# LabFriendMain1.net
KiCad netlist of a schematic drawn in EAGLE
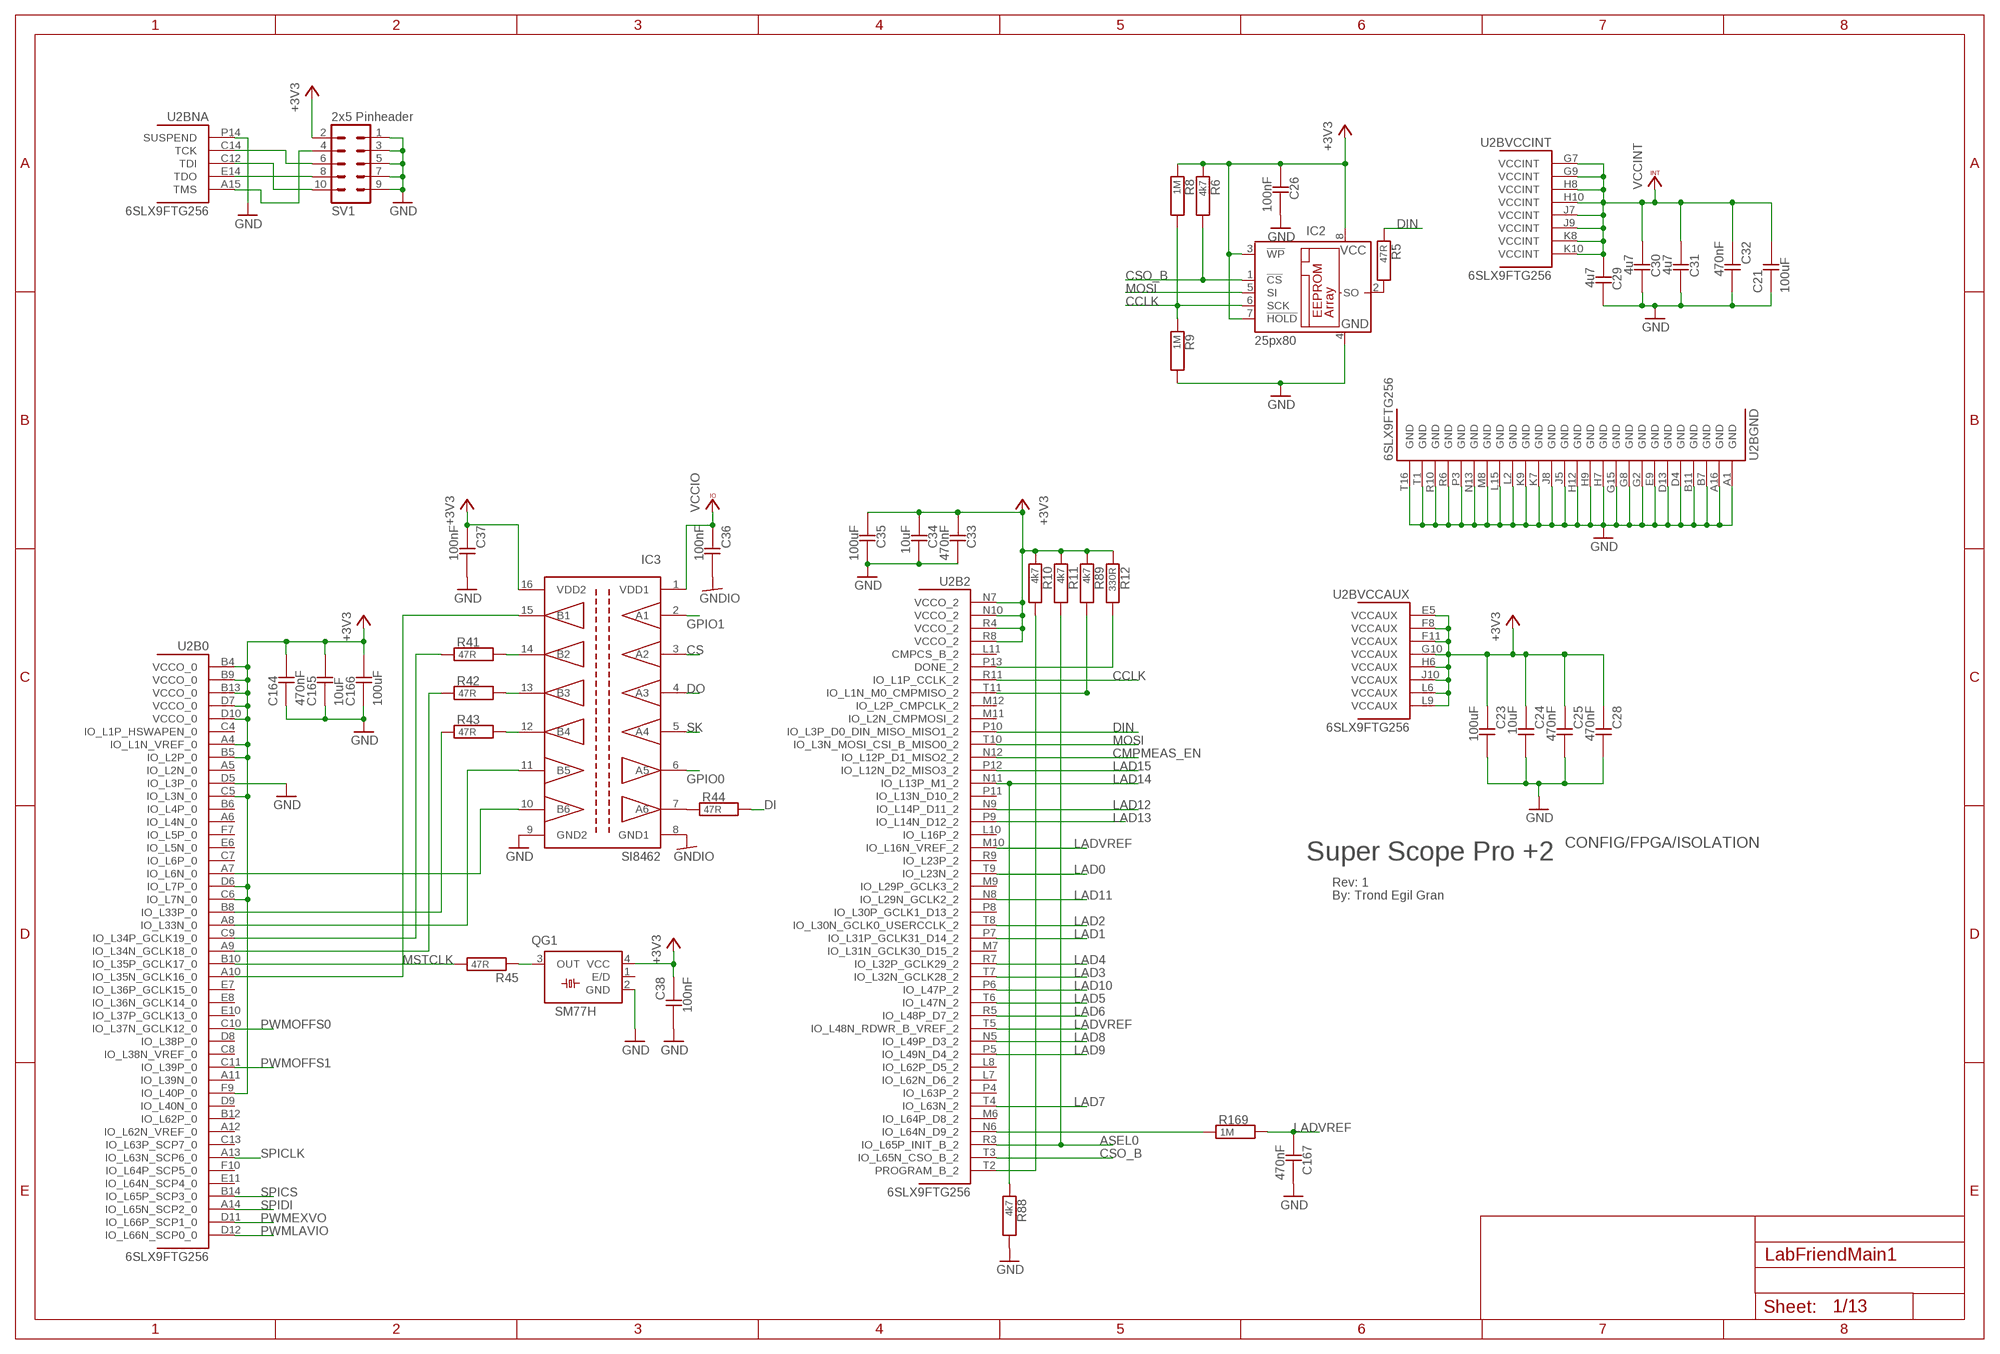
[diagram p0: schematic, sheet 1]
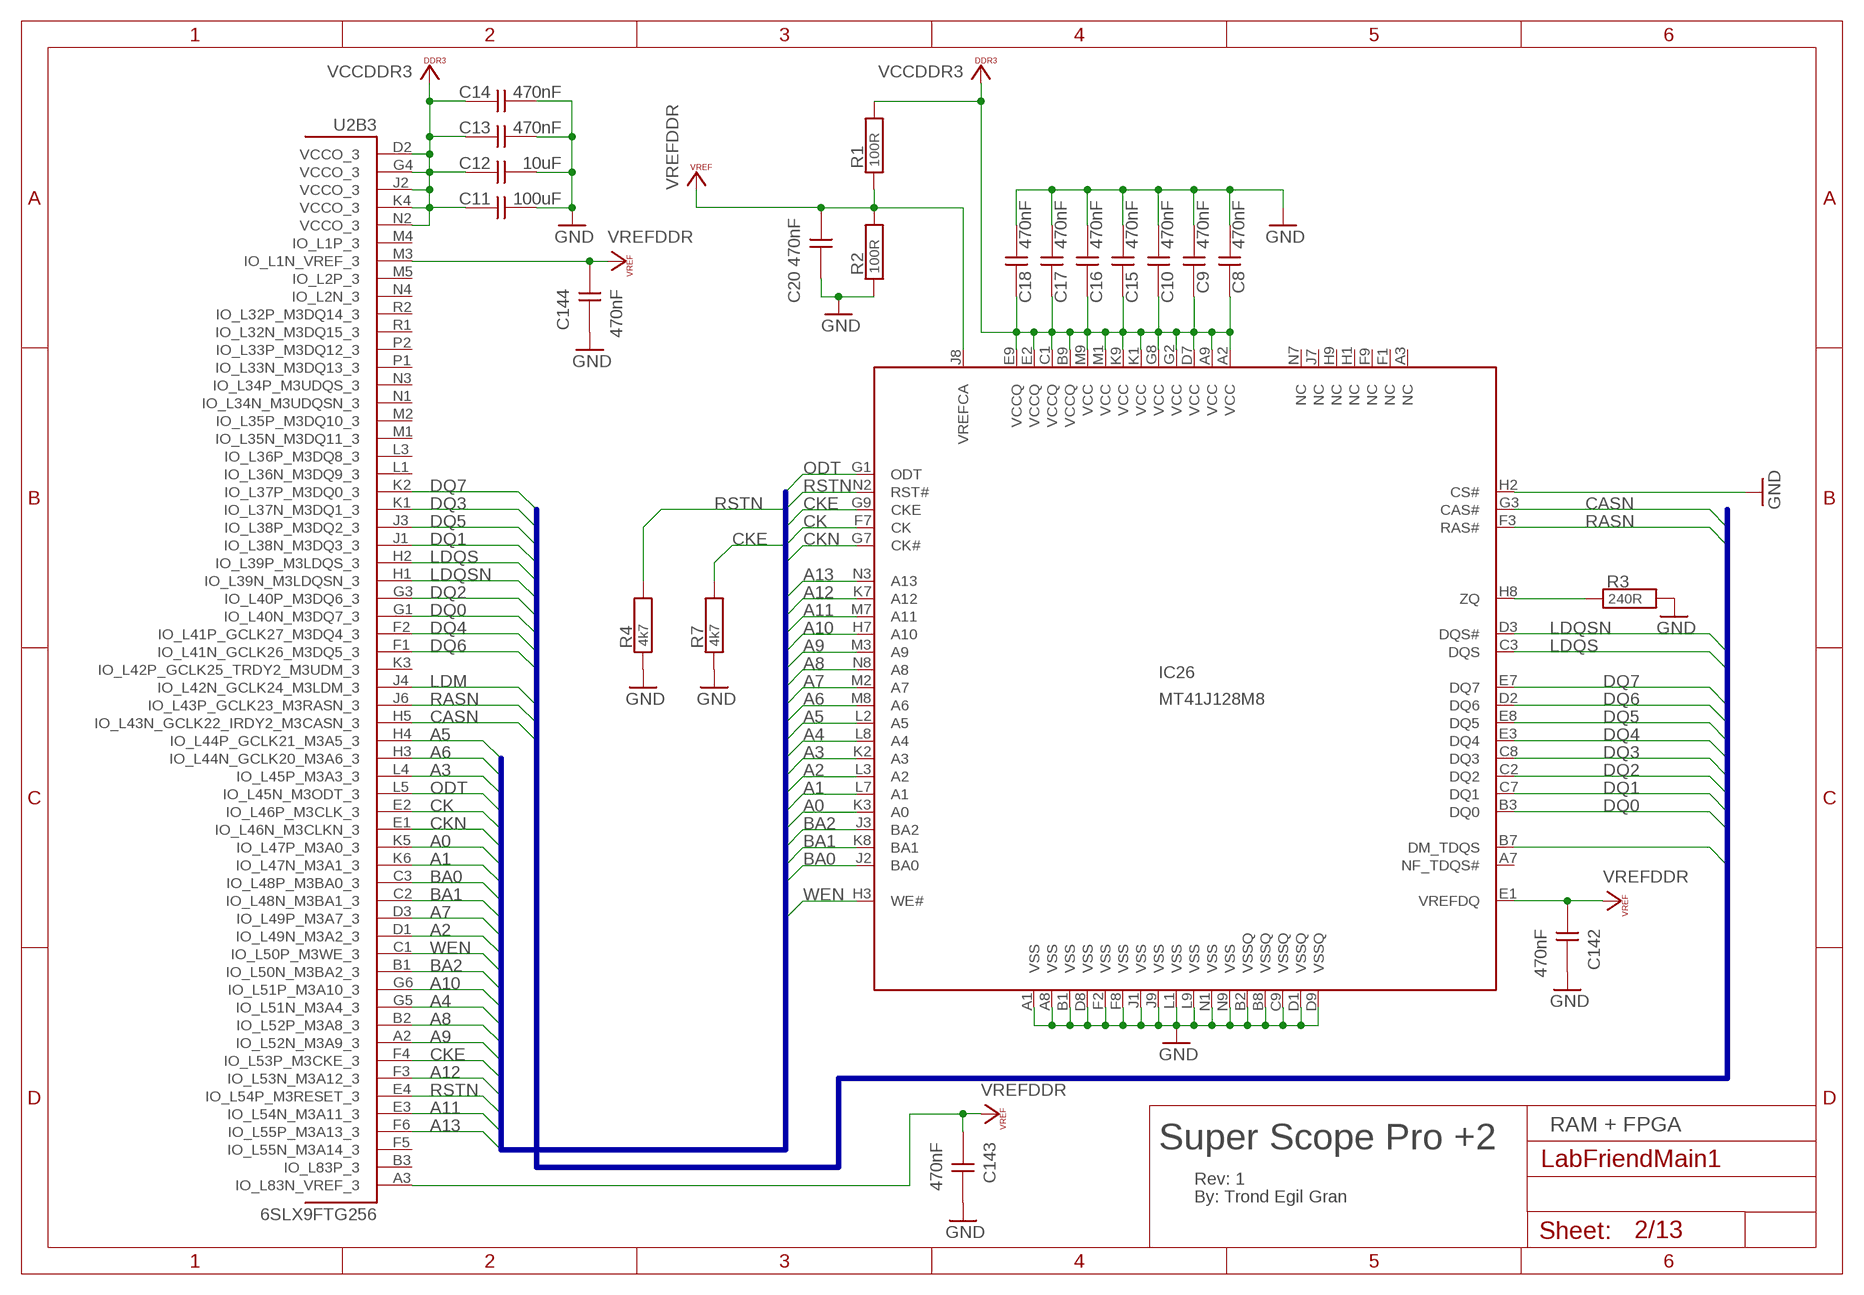
[diagram p1: schematic, sheet 2]
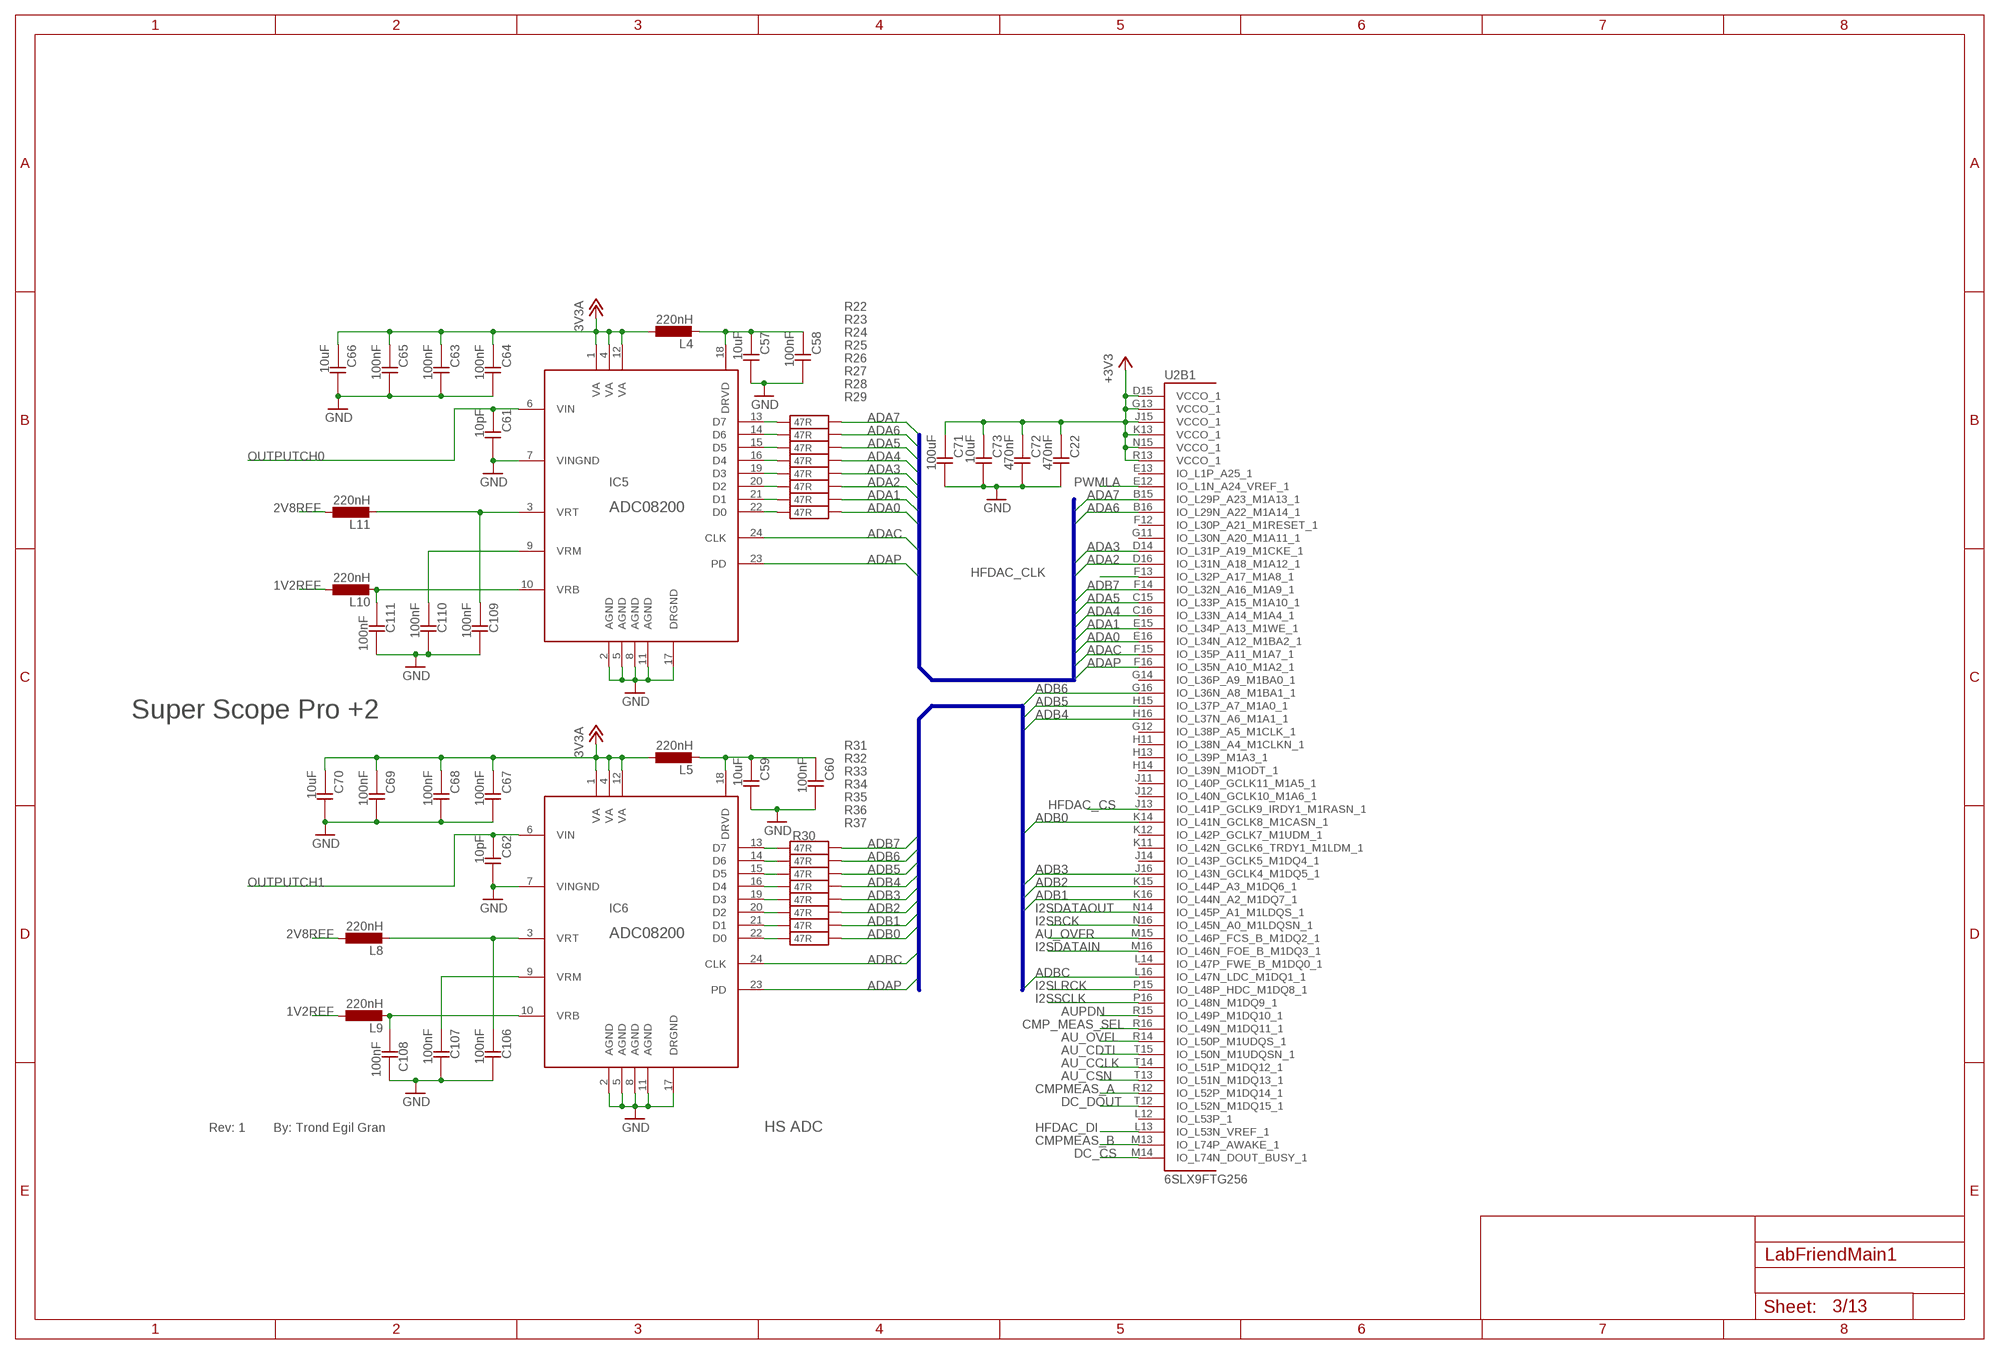
[diagram p2: schematic, sheet 3]
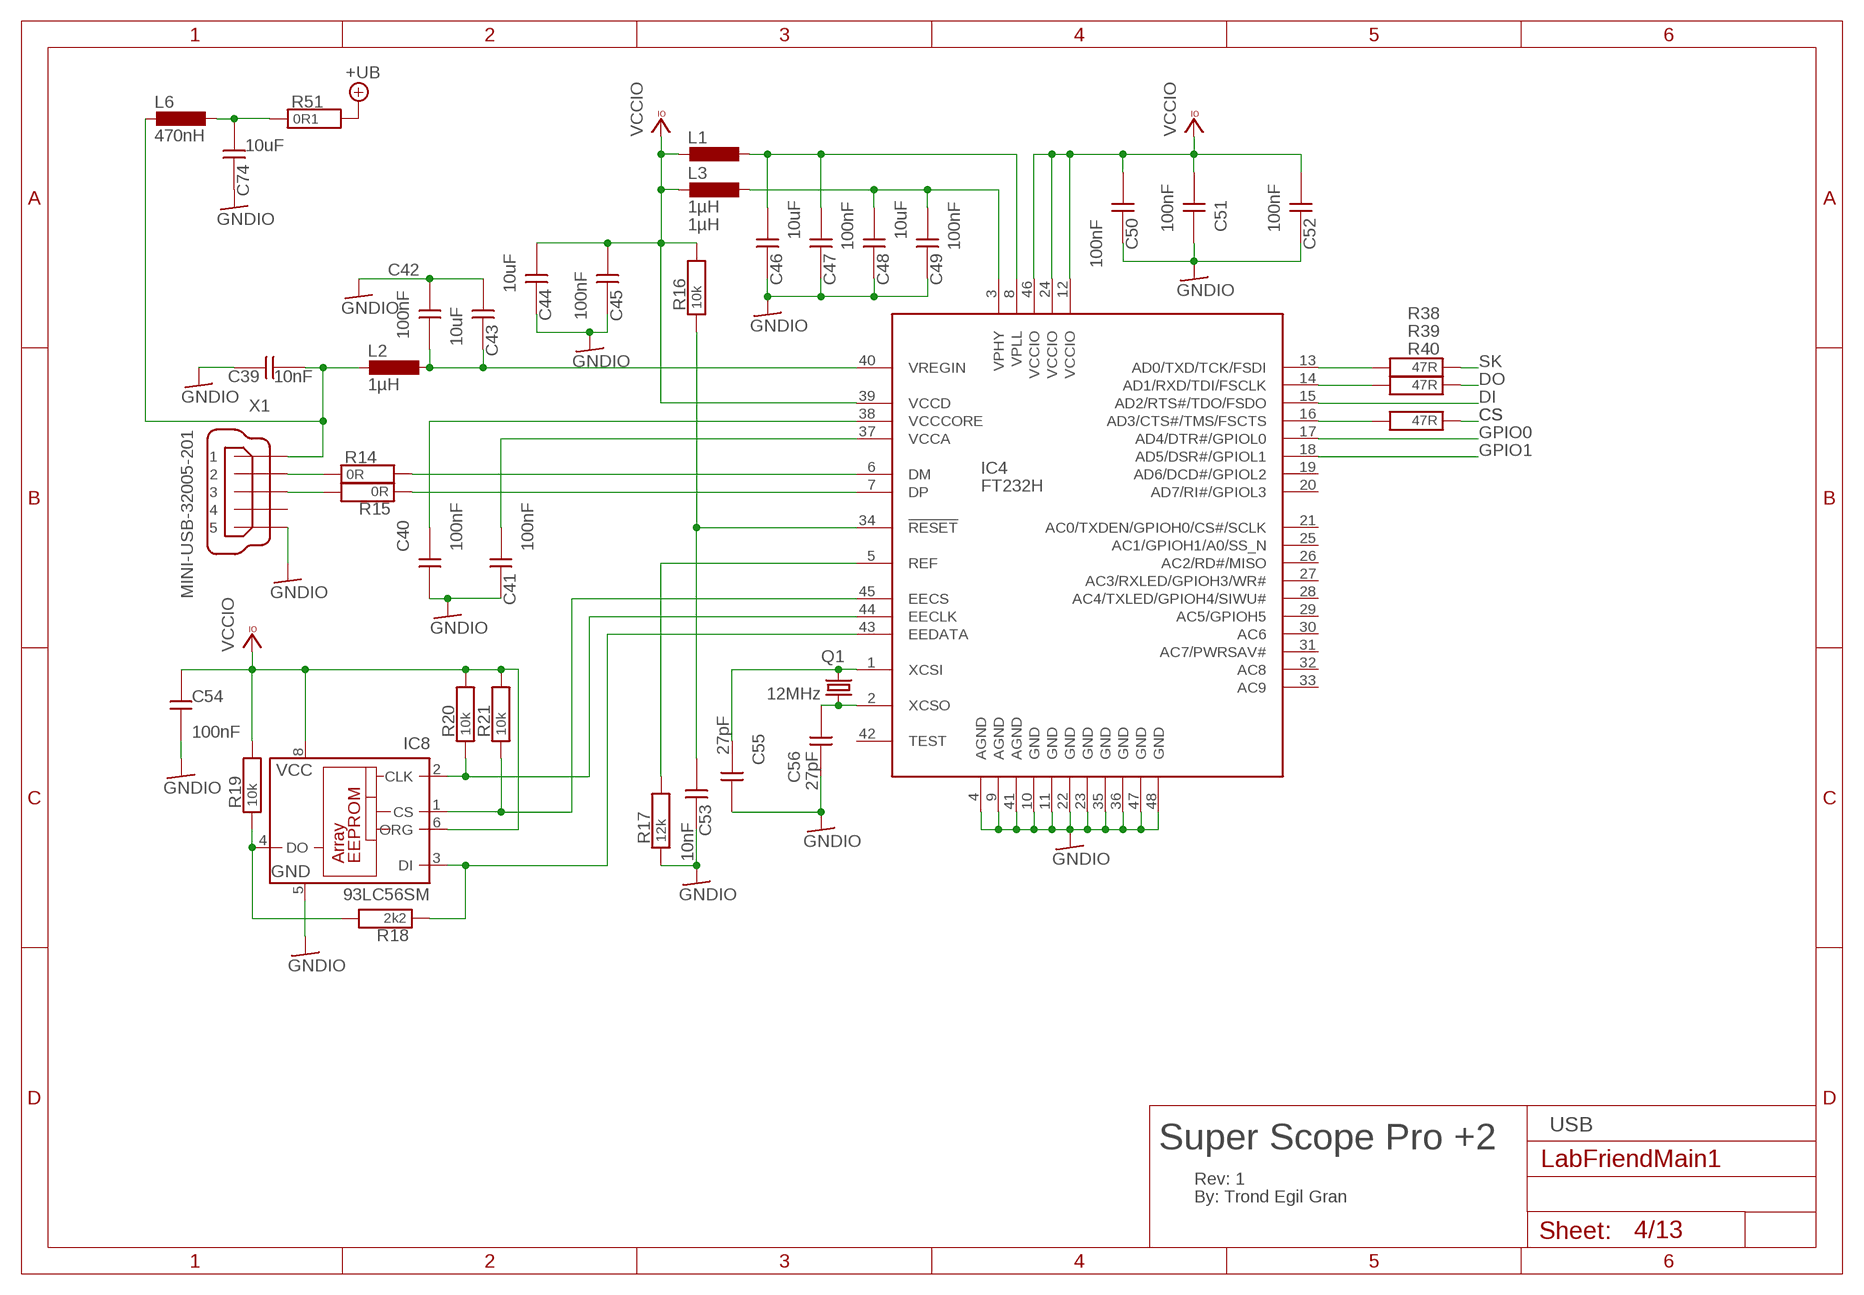
[diagram p3: schematic, sheet 4]
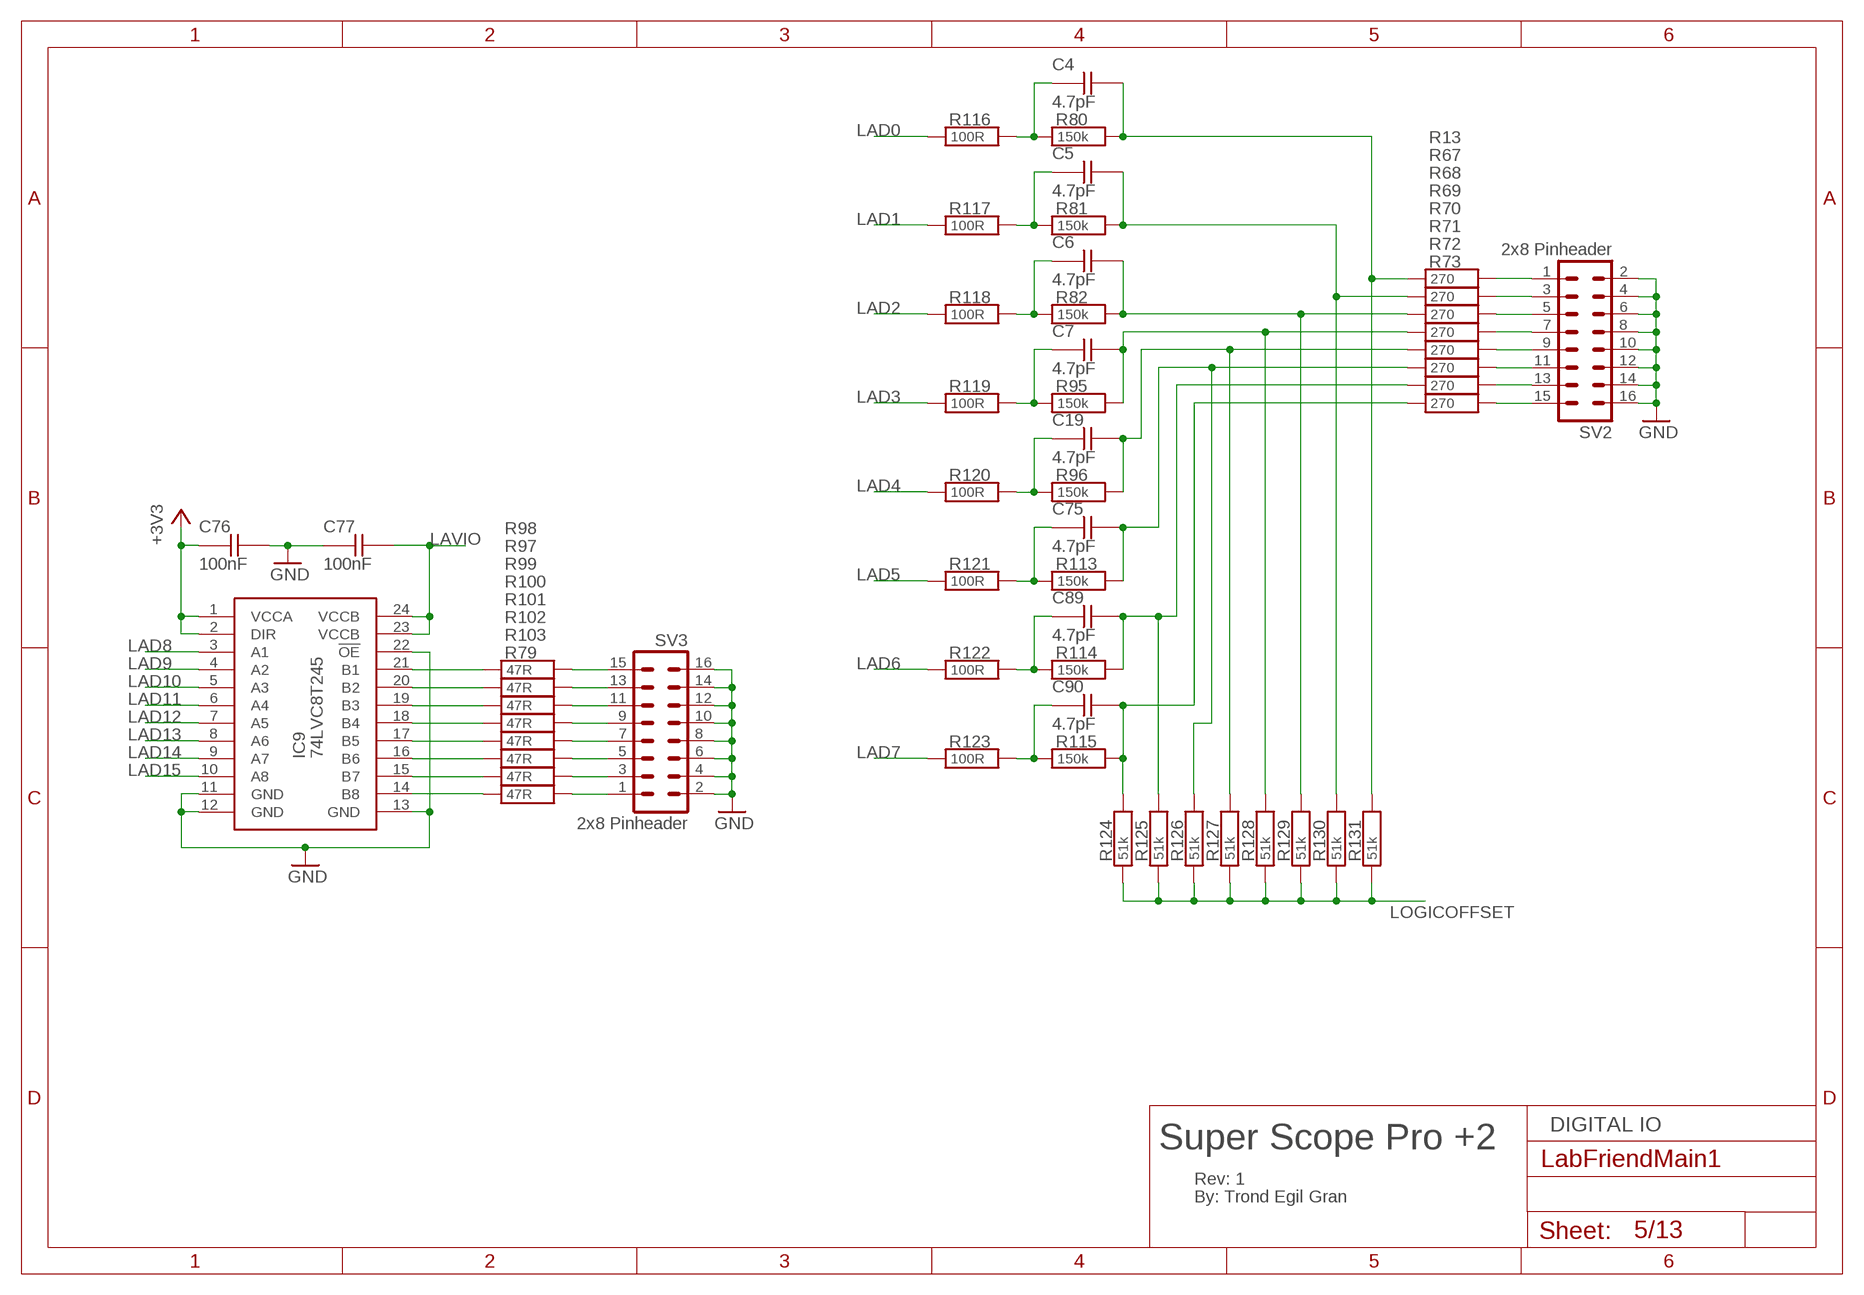
[diagram p4: schematic, sheet 5]
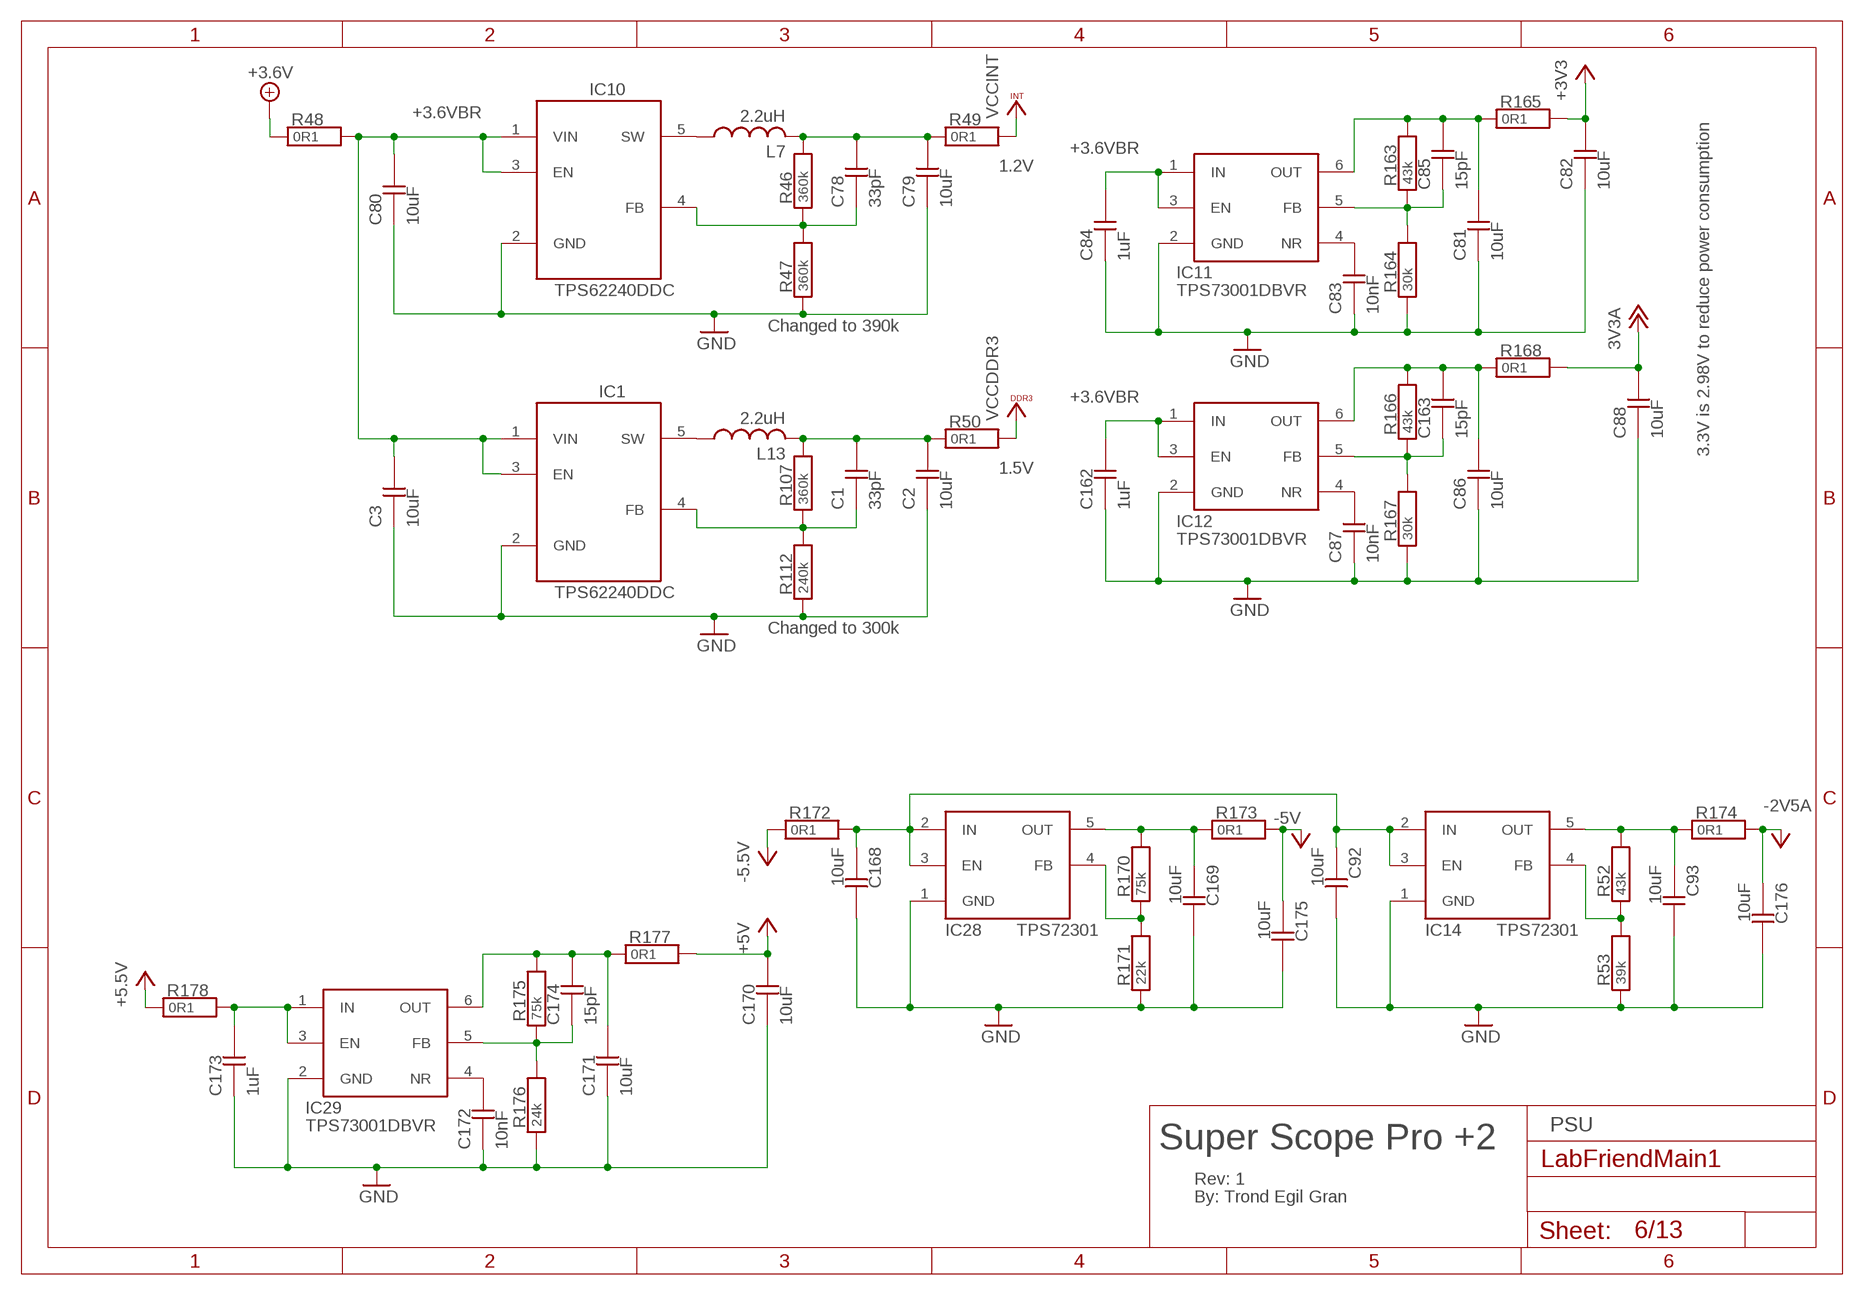
[diagram p5: schematic, sheet 6]
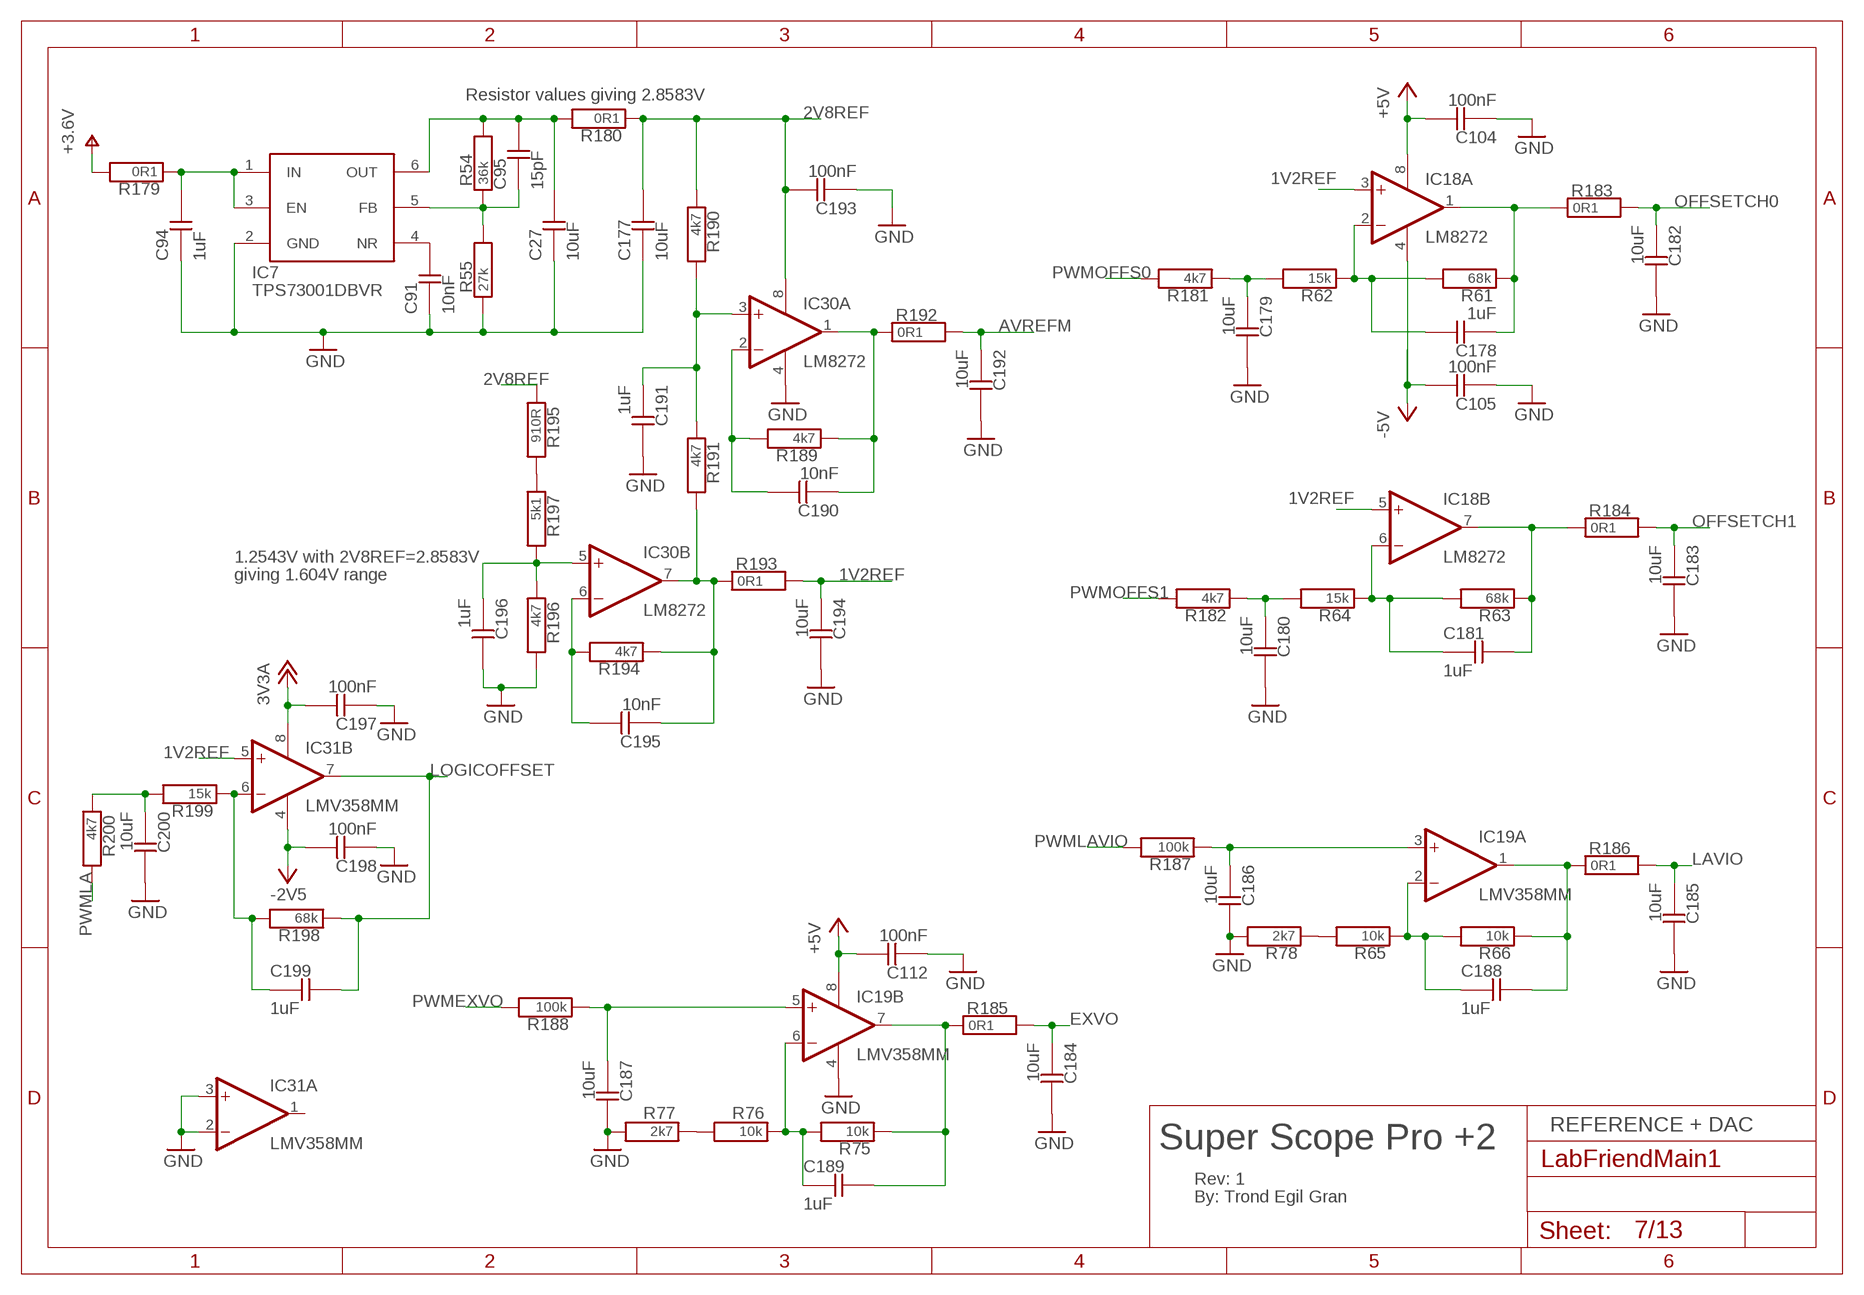
[diagram p6: schematic, sheet 7]
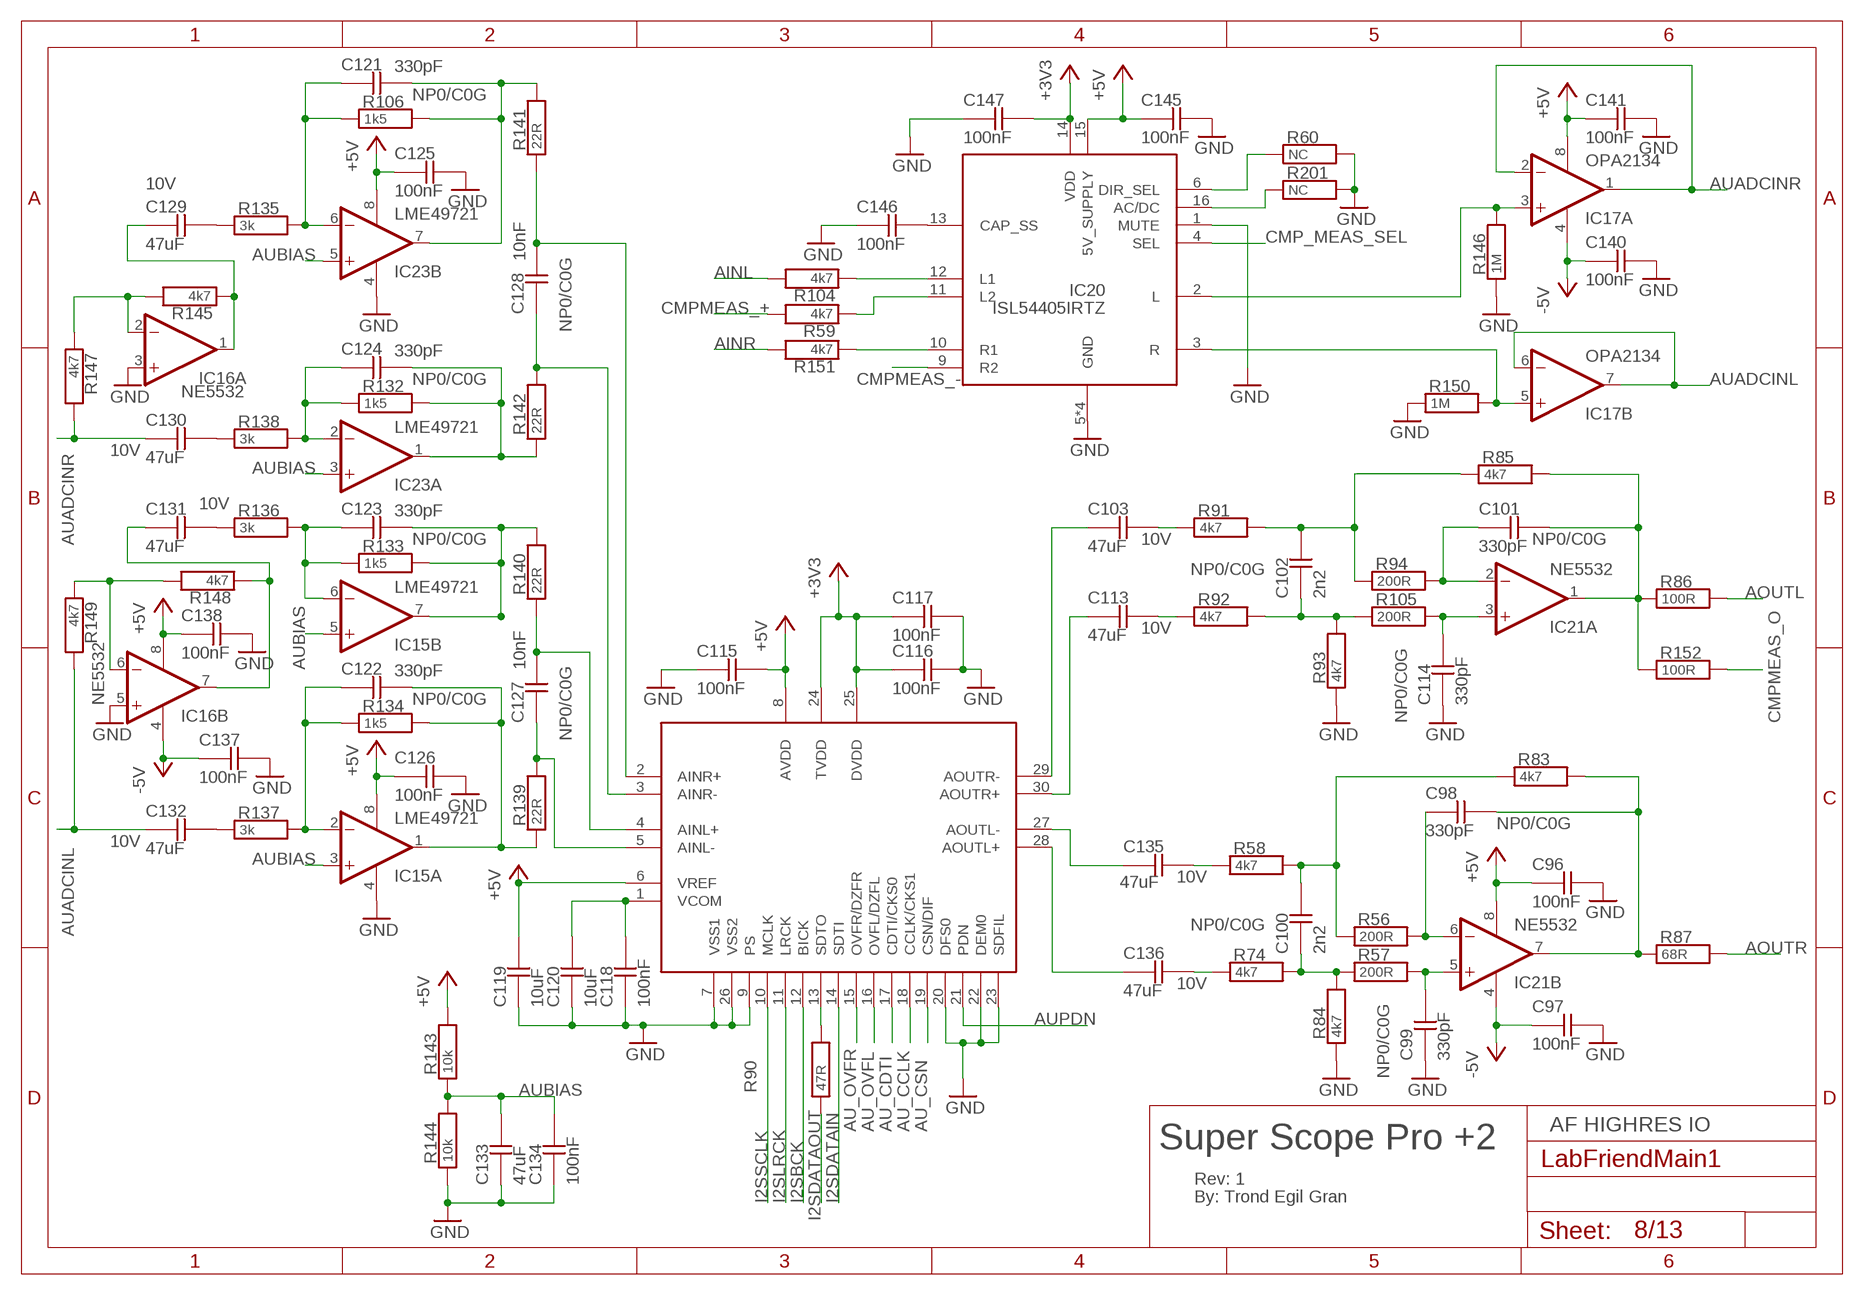
[diagram p7: schematic, sheet 8]
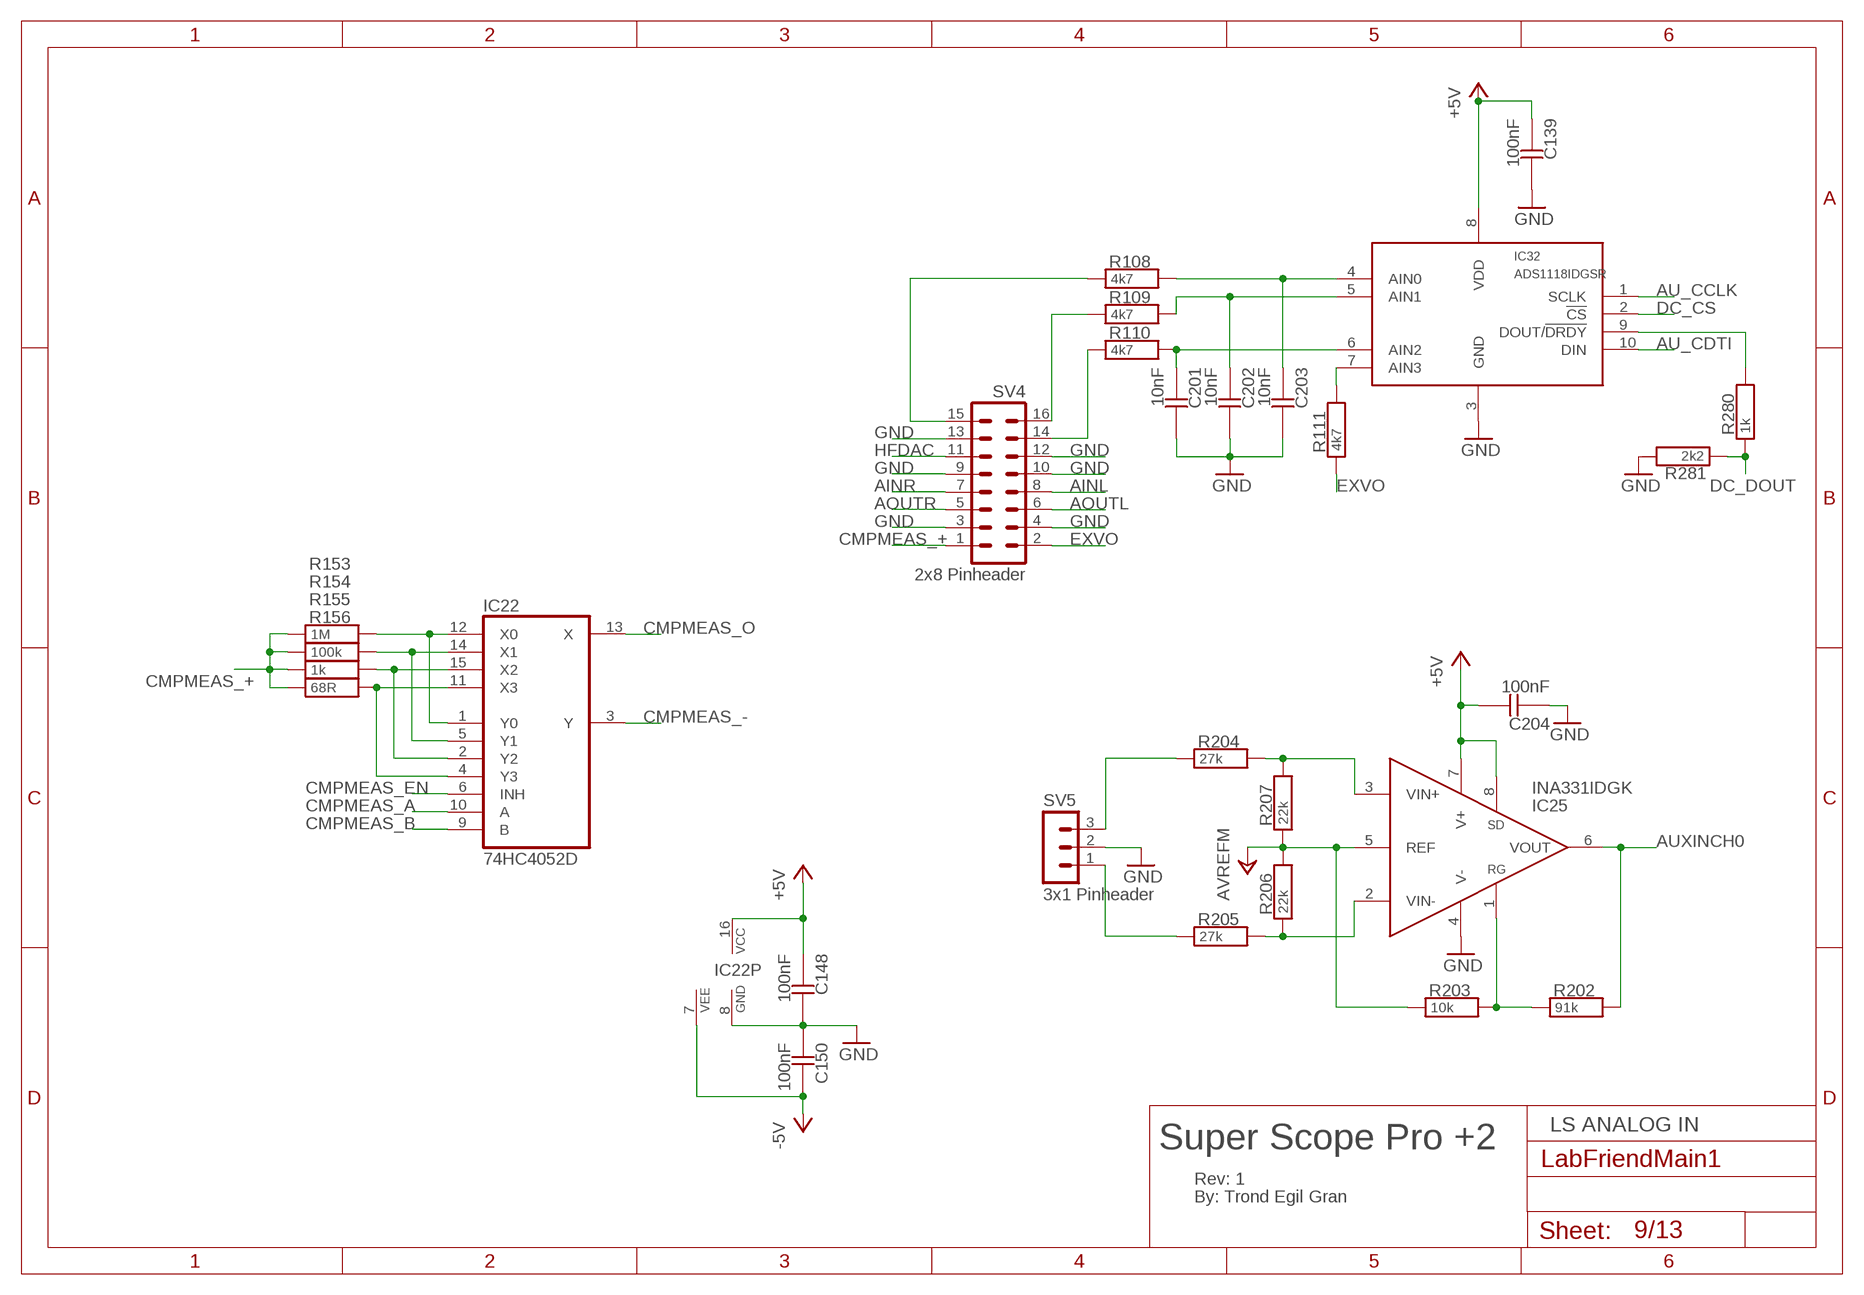
[diagram p8: schematic, sheet 9]
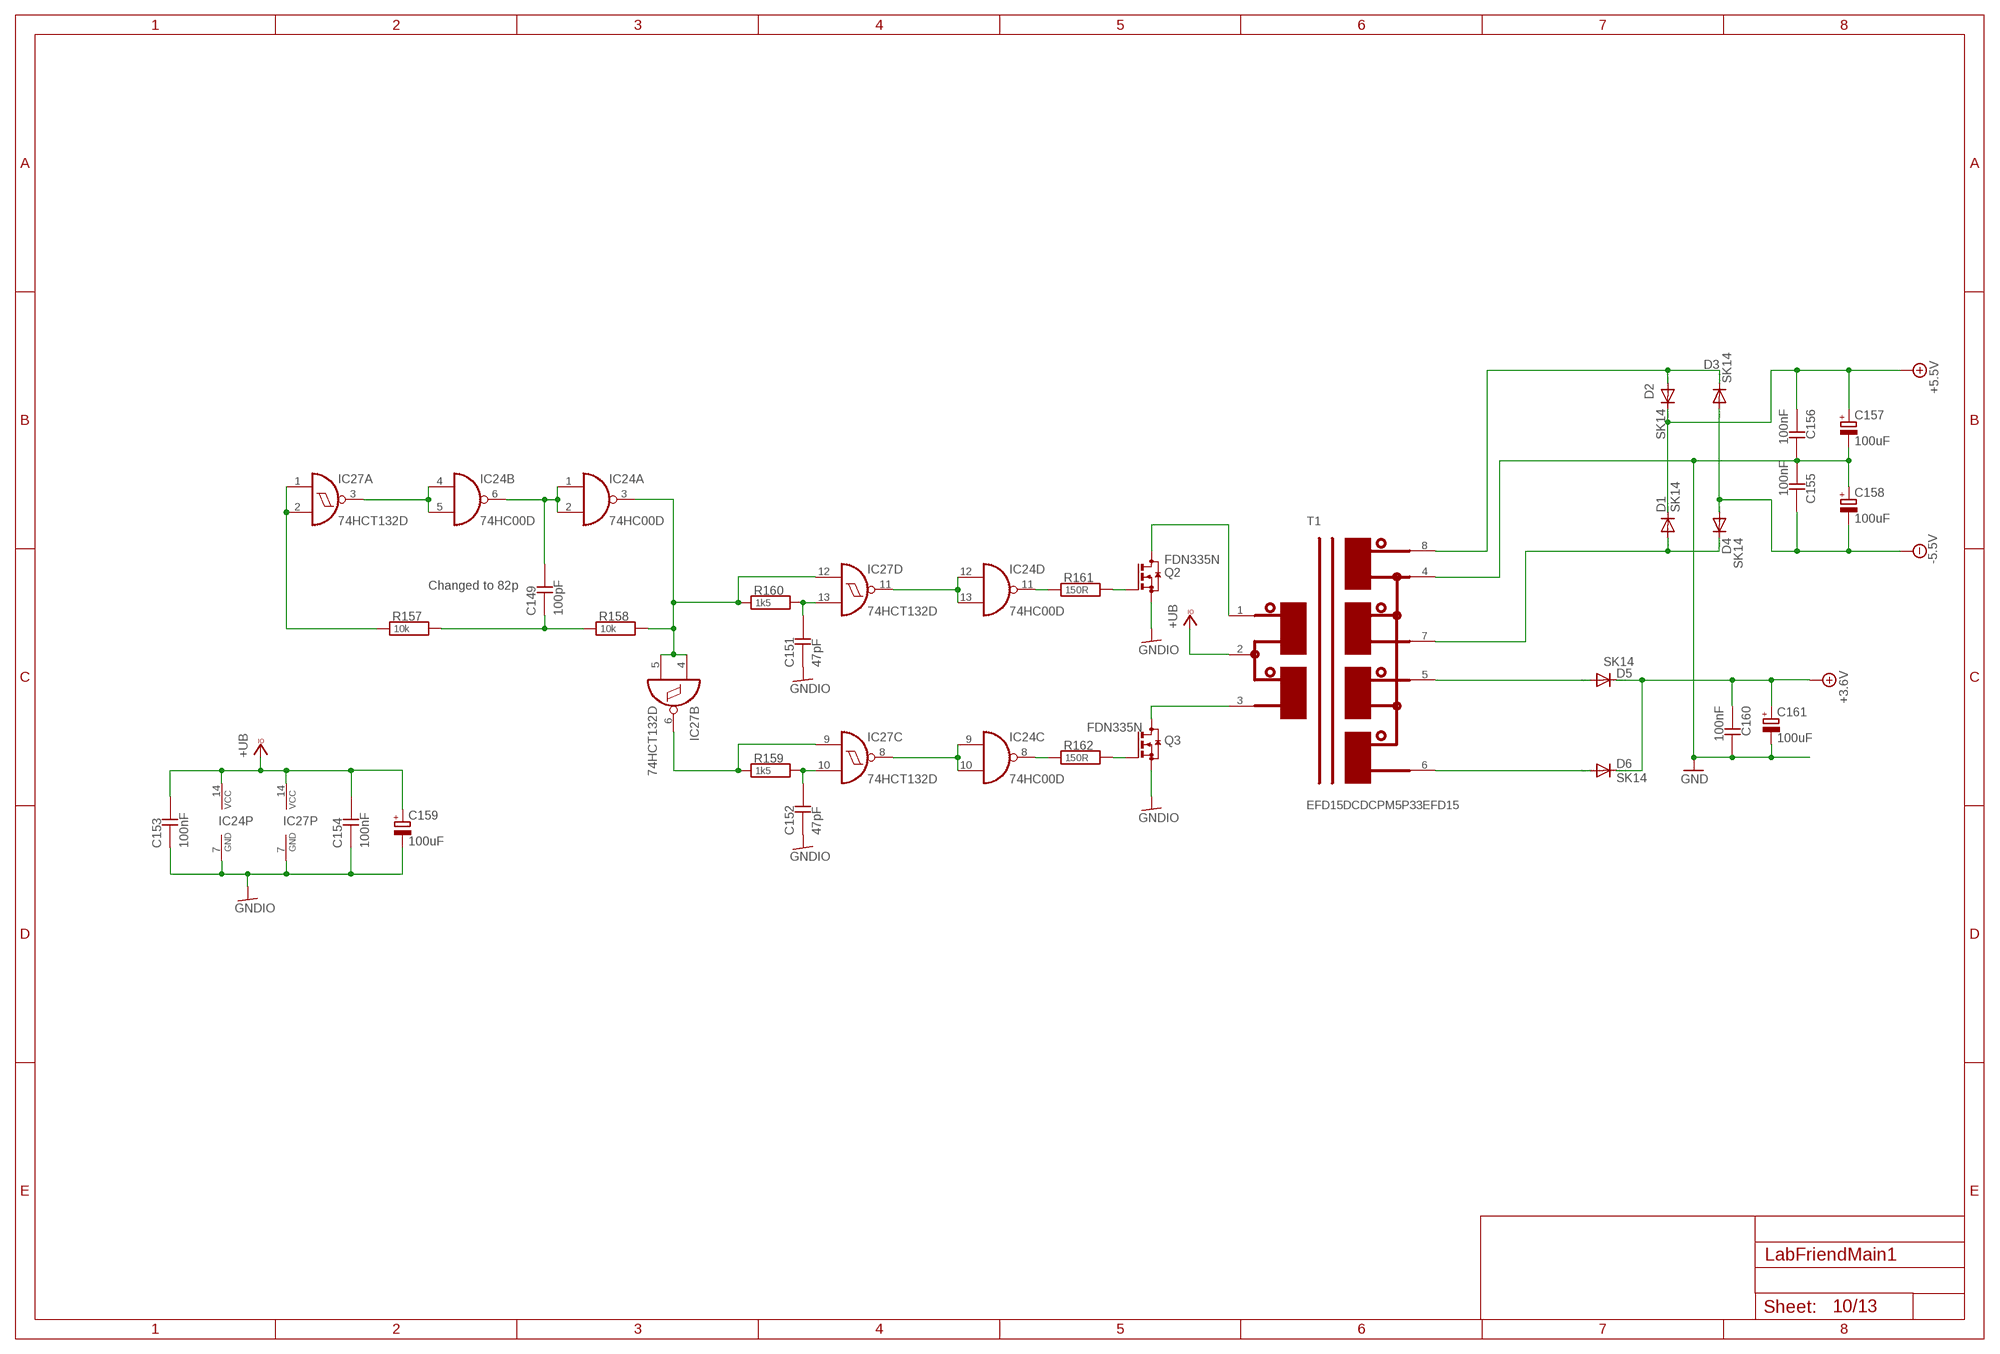
[diagram p9: schematic, sheet 10]
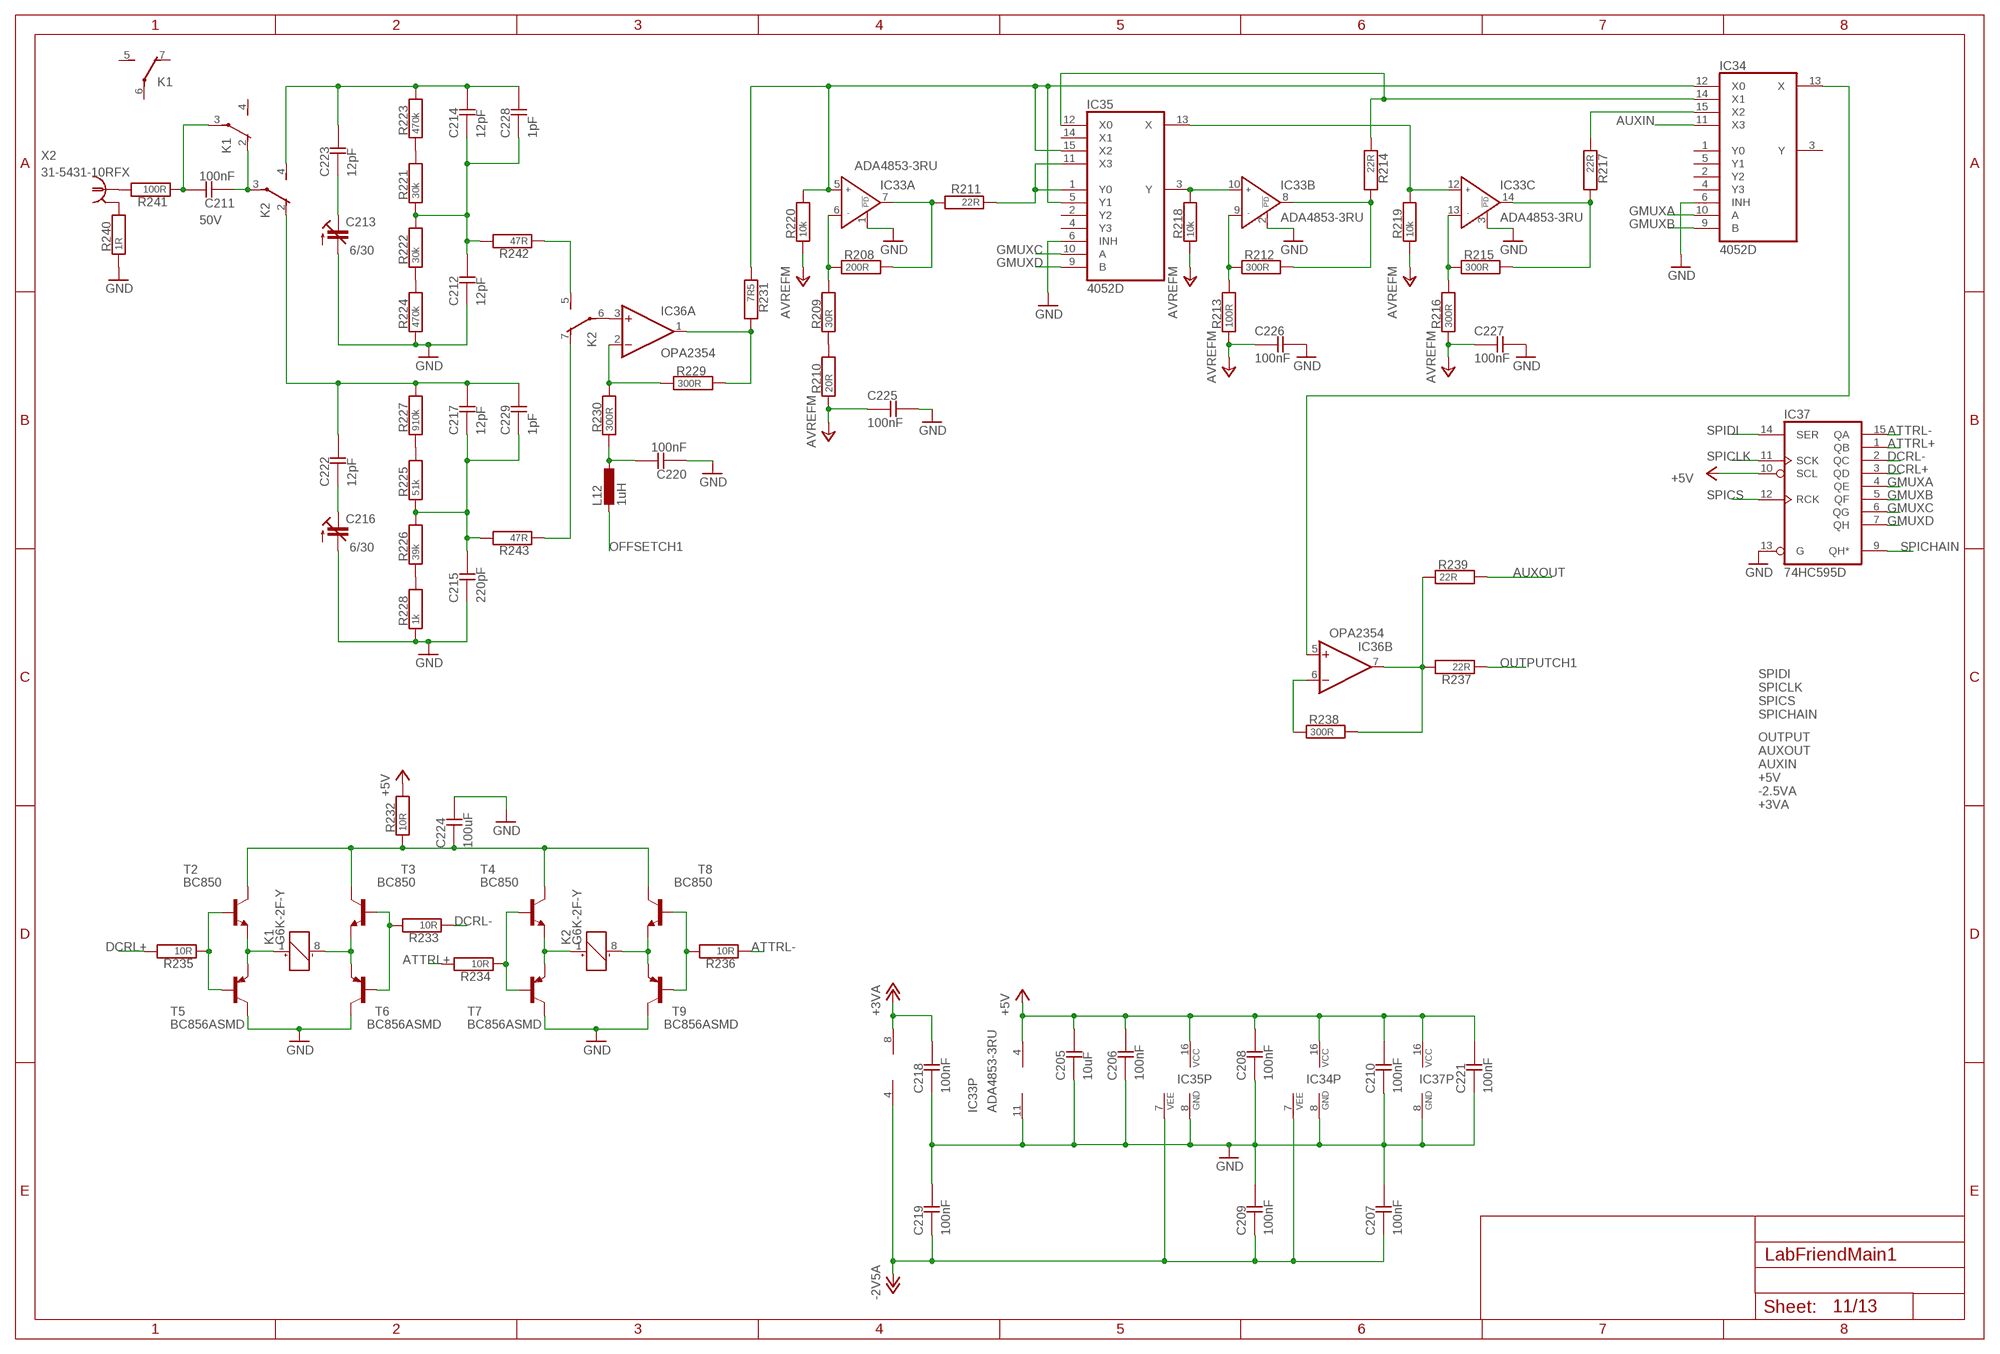
[diagram p10: schematic, sheet 11]
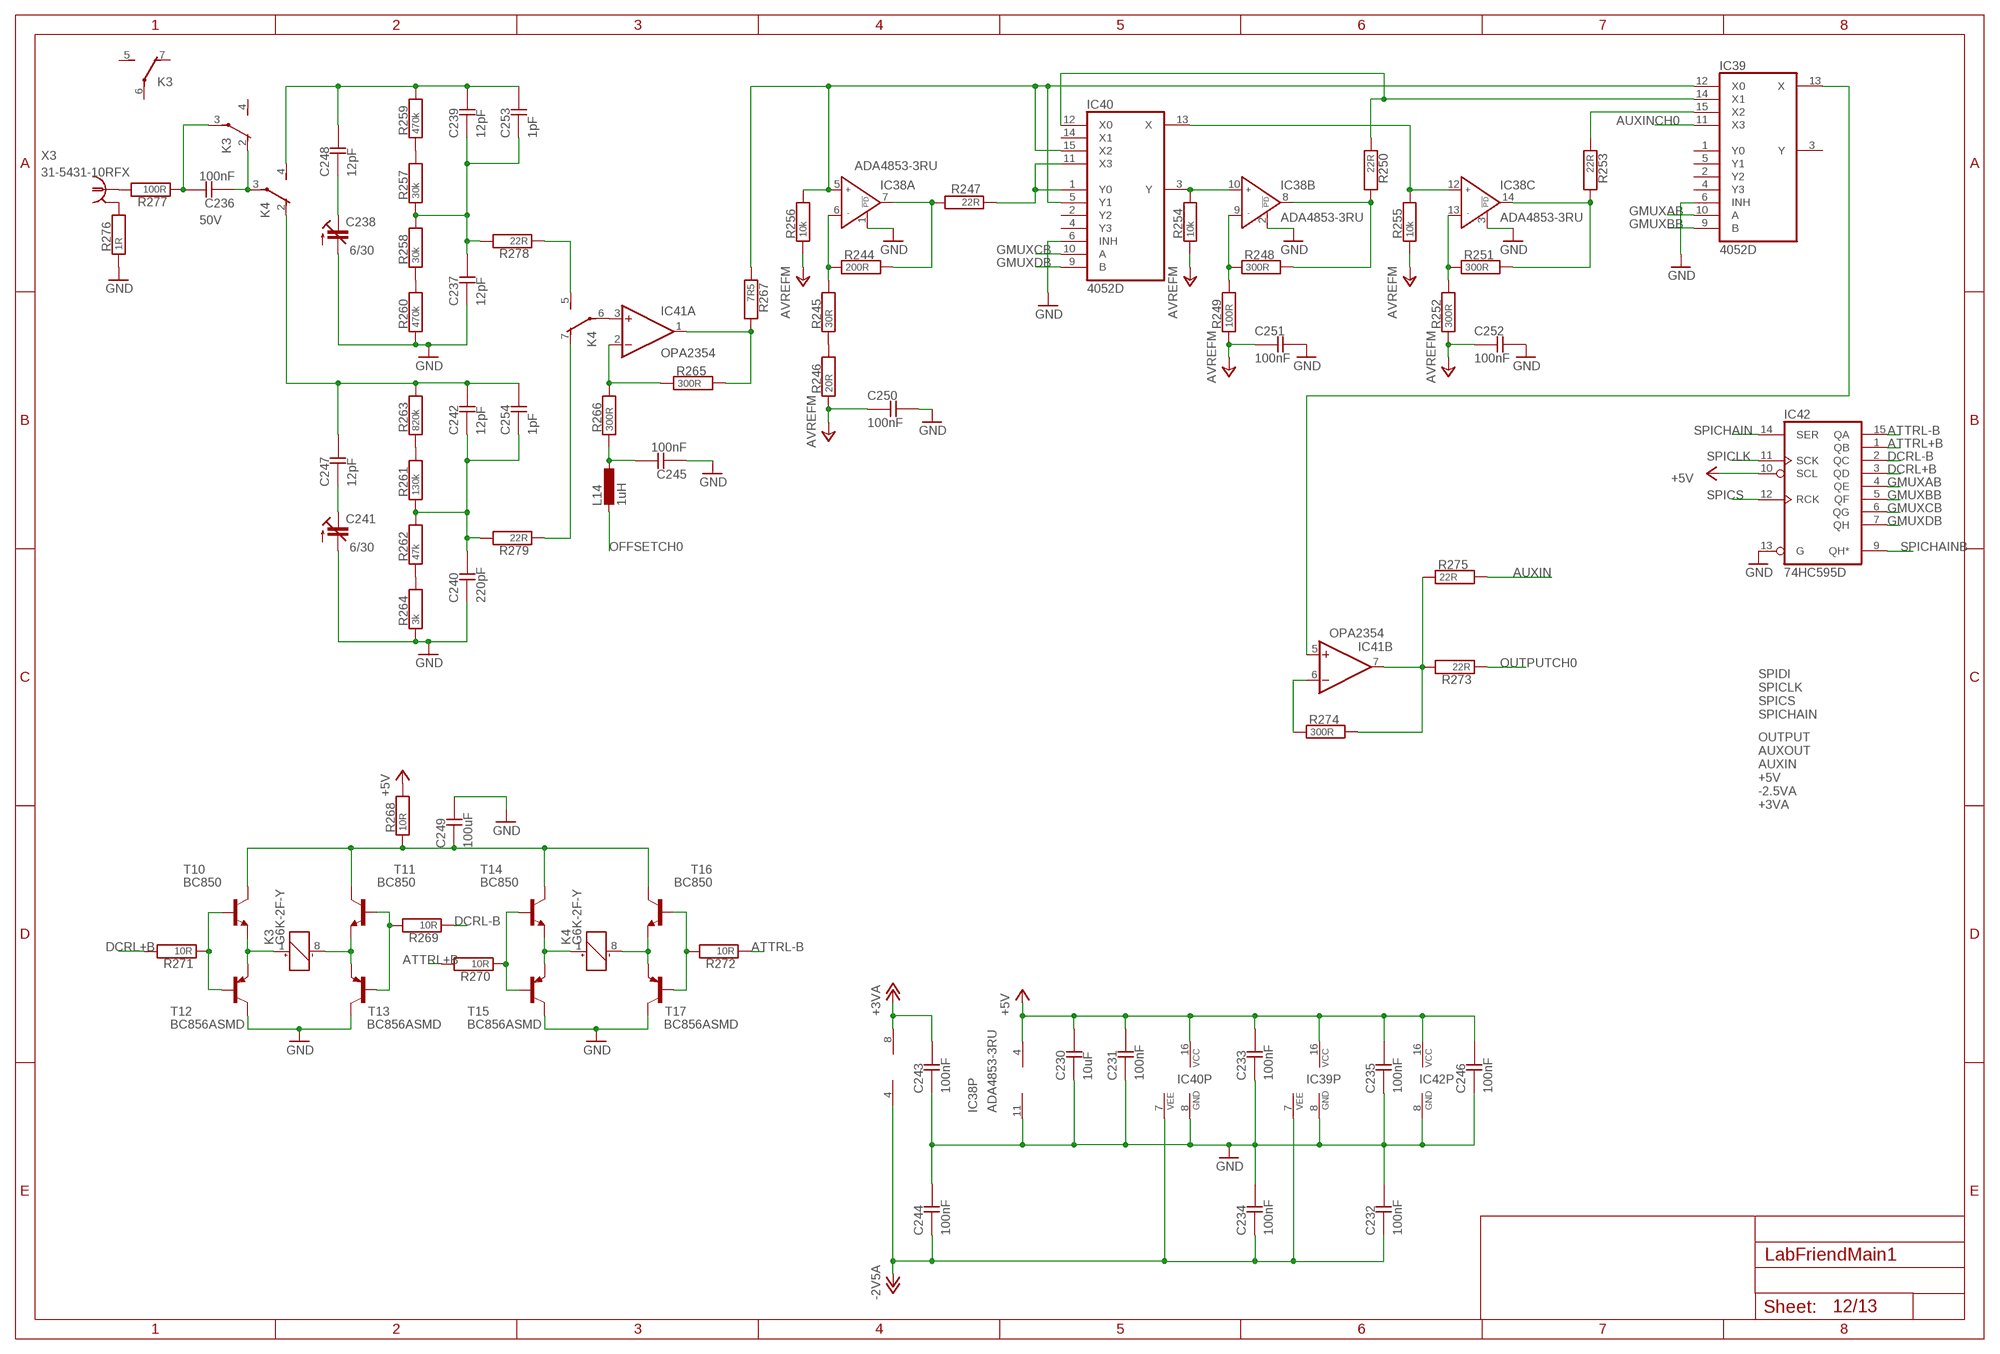
[diagram p11: schematic, sheet 12]
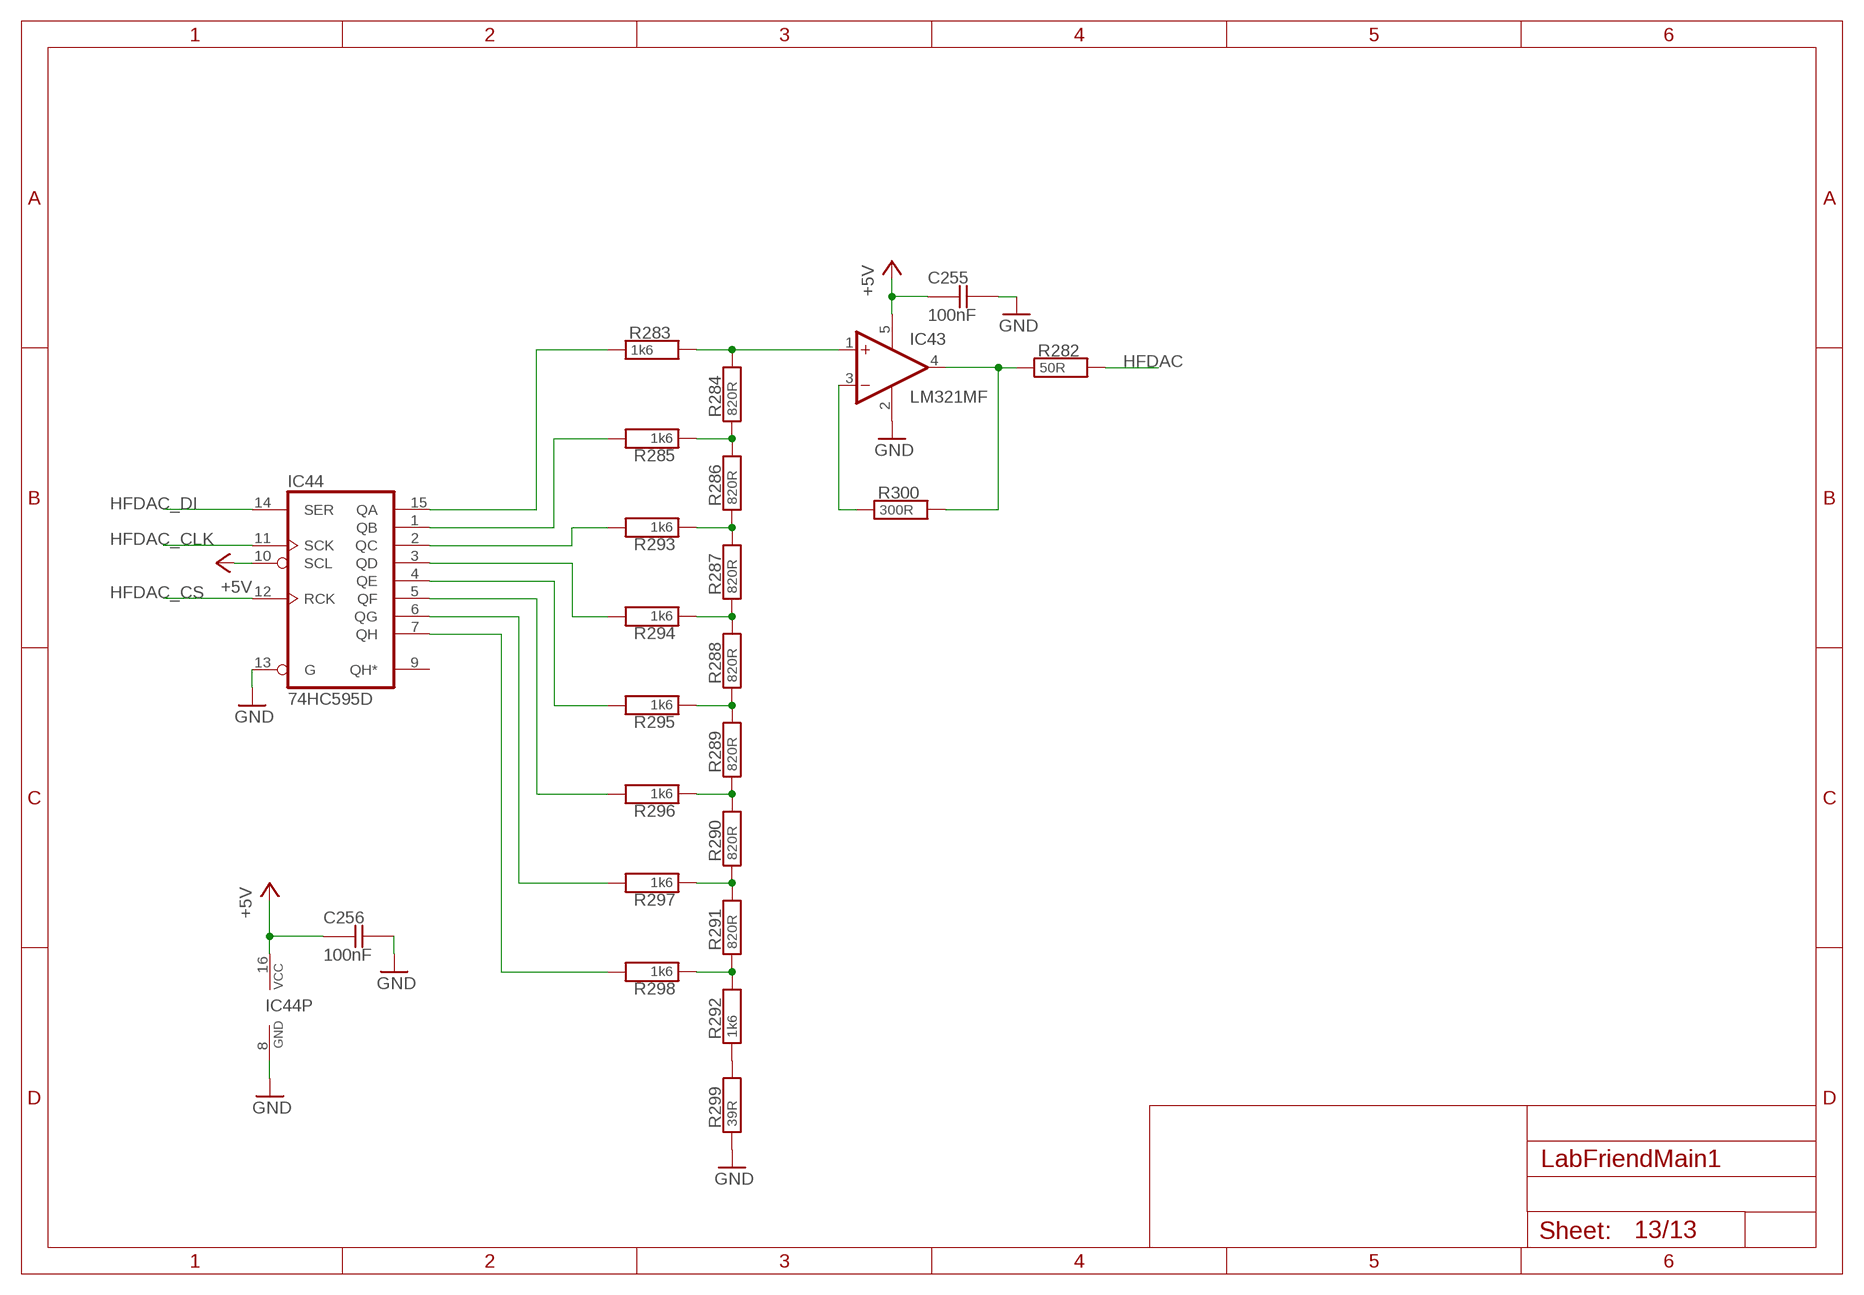
[diagram p12: schematic, sheet 13]

(export (version "E")
  (design (tool "Eeschema 10.0.6"))
  (components
    (comp (ref "C27")
      (value "10uF")
      (footprint "eagle-import:0603")
      (libsource (lib "eagle-import") (part "CAPC0603"))
    )
    (comp (ref "C91")
      (value "10nF")
      (footprint "eagle-import:0402")
      (libsource (lib "eagle-import") (part "CAPC0402"))
    )
    (comp (ref "C94")
      (value "1uF")
      (footprint "eagle-import:0603")
      (libsource (lib "eagle-import") (part "CAPC0603"))
    )
    (comp (ref "C95")
      (value "15pF")
      (footprint "eagle-import:0603")
      (libsource (lib "eagle-import") (part "CAPC0603"))
    )
    (comp (ref "C104")
      (value "100nF")
      (footprint "eagle-import:0402")
      (libsource (lib "eagle-import") (part "CAPC0402"))
    )
    (comp (ref "C105")
      (value "100nF")
      (footprint "eagle-import:0402")
      (libsource (lib "eagle-import") (part "CAPC0402"))
    )
    (comp (ref "C112")
      (value "100nF")
      (footprint "eagle-import:0402")
      (libsource (lib "eagle-import") (part "CAPC0402"))
    )
    (comp (ref "C177")
      (value "10uF")
      (footprint "eagle-import:0603")
      (libsource (lib "eagle-import") (part "CAPC0603"))
    )
    (comp (ref "C178")
      (value "1uF")
      (footprint "eagle-import:0603")
      (libsource (lib "eagle-import") (part "CAPC0603"))
    )
    (comp (ref "C179")
      (value "10uF")
      (footprint "eagle-import:0603")
      (libsource (lib "eagle-import") (part "CAPC0603"))
    )
    (comp (ref "C180")
      (value "10uF")
      (footprint "eagle-import:0603")
      (libsource (lib "eagle-import") (part "CAPC0603"))
    )
    (comp (ref "C181")
      (value "1uF")
      (footprint "eagle-import:0603")
      (libsource (lib "eagle-import") (part "CAPC0603"))
    )
    (comp (ref "C182")
      (value "10uF")
      (footprint "eagle-import:0603")
      (libsource (lib "eagle-import") (part "CAPC0603"))
    )
    (comp (ref "C183")
      (value "10uF")
      (footprint "eagle-import:0603")
      (libsource (lib "eagle-import") (part "CAPC0603"))
    )
    (comp (ref "C184")
      (value "10uF")
      (footprint "eagle-import:0603")
      (libsource (lib "eagle-import") (part "CAPC0603"))
    )
    (comp (ref "C185")
      (value "10uF")
      (footprint "eagle-import:0603")
      (libsource (lib "eagle-import") (part "CAPC0603"))
    )
    (comp (ref "C186")
      (value "10uF")
      (footprint "eagle-import:0603")
      (libsource (lib "eagle-import") (part "CAPC0603"))
    )
    (comp (ref "C187")
      (value "10uF")
      (footprint "eagle-import:0603")
      (libsource (lib "eagle-import") (part "CAPC0603"))
    )
    (comp (ref "C188")
      (value "1uF")
      (footprint "eagle-import:0603")
      (libsource (lib "eagle-import") (part "CAPC0603"))
    )
    (comp (ref "C189")
      (value "1uF")
      (footprint "eagle-import:0603")
      (libsource (lib "eagle-import") (part "CAPC0603"))
    )
    (comp (ref "C190")
      (value "10nF")
      (footprint "eagle-import:0402")
      (libsource (lib "eagle-import") (part "CAPC0402"))
    )
    (comp (ref "C191")
      (value "1uF")
      (footprint "eagle-import:0603")
      (libsource (lib "eagle-import") (part "CAPC0603"))
    )
    (comp (ref "C192")
      (value "10uF")
      (footprint "eagle-import:0603")
      (libsource (lib "eagle-import") (part "CAPC0603"))
    )
    (comp (ref "C193")
      (value "100nF")
      (footprint "eagle-import:0402")
      (libsource (lib "eagle-import") (part "CAPC0402"))
    )
    (comp (ref "C194")
      (value "10uF")
      (footprint "eagle-import:0603")
      (libsource (lib "eagle-import") (part "CAPC0603"))
    )
    (comp (ref "C195")
      (value "10nF")
      (footprint "eagle-import:0402")
      (libsource (lib "eagle-import") (part "CAPC0402"))
    )
    (comp (ref "C196")
      (value "1uF")
      (footprint "eagle-import:0603")
      (libsource (lib "eagle-import") (part "CAPC0603"))
    )
    (comp (ref "C197")
      (value "100nF")
      (footprint "eagle-import:0402")
      (libsource (lib "eagle-import") (part "CAPC0402"))
    )
    (comp (ref "C198")
      (value "100nF")
      (footprint "eagle-import:0402")
      (libsource (lib "eagle-import") (part "CAPC0402"))
    )
    (comp (ref "C199")
      (value "1uF")
      (footprint "eagle-import:0603")
      (libsource (lib "eagle-import") (part "CAPC0603"))
    )
    (comp (ref "C200")
      (value "10uF")
      (footprint "eagle-import:0603")
      (libsource (lib "eagle-import") (part "CAPC0603"))
    )
    (comp (ref "IC7")
      (value "TPS73001DBVR")
      (footprint "eagle-import:SOT23-6L")
      (libsource (lib "eagle-import") (part "TPS73001"))
    )
    (comp (ref "IC18")
      (value "LM8272")
      (footprint "eagle-import:MSOP08")
      (libsource (lib "eagle-import") (part "LMV358?MM"))
    )
    (comp (ref "IC19")
      (value "LMV358MM")
      (footprint "eagle-import:MSOP08")
      (libsource (lib "eagle-import") (part "LMV358?MM"))
    )
    (comp (ref "IC30")
      (value "LM8272")
      (footprint "eagle-import:MSOP08")
      (libsource (lib "eagle-import") (part "LMV358?MM"))
    )
    (comp (ref "IC31")
      (value "LMV358MM")
      (footprint "eagle-import:MSOP08")
      (libsource (lib "eagle-import") (part "LMV358?MM"))
    )
    (comp (ref "R54")
      (value "36k")
      (footprint "eagle-import:0603")
      (libsource (lib "eagle-import") (part "RESR0603"))
    )
    (comp (ref "R55")
      (value "27k")
      (footprint "eagle-import:0603")
      (libsource (lib "eagle-import") (part "RESR0603"))
    )
    (comp (ref "R61")
      (value "68k")
      (footprint "eagle-import:0603")
      (libsource (lib "eagle-import") (part "RESR0603"))
    )
    (comp (ref "R62")
      (value "15k")
      (footprint "eagle-import:0603")
      (libsource (lib "eagle-import") (part "RESR0603"))
    )
    (comp (ref "R63")
      (value "68k")
      (footprint "eagle-import:0603")
      (libsource (lib "eagle-import") (part "RESR0603"))
    )
    (comp (ref "R64")
      (value "15k")
      (footprint "eagle-import:0603")
      (libsource (lib "eagle-import") (part "RESR0603"))
    )
    (comp (ref "R65")
      (value "10k")
      (footprint "eagle-import:0603")
      (libsource (lib "eagle-import") (part "RESR0603"))
    )
    (comp (ref "R66")
      (value "10k")
      (footprint "eagle-import:0603")
      (libsource (lib "eagle-import") (part "RESR0603"))
    )
    (comp (ref "R75")
      (value "10k")
      (footprint "eagle-import:0603")
      (libsource (lib "eagle-import") (part "RESR0603"))
    )
    (comp (ref "R76")
      (value "10k")
      (footprint "eagle-import:0603")
      (libsource (lib "eagle-import") (part "RESR0603"))
    )
    (comp (ref "R77")
      (value "2k7")
      (footprint "eagle-import:0603")
      (libsource (lib "eagle-import") (part "RESR0603"))
    )
    (comp (ref "R78")
      (value "2k7")
      (footprint "eagle-import:0603")
      (libsource (lib "eagle-import") (part "RESR0603"))
    )
    (comp (ref "R179")
      (value "0R1")
      (footprint "eagle-import:0603")
      (libsource (lib "eagle-import") (part "RESR0603"))
    )
    (comp (ref "R180")
      (value "0R1")
      (footprint "eagle-import:0603")
      (libsource (lib "eagle-import") (part "RESR0603"))
    )
    (comp (ref "R181")
      (value "4k7")
      (footprint "eagle-import:0603")
      (libsource (lib "eagle-import") (part "RESR0603"))
    )
    (comp (ref "R182")
      (value "4k7")
      (footprint "eagle-import:0603")
      (libsource (lib "eagle-import") (part "RESR0603"))
    )
    (comp (ref "R183")
      (value "0R1")
      (footprint "eagle-import:0603")
      (libsource (lib "eagle-import") (part "RESR0603"))
    )
    (comp (ref "R184")
      (value "0R1")
      (footprint "eagle-import:0603")
      (libsource (lib "eagle-import") (part "RESR0603"))
    )
    (comp (ref "R185")
      (value "0R1")
      (footprint "eagle-import:0603")
      (libsource (lib "eagle-import") (part "RESR0603"))
    )
    (comp (ref "R186")
      (value "0R1")
      (footprint "eagle-import:0603")
      (libsource (lib "eagle-import") (part "RESR0603"))
    )
    (comp (ref "R187")
      (value "100k")
      (footprint "eagle-import:0603")
      (libsource (lib "eagle-import") (part "RESR0603"))
    )
    (comp (ref "R188")
      (value "100k")
      (footprint "eagle-import:0603")
      (libsource (lib "eagle-import") (part "RESR0603"))
    )
    (comp (ref "R189")
      (value "4k7")
      (footprint "eagle-import:0603")
      (libsource (lib "eagle-import") (part "RESR0603"))
    )
    (comp (ref "R190")
      (value "4k7")
      (footprint "eagle-import:0603")
      (libsource (lib "eagle-import") (part "RESR0603"))
    )
    (comp (ref "R191")
      (value "4k7")
      (footprint "eagle-import:0603")
      (libsource (lib "eagle-import") (part "RESR0603"))
    )
    (comp (ref "R192")
      (value "0R1")
      (footprint "eagle-import:0603")
      (libsource (lib "eagle-import") (part "RESR0603"))
    )
    (comp (ref "R193")
      (value "0R1")
      (footprint "eagle-import:0603")
      (libsource (lib "eagle-import") (part "RESR0603"))
    )
    (comp (ref "R194")
      (value "4k7")
      (footprint "eagle-import:0603")
      (libsource (lib "eagle-import") (part "RESR0603"))
    )
    (comp (ref "R195")
      (value "910R")
      (footprint "eagle-import:0603")
      (libsource (lib "eagle-import") (part "RESR0603"))
    )
    (comp (ref "R196")
      (value "4k7")
      (footprint "eagle-import:0603")
      (libsource (lib "eagle-import") (part "RESR0603"))
    )
    (comp (ref "R197")
      (value "5k1")
      (footprint "eagle-import:0603")
      (libsource (lib "eagle-import") (part "RESR0603"))
    )
    (comp (ref "R198")
      (value "68k")
      (footprint "eagle-import:0603")
      (libsource (lib "eagle-import") (part "RESR0603"))
    )
    (comp (ref "R199")
      (value "15k")
      (footprint "eagle-import:0603")
      (libsource (lib "eagle-import") (part "RESR0603"))
    )
    (comp (ref "R200")
      (value "4k7")
      (footprint "eagle-import:0603")
      (libsource (lib "eagle-import") (part "RESR0603"))
    )
    (comp (ref "C205")
      (value "10uF")
      (footprint "eagle-import:0603")
      (libsource (lib "eagle-import") (part "CAPC0603"))
    )
    (comp (ref "C206")
      (value "100nF")
      (footprint "eagle-import:0402")
      (libsource (lib "eagle-import") (part "CAPC0402"))
    )
    (comp (ref "C207")
      (value "100nF")
      (footprint "eagle-import:0402")
      (libsource (lib "eagle-import") (part "CAPC0402"))
    )
    (comp (ref "C208")
      (value "100nF")
      (footprint "eagle-import:0402")
      (libsource (lib "eagle-import") (part "CAPC0402"))
    )
    (comp (ref "C209")
      (value "100nF")
      (footprint "eagle-import:0402")
      (libsource (lib "eagle-import") (part "CAPC0402"))
    )
    (comp (ref "C210")
      (value "100nF")
      (footprint "eagle-import:0402")
      (libsource (lib "eagle-import") (part "CAPC0402"))
    )
    (comp (ref "C211")
      (value "100nF")
      (footprint "eagle-import:0603")
      (fields (field (name "VOLTAGE") "50V"))
      (libsource (lib "eagle-import") (part "CAPC0603"))
    )
    (comp (ref "C212")
      (value "12pF")
      (footprint "eagle-import:0603")
      (libsource (lib "eagle-import") (part "CAPC0603"))
    )
    (comp (ref "C213")
      (value "6/30")
      (footprint "eagle-import:CTRIMTZBX4")
      (libsource (lib "eagle-import") (part "C-TRIMMTZBX4"))
    )
    (comp (ref "C214")
      (value "12pF")
      (footprint "eagle-import:0603")
      (libsource (lib "eagle-import") (part "CAPC0603"))
    )
    (comp (ref "C215")
      (value "220pF")
      (footprint "eagle-import:0603")
      (libsource (lib "eagle-import") (part "CAPC0603"))
    )
    (comp (ref "C216")
      (value "6/30")
      (footprint "eagle-import:CTRIMTZBX4")
      (libsource (lib "eagle-import") (part "C-TRIMMTZBX4"))
    )
    (comp (ref "C217")
      (value "12pF")
      (footprint "eagle-import:0603")
      (libsource (lib "eagle-import") (part "CAPC0603"))
    )
    (comp (ref "C218")
      (value "100nF")
      (footprint "eagle-import:0402")
      (libsource (lib "eagle-import") (part "CAPC0402"))
    )
    (comp (ref "C219")
      (value "100nF")
      (footprint "eagle-import:0402")
      (libsource (lib "eagle-import") (part "CAPC0402"))
    )
    (comp (ref "C220")
      (value "100nF")
      (footprint "eagle-import:0402")
      (libsource (lib "eagle-import") (part "CAPC0402"))
    )
    (comp (ref "C221")
      (value "100nF")
      (footprint "eagle-import:0402")
      (libsource (lib "eagle-import") (part "CAPC0402"))
    )
    (comp (ref "C222")
      (value "12pF")
      (footprint "eagle-import:0603")
      (libsource (lib "eagle-import") (part "CAPC0603"))
    )
    (comp (ref "C223")
      (value "12pF")
      (footprint "eagle-import:0603")
      (libsource (lib "eagle-import") (part "CAPC0603"))
    )
    (comp (ref "C224")
      (value "100uF")
      (footprint "eagle-import:1206")
      (libsource (lib "eagle-import") (part "CAPC1206"))
    )
    (comp (ref "C225")
      (value "100nF")
      (footprint "eagle-import:0402")
      (libsource (lib "eagle-import") (part "CAPC0402"))
    )
    (comp (ref "C226")
      (value "100nF")
      (footprint "eagle-import:0402")
      (libsource (lib "eagle-import") (part "CAPC0402"))
    )
    (comp (ref "C227")
      (value "100nF")
      (footprint "eagle-import:0402")
      (libsource (lib "eagle-import") (part "CAPC0402"))
    )
    (comp (ref "C228")
      (value "1pF")
      (footprint "eagle-import:0603")
      (libsource (lib "eagle-import") (part "CAPC0603"))
    )
    (comp (ref "C229")
      (value "1pF")
      (footprint "eagle-import:0603")
      (libsource (lib "eagle-import") (part "CAPC0603"))
    )
    (comp (ref "IC33")
      (value "ADA4853-3RU")
      (footprint "eagle-import:SO14")
      (libsource (lib "eagle-import") (part "ADA4853-3RU"))
    )
    (comp (ref "IC34")
      (value "4052D")
      (footprint "eagle-import:SO16")
      (libsource (lib "eagle-import") (part "4052D"))
    )
    (comp (ref "IC35")
      (value "4052D")
      (footprint "eagle-import:SO16")
      (libsource (lib "eagle-import") (part "4052D"))
    )
    (comp (ref "IC36")
      (value "OPA2354")
      (footprint "eagle-import:MSOP08")
      (libsource (lib "eagle-import") (part "AD8682RM"))
    )
    (comp (ref "IC37")
      (value "74HC595D")
      (footprint "eagle-import:SO16")
      (libsource (lib "eagle-import") (part "74595DHC"))
    )
    (comp (ref "K1")
      (value "G6K-2F-Y")
      (footprint "eagle-import:G6K-2F-Y")
      (fields (field (name "MF") "OMRON COMPONENTS USA") (field (name "MPN") "G6K-2F-Y DC3"))
      (libsource (lib "eagle-import") (part "G6K-2F-Y"))
    )
    (comp (ref "K2")
      (value "G6K-2F-Y")
      (footprint "eagle-import:G6K-2F-Y")
      (fields (field (name "MF") "OMRON COMPONENTS USA") (field (name "MPN") "G6K-2F-Y DC3"))
      (libsource (lib "eagle-import") (part "G6K-2F-Y"))
    )
    (comp (ref "L12")
      (value "1uH")
      (footprint "eagle-import:L3216C")
      (libsource (lib "eagle-import") (part "L-EUL3216C"))
    )
    (comp (ref "R208")
      (value "200R")
      (footprint "eagle-import:0603")
      (libsource (lib "eagle-import") (part "RESR0603"))
    )
    (comp (ref "R209")
      (value "30R")
      (footprint "eagle-import:0603")
      (libsource (lib "eagle-import") (part "RESR0603"))
    )
    (comp (ref "R210")
      (value "20R")
      (footprint "eagle-import:0603")
      (libsource (lib "eagle-import") (part "RESR0603"))
    )
    (comp (ref "R211")
      (value "22R")
      (footprint "eagle-import:0603")
      (libsource (lib "eagle-import") (part "RESR0603"))
    )
    (comp (ref "R212")
      (value "300R")
      (footprint "eagle-import:0603")
      (libsource (lib "eagle-import") (part "RESR0603"))
    )
    (comp (ref "R213")
      (value "100R")
      (footprint "eagle-import:0603")
      (libsource (lib "eagle-import") (part "RESR0603"))
    )
    (comp (ref "R214")
      (value "22R")
      (footprint "eagle-import:0603")
      (libsource (lib "eagle-import") (part "RESR0603"))
    )
    (comp (ref "R215")
      (value "300R")
      (footprint "eagle-import:0603")
      (libsource (lib "eagle-import") (part "RESR0603"))
    )
    (comp (ref "R216")
      (value "300R")
      (footprint "eagle-import:0603")
      (libsource (lib "eagle-import") (part "RESR0603"))
    )
    (comp (ref "R217")
      (value "22R")
      (footprint "eagle-import:0603")
      (libsource (lib "eagle-import") (part "RESR0603"))
    )
    (comp (ref "R218")
      (value "10k")
      (footprint "eagle-import:0603")
      (libsource (lib "eagle-import") (part "RESR0603"))
    )
    (comp (ref "R219")
      (value "10k")
      (footprint "eagle-import:0603")
      (libsource (lib "eagle-import") (part "RESR0603"))
    )
    (comp (ref "R220")
      (value "10k")
      (footprint "eagle-import:0603")
      (libsource (lib "eagle-import") (part "RESR0603"))
    )
    (comp (ref "R221")
      (value "30k")
      (footprint "eagle-import:0603")
      (libsource (lib "eagle-import") (part "RESR0603"))
    )
    (comp (ref "R222")
      (value "30k")
      (footprint "eagle-import:0603")
      (libsource (lib "eagle-import") (part "RESR0603"))
    )
    (comp (ref "R223")
      (value "470k")
      (footprint "eagle-import:0603")
      (libsource (lib "eagle-import") (part "RESR0603"))
    )
    (comp (ref "R224")
      (value "470k")
      (footprint "eagle-import:0603")
      (libsource (lib "eagle-import") (part "RESR0603"))
    )
    (comp (ref "R225")
      (value "51k")
      (footprint "eagle-import:0603")
      (libsource (lib "eagle-import") (part "RESR0603"))
    )
    (comp (ref "R226")
      (value "39k")
      (footprint "eagle-import:0603")
      (libsource (lib "eagle-import") (part "RESR0603"))
    )
    (comp (ref "R227")
      (value "910k")
      (footprint "eagle-import:0603")
      (libsource (lib "eagle-import") (part "RESR0603"))
    )
    (comp (ref "R228")
      (value "1k")
      (footprint "eagle-import:0603")
      (libsource (lib "eagle-import") (part "RESR0603"))
    )
    (comp (ref "R229")
      (value "300R")
      (footprint "eagle-import:0603")
      (libsource (lib "eagle-import") (part "RESR0603"))
    )
    (comp (ref "R230")
      (value "300R")
      (footprint "eagle-import:0603")
      (libsource (lib "eagle-import") (part "RESR0603"))
    )
    (comp (ref "R231")
      (value "7R5")
      (footprint "eagle-import:0603")
      (libsource (lib "eagle-import") (part "RESR0603"))
    )
    (comp (ref "R232")
      (value "10R")
      (footprint "eagle-import:0603")
      (libsource (lib "eagle-import") (part "RESR0603"))
    )
    (comp (ref "R233")
      (value "10R")
      (footprint "eagle-import:0603")
      (libsource (lib "eagle-import") (part "RESR0603"))
    )
    (comp (ref "R234")
      (value "10R")
      (footprint "eagle-import:0603")
      (libsource (lib "eagle-import") (part "RESR0603"))
    )
    (comp (ref "R235")
      (value "10R")
      (footprint "eagle-import:0603")
      (libsource (lib "eagle-import") (part "RESR0603"))
    )
    (comp (ref "R236")
      (value "10R")
      (footprint "eagle-import:0603")
      (libsource (lib "eagle-import") (part "RESR0603"))
    )
    (comp (ref "R237")
      (value "22R")
      (footprint "eagle-import:0603")
      (libsource (lib "eagle-import") (part "RESR0603"))
    )
    (comp (ref "R238")
      (value "300R")
      (footprint "eagle-import:0603")
      (libsource (lib "eagle-import") (part "RESR0603"))
    )
    (comp (ref "R239")
      (value "22R")
      (footprint "eagle-import:0603")
      (libsource (lib "eagle-import") (part "RESR0603"))
    )
    (comp (ref "R240")
      (value "1R")
      (footprint "eagle-import:0603")
      (libsource (lib "eagle-import") (part "RESR0603"))
    )
    (comp (ref "R241")
      (value "100R")
      (footprint "eagle-import:0402")
      (libsource (lib "eagle-import") (part "RESR0402"))
    )
    (comp (ref "R242")
      (value "47R")
      (footprint "eagle-import:0603")
      (libsource (lib "eagle-import") (part "RESR0603"))
    )
    (comp (ref "R243")
      (value "47R")
      (footprint "eagle-import:0603")
      (libsource (lib "eagle-import") (part "RESR0603"))
    )
    (comp (ref "T2")
      (value "BC850")
      (footprint "eagle-import:SOT23")
      (libsource (lib "eagle-import") (part "BC850"))
    )
    (comp (ref "T3")
      (value "BC850")
      (footprint "eagle-import:SOT23")
      (libsource (lib "eagle-import") (part "BC850"))
    )
    (comp (ref "T4")
      (value "BC850")
      (footprint "eagle-import:SOT23")
      (libsource (lib "eagle-import") (part "BC850"))
    )
    (comp (ref "T5")
      (value "BC856ASMD")
      (footprint "eagle-import:SOT23-BEC")
      (libsource (lib "eagle-import") (part "BC856SMDA"))
    )
    (comp (ref "T6")
      (value "BC856ASMD")
      (footprint "eagle-import:SOT23-BEC")
      (libsource (lib "eagle-import") (part "BC856SMDA"))
    )
    (comp (ref "T7")
      (value "BC856ASMD")
      (footprint "eagle-import:SOT23-BEC")
      (libsource (lib "eagle-import") (part "BC856SMDA"))
    )
    (comp (ref "T8")
      (value "BC850")
      (footprint "eagle-import:SOT23")
      (libsource (lib "eagle-import") (part "BC850"))
    )
    (comp (ref "T9")
      (value "BC856ASMD")
      (footprint "eagle-import:SOT23-BEC")
      (libsource (lib "eagle-import") (part "BC856SMDA"))
    )
    (comp (ref "X2")
      (value "31-5431-10RFX")
      (footprint "eagle-import:AMP_227161")
      (libsource (lib "eagle-import") (part "?227161-8"))
    )
    (comp (ref "C255")
      (value "100nF")
      (footprint "eagle-import:0402")
      (libsource (lib "eagle-import") (part "CAPC0402"))
    )
    (comp (ref "C256")
      (value "100nF")
      (footprint "eagle-import:0402")
      (libsource (lib "eagle-import") (part "CAPC0402"))
    )
    (comp (ref "IC43")
      (value "LM321MF")
      (footprint "eagle-import:SOT23-5")
      (libsource (lib "eagle-import") (part "LM321?MF"))
    )
    (comp (ref "IC44")
      (value "74HC595D")
      (footprint "eagle-import:SO16")
      (libsource (lib "eagle-import") (part "74595DHC"))
    )
    (comp (ref "R282")
      (value "50R")
      (footprint "eagle-import:0603")
      (libsource (lib "eagle-import") (part "RESR0603"))
    )
    (comp (ref "R283")
      (value "1k6")
      (footprint "eagle-import:0603")
      (libsource (lib "eagle-import") (part "RESR0603"))
    )
    (comp (ref "R284")
      (value "820R")
      (footprint "eagle-import:0603")
      (libsource (lib "eagle-import") (part "RESR0603"))
    )
    (comp (ref "R285")
      (value "1k6")
      (footprint "eagle-import:0603")
      (libsource (lib "eagle-import") (part "RESR0603"))
    )
    (comp (ref "R286")
      (value "820R")
      (footprint "eagle-import:0603")
      (libsource (lib "eagle-import") (part "RESR0603"))
    )
    (comp (ref "R287")
      (value "820R")
      (footprint "eagle-import:0603")
      (libsource (lib "eagle-import") (part "RESR0603"))
    )
    (comp (ref "R288")
      (value "820R")
      (footprint "eagle-import:0603")
      (libsource (lib "eagle-import") (part "RESR0603"))
    )
    (comp (ref "R289")
      (value "820R")
      (footprint "eagle-import:0603")
      (libsource (lib "eagle-import") (part "RESR0603"))
    )
    (comp (ref "R290")
      (value "820R")
      (footprint "eagle-import:0603")
      (libsource (lib "eagle-import") (part "RESR0603"))
    )
    (comp (ref "R291")
      (value "820R")
      (footprint "eagle-import:0603")
      (libsource (lib "eagle-import") (part "RESR0603"))
    )
    (comp (ref "R292")
      (value "1k6")
      (footprint "eagle-import:0603")
      (libsource (lib "eagle-import") (part "RESR0603"))
    )
    (comp (ref "R293")
      (value "1k6")
      (footprint "eagle-import:0603")
      (libsource (lib "eagle-import") (part "RESR0603"))
    )
    (comp (ref "R294")
      (value "1k6")
      (footprint "eagle-import:0603")
      (libsource (lib "eagle-import") (part "RESR0603"))
    )
    (comp (ref "R295")
      (value "1k6")
      (footprint "eagle-import:0603")
      (libsource (lib "eagle-import") (part "RESR0603"))
    )
    (comp (ref "R296")
      (value "1k6")
      (footprint "eagle-import:0603")
      (libsource (lib "eagle-import") (part "RESR0603"))
    )
    (comp (ref "R297")
      (value "1k6")
      (footprint "eagle-import:0603")
      (libsource (lib "eagle-import") (part "RESR0603"))
    )
    (comp (ref "R298")
      (value "1k6")
      (footprint "eagle-import:0603")
      (libsource (lib "eagle-import") (part "RESR0603"))
    )
    (comp (ref "R299")
      (value "39R")
      (footprint "eagle-import:0603")
      (libsource (lib "eagle-import") (part "RESR0603"))
    )
    (comp (ref "R300")
      (value "300R")
      (footprint "eagle-import:0603")
      (libsource (lib "eagle-import") (part "RESR0603"))
    )
    (comp (ref "C4")
      (value "4.7pF")
      (footprint "eagle-import:0402")
      (libsource (lib "eagle-import") (part "CAPC0402"))
    )
    (comp (ref "C5")
      (value "4.7pF")
      (footprint "eagle-import:0402")
      (libsource (lib "eagle-import") (part "CAPC0402"))
    )
    (comp (ref "C6")
      (value "4.7pF")
      (footprint "eagle-import:0402")
      (libsource (lib "eagle-import") (part "CAPC0402"))
    )
    (comp (ref "C7")
      (value "4.7pF")
      (footprint "eagle-import:0402")
      (libsource (lib "eagle-import") (part "CAPC0402"))
    )
    (comp (ref "C19")
      (value "4.7pF")
      (footprint "eagle-import:0402")
      (libsource (lib "eagle-import") (part "CAPC0402"))
    )
    (comp (ref "C75")
      (value "4.7pF")
      (footprint "eagle-import:0402")
      (libsource (lib "eagle-import") (part "CAPC0402"))
    )
    (comp (ref "C76")
      (value "100nF")
      (footprint "eagle-import:0402")
      (libsource (lib "eagle-import") (part "CAPC0402"))
    )
    (comp (ref "C77")
      (value "100nF")
      (footprint "eagle-import:0402")
      (libsource (lib "eagle-import") (part "CAPC0402"))
    )
    (comp (ref "C89")
      (value "4.7pF")
      (footprint "eagle-import:0402")
      (libsource (lib "eagle-import") (part "CAPC0402"))
    )
    (comp (ref "C90")
      (value "4.7pF")
      (footprint "eagle-import:0402")
      (libsource (lib "eagle-import") (part "CAPC0402"))
    )
    (comp (ref "IC9")
      (value "74LVC8T245")
      (footprint "eagle-import:R-PDSO-G24")
      (libsource (lib "eagle-import") (part "74LVC8T245"))
    )
    (comp (ref "R13")
      (value "270")
      (footprint "eagle-import:0402")
      (libsource (lib "eagle-import") (part "RESR0402"))
    )
    (comp (ref "R67")
      (value "270")
      (footprint "eagle-import:0402")
      (libsource (lib "eagle-import") (part "RESR0402"))
    )
    (comp (ref "R68")
      (value "270")
      (footprint "eagle-import:0402")
      (libsource (lib "eagle-import") (part "RESR0402"))
    )
    (comp (ref "R69")
      (value "270")
      (footprint "eagle-import:0402")
      (libsource (lib "eagle-import") (part "RESR0402"))
    )
    (comp (ref "R70")
      (value "270")
      (footprint "eagle-import:0402")
      (libsource (lib "eagle-import") (part "RESR0402"))
    )
    (comp (ref "R71")
      (value "270")
      (footprint "eagle-import:0402")
      (libsource (lib "eagle-import") (part "RESR0402"))
    )
    (comp (ref "R72")
      (value "270")
      (footprint "eagle-import:0402")
      (libsource (lib "eagle-import") (part "RESR0402"))
    )
    (comp (ref "R73")
      (value "270")
      (footprint "eagle-import:0402")
      (libsource (lib "eagle-import") (part "RESR0402"))
    )
    (comp (ref "R79")
      (value "47R")
      (footprint "eagle-import:0402")
      (libsource (lib "eagle-import") (part "RESR0402"))
    )
    (comp (ref "R80")
      (value "150k")
      (footprint "eagle-import:0402")
      (libsource (lib "eagle-import") (part "RESR0402"))
    )
    (comp (ref "R81")
      (value "150k")
      (footprint "eagle-import:0402")
      (libsource (lib "eagle-import") (part "RESR0402"))
    )
    (comp (ref "R82")
      (value "150k")
      (footprint "eagle-import:0402")
      (libsource (lib "eagle-import") (part "RESR0402"))
    )
    (comp (ref "R95")
      (value "150k")
      (footprint "eagle-import:0402")
      (libsource (lib "eagle-import") (part "RESR0402"))
    )
    (comp (ref "R96")
      (value "150k")
      (footprint "eagle-import:0402")
      (libsource (lib "eagle-import") (part "RESR0402"))
    )
    (comp (ref "R97")
      (value "47R")
      (footprint "eagle-import:0402")
      (libsource (lib "eagle-import") (part "RESR0402"))
    )
    (comp (ref "R98")
      (value "47R")
      (footprint "eagle-import:0402")
      (libsource (lib "eagle-import") (part "RESR0402"))
    )
    (comp (ref "R99")
      (value "47R")
      (footprint "eagle-import:0402")
      (libsource (lib "eagle-import") (part "RESR0402"))
    )
    (comp (ref "R100")
      (value "47R")
      (footprint "eagle-import:0402")
      (libsource (lib "eagle-import") (part "RESR0402"))
    )
    (comp (ref "R101")
      (value "47R")
      (footprint "eagle-import:0402")
      (libsource (lib "eagle-import") (part "RESR0402"))
    )
    (comp (ref "R102")
      (value "47R")
      (footprint "eagle-import:0402")
      (libsource (lib "eagle-import") (part "RESR0402"))
    )
    (comp (ref "R103")
      (value "47R")
      (footprint "eagle-import:0402")
      (libsource (lib "eagle-import") (part "RESR0402"))
    )
    (comp (ref "R113")
      (value "150k")
      (footprint "eagle-import:0402")
      (libsource (lib "eagle-import") (part "RESR0402"))
    )
    (comp (ref "R114")
      (value "150k")
      (footprint "eagle-import:0402")
      (libsource (lib "eagle-import") (part "RESR0402"))
    )
    (comp (ref "R115")
      (value "150k")
      (footprint "eagle-import:0402")
      (libsource (lib "eagle-import") (part "RESR0402"))
    )
    (comp (ref "R116")
      (value "100R")
      (footprint "eagle-import:0402")
      (libsource (lib "eagle-import") (part "RESR0402"))
    )
    (comp (ref "R117")
      (value "100R")
      (footprint "eagle-import:0402")
      (libsource (lib "eagle-import") (part "RESR0402"))
    )
    (comp (ref "R118")
      (value "100R")
      (footprint "eagle-import:0402")
      (libsource (lib "eagle-import") (part "RESR0402"))
    )
    (comp (ref "R119")
      (value "100R")
      (footprint "eagle-import:0402")
      (libsource (lib "eagle-import") (part "RESR0402"))
    )
    (comp (ref "R120")
      (value "100R")
      (footprint "eagle-import:0402")
      (libsource (lib "eagle-import") (part "RESR0402"))
    )
    (comp (ref "R121")
      (value "100R")
      (footprint "eagle-import:0402")
      (libsource (lib "eagle-import") (part "RESR0402"))
    )
    (comp (ref "R122")
      (value "100R")
      (footprint "eagle-import:0402")
      (libsource (lib "eagle-import") (part "RESR0402"))
    )
    (comp (ref "R123")
      (value "100R")
      (footprint "eagle-import:0402")
      (libsource (lib "eagle-import") (part "RESR0402"))
    )
    (comp (ref "R124")
      (value "51k")
      (footprint "eagle-import:0402")
      (libsource (lib "eagle-import") (part "RESR0402"))
    )
    (comp (ref "R125")
      (value "51k")
      (footprint "eagle-import:0402")
      (libsource (lib "eagle-import") (part "RESR0402"))
    )
    (comp (ref "R126")
      (value "51k")
      (footprint "eagle-import:0402")
      (libsource (lib "eagle-import") (part "RESR0402"))
    )
    (comp (ref "R127")
      (value "51k")
      (footprint "eagle-import:0402")
      (libsource (lib "eagle-import") (part "RESR0402"))
    )
    (comp (ref "R128")
      (value "51k")
      (footprint "eagle-import:0402")
      (libsource (lib "eagle-import") (part "RESR0402"))
    )
    (comp (ref "R129")
      (value "51k")
      (footprint "eagle-import:0402")
      (libsource (lib "eagle-import") (part "RESR0402"))
    )
    (comp (ref "R130")
      (value "51k")
      (footprint "eagle-import:0402")
      (libsource (lib "eagle-import") (part "RESR0402"))
    )
    (comp (ref "R131")
      (value "51k")
      (footprint "eagle-import:0402")
      (libsource (lib "eagle-import") (part "RESR0402"))
    )
    (comp (ref "SV2")
      (value "2x8 Pinheader")
      (footprint "eagle-import:MA08-2W")
      (libsource (lib "eagle-import") (part "MA08-2W"))
    )
    (comp (ref "SV3")
      (value "2x8 Pinheader")
      (footprint "eagle-import:MA08-2W")
      (libsource (lib "eagle-import") (part "MA08-2W"))
    )
    (comp (ref "C22")
      (value "470nF")
      (footprint "eagle-import:0402")
      (libsource (lib "eagle-import") (part "CAPC0402"))
    )
    (comp (ref "C57")
      (value "10uF")
      (footprint "eagle-import:0603")
      (libsource (lib "eagle-import") (part "CAPC0603"))
    )
    (comp (ref "C58")
      (value "100nF")
      (footprint "eagle-import:0402")
      (libsource (lib "eagle-import") (part "CAPC0402"))
    )
    (comp (ref "C59")
      (value "10uF")
      (footprint "eagle-import:0603")
      (libsource (lib "eagle-import") (part "CAPC0603"))
    )
    (comp (ref "C60")
      (value "100nF")
      (footprint "eagle-import:0402")
      (libsource (lib "eagle-import") (part "CAPC0402"))
    )
    (comp (ref "C61")
      (value "10pF")
      (footprint "eagle-import:0402")
      (libsource (lib "eagle-import") (part "CAPC0402"))
    )
    (comp (ref "C62")
      (value "10pF")
      (footprint "eagle-import:0402")
      (libsource (lib "eagle-import") (part "CAPC0402"))
    )
    (comp (ref "C63")
      (value "100nF")
      (footprint "eagle-import:0402")
      (libsource (lib "eagle-import") (part "CAPC0402"))
    )
    (comp (ref "C64")
      (value "100nF")
      (footprint "eagle-import:0402")
      (libsource (lib "eagle-import") (part "CAPC0402"))
    )
    (comp (ref "C65")
      (value "100nF")
      (footprint "eagle-import:0402")
      (libsource (lib "eagle-import") (part "CAPC0402"))
    )
    (comp (ref "C66")
      (value "10uF")
      (footprint "eagle-import:0603")
      (libsource (lib "eagle-import") (part "CAPC0603"))
    )
    (comp (ref "C67")
      (value "100nF")
      (footprint "eagle-import:0402")
      (libsource (lib "eagle-import") (part "CAPC0402"))
    )
    (comp (ref "C68")
      (value "100nF")
      (footprint "eagle-import:0402")
      (libsource (lib "eagle-import") (part "CAPC0402"))
    )
    (comp (ref "C69")
      (value "100nF")
      (footprint "eagle-import:0402")
      (libsource (lib "eagle-import") (part "CAPC0402"))
    )
    (comp (ref "C70")
      (value "10uF")
      (footprint "eagle-import:0603")
      (libsource (lib "eagle-import") (part "CAPC0603"))
    )
    (comp (ref "C71")
      (value "100uF")
      (footprint "eagle-import:1206")
      (libsource (lib "eagle-import") (part "CAPC1206"))
    )
    (comp (ref "C72")
      (value "470nF")
      (footprint "eagle-import:0402")
      (libsource (lib "eagle-import") (part "CAPC0402"))
    )
    (comp (ref "C73")
      (value "10uF")
      (footprint "eagle-import:0603")
      (libsource (lib "eagle-import") (part "CAPC0603"))
    )
    (comp (ref "C106")
      (value "100nF")
      (footprint "eagle-import:0402")
      (libsource (lib "eagle-import") (part "CAPC0402"))
    )
    (comp (ref "C107")
      (value "100nF")
      (footprint "eagle-import:0402")
      (libsource (lib "eagle-import") (part "CAPC0402"))
    )
    (comp (ref "C108")
      (value "100nF")
      (footprint "eagle-import:0402")
      (libsource (lib "eagle-import") (part "CAPC0402"))
    )
    (comp (ref "C109")
      (value "100nF")
      (footprint "eagle-import:0402")
      (libsource (lib "eagle-import") (part "CAPC0402"))
    )
    (comp (ref "C110")
      (value "100nF")
      (footprint "eagle-import:0402")
      (libsource (lib "eagle-import") (part "CAPC0402"))
    )
    (comp (ref "C111")
      (value "100nF")
      (footprint "eagle-import:0402")
      (libsource (lib "eagle-import") (part "CAPC0402"))
    )
    (comp (ref "IC5")
      (value "ADC08200")
      (footprint "eagle-import:TSSOP24")
      (libsource (lib "eagle-import") (part "ADC08200"))
    )
    (comp (ref "IC6")
      (value "ADC08200")
      (footprint "eagle-import:TSSOP24")
      (libsource (lib "eagle-import") (part "ADC08200"))
    )
    (comp (ref "L4")
      (value "220nH")
      (footprint "eagle-import:0603")
      (libsource (lib "eagle-import") (part "INUDCTOR0603"))
    )
    (comp (ref "L5")
      (value "220nH")
      (footprint "eagle-import:0603")
      (libsource (lib "eagle-import") (part "INUDCTOR0603"))
    )
    (comp (ref "L8")
      (value "220nH")
      (footprint "eagle-import:0603")
      (libsource (lib "eagle-import") (part "INUDCTOR0603"))
    )
    (comp (ref "L9")
      (value "220nH")
      (footprint "eagle-import:0603")
      (libsource (lib "eagle-import") (part "INUDCTOR0603"))
    )
    (comp (ref "L10")
      (value "220nH")
      (footprint "eagle-import:0603")
      (libsource (lib "eagle-import") (part "INUDCTOR0603"))
    )
    (comp (ref "L11")
      (value "220nH")
      (footprint "eagle-import:0603")
      (libsource (lib "eagle-import") (part "INUDCTOR0603"))
    )
    (comp (ref "R22")
      (value "47R")
      (footprint "eagle-import:0402")
      (libsource (lib "eagle-import") (part "RESR0402"))
    )
    (comp (ref "R23")
      (value "47R")
      (footprint "eagle-import:0402")
      (libsource (lib "eagle-import") (part "RESR0402"))
    )
    (comp (ref "R24")
      (value "47R")
      (footprint "eagle-import:0402")
      (libsource (lib "eagle-import") (part "RESR0402"))
    )
    (comp (ref "R25")
      (value "47R")
      (footprint "eagle-import:0402")
      (libsource (lib "eagle-import") (part "RESR0402"))
    )
    (comp (ref "R26")
      (value "47R")
      (footprint "eagle-import:0402")
      (libsource (lib "eagle-import") (part "RESR0402"))
    )
    (comp (ref "R27")
      (value "47R")
      (footprint "eagle-import:0402")
      (libsource (lib "eagle-import") (part "RESR0402"))
    )
    (comp (ref "R28")
      (value "47R")
      (footprint "eagle-import:0402")
      (libsource (lib "eagle-import") (part "RESR0402"))
    )
    (comp (ref "R29")
      (value "47R")
      (footprint "eagle-import:0402")
      (libsource (lib "eagle-import") (part "RESR0402"))
    )
    (comp (ref "R30")
      (value "47R")
      (footprint "eagle-import:0402")
      (libsource (lib "eagle-import") (part "RESR0402"))
    )
    (comp (ref "R31")
      (value "47R")
      (footprint "eagle-import:0402")
      (libsource (lib "eagle-import") (part "RESR0402"))
    )
    (comp (ref "R32")
      (value "47R")
      (footprint "eagle-import:0402")
      (libsource (lib "eagle-import") (part "RESR0402"))
    )
    (comp (ref "R33")
      (value "47R")
      (footprint "eagle-import:0402")
      (libsource (lib "eagle-import") (part "RESR0402"))
    )
    (comp (ref "R34")
      (value "47R")
      (footprint "eagle-import:0402")
      (libsource (lib "eagle-import") (part "RESR0402"))
    )
    (comp (ref "R35")
      (value "47R")
      (footprint "eagle-import:0402")
      (libsource (lib "eagle-import") (part "RESR0402"))
    )
    (comp (ref "R36")
      (value "47R")
      (footprint "eagle-import:0402")
      (libsource (lib "eagle-import") (part "RESR0402"))
    )
    (comp (ref "R37")
      (value "47R")
      (footprint "eagle-import:0402")
      (libsource (lib "eagle-import") (part "RESR0402"))
    )
    (comp (ref "U2")
      (value "6SLX9FTG256")
      (footprint "eagle-import:FT256")
      (libsource (lib "eagle-import") (part "6SLX9FTG256"))
    )
    (comp (ref "C139")
      (value "100nF")
      (footprint "eagle-import:0402")
      (libsource (lib "eagle-import") (part "CAPC0402"))
    )
    (comp (ref "C148")
      (value "100nF")
      (footprint "eagle-import:0402")
      (libsource (lib "eagle-import") (part "CAPC0402"))
    )
    (comp (ref "C150")
      (value "100nF")
      (footprint "eagle-import:0402")
      (libsource (lib "eagle-import") (part "CAPC0402"))
    )
    (comp (ref "C201")
      (value "10nF")
      (footprint "eagle-import:0402")
      (libsource (lib "eagle-import") (part "CAPC0402"))
    )
    (comp (ref "C202")
      (value "10nF")
      (footprint "eagle-import:0402")
      (libsource (lib "eagle-import") (part "CAPC0402"))
    )
    (comp (ref "C203")
      (value "10nF")
      (footprint "eagle-import:0402")
      (libsource (lib "eagle-import") (part "CAPC0402"))
    )
    (comp (ref "C204")
      (value "100nF")
      (footprint "eagle-import:0402")
      (libsource (lib "eagle-import") (part "CAPC0402"))
    )
    (comp (ref "IC22")
      (value "74HC4052D")
      (footprint "eagle-import:SO16")
      (libsource (lib "eagle-import") (part "4052D"))
    )
    (comp (ref "IC25")
      (value "INA331IDGK")
      (footprint "eagle-import:MSOP08")
      (libsource (lib "eagle-import") (part "INA331IDGK"))
    )
    (comp (ref "IC32")
      (value "ADS1118IDGSR")
      (footprint "eagle-import:MSOP10")
      (libsource (lib "eagle-import") (part "ADS1118IDGSR"))
    )
    (comp (ref "R108")
      (value "4k7")
      (footprint "eagle-import:0402")
      (libsource (lib "eagle-import") (part "RESR0402"))
    )
    (comp (ref "R109")
      (value "4k7")
      (footprint "eagle-import:0402")
      (libsource (lib "eagle-import") (part "RESR0402"))
    )
    (comp (ref "R110")
      (value "4k7")
      (footprint "eagle-import:0402")
      (libsource (lib "eagle-import") (part "RESR0402"))
    )
    (comp (ref "R111")
      (value "4k7")
      (footprint "eagle-import:0402")
      (libsource (lib "eagle-import") (part "RESR0402"))
    )
    (comp (ref "R153")
      (value "1M")
      (footprint "eagle-import:0603")
      (libsource (lib "eagle-import") (part "RESR0603"))
    )
    (comp (ref "R154")
      (value "100k")
      (footprint "eagle-import:0603")
      (libsource (lib "eagle-import") (part "RESR0603"))
    )
    (comp (ref "R155")
      (value "1k")
      (footprint "eagle-import:0603")
      (libsource (lib "eagle-import") (part "RESR0603"))
    )
    (comp (ref "R156")
      (value "68R")
      (footprint "eagle-import:0603")
      (libsource (lib "eagle-import") (part "RESR0603"))
    )
    (comp (ref "R202")
      (value "91k")
      (footprint "eagle-import:0603")
      (libsource (lib "eagle-import") (part "RESR0603"))
    )
    (comp (ref "R203")
      (value "10k")
      (footprint "eagle-import:0603")
      (libsource (lib "eagle-import") (part "RESR0603"))
    )
    (comp (ref "R204")
      (value "27k")
      (footprint "eagle-import:0603")
      (libsource (lib "eagle-import") (part "RESR0603"))
    )
    (comp (ref "R205")
      (value "27k")
      (footprint "eagle-import:0603")
      (libsource (lib "eagle-import") (part "RESR0603"))
    )
    (comp (ref "R206")
      (value "22k")
      (footprint "eagle-import:0603")
      (libsource (lib "eagle-import") (part "RESR0603"))
    )
    (comp (ref "R207")
      (value "22k")
      (footprint "eagle-import:0603")
      (libsource (lib "eagle-import") (part "RESR0603"))
    )
    (comp (ref "R280")
      (value "1k")
      (footprint "eagle-import:0402")
      (libsource (lib "eagle-import") (part "RESR0402"))
    )
    (comp (ref "R281")
      (value "2k2")
      (footprint "eagle-import:0402")
      (libsource (lib "eagle-import") (part "RESR0402"))
    )
    (comp (ref "SV4")
      (value "2x8 Pinheader")
      (footprint "eagle-import:MA08-2W")
      (libsource (lib "eagle-import") (part "MA08-2W"))
    )
    (comp (ref "SV5")
      (value "3x1 Pinheader")
      (footprint "eagle-import:MA03-1")
      (libsource (lib "eagle-import") (part "MA03-1"))
    )
    (comp (ref "C39")
      (value "10nF")
      (footprint "eagle-import:0402")
      (libsource (lib "eagle-import") (part "CAPC0402"))
    )
    (comp (ref "C40")
      (value "100nF")
      (footprint "eagle-import:0402")
      (libsource (lib "eagle-import") (part "CAPC0402"))
    )
    (comp (ref "C41")
      (value "100nF")
      (footprint "eagle-import:0402")
      (libsource (lib "eagle-import") (part "CAPC0402"))
    )
    (comp (ref "C42")
      (value "100nF")
      (footprint "eagle-import:0402")
      (libsource (lib "eagle-import") (part "CAPC0402"))
    )
    (comp (ref "C43")
      (value "10uF")
      (footprint "eagle-import:0603")
      (libsource (lib "eagle-import") (part "CAPC0603"))
    )
    (comp (ref "C44")
      (value "10uF")
      (footprint "eagle-import:0603")
      (libsource (lib "eagle-import") (part "CAPC0603"))
    )
    (comp (ref "C45")
      (value "100nF")
      (footprint "eagle-import:0402")
      (libsource (lib "eagle-import") (part "CAPC0402"))
    )
    (comp (ref "C46")
      (value "10uF")
      (footprint "eagle-import:0603")
      (libsource (lib "eagle-import") (part "CAPC0603"))
    )
    (comp (ref "C47")
      (value "100nF")
      (footprint "eagle-import:0402")
      (libsource (lib "eagle-import") (part "CAPC0402"))
    )
    (comp (ref "C48")
      (value "10uF")
      (footprint "eagle-import:0603")
      (libsource (lib "eagle-import") (part "CAPC0603"))
    )
    (comp (ref "C49")
      (value "100nF")
      (footprint "eagle-import:0402")
      (libsource (lib "eagle-import") (part "CAPC0402"))
    )
    (comp (ref "C50")
      (value "100nF")
      (footprint "eagle-import:0402")
      (libsource (lib "eagle-import") (part "CAPC0402"))
    )
    (comp (ref "C51")
      (value "100nF")
      (footprint "eagle-import:0402")
      (libsource (lib "eagle-import") (part "CAPC0402"))
    )
    (comp (ref "C52")
      (value "100nF")
      (footprint "eagle-import:0402")
      (libsource (lib "eagle-import") (part "CAPC0402"))
    )
    (comp (ref "C53")
      (value "10nF")
      (footprint "eagle-import:0402")
      (libsource (lib "eagle-import") (part "CAPC0402"))
    )
    (comp (ref "C54")
      (value "100nF")
      (footprint "eagle-import:0402")
      (libsource (lib "eagle-import") (part "CAPC0402"))
    )
    (comp (ref "C55")
      (value "27pF")
      (footprint "eagle-import:0603")
      (libsource (lib "eagle-import") (part "CAPC0603"))
    )
    (comp (ref "C56")
      (value "27pF")
      (footprint "eagle-import:0603")
      (libsource (lib "eagle-import") (part "CAPC0603"))
    )
    (comp (ref "C74")
      (value "10uF")
      (footprint "eagle-import:0603")
      (libsource (lib "eagle-import") (part "CAPC0603"))
    )
    (comp (ref "IC4")
      (value "FT232H")
      (footprint "eagle-import:LQFP48")
      (libsource (lib "eagle-import") (part "FT232H"))
    )
    (comp (ref "IC8")
      (value "93LC56SM")
      (footprint "eagle-import:SO-08M")
      (fields (field (name "MF") "MICROCHIP") (field (name "MPN") "93LC56T/SN"))
      (libsource (lib "eagle-import") (part "93SMLC56"))
    )
    (comp (ref "L1")
      (value "1µH")
      (footprint "eagle-import:L3216C")
      (libsource (lib "eagle-import") (part "L-EUL3216C"))
    )
    (comp (ref "L2")
      (value "1µH")
      (footprint "eagle-import:L3216C")
      (libsource (lib "eagle-import") (part "L-EUL3216C"))
    )
    (comp (ref "L3")
      (value "1µH")
      (footprint "eagle-import:L3216C")
      (libsource (lib "eagle-import") (part "L-EUL3216C"))
    )
    (comp (ref "L6")
      (value "470nH")
      (footprint "eagle-import:L3216C")
      (libsource (lib "eagle-import") (part "L-EUL3216C"))
    )
    (comp (ref "Q1")
      (value "12MHz")
      (footprint "eagle-import:HC49UP")
      (libsource (lib "eagle-import") (part "CRYSTALHC49UP"))
    )
    (comp (ref "R14")
      (value "0R")
      (footprint "eagle-import:0603")
      (libsource (lib "eagle-import") (part "RESR0603"))
    )
    (comp (ref "R15")
      (value "0R")
      (footprint "eagle-import:0603")
      (libsource (lib "eagle-import") (part "RESR0603"))
    )
    (comp (ref "R16")
      (value "10k")
      (footprint "eagle-import:0603")
      (libsource (lib "eagle-import") (part "RESR0603"))
    )
    (comp (ref "R17")
      (value "12k")
      (footprint "eagle-import:0603")
      (libsource (lib "eagle-import") (part "RESR0603"))
    )
    (comp (ref "R18")
      (value "2k2")
      (footprint "eagle-import:0402")
      (libsource (lib "eagle-import") (part "RESR0402"))
    )
    (comp (ref "R19")
      (value "10k")
      (footprint "eagle-import:0603")
      (libsource (lib "eagle-import") (part "RESR0603"))
    )
    (comp (ref "R20")
      (value "10k")
      (footprint "eagle-import:0603")
      (libsource (lib "eagle-import") (part "RESR0603"))
    )
    (comp (ref "R21")
      (value "10k")
      (footprint "eagle-import:0603")
      (libsource (lib "eagle-import") (part "RESR0603"))
    )
    (comp (ref "R38")
      (value "47R")
      (footprint "eagle-import:0402")
      (libsource (lib "eagle-import") (part "RESR0402"))
    )
    (comp (ref "R39")
      (value "47R")
      (footprint "eagle-import:0402")
      (libsource (lib "eagle-import") (part "RESR0402"))
    )
    (comp (ref "R40")
      (value "47R")
      (footprint "eagle-import:0402")
      (libsource (lib "eagle-import") (part "RESR0402"))
    )
    (comp (ref "R51")
      (value "0R1")
      (footprint "eagle-import:0603")
      (libsource (lib "eagle-import") (part "RESR0603"))
    )
    (comp (ref "X1")
      (value "MINI-USB-32005-201")
      (footprint "eagle-import:32005-201")
      (libsource (lib "eagle-import") (part "MINI-USB-32005-201"))
    )
    (comp (ref "C230")
      (value "10uF")
      (footprint "eagle-import:0603")
      (libsource (lib "eagle-import") (part "CAPC0603"))
    )
    (comp (ref "C231")
      (value "100nF")
      (footprint "eagle-import:0402")
      (libsource (lib "eagle-import") (part "CAPC0402"))
    )
    (comp (ref "C232")
      (value "100nF")
      (footprint "eagle-import:0402")
      (libsource (lib "eagle-import") (part "CAPC0402"))
    )
    (comp (ref "C233")
      (value "100nF")
      (footprint "eagle-import:0402")
      (libsource (lib "eagle-import") (part "CAPC0402"))
    )
    (comp (ref "C234")
      (value "100nF")
      (footprint "eagle-import:0402")
      (libsource (lib "eagle-import") (part "CAPC0402"))
    )
    (comp (ref "C235")
      (value "100nF")
      (footprint "eagle-import:0402")
      (libsource (lib "eagle-import") (part "CAPC0402"))
    )
    (comp (ref "C236")
      (value "100nF")
      (footprint "eagle-import:0603")
      (fields (field (name "VOLTAGE") "50V"))
      (libsource (lib "eagle-import") (part "CAPC0603"))
    )
    (comp (ref "C237")
      (value "12pF")
      (footprint "eagle-import:0603")
      (libsource (lib "eagle-import") (part "CAPC0603"))
    )
    (comp (ref "C238")
      (value "6/30")
      (footprint "eagle-import:CTRIMTZBX4")
      (libsource (lib "eagle-import") (part "C-TRIMMTZBX4"))
    )
    (comp (ref "C239")
      (value "12pF")
      (footprint "eagle-import:0603")
      (libsource (lib "eagle-import") (part "CAPC0603"))
    )
    (comp (ref "C240")
      (value "220pF")
      (footprint "eagle-import:0603")
      (libsource (lib "eagle-import") (part "CAPC0603"))
    )
    (comp (ref "C241")
      (value "6/30")
      (footprint "eagle-import:CTRIMTZBX4")
      (libsource (lib "eagle-import") (part "C-TRIMMTZBX4"))
    )
    (comp (ref "C242")
      (value "12pF")
      (footprint "eagle-import:0603")
      (libsource (lib "eagle-import") (part "CAPC0603"))
    )
    (comp (ref "C243")
      (value "100nF")
      (footprint "eagle-import:0402")
      (libsource (lib "eagle-import") (part "CAPC0402"))
    )
    (comp (ref "C244")
      (value "100nF")
      (footprint "eagle-import:0402")
      (libsource (lib "eagle-import") (part "CAPC0402"))
    )
    (comp (ref "C245")
      (value "100nF")
      (footprint "eagle-import:0402")
      (libsource (lib "eagle-import") (part "CAPC0402"))
    )
    (comp (ref "C246")
      (value "100nF")
      (footprint "eagle-import:0402")
      (libsource (lib "eagle-import") (part "CAPC0402"))
    )
    (comp (ref "C247")
      (value "12pF")
      (footprint "eagle-import:0603")
      (libsource (lib "eagle-import") (part "CAPC0603"))
    )
    (comp (ref "C248")
      (value "12pF")
      (footprint "eagle-import:0603")
      (libsource (lib "eagle-import") (part "CAPC0603"))
    )
    (comp (ref "C249")
      (value "100uF")
      (footprint "eagle-import:1206")
      (libsource (lib "eagle-import") (part "CAPC1206"))
    )
    (comp (ref "C250")
      (value "100nF")
      (footprint "eagle-import:0402")
      (libsource (lib "eagle-import") (part "CAPC0402"))
    )
    (comp (ref "C251")
      (value "100nF")
      (footprint "eagle-import:0402")
      (libsource (lib "eagle-import") (part "CAPC0402"))
    )
    (comp (ref "C252")
      (value "100nF")
      (footprint "eagle-import:0402")
      (libsource (lib "eagle-import") (part "CAPC0402"))
    )
    (comp (ref "C253")
      (value "1pF")
      (footprint "eagle-import:0603")
      (libsource (lib "eagle-import") (part "CAPC0603"))
    )
    (comp (ref "C254")
      (value "1pF")
      (footprint "eagle-import:0603")
      (libsource (lib "eagle-import") (part "CAPC0603"))
    )
    (comp (ref "IC38")
      (value "ADA4853-3RU")
      (footprint "eagle-import:SO14")
      (libsource (lib "eagle-import") (part "ADA4853-3RU"))
    )
    (comp (ref "IC39")
      (value "4052D")
      (footprint "eagle-import:SO16")
      (libsource (lib "eagle-import") (part "4052D"))
    )
    (comp (ref "IC40")
      (value "4052D")
      (footprint "eagle-import:SO16")
      (libsource (lib "eagle-import") (part "4052D"))
    )
    (comp (ref "IC41")
      (value "OPA2354")
      (footprint "eagle-import:MSOP08")
      (libsource (lib "eagle-import") (part "AD8682RM"))
    )
    (comp (ref "IC42")
      (value "74HC595D")
      (footprint "eagle-import:SO16")
      (libsource (lib "eagle-import") (part "74595DHC"))
    )
    (comp (ref "K3")
      (value "G6K-2F-Y")
      (footprint "eagle-import:G6K-2F-Y")
      (fields (field (name "MF") "OMRON COMPONENTS USA") (field (name "MPN") "G6K-2F-Y DC3"))
      (libsource (lib "eagle-import") (part "G6K-2F-Y"))
    )
    (comp (ref "K4")
      (value "G6K-2F-Y")
      (footprint "eagle-import:G6K-2F-Y")
      (fields (field (name "MF") "OMRON COMPONENTS USA") (field (name "MPN") "G6K-2F-Y DC3"))
      (libsource (lib "eagle-import") (part "G6K-2F-Y"))
    )
    (comp (ref "L14")
      (value "1uH")
      (footprint "eagle-import:L3216C")
      (libsource (lib "eagle-import") (part "L-EUL3216C"))
    )
    (comp (ref "R244")
      (value "200R")
      (footprint "eagle-import:0603")
      (libsource (lib "eagle-import") (part "RESR0603"))
    )
    (comp (ref "R245")
      (value "30R")
      (footprint "eagle-import:0603")
      (libsource (lib "eagle-import") (part "RESR0603"))
    )
    (comp (ref "R246")
      (value "20R")
      (footprint "eagle-import:0603")
      (libsource (lib "eagle-import") (part "RESR0603"))
    )
    (comp (ref "R247")
      (value "22R")
      (footprint "eagle-import:0603")
      (libsource (lib "eagle-import") (part "RESR0603"))
    )
    (comp (ref "R248")
      (value "300R")
      (footprint "eagle-import:0603")
      (libsource (lib "eagle-import") (part "RESR0603"))
    )
    (comp (ref "R249")
      (value "100R")
      (footprint "eagle-import:0603")
      (libsource (lib "eagle-import") (part "RESR0603"))
    )
    (comp (ref "R250")
      (value "22R")
      (footprint "eagle-import:0603")
      (libsource (lib "eagle-import") (part "RESR0603"))
    )
    (comp (ref "R251")
      (value "300R")
      (footprint "eagle-import:0603")
      (libsource (lib "eagle-import") (part "RESR0603"))
    )
    (comp (ref "R252")
      (value "300R")
      (footprint "eagle-import:0603")
      (libsource (lib "eagle-import") (part "RESR0603"))
    )
    (comp (ref "R253")
      (value "22R")
      (footprint "eagle-import:0603")
      (libsource (lib "eagle-import") (part "RESR0603"))
    )
    (comp (ref "R254")
      (value "10k")
      (footprint "eagle-import:0603")
      (libsource (lib "eagle-import") (part "RESR0603"))
    )
    (comp (ref "R255")
      (value "10k")
      (footprint "eagle-import:0603")
      (libsource (lib "eagle-import") (part "RESR0603"))
    )
    (comp (ref "R256")
      (value "10k")
      (footprint "eagle-import:0603")
      (libsource (lib "eagle-import") (part "RESR0603"))
    )
    (comp (ref "R257")
      (value "30k")
      (footprint "eagle-import:0603")
      (libsource (lib "eagle-import") (part "RESR0603"))
    )
    (comp (ref "R258")
      (value "30k")
      (footprint "eagle-import:0603")
      (libsource (lib "eagle-import") (part "RESR0603"))
    )
    (comp (ref "R259")
      (value "470k")
      (footprint "eagle-import:0603")
      (libsource (lib "eagle-import") (part "RESR0603"))
    )
    (comp (ref "R260")
      (value "470k")
      (footprint "eagle-import:0603")
      (libsource (lib "eagle-import") (part "RESR0603"))
    )
    (comp (ref "R261")
      (value "130k")
      (footprint "eagle-import:0603")
      (libsource (lib "eagle-import") (part "RESR0603"))
    )
    (comp (ref "R262")
      (value "47k")
      (footprint "eagle-import:0603")
      (libsource (lib "eagle-import") (part "RESR0603"))
    )
    (comp (ref "R263")
      (value "820k")
      (footprint "eagle-import:0603")
      (libsource (lib "eagle-import") (part "RESR0603"))
    )
    (comp (ref "R264")
      (value "3k")
      (footprint "eagle-import:0603")
      (libsource (lib "eagle-import") (part "RESR0603"))
    )
    (comp (ref "R265")
      (value "300R")
      (footprint "eagle-import:0603")
      (libsource (lib "eagle-import") (part "RESR0603"))
    )
    (comp (ref "R266")
      (value "300R")
      (footprint "eagle-import:0603")
      (libsource (lib "eagle-import") (part "RESR0603"))
    )
    (comp (ref "R267")
      (value "7R5")
      (footprint "eagle-import:0603")
      (libsource (lib "eagle-import") (part "RESR0603"))
    )
    (comp (ref "R268")
      (value "10R")
      (footprint "eagle-import:0603")
      (libsource (lib "eagle-import") (part "RESR0603"))
    )
    (comp (ref "R269")
      (value "10R")
      (footprint "eagle-import:0603")
      (libsource (lib "eagle-import") (part "RESR0603"))
    )
    (comp (ref "R270")
      (value "10R")
      (footprint "eagle-import:0603")
      (libsource (lib "eagle-import") (part "RESR0603"))
    )
    (comp (ref "R271")
      (value "10R")
      (footprint "eagle-import:0603")
      (libsource (lib "eagle-import") (part "RESR0603"))
    )
    (comp (ref "R272")
      (value "10R")
      (footprint "eagle-import:0603")
      (libsource (lib "eagle-import") (part "RESR0603"))
    )
    (comp (ref "R273")
      (value "22R")
      (footprint "eagle-import:0603")
      (libsource (lib "eagle-import") (part "RESR0603"))
    )
    (comp (ref "R274")
      (value "300R")
      (footprint "eagle-import:0603")
      (libsource (lib "eagle-import") (part "RESR0603"))
    )
    (comp (ref "R275")
      (value "22R")
      (footprint "eagle-import:0603")
      (libsource (lib "eagle-import") (part "RESR0603"))
    )
    (comp (ref "R276")
      (value "1R")
      (footprint "eagle-import:0603")
      (libsource (lib "eagle-import") (part "RESR0603"))
    )
    (comp (ref "R277")
      (value "100R")
      (footprint "eagle-import:0603")
      (libsource (lib "eagle-import") (part "RESR0603"))
    )
    (comp (ref "R278")
      (value "22R")
      (footprint "eagle-import:0603")
      (libsource (lib "eagle-import") (part "RESR0603"))
    )
    (comp (ref "R279")
      (value "22R")
      (footprint "eagle-import:0603")
      (libsource (lib "eagle-import") (part "RESR0603"))
    )
    (comp (ref "T10")
      (value "BC850")
      (footprint "eagle-import:SOT23")
      (libsource (lib "eagle-import") (part "BC850"))
    )
    (comp (ref "T11")
      (value "BC850")
      (footprint "eagle-import:SOT23")
      (libsource (lib "eagle-import") (part "BC850"))
    )
    (comp (ref "T12")
      (value "BC856ASMD")
      (footprint "eagle-import:SOT23-BEC")
      (libsource (lib "eagle-import") (part "BC856SMDA"))
    )
    (comp (ref "T13")
      (value "BC856ASMD")
      (footprint "eagle-import:SOT23-BEC")
      (libsource (lib "eagle-import") (part "BC856SMDA"))
    )
    (comp (ref "T14")
      (value "BC850")
      (footprint "eagle-import:SOT23")
      (libsource (lib "eagle-import") (part "BC850"))
    )
    (comp (ref "T15")
      (value "BC856ASMD")
      (footprint "eagle-import:SOT23-BEC")
      (libsource (lib "eagle-import") (part "BC856SMDA"))
    )
    (comp (ref "T16")
      (value "BC850")
      (footprint "eagle-import:SOT23")
      (libsource (lib "eagle-import") (part "BC850"))
    )
    (comp (ref "T17")
      (value "BC856ASMD")
      (footprint "eagle-import:SOT23-BEC")
      (libsource (lib "eagle-import") (part "BC856SMDA"))
    )
    (comp (ref "X3")
      (value "31-5431-10RFX")
      (footprint "eagle-import:AMP_227161")
      (libsource (lib "eagle-import") (part "?227161-8"))
    )
    (comp (ref "C8")
      (value "470nF")
      (footprint "eagle-import:0402")
      (libsource (lib "eagle-import") (part "CAPC0402"))
    )
    (comp (ref "C9")
      (value "470nF")
      (footprint "eagle-import:0402")
      (libsource (lib "eagle-import") (part "CAPC0402"))
    )
    (comp (ref "C10")
      (value "470nF")
      (footprint "eagle-import:0402")
      (libsource (lib "eagle-import") (part "CAPC0402"))
    )
    (comp (ref "C11")
      (value "100uF")
      (footprint "eagle-import:1206")
      (libsource (lib "eagle-import") (part "CAPC1206"))
    )
    (comp (ref "C12")
      (value "10uF")
      (footprint "eagle-import:0603")
      (libsource (lib "eagle-import") (part "CAPC0603"))
    )
    (comp (ref "C13")
      (value "470nF")
      (footprint "eagle-import:0402")
      (libsource (lib "eagle-import") (part "CAPC0402"))
    )
    (comp (ref "C14")
      (value "470nF")
      (footprint "eagle-import:0402")
      (libsource (lib "eagle-import") (part "CAPC0402"))
    )
    (comp (ref "C15")
      (value "470nF")
      (footprint "eagle-import:0402")
      (libsource (lib "eagle-import") (part "CAPC0402"))
    )
    (comp (ref "C16")
      (value "470nF")
      (footprint "eagle-import:0402")
      (libsource (lib "eagle-import") (part "CAPC0402"))
    )
    (comp (ref "C17")
      (value "470nF")
      (footprint "eagle-import:0402")
      (libsource (lib "eagle-import") (part "CAPC0402"))
    )
    (comp (ref "C18")
      (value "470nF")
      (footprint "eagle-import:0402")
      (libsource (lib "eagle-import") (part "CAPC0402"))
    )
    (comp (ref "C20")
      (value "470nF")
      (footprint "eagle-import:0402")
      (libsource (lib "eagle-import") (part "CAPC0402"))
    )
    (comp (ref "C142")
      (value "470nF")
      (footprint "eagle-import:0402")
      (libsource (lib "eagle-import") (part "CAPC0402"))
    )
    (comp (ref "C143")
      (value "470nF")
      (footprint "eagle-import:0402")
      (libsource (lib "eagle-import") (part "CAPC0402"))
    )
    (comp (ref "C144")
      (value "470nF")
      (footprint "eagle-import:0402")
      (libsource (lib "eagle-import") (part "CAPC0402"))
    )
    (comp (ref "IC26")
      (value "MT41J128M8")
      (footprint "eagle-import:FBGA78")
      (libsource (lib "eagle-import") (part "MT41J128M8"))
    )
    (comp (ref "R1")
      (value "100R")
      (footprint "eagle-import:0402")
      (libsource (lib "eagle-import") (part "RESR0402"))
    )
    (comp (ref "R2")
      (value "100R")
      (footprint "eagle-import:0402")
      (libsource (lib "eagle-import") (part "RESR0402"))
    )
    (comp (ref "R3")
      (value "240R")
      (footprint "eagle-import:0603")
      (libsource (lib "eagle-import") (part "RESR0603"))
    )
    (comp (ref "R4")
      (value "4k7")
      (footprint "eagle-import:0402")
      (libsource (lib "eagle-import") (part "RESR0402"))
    )
    (comp (ref "R7")
      (value "4k7")
      (footprint "eagle-import:0402")
      (libsource (lib "eagle-import") (part "RESR0402"))
    )
    (comp (ref "C149")
      (value "100pF")
      (footprint "eagle-import:0603")
      (libsource (lib "eagle-import") (part "CAPC0603"))
    )
    (comp (ref "C151")
      (value "47pF")
      (footprint "eagle-import:0603")
      (libsource (lib "eagle-import") (part "CAPC0603"))
    )
    (comp (ref "C152")
      (value "47pF")
      (footprint "eagle-import:0603")
      (libsource (lib "eagle-import") (part "CAPC0603"))
    )
    (comp (ref "C153")
      (value "100nF")
      (footprint "eagle-import:0402")
      (libsource (lib "eagle-import") (part "CAPC0402"))
    )
    (comp (ref "C154")
      (value "100nF")
      (footprint "eagle-import:0402")
      (libsource (lib "eagle-import") (part "CAPC0402"))
    )
    (comp (ref "C155")
      (value "100nF")
      (footprint "eagle-import:0402")
      (libsource (lib "eagle-import") (part "CAPC0402"))
    )
    (comp (ref "C156")
      (value "100nF")
      (footprint "eagle-import:0402")
      (libsource (lib "eagle-import") (part "CAPC0402"))
    )
    (comp (ref "C157")
      (value "100uF")
      (footprint "eagle-import:CT6032")
      (libsource (lib "eagle-import") (part "CPOL-EUCT6032"))
    )
    (comp (ref "C158")
      (value "100uF")
      (footprint "eagle-import:CT6032")
      (libsource (lib "eagle-import") (part "CPOL-EUCT6032"))
    )
    (comp (ref "C159")
      (value "100uF")
      (footprint "eagle-import:CT6032")
      (libsource (lib "eagle-import") (part "CPOL-EUCT6032"))
    )
    (comp (ref "C160")
      (value "100nF")
      (footprint "eagle-import:0402")
      (libsource (lib "eagle-import") (part "CAPC0402"))
    )
    (comp (ref "C161")
      (value "100uF")
      (footprint "eagle-import:CT6032")
      (libsource (lib "eagle-import") (part "CPOL-EUCT6032"))
    )
    (comp (ref "D1")
      (value "SK14")
      (footprint "eagle-import:DO214AC")
      (libsource (lib "eagle-import") (part "DIODE-DO214AC"))
    )
    (comp (ref "D2")
      (value "SK14")
      (footprint "eagle-import:DO214AC")
      (libsource (lib "eagle-import") (part "DIODE-DO214AC"))
    )
    (comp (ref "D3")
      (value "SK14")
      (footprint "eagle-import:DO214AC")
      (libsource (lib "eagle-import") (part "DIODE-DO214AC"))
    )
    (comp (ref "D4")
      (value "SK14")
      (footprint "eagle-import:DO214AC")
      (libsource (lib "eagle-import") (part "DIODE-DO214AC"))
    )
    (comp (ref "D5")
      (value "SK14")
      (footprint "eagle-import:DO214AC")
      (libsource (lib "eagle-import") (part "DIODE-DO214AC"))
    )
    (comp (ref "D6")
      (value "SK14")
      (footprint "eagle-import:DO214AC")
      (libsource (lib "eagle-import") (part "DIODE-DO214AC"))
    )
    (comp (ref "IC24")
      (value "74HC00D")
      (footprint "eagle-import:SO14")
      (libsource (lib "eagle-import") (part "7400DHC"))
    )
    (comp (ref "IC27")
      (value "74HCT132D")
      (footprint "eagle-import:SO14")
      (libsource (lib "eagle-import") (part "74132DHCT"))
    )
    (comp (ref "Q2")
      (value "FDN335N")
      (footprint "eagle-import:SOT23")
      (libsource (lib "eagle-import") (part "BSS123"))
    )
    (comp (ref "Q3")
      (value "FDN335N")
      (footprint "eagle-import:SOT23")
      (libsource (lib "eagle-import") (part "BSS123"))
    )
    (comp (ref "R157")
      (value "10k")
      (footprint "eagle-import:0603")
      (libsource (lib "eagle-import") (part "RESR0603"))
    )
    (comp (ref "R158")
      (value "10k")
      (footprint "eagle-import:0603")
      (libsource (lib "eagle-import") (part "RESR0603"))
    )
    (comp (ref "R159")
      (value "1k5")
      (footprint "eagle-import:0603")
      (libsource (lib "eagle-import") (part "RESR0603"))
    )
    (comp (ref "R160")
      (value "1k5")
      (footprint "eagle-import:0603")
      (libsource (lib "eagle-import") (part "RESR0603"))
    )
    (comp (ref "R161")
      (value "150R")
      (footprint "eagle-import:0603")
      (libsource (lib "eagle-import") (part "RESR0603"))
    )
    (comp (ref "R162")
      (value "150R")
      (footprint "eagle-import:0603")
      (libsource (lib "eagle-import") (part "RESR0603"))
    )
    (comp (ref "T1")
      (value "EFD15DCDCPM5P33EFD15")
      (footprint "eagle-import:B66414-W1008-D1")
      (libsource (lib "eagle-import") (part "EFD15DCDCPM5P33EFD15"))
    )
    (comp (ref "C21")
      (value "100uF")
      (footprint "eagle-import:1206")
      (libsource (lib "eagle-import") (part "CAPC1206"))
    )
    (comp (ref "C23")
      (value "100uF")
      (footprint "eagle-import:1206")
      (libsource (lib "eagle-import") (part "CAPC1206"))
    )
    (comp (ref "C24")
      (value "10uF")
      (footprint "eagle-import:0603")
      (libsource (lib "eagle-import") (part "CAPC0603"))
    )
    (comp (ref "C25")
      (value "470nF")
      (footprint "eagle-import:0402")
      (libsource (lib "eagle-import") (part "CAPC0402"))
    )
    (comp (ref "C26")
      (value "100nF")
      (footprint "eagle-import:0402")
      (libsource (lib "eagle-import") (part "CAPC0402"))
    )
    (comp (ref "C28")
      (value "470nF")
      (footprint "eagle-import:0402")
      (libsource (lib "eagle-import") (part "CAPC0402"))
    )
    (comp (ref "C29")
      (value "4u7")
      (footprint "eagle-import:0603")
      (libsource (lib "eagle-import") (part "CAPC0603"))
    )
    (comp (ref "C30")
      (value "4u7")
      (footprint "eagle-import:0603")
      (libsource (lib "eagle-import") (part "CAPC0603"))
    )
    (comp (ref "C31")
      (value "4u7")
      (footprint "eagle-import:0603")
      (libsource (lib "eagle-import") (part "CAPC0603"))
    )
    (comp (ref "C32")
      (value "470nF")
      (footprint "eagle-import:0402")
      (libsource (lib "eagle-import") (part "CAPC0402"))
    )
    (comp (ref "C33")
      (value "470nF")
      (footprint "eagle-import:0402")
      (libsource (lib "eagle-import") (part "CAPC0402"))
    )
    (comp (ref "C34")
      (value "10uF")
      (footprint "eagle-import:0603")
      (libsource (lib "eagle-import") (part "CAPC0603"))
    )
    (comp (ref "C35")
      (value "100uF")
      (footprint "eagle-import:1206")
      (libsource (lib "eagle-import") (part "CAPC1206"))
    )
    (comp (ref "C36")
      (value "100nF")
      (footprint "eagle-import:0402")
      (libsource (lib "eagle-import") (part "CAPC0402"))
    )
    (comp (ref "C37")
      (value "100nF")
      (footprint "eagle-import:0402")
      (libsource (lib "eagle-import") (part "CAPC0402"))
    )
    (comp (ref "C38")
      (value "100nF")
      (footprint "eagle-import:0402")
      (libsource (lib "eagle-import") (part "CAPC0402"))
    )
    (comp (ref "C164")
      (value "470nF")
      (footprint "eagle-import:0402")
      (libsource (lib "eagle-import") (part "CAPC0402"))
    )
    (comp (ref "C165")
      (value "10uF")
      (footprint "eagle-import:0603")
      (libsource (lib "eagle-import") (part "CAPC0603"))
    )
    (comp (ref "C166")
      (value "100uF")
      (footprint "eagle-import:1206")
      (libsource (lib "eagle-import") (part "CAPC1206"))
    )
    (comp (ref "C167")
      (value "470nF")
      (footprint "eagle-import:0402")
      (libsource (lib "eagle-import") (part "CAPC0402"))
    )
    (comp (ref "IC2")
      (value "25px80")
      (footprint "eagle-import:SO-08")
      (fields (field (name "MF") "MICROCHIP") (field (name "MPN") "25AA080/SN"))
      (libsource (lib "eagle-import") (part "25SNAA080"))
    )
    (comp (ref "IC3")
      (value "SI8462")
      (footprint "eagle-import:SO16")
      (libsource (lib "eagle-import") (part "SI8462"))
    )
    (comp (ref "QG1")
      (value "SM77H")
      (footprint "eagle-import:SM77H")
      (libsource (lib "eagle-import") (part "SM77H"))
    )
    (comp (ref "R5")
      (value "47R")
      (footprint "eagle-import:0402")
      (libsource (lib "eagle-import") (part "RESR0402"))
    )
    (comp (ref "R6")
      (value "4k7")
      (footprint "eagle-import:0402")
      (libsource (lib "eagle-import") (part "RESR0402"))
    )
    (comp (ref "R8")
      (value "1M")
      (footprint "eagle-import:0402")
      (libsource (lib "eagle-import") (part "RESR0402"))
    )
    (comp (ref "R9")
      (value "1M")
      (footprint "eagle-import:0402")
      (libsource (lib "eagle-import") (part "RESR0402"))
    )
    (comp (ref "R10")
      (value "4k7")
      (footprint "eagle-import:0402")
      (libsource (lib "eagle-import") (part "RESR0402"))
    )
    (comp (ref "R11")
      (value "4k7")
      (footprint "eagle-import:0402")
      (libsource (lib "eagle-import") (part "RESR0402"))
    )
    (comp (ref "R12")
      (value "330R")
      (footprint "eagle-import:0402")
      (libsource (lib "eagle-import") (part "RESR0402"))
    )
    (comp (ref "R41")
      (value "47R")
      (footprint "eagle-import:0402")
      (libsource (lib "eagle-import") (part "RESR0402"))
    )
    (comp (ref "R42")
      (value "47R")
      (footprint "eagle-import:0402")
      (libsource (lib "eagle-import") (part "RESR0402"))
    )
    (comp (ref "R43")
      (value "47R")
      (footprint "eagle-import:0402")
      (libsource (lib "eagle-import") (part "RESR0402"))
    )
    (comp (ref "R44")
      (value "47R")
      (footprint "eagle-import:0402")
      (libsource (lib "eagle-import") (part "RESR0402"))
    )
    (comp (ref "R45")
      (value "47R")
      (footprint "eagle-import:0402")
      (libsource (lib "eagle-import") (part "RESR0402"))
    )
    (comp (ref "R88")
      (value "4k7")
      (footprint "eagle-import:0402")
      (libsource (lib "eagle-import") (part "RESR0402"))
    )
    (comp (ref "R89")
      (value "4k7")
      (footprint "eagle-import:0402")
      (libsource (lib "eagle-import") (part "RESR0402"))
    )
    (comp (ref "R169")
      (value "1M")
      (footprint "eagle-import:0402")
      (libsource (lib "eagle-import") (part "RESR0402"))
    )
    (comp (ref "SV1")
      (value "2x5 Pinheader")
      (footprint "eagle-import:ML10")
      (libsource (lib "eagle-import") (part "ML10"))
    )
    (comp (ref "C1")
      (value "33pF")
      (footprint "eagle-import:0603")
      (libsource (lib "eagle-import") (part "CAPC0603"))
    )
    (comp (ref "C2")
      (value "10uF")
      (footprint "eagle-import:0603")
      (libsource (lib "eagle-import") (part "CAPC0603"))
    )
    (comp (ref "C3")
      (value "10uF")
      (footprint "eagle-import:0603")
      (libsource (lib "eagle-import") (part "CAPC0603"))
    )
    (comp (ref "C78")
      (value "33pF")
      (footprint "eagle-import:0603")
      (libsource (lib "eagle-import") (part "CAPC0603"))
    )
    (comp (ref "C79")
      (value "10uF")
      (footprint "eagle-import:0603")
      (libsource (lib "eagle-import") (part "CAPC0603"))
    )
    (comp (ref "C80")
      (value "10uF")
      (footprint "eagle-import:0603")
      (libsource (lib "eagle-import") (part "CAPC0603"))
    )
    (comp (ref "C81")
      (value "10uF")
      (footprint "eagle-import:0603")
      (libsource (lib "eagle-import") (part "CAPC0603"))
    )
    (comp (ref "C82")
      (value "10uF")
      (footprint "eagle-import:0603")
      (libsource (lib "eagle-import") (part "CAPC0603"))
    )
    (comp (ref "C83")
      (value "10nF")
      (footprint "eagle-import:0402")
      (libsource (lib "eagle-import") (part "CAPC0402"))
    )
    (comp (ref "C84")
      (value "1uF")
      (footprint "eagle-import:0603")
      (libsource (lib "eagle-import") (part "CAPC0603"))
    )
    (comp (ref "C85")
      (value "15pF")
      (footprint "eagle-import:0603")
      (libsource (lib "eagle-import") (part "CAPC0603"))
    )
    (comp (ref "C86")
      (value "10uF")
      (footprint "eagle-import:0603")
      (libsource (lib "eagle-import") (part "CAPC0603"))
    )
    (comp (ref "C87")
      (value "10nF")
      (footprint "eagle-import:0402")
      (libsource (lib "eagle-import") (part "CAPC0402"))
    )
    (comp (ref "C88")
      (value "10uF")
      (footprint "eagle-import:0603")
      (libsource (lib "eagle-import") (part "CAPC0603"))
    )
    (comp (ref "C92")
      (value "10uF")
      (footprint "eagle-import:0603")
      (libsource (lib "eagle-import") (part "CAPC0603"))
    )
    (comp (ref "C93")
      (value "10uF")
      (footprint "eagle-import:0603")
      (libsource (lib "eagle-import") (part "CAPC0603"))
    )
    (comp (ref "C162")
      (value "1uF")
      (footprint "eagle-import:0603")
      (libsource (lib "eagle-import") (part "CAPC0603"))
    )
    (comp (ref "C163")
      (value "15pF")
      (footprint "eagle-import:0603")
      (libsource (lib "eagle-import") (part "CAPC0603"))
    )
    (comp (ref "C168")
      (value "10uF")
      (footprint "eagle-import:0603")
      (libsource (lib "eagle-import") (part "CAPC0603"))
    )
    (comp (ref "C169")
      (value "10uF")
      (footprint "eagle-import:0603")
      (libsource (lib "eagle-import") (part "CAPC0603"))
    )
    (comp (ref "C170")
      (value "10uF")
      (footprint "eagle-import:0603")
      (libsource (lib "eagle-import") (part "CAPC0603"))
    )
    (comp (ref "C171")
      (value "10uF")
      (footprint "eagle-import:0603")
      (libsource (lib "eagle-import") (part "CAPC0603"))
    )
    (comp (ref "C172")
      (value "10nF")
      (footprint "eagle-import:0402")
      (libsource (lib "eagle-import") (part "CAPC0402"))
    )
    (comp (ref "C173")
      (value "1uF")
      (footprint "eagle-import:0603")
      (libsource (lib "eagle-import") (part "CAPC0603"))
    )
    (comp (ref "C174")
      (value "15pF")
      (footprint "eagle-import:0603")
      (libsource (lib "eagle-import") (part "CAPC0603"))
    )
    (comp (ref "C175")
      (value "10uF")
      (footprint "eagle-import:0603")
      (libsource (lib "eagle-import") (part "CAPC0603"))
    )
    (comp (ref "C176")
      (value "10uF")
      (footprint "eagle-import:0603")
      (libsource (lib "eagle-import") (part "CAPC0603"))
    )
    (comp (ref "IC1")
      (value "TPS62240DDC")
      (footprint "eagle-import:SOT23-5L")
      (libsource (lib "eagle-import") (part "TPS62560"))
    )
    (comp (ref "IC10")
      (value "TPS62240DDC")
      (footprint "eagle-import:SOT23-5L")
      (libsource (lib "eagle-import") (part "TPS62560"))
    )
    (comp (ref "IC11")
      (value "TPS73001DBVR")
      (footprint "eagle-import:SOT23-6L")
      (libsource (lib "eagle-import") (part "TPS73001"))
    )
    (comp (ref "IC12")
      (value "TPS73001DBVR")
      (footprint "eagle-import:SOT23-6L")
      (libsource (lib "eagle-import") (part "TPS73001"))
    )
    (comp (ref "IC14")
      (value "TPS72301")
      (footprint "eagle-import:SOT23-5L")
      (libsource (lib "eagle-import") (part "TPS72301"))
    )
    (comp (ref "IC28")
      (value "TPS72301")
      (footprint "eagle-import:SOT23-5L")
      (libsource (lib "eagle-import") (part "TPS72301"))
    )
    (comp (ref "IC29")
      (value "TPS73001DBVR")
      (footprint "eagle-import:SOT23-6L")
      (libsource (lib "eagle-import") (part "TPS73001"))
    )
    (comp (ref "L7")
      (value "2.2uH")
      (footprint "eagle-import:L3216C")
      (libsource (lib "eagle-import") (part "L-USL3216C"))
    )
    (comp (ref "L13")
      (value "2.2uH")
      (footprint "eagle-import:L3216C")
      (libsource (lib "eagle-import") (part "L-USL3216C"))
    )
    (comp (ref "R46")
      (value "360k")
      (footprint "eagle-import:0603")
      (libsource (lib "eagle-import") (part "RESR0603"))
    )
    (comp (ref "R47")
      (value "360k")
      (footprint "eagle-import:0603")
      (libsource (lib "eagle-import") (part "RESR0603"))
    )
    (comp (ref "R48")
      (value "0R1")
      (footprint "eagle-import:0603")
      (libsource (lib "eagle-import") (part "RESR0603"))
    )
    (comp (ref "R49")
      (value "0R1")
      (footprint "eagle-import:0603")
      (libsource (lib "eagle-import") (part "RESR0603"))
    )
    (comp (ref "R50")
      (value "0R1")
      (footprint "eagle-import:0603")
      (libsource (lib "eagle-import") (part "RESR0603"))
    )
    (comp (ref "R52")
      (value "43k")
      (footprint "eagle-import:0603")
      (libsource (lib "eagle-import") (part "RESR0603"))
    )
    (comp (ref "R53")
      (value "39k")
      (footprint "eagle-import:0603")
      (libsource (lib "eagle-import") (part "RESR0603"))
    )
    (comp (ref "R107")
      (value "360k")
      (footprint "eagle-import:0603")
      (libsource (lib "eagle-import") (part "RESR0603"))
    )
    (comp (ref "R112")
      (value "240k")
      (footprint "eagle-import:0603")
      (libsource (lib "eagle-import") (part "RESR0603"))
    )
    (comp (ref "R163")
      (value "43k")
      (footprint "eagle-import:0603")
      (libsource (lib "eagle-import") (part "RESR0603"))
    )
    (comp (ref "R164")
      (value "30k")
      (footprint "eagle-import:0603")
      (libsource (lib "eagle-import") (part "RESR0603"))
    )
    (comp (ref "R165")
      (value "0R1")
      (footprint "eagle-import:0603")
      (libsource (lib "eagle-import") (part "RESR0603"))
    )
    (comp (ref "R166")
      (value "43k")
      (footprint "eagle-import:0603")
      (libsource (lib "eagle-import") (part "RESR0603"))
    )
    (comp (ref "R167")
      (value "30k")
      (footprint "eagle-import:0603")
      (libsource (lib "eagle-import") (part "RESR0603"))
    )
    (comp (ref "R168")
      (value "0R1")
      (footprint "eagle-import:0603")
      (libsource (lib "eagle-import") (part "RESR0603"))
    )
    (comp (ref "R170")
      (value "75k")
      (footprint "eagle-import:0603")
      (libsource (lib "eagle-import") (part "RESR0603"))
    )
    (comp (ref "R171")
      (value "22k")
      (footprint "eagle-import:0603")
      (libsource (lib "eagle-import") (part "RESR0603"))
    )
    (comp (ref "R172")
      (value "0R1")
      (footprint "eagle-import:0603")
      (libsource (lib "eagle-import") (part "RESR0603"))
    )
    (comp (ref "R173")
      (value "0R1")
      (footprint "eagle-import:0603")
      (libsource (lib "eagle-import") (part "RESR0603"))
    )
    (comp (ref "R174")
      (value "0R1")
      (footprint "eagle-import:0603")
      (libsource (lib "eagle-import") (part "RESR0603"))
    )
    (comp (ref "R175")
      (value "75k")
      (footprint "eagle-import:0603")
      (libsource (lib "eagle-import") (part "RESR0603"))
    )
    (comp (ref "R176")
      (value "24k")
      (footprint "eagle-import:0603")
      (libsource (lib "eagle-import") (part "RESR0603"))
    )
    (comp (ref "R177")
      (value "0R1")
      (footprint "eagle-import:0603")
      (libsource (lib "eagle-import") (part "RESR0603"))
    )
    (comp (ref "R178")
      (value "0R1")
      (footprint "eagle-import:0603")
      (libsource (lib "eagle-import") (part "RESR0603"))
    )
    (comp (ref "C96")
      (value "100nF")
      (footprint "eagle-import:0402")
      (libsource (lib "eagle-import") (part "CAPC0402"))
    )
    (comp (ref "C97")
      (value "100nF")
      (footprint "eagle-import:0402")
      (libsource (lib "eagle-import") (part "CAPC0402"))
    )
    (comp (ref "C98")
      (value "330pF")
      (footprint "eagle-import:0603")
      (fields (field (name "TYPE") "NP0/C0G"))
      (libsource (lib "eagle-import") (part "CAPC0603"))
    )
    (comp (ref "C99")
      (value "330pF")
      (footprint "eagle-import:0603")
      (fields (field (name "TYPE") "NP0/C0G"))
      (libsource (lib "eagle-import") (part "CAPC0603"))
    )
    (comp (ref "C100")
      (value "2n2")
      (footprint "eagle-import:0603")
      (fields (field (name "TYPE") "NP0/C0G"))
      (libsource (lib "eagle-import") (part "CAPC0603"))
    )
    (comp (ref "C101")
      (value "330pF")
      (footprint "eagle-import:0603")
      (fields (field (name "TYPE") "NP0/C0G"))
      (libsource (lib "eagle-import") (part "CAPC0603"))
    )
    (comp (ref "C102")
      (value "2n2")
      (footprint "eagle-import:0603")
      (fields (field (name "TYPE") "NP0/C0G"))
      (libsource (lib "eagle-import") (part "CAPC0603"))
    )
    (comp (ref "C103")
      (value "47uF")
      (footprint "eagle-import:1206")
      (fields (field (name "VOLTAGE") "10V"))
      (libsource (lib "eagle-import") (part "CAPC1206"))
    )
    (comp (ref "C113")
      (value "47uF")
      (footprint "eagle-import:1206")
      (fields (field (name "VOLTAGE") "10V"))
      (libsource (lib "eagle-import") (part "CAPC1206"))
    )
    (comp (ref "C114")
      (value "330pF")
      (footprint "eagle-import:0603")
      (fields (field (name "TYPE") "NP0/C0G"))
      (libsource (lib "eagle-import") (part "CAPC0603"))
    )
    (comp (ref "C115")
      (value "100nF")
      (footprint "eagle-import:0402")
      (libsource (lib "eagle-import") (part "CAPC0402"))
    )
    (comp (ref "C116")
      (value "100nF")
      (footprint "eagle-import:0402")
      (libsource (lib "eagle-import") (part "CAPC0402"))
    )
    (comp (ref "C117")
      (value "100nF")
      (footprint "eagle-import:0402")
      (libsource (lib "eagle-import") (part "CAPC0402"))
    )
    (comp (ref "C118")
      (value "100nF")
      (footprint "eagle-import:0402")
      (libsource (lib "eagle-import") (part "CAPC0402"))
    )
    (comp (ref "C119")
      (value "10uF")
      (footprint "eagle-import:0603")
      (libsource (lib "eagle-import") (part "CAPC0603"))
    )
    (comp (ref "C120")
      (value "10uF")
      (footprint "eagle-import:0603")
      (libsource (lib "eagle-import") (part "CAPC0603"))
    )
    (comp (ref "C121")
      (value "330pF")
      (footprint "eagle-import:0603")
      (fields (field (name "TYPE") "NP0/C0G"))
      (libsource (lib "eagle-import") (part "CAPC0603"))
    )
    (comp (ref "C122")
      (value "330pF")
      (footprint "eagle-import:0603")
      (fields (field (name "TYPE") "NP0/C0G"))
      (libsource (lib "eagle-import") (part "CAPC0603"))
    )
    (comp (ref "C123")
      (value "330pF")
      (footprint "eagle-import:0603")
      (fields (field (name "TYPE") "NP0/C0G"))
      (libsource (lib "eagle-import") (part "CAPC0603"))
    )
    (comp (ref "C124")
      (value "330pF")
      (footprint "eagle-import:0603")
      (fields (field (name "TYPE") "NP0/C0G"))
      (libsource (lib "eagle-import") (part "CAPC0603"))
    )
    (comp (ref "C125")
      (value "100nF")
      (footprint "eagle-import:0402")
      (libsource (lib "eagle-import") (part "CAPC0402"))
    )
    (comp (ref "C126")
      (value "100nF")
      (footprint "eagle-import:0402")
      (libsource (lib "eagle-import") (part "CAPC0402"))
    )
    (comp (ref "C127")
      (value "10nF")
      (footprint "eagle-import:0603")
      (fields (field (name "TYPE") "NP0/C0G"))
      (libsource (lib "eagle-import") (part "CAPC0603"))
    )
    (comp (ref "C128")
      (value "10nF")
      (footprint "eagle-import:0603")
      (fields (field (name "TYPE") "NP0/C0G"))
      (libsource (lib "eagle-import") (part "CAPC0603"))
    )
    (comp (ref "C129")
      (value "47uF")
      (footprint "eagle-import:1206")
      (fields (field (name "VOLTAGE") "10V"))
      (libsource (lib "eagle-import") (part "CAPC1206"))
    )
    (comp (ref "C130")
      (value "47uF")
      (footprint "eagle-import:1206")
      (fields (field (name "VOLTAGE") "10V"))
      (libsource (lib "eagle-import") (part "CAPC1206"))
    )
    (comp (ref "C131")
      (value "47uF")
      (footprint "eagle-import:1206")
      (fields (field (name "VOLTAGE") "10V"))
      (libsource (lib "eagle-import") (part "CAPC1206"))
    )
    (comp (ref "C132")
      (value "47uF")
      (footprint "eagle-import:1206")
      (fields (field (name "VOLTAGE") "10V"))
      (libsource (lib "eagle-import") (part "CAPC1206"))
    )
    (comp (ref "C133")
      (value "47uF")
      (footprint "eagle-import:1206")
      (fields (field (name "VOLTAGE") "10V"))
      (libsource (lib "eagle-import") (part "CAPC1206"))
    )
    (comp (ref "C134")
      (value "100nF")
      (footprint "eagle-import:0402")
      (libsource (lib "eagle-import") (part "CAPC0402"))
    )
    (comp (ref "C135")
      (value "47uF")
      (footprint "eagle-import:1206")
      (fields (field (name "VOLTAGE") "10V"))
      (libsource (lib "eagle-import") (part "CAPC1206"))
    )
    (comp (ref "C136")
      (value "47uF")
      (footprint "eagle-import:1206")
      (fields (field (name "VOLTAGE") "10V"))
      (libsource (lib "eagle-import") (part "CAPC1206"))
    )
    (comp (ref "C137")
      (value "100nF")
      (footprint "eagle-import:0402")
      (libsource (lib "eagle-import") (part "CAPC0402"))
    )
    (comp (ref "C138")
      (value "100nF")
      (footprint "eagle-import:0402")
      (libsource (lib "eagle-import") (part "CAPC0402"))
    )
    (comp (ref "C140")
      (value "100nF")
      (footprint "eagle-import:0402")
      (libsource (lib "eagle-import") (part "CAPC0402"))
    )
    (comp (ref "C141")
      (value "100nF")
      (footprint "eagle-import:0402")
      (libsource (lib "eagle-import") (part "CAPC0402"))
    )
    (comp (ref "C145")
      (value "100nF")
      (footprint "eagle-import:0402")
      (libsource (lib "eagle-import") (part "CAPC0402"))
    )
    (comp (ref "C146")
      (value "100nF")
      (footprint "eagle-import:0402")
      (libsource (lib "eagle-import") (part "CAPC0402"))
    )
    (comp (ref "C147")
      (value "100nF")
      (footprint "eagle-import:0402")
      (libsource (lib "eagle-import") (part "CAPC0402"))
    )
    (comp (ref "IC13")
      (value "AK4621")
      (footprint "eagle-import:VSOP30")
      (fields (field (name "MANFPART") "AK4621EF"))
      (libsource (lib "eagle-import") (part "AK4621"))
    )
    (comp (ref "IC15")
      (value "LME49721")
      (footprint "eagle-import:SO08")
      (libsource (lib "eagle-import") (part "LM358D"))
    )
    (comp (ref "IC16")
      (value "NE5532")
      (footprint "eagle-import:SO08")
      (libsource (lib "eagle-import") (part "LM358D"))
    )
    (comp (ref "IC17")
      (value "OPA2134")
      (footprint "eagle-import:SO08")
      (libsource (lib "eagle-import") (part "LM358D"))
    )
    (comp (ref "IC20")
      (value "ISL54405IRTZ")
      (footprint "eagle-import:TQFN3X3")
      (libsource (lib "eagle-import") (part "ISL54405IRTZ"))
    )
    (comp (ref "IC21")
      (value "NE5532")
      (footprint "eagle-import:SO08")
      (libsource (lib "eagle-import") (part "LM358D"))
    )
    (comp (ref "IC23")
      (value "LME49721")
      (footprint "eagle-import:SO08")
      (libsource (lib "eagle-import") (part "LM358D"))
    )
    (comp (ref "R56")
      (value "200R")
      (footprint "eagle-import:0603")
      (libsource (lib "eagle-import") (part "RESR0603"))
    )
    (comp (ref "R57")
      (value "200R")
      (footprint "eagle-import:0603")
      (libsource (lib "eagle-import") (part "RESR0603"))
    )
    (comp (ref "R58")
      (value "4k7")
      (footprint "eagle-import:0603")
      (libsource (lib "eagle-import") (part "RESR0603"))
    )
    (comp (ref "R59")
      (value "4k7")
      (footprint "eagle-import:0603")
      (libsource (lib "eagle-import") (part "RESR0603"))
    )
    (comp (ref "R60")
      (value "NC")
      (footprint "eagle-import:0402")
      (libsource (lib "eagle-import") (part "RESR0402"))
    )
    (comp (ref "R74")
      (value "4k7")
      (footprint "eagle-import:0603")
      (libsource (lib "eagle-import") (part "RESR0603"))
    )
    (comp (ref "R83")
      (value "4k7")
      (footprint "eagle-import:0603")
      (libsource (lib "eagle-import") (part "RESR0603"))
    )
    (comp (ref "R84")
      (value "4k7")
      (footprint "eagle-import:0603")
      (libsource (lib "eagle-import") (part "RESR0603"))
    )
    (comp (ref "R85")
      (value "4k7")
      (footprint "eagle-import:0603")
      (libsource (lib "eagle-import") (part "RESR0603"))
    )
    (comp (ref "R86")
      (value "100R")
      (footprint "eagle-import:0402")
      (libsource (lib "eagle-import") (part "RESR0402"))
    )
    (comp (ref "R87")
      (value "68R")
      (footprint "eagle-import:0603")
      (libsource (lib "eagle-import") (part "RESR0603"))
    )
    (comp (ref "R90")
      (value "47R")
      (footprint "eagle-import:0402")
      (libsource (lib "eagle-import") (part "RESR0402"))
    )
    (comp (ref "R91")
      (value "4k7")
      (footprint "eagle-import:0603")
      (libsource (lib "eagle-import") (part "RESR0603"))
    )
    (comp (ref "R92")
      (value "4k7")
      (footprint "eagle-import:0603")
      (libsource (lib "eagle-import") (part "RESR0603"))
    )
    (comp (ref "R93")
      (value "4k7")
      (footprint "eagle-import:0603")
      (libsource (lib "eagle-import") (part "RESR0603"))
    )
    (comp (ref "R94")
      (value "200R")
      (footprint "eagle-import:0603")
      (libsource (lib "eagle-import") (part "RESR0603"))
    )
    (comp (ref "R104")
      (value "4k7")
      (footprint "eagle-import:0603")
      (libsource (lib "eagle-import") (part "RESR0603"))
    )
    (comp (ref "R105")
      (value "200R")
      (footprint "eagle-import:0603")
      (libsource (lib "eagle-import") (part "RESR0603"))
    )
    (comp (ref "R106")
      (value "1k5")
      (footprint "eagle-import:0603")
      (libsource (lib "eagle-import") (part "RESR0603"))
    )
    (comp (ref "R132")
      (value "1k5")
      (footprint "eagle-import:0603")
      (libsource (lib "eagle-import") (part "RESR0603"))
    )
    (comp (ref "R133")
      (value "1k5")
      (footprint "eagle-import:0603")
      (libsource (lib "eagle-import") (part "RESR0603"))
    )
    (comp (ref "R134")
      (value "1k5")
      (footprint "eagle-import:0603")
      (libsource (lib "eagle-import") (part "RESR0603"))
    )
    (comp (ref "R135")
      (value "3k")
      (footprint "eagle-import:0603")
      (libsource (lib "eagle-import") (part "RESR0603"))
    )
    (comp (ref "R136")
      (value "3k")
      (footprint "eagle-import:0603")
      (libsource (lib "eagle-import") (part "RESR0603"))
    )
    (comp (ref "R137")
      (value "3k")
      (footprint "eagle-import:0603")
      (libsource (lib "eagle-import") (part "RESR0603"))
    )
    (comp (ref "R138")
      (value "3k")
      (footprint "eagle-import:0603")
      (libsource (lib "eagle-import") (part "RESR0603"))
    )
    (comp (ref "R139")
      (value "22R")
      (footprint "eagle-import:0603")
      (libsource (lib "eagle-import") (part "RESR0603"))
    )
    (comp (ref "R140")
      (value "22R")
      (footprint "eagle-import:0603")
      (libsource (lib "eagle-import") (part "RESR0603"))
    )
    (comp (ref "R141")
      (value "22R")
      (footprint "eagle-import:0603")
      (libsource (lib "eagle-import") (part "RESR0603"))
    )
    (comp (ref "R142")
      (value "22R")
      (footprint "eagle-import:0603")
      (libsource (lib "eagle-import") (part "RESR0603"))
    )
    (comp (ref "R143")
      (value "10k")
      (footprint "eagle-import:0603")
      (libsource (lib "eagle-import") (part "RESR0603"))
    )
    (comp (ref "R144")
      (value "10k")
      (footprint "eagle-import:0603")
      (libsource (lib "eagle-import") (part "RESR0603"))
    )
    (comp (ref "R145")
      (value "4k7")
      (footprint "eagle-import:0603")
      (libsource (lib "eagle-import") (part "RESR0603"))
    )
    (comp (ref "R146")
      (value "1M")
      (footprint "eagle-import:0603")
      (libsource (lib "eagle-import") (part "RESR0603"))
    )
    (comp (ref "R147")
      (value "4k7")
      (footprint "eagle-import:0603")
      (libsource (lib "eagle-import") (part "RESR0603"))
    )
    (comp (ref "R148")
      (value "4k7")
      (footprint "eagle-import:0603")
      (libsource (lib "eagle-import") (part "RESR0603"))
    )
    (comp (ref "R149")
      (value "4k7")
      (footprint "eagle-import:0603")
      (libsource (lib "eagle-import") (part "RESR0603"))
    )
    (comp (ref "R150")
      (value "1M")
      (footprint "eagle-import:0603")
      (libsource (lib "eagle-import") (part "RESR0603"))
    )
    (comp (ref "R151")
      (value "4k7")
      (footprint "eagle-import:0603")
      (libsource (lib "eagle-import") (part "RESR0603"))
    )
    (comp (ref "R152")
      (value "100R")
      (footprint "eagle-import:0402")
      (libsource (lib "eagle-import") (part "RESR0402"))
    )
    (comp (ref "R201")
      (value "NC")
      (footprint "eagle-import:0402")
      (libsource (lib "eagle-import") (part "RESR0402"))
    )
  )
  (nets
    (net (code "1") (name "+3.6V") (class "Default")
      (node (ref "C160") (pin "1") (pinfunction "1_1") (pintype "passive"))
      (node (ref "C161") (pin "+") (pinfunction "+_+") (pintype "passive"))
      (node (ref "D5") (pin "C") (pinfunction "C_C") (pintype "passive"))
      (node (ref "D6") (pin "C") (pinfunction "C_C") (pintype "passive"))
      (node (ref "R179") (pin "2") (pinfunction "P$2_2") (pintype "bidirectional"))
      (node (ref "R48") (pin "1") (pinfunction "P$1_1") (pintype "bidirectional"))
    )
    (net (code "2") (name "+3.6VBR") (class "Default")
      (node (ref "C162") (pin "2") (pinfunction "2_2") (pintype "passive"))
      (node (ref "C3") (pin "2") (pinfunction "2_2") (pintype "passive"))
      (node (ref "C80") (pin "2") (pinfunction "2_2") (pintype "passive"))
      (node (ref "C84") (pin "2") (pinfunction "2_2") (pintype "passive"))
      (node (ref "IC1") (pin "1") (pinfunction "VIN_1") (pintype "bidirectional"))
      (node (ref "IC1") (pin "3") (pinfunction "EN_3") (pintype "bidirectional"))
      (node (ref "IC10") (pin "1") (pinfunction "VIN_1") (pintype "bidirectional"))
      (node (ref "IC10") (pin "3") (pinfunction "EN_3") (pintype "bidirectional"))
      (node (ref "IC11") (pin "1") (pinfunction "IN_1") (pintype "power_in"))
      (node (ref "IC11") (pin "3") (pinfunction "EN_3") (pintype "input"))
      (node (ref "IC12") (pin "1") (pinfunction "IN_1") (pintype "power_in"))
      (node (ref "IC12") (pin "3") (pinfunction "EN_3") (pintype "input"))
      (node (ref "R48") (pin "2") (pinfunction "P$2_2") (pintype "bidirectional"))
    )
    (net (code "3") (name "+3V3") (class "Default")
      (node (ref "C116") (pin "1") (pinfunction "1_1") (pintype "passive"))
      (node (ref "C117") (pin "1") (pinfunction "1_1") (pintype "passive"))
      (node (ref "C147") (pin "2") (pinfunction "2_2") (pintype "passive"))
      (node (ref "C164") (pin "2") (pinfunction "2_2") (pintype "passive"))
      (node (ref "C165") (pin "2") (pinfunction "2_2") (pintype "passive"))
      (node (ref "C166") (pin "2") (pinfunction "2_2") (pintype "passive"))
      (node (ref "C22") (pin "1") (pinfunction "1_1") (pintype "passive"))
      (node (ref "C23") (pin "1") (pinfunction "1_1") (pintype "passive"))
      (node (ref "C24") (pin "1") (pinfunction "1_1") (pintype "passive"))
      (node (ref "C25") (pin "1") (pinfunction "1_1") (pintype "passive"))
      (node (ref "C26") (pin "1") (pinfunction "1_1") (pintype "passive"))
      (node (ref "C28") (pin "1") (pinfunction "1_1") (pintype "passive"))
      (node (ref "C33") (pin "1") (pinfunction "1_1") (pintype "passive"))
      (node (ref "C34") (pin "1") (pinfunction "1_1") (pintype "passive"))
      (node (ref "C35") (pin "1") (pinfunction "1_1") (pintype "passive"))
      (node (ref "C37") (pin "1") (pinfunction "1_1") (pintype "passive"))
      (node (ref "C38") (pin "1") (pinfunction "1_1") (pintype "passive"))
      (node (ref "C71") (pin "1") (pinfunction "1_1") (pintype "passive"))
      (node (ref "C72") (pin "1") (pinfunction "1_1") (pintype "passive"))
      (node (ref "C73") (pin "1") (pinfunction "1_1") (pintype "passive"))
      (node (ref "C76") (pin "1") (pinfunction "1_1") (pintype "passive"))
      (node (ref "C82") (pin "2") (pinfunction "2_2") (pintype "passive"))
      (node (ref "IC13") (pin "24") (pinfunction "TVDD_24") (pintype "power_in"))
      (node (ref "IC13") (pin "25") (pinfunction "DVDD_25") (pintype "power_in"))
      (node (ref "IC2") (pin "3") (pinfunction "~{WP}_3") (pintype "input"))
      (node (ref "IC2") (pin "7") (pinfunction "~{HOLD}_7") (pintype "input"))
      (node (ref "IC2") (pin "8") (pinfunction "VCC_8") (pintype "power_in"))
      (node (ref "IC20") (pin "14") (pinfunction "VDD_14") (pintype "power_in"))
      (node (ref "IC3") (pin "16") (pinfunction "VDD2_16") (pintype "power_in"))
      (node (ref "IC9") (pin "1") (pinfunction "VCCA_1") (pintype "power_in"))
      (node (ref "IC9") (pin "2") (pinfunction "DIR_2") (pintype "input"))
      (node (ref "QG1") (pin "4") (pinfunction "VCC_4") (pintype "power_in"))
      (node (ref "R10") (pin "1") (pinfunction "P$1_1") (pintype "bidirectional"))
      (node (ref "R11") (pin "1") (pinfunction "P$1_1") (pintype "bidirectional"))
      (node (ref "R12") (pin "1") (pinfunction "P$1_1") (pintype "bidirectional"))
      (node (ref "R165") (pin "2") (pinfunction "P$2_2") (pintype "bidirectional"))
      (node (ref "R6") (pin "1") (pinfunction "P$1_1") (pintype "bidirectional"))
      (node (ref "R8") (pin "1") (pinfunction "P$1_1") (pintype "bidirectional"))
      (node (ref "R89") (pin "1") (pinfunction "P$1_1") (pintype "bidirectional"))
      (node (ref "SV1") (pin "2") (pinfunction "2_2") (pintype "passive"))
      (node (ref "U2") (pin "A4") (pinfunction "IO_L1N_VREF_0_A4") (pintype "bidirectional"))
      (node (ref "U2") (pin "B13") (pinfunction "VCCO_0_B13") (pintype "input"))
      (node (ref "U2") (pin "B4") (pinfunction "VCCO_0_B4") (pintype "input"))
      (node (ref "U2") (pin "B5") (pinfunction "IO_L2P_0_B5") (pintype "bidirectional"))
      (node (ref "U2") (pin "B9") (pinfunction "VCCO_0_B9") (pintype "input"))
      (node (ref "U2") (pin "C5") (pinfunction "IO_L3N_0_C5") (pintype "bidirectional"))
      (node (ref "U2") (pin "C6") (pinfunction "IO_L7N_0_C6") (pintype "bidirectional"))
      (node (ref "U2") (pin "D10") (pinfunction "VCCO_0_D10") (pintype "input"))
      (node (ref "U2") (pin "D15") (pinfunction "VCCO_1_D15") (pintype "input"))
      (node (ref "U2") (pin "D6") (pinfunction "IO_L7P_0_D6") (pintype "bidirectional"))
      (node (ref "U2") (pin "D7") (pinfunction "VCCO_0_D7") (pintype "input"))
      (node (ref "U2") (pin "E5") (pinfunction "VCCAUX_E5") (pintype "input"))
      (node (ref "U2") (pin "F11") (pinfunction "VCCAUX_F11") (pintype "input"))
      (node (ref "U2") (pin "F8") (pinfunction "VCCAUX_F8") (pintype "input"))
      (node (ref "U2") (pin "F9") (pinfunction "IO_L40P_0_F9") (pintype "bidirectional"))
      (node (ref "U2") (pin "G10") (pinfunction "VCCAUX_G10") (pintype "input"))
      (node (ref "U2") (pin "G13") (pinfunction "VCCO_1_G13") (pintype "input"))
      (node (ref "U2") (pin "H6") (pinfunction "VCCAUX_H6") (pintype "input"))
      (node (ref "U2") (pin "J10") (pinfunction "VCCAUX_J10") (pintype "input"))
      (node (ref "U2") (pin "J15") (pinfunction "VCCO_1_J15") (pintype "input"))
      (node (ref "U2") (pin "K13") (pinfunction "VCCO_1_K13") (pintype "input"))
      (node (ref "U2") (pin "L6") (pinfunction "VCCAUX_L6") (pintype "input"))
      (node (ref "U2") (pin "L9") (pinfunction "VCCAUX_L9") (pintype "input"))
      (node (ref "U2") (pin "N10") (pinfunction "VCCO_2_N10") (pintype "input"))
      (node (ref "U2") (pin "N15") (pinfunction "VCCO_1_N15") (pintype "input"))
      (node (ref "U2") (pin "N7") (pinfunction "VCCO_2_N7") (pintype "input"))
      (node (ref "U2") (pin "R13") (pinfunction "VCCO_1_R13") (pintype "input"))
      (node (ref "U2") (pin "R4") (pinfunction "VCCO_2_R4") (pintype "input"))
      (node (ref "U2") (pin "R8") (pinfunction "VCCO_2_R8") (pintype "input"))
    )
    (net (code "4") (name "+5.5V") (class "Default")
      (node (ref "C156") (pin "1") (pinfunction "1_1") (pintype "passive"))
      (node (ref "C157") (pin "+") (pinfunction "+_+") (pintype "passive"))
      (node (ref "D1") (pin "C") (pinfunction "C_C") (pintype "passive"))
      (node (ref "D2") (pin "C") (pinfunction "C_C") (pintype "passive"))
      (node (ref "R178") (pin "1") (pinfunction "P$1_1") (pintype "bidirectional"))
    )
    (net (code "5") (name "+5V") (class "Default")
      (node (ref "C104") (pin "2") (pinfunction "2_2") (pintype "passive"))
      (node (ref "C112") (pin "2") (pinfunction "2_2") (pintype "passive"))
      (node (ref "C115") (pin "2") (pinfunction "2_2") (pintype "passive"))
      (node (ref "C119") (pin "2") (pinfunction "2_2") (pintype "passive"))
      (node (ref "C125") (pin "1") (pinfunction "1_1") (pintype "passive"))
      (node (ref "C126") (pin "1") (pinfunction "1_1") (pintype "passive"))
      (node (ref "C138") (pin "1") (pinfunction "1_1") (pintype "passive"))
      (node (ref "C139") (pin "1") (pinfunction "1_1") (pintype "passive"))
      (node (ref "C141") (pin "1") (pinfunction "1_1") (pintype "passive"))
      (node (ref "C145") (pin "1") (pinfunction "1_1") (pintype "passive"))
      (node (ref "C148") (pin "1") (pinfunction "1_1") (pintype "passive"))
      (node (ref "C170") (pin "2") (pinfunction "2_2") (pintype "passive"))
      (node (ref "C204") (pin "2") (pinfunction "2_2") (pintype "passive"))
      (node (ref "C205") (pin "2") (pinfunction "2_2") (pintype "passive"))
      (node (ref "C206") (pin "2") (pinfunction "2_2") (pintype "passive"))
      (node (ref "C208") (pin "2") (pinfunction "2_2") (pintype "passive"))
      (node (ref "C210") (pin "2") (pinfunction "2_2") (pintype "passive"))
      (node (ref "C221") (pin "2") (pinfunction "2_2") (pintype "passive"))
      (node (ref "C230") (pin "2") (pinfunction "2_2") (pintype "passive"))
      (node (ref "C231") (pin "2") (pinfunction "2_2") (pintype "passive"))
      (node (ref "C233") (pin "2") (pinfunction "2_2") (pintype "passive"))
      (node (ref "C235") (pin "2") (pinfunction "2_2") (pintype "passive"))
      (node (ref "C246") (pin "2") (pinfunction "2_2") (pintype "passive"))
      (node (ref "C255") (pin "1") (pinfunction "1_1") (pintype "passive"))
      (node (ref "C256") (pin "1") (pinfunction "1_1") (pintype "passive"))
      (node (ref "C96") (pin "1") (pinfunction "1_1") (pintype "passive"))
      (node (ref "IC13") (pin "6") (pinfunction "VREF_6") (pintype "passive"))
      (node (ref "IC13") (pin "8") (pinfunction "AVDD_8") (pintype "power_in"))
      (node (ref "IC15") (pin "8") (pinfunction "V+_8") (pintype "power_in"))
      (node (ref "IC16") (pin "8") (pinfunction "V+_8") (pintype "power_in"))
      (node (ref "IC17") (pin "8") (pinfunction "V+_8") (pintype "power_in"))
      (node (ref "IC18") (pin "8") (pinfunction "V+_8") (pintype "power_in"))
      (node (ref "IC19") (pin "8") (pinfunction "V+_8") (pintype "power_in"))
      (node (ref "IC20") (pin "15") (pinfunction "5V_SUPPLY_15") (pintype "power_in"))
      (node (ref "IC21") (pin "8") (pinfunction "V+_8") (pintype "power_in"))
      (node (ref "IC22") (pin "16") (pinfunction "VCC_16") (pintype "power_in"))
      (node (ref "IC23") (pin "8") (pinfunction "V+_8") (pintype "power_in"))
      (node (ref "IC25") (pin "7") (pinfunction "V+_7") (pintype "power_in"))
      (node (ref "IC25") (pin "8") (pinfunction "SD_8") (pintype "input"))
      (node (ref "IC32") (pin "8") (pinfunction "VDD_8") (pintype "power_in"))
      (node (ref "IC33") (pin "4") (pinfunction "V+_4") (pintype "power_in"))
      (node (ref "IC34") (pin "16") (pinfunction "VCC_16") (pintype "power_in"))
      (node (ref "IC35") (pin "16") (pinfunction "VCC_16") (pintype "power_in"))
      (node (ref "IC37") (pin "10") (pinfunction "SCL_10") (pintype "input"))
      (node (ref "IC37") (pin "16") (pinfunction "VCC_16") (pintype "power_in"))
      (node (ref "IC38") (pin "4") (pinfunction "V+_4") (pintype "power_in"))
      (node (ref "IC39") (pin "16") (pinfunction "VCC_16") (pintype "power_in"))
      (node (ref "IC40") (pin "16") (pinfunction "VCC_16") (pintype "power_in"))
      (node (ref "IC42") (pin "10") (pinfunction "SCL_10") (pintype "input"))
      (node (ref "IC42") (pin "16") (pinfunction "VCC_16") (pintype "power_in"))
      (node (ref "IC43") (pin "5") (pinfunction "V+_5") (pintype "power_in"))
      (node (ref "IC44") (pin "10") (pinfunction "SCL_10") (pintype "input"))
      (node (ref "IC44") (pin "16") (pinfunction "VCC_16") (pintype "power_in"))
      (node (ref "R143") (pin "2") (pinfunction "P$2_2") (pintype "bidirectional"))
      (node (ref "R177") (pin "2") (pinfunction "P$2_2") (pintype "bidirectional"))
      (node (ref "R232") (pin "2") (pinfunction "P$2_2") (pintype "bidirectional"))
      (node (ref "R268") (pin "2") (pinfunction "P$2_2") (pintype "bidirectional"))
    )
    (net (code "6") (name "+UB") (class "Default")
      (node (ref "C153") (pin "2") (pinfunction "2_2") (pintype "passive"))
      (node (ref "C154") (pin "2") (pinfunction "2_2") (pintype "passive"))
      (node (ref "C159") (pin "+") (pinfunction "+_+") (pintype "passive"))
      (node (ref "IC24") (pin "14") (pinfunction "VCC_14") (pintype "power_in"))
      (node (ref "IC27") (pin "14") (pinfunction "VCC_14") (pintype "power_in"))
      (node (ref "R51") (pin "2") (pinfunction "P$2_2") (pintype "bidirectional"))
      (node (ref "T1") (pin "2") (pinfunction "P1M_2") (pintype "passive"))
    )
    (net (code "7") (name "-2V5A") (class "Default")
      (node (ref "C176") (pin "1") (pinfunction "1_1") (pintype "passive"))
      (node (ref "C198") (pin "2") (pinfunction "2_2") (pintype "passive"))
      (node (ref "C207") (pin "1") (pinfunction "1_1") (pintype "passive"))
      (node (ref "C209") (pin "1") (pinfunction "1_1") (pintype "passive"))
      (node (ref "C219") (pin "1") (pinfunction "1_1") (pintype "passive"))
      (node (ref "C232") (pin "1") (pinfunction "1_1") (pintype "passive"))
      (node (ref "C234") (pin "1") (pinfunction "1_1") (pintype "passive"))
      (node (ref "C244") (pin "1") (pinfunction "1_1") (pintype "passive"))
      (node (ref "IC31") (pin "4") (pinfunction "V-_4") (pintype "power_in"))
      (node (ref "IC34") (pin "7") (pinfunction "VEE_7") (pintype "power_in"))
      (node (ref "IC35") (pin "7") (pinfunction "VEE_7") (pintype "power_in"))
      (node (ref "IC36") (pin "4") (pinfunction "V-_4") (pintype "power_in"))
      (node (ref "IC39") (pin "7") (pinfunction "VEE_7") (pintype "power_in"))
      (node (ref "IC40") (pin "7") (pinfunction "VEE_7") (pintype "power_in"))
      (node (ref "IC41") (pin "4") (pinfunction "V-_4") (pintype "power_in"))
      (node (ref "R174") (pin "2") (pinfunction "P$2_2") (pintype "bidirectional"))
    )
    (net (code "8") (name "-5.5V") (class "Default")
      (node (ref "C155") (pin "2") (pinfunction "2_2") (pintype "passive"))
      (node (ref "C158") (pin "-") (pinfunction "-_-") (pintype "passive"))
      (node (ref "D3") (pin "A") (pinfunction "A_A") (pintype "passive"))
      (node (ref "D4") (pin "A") (pinfunction "A_A") (pintype "passive"))
      (node (ref "R172") (pin "1") (pinfunction "P$1_1") (pintype "bidirectional"))
    )
    (net (code "9") (name "-5V") (class "Default")
      (node (ref "C105") (pin "2") (pinfunction "2_2") (pintype "passive"))
      (node (ref "C137") (pin "1") (pinfunction "1_1") (pintype "passive"))
      (node (ref "C140") (pin "1") (pinfunction "1_1") (pintype "passive"))
      (node (ref "C150") (pin "2") (pinfunction "2_2") (pintype "passive"))
      (node (ref "C175") (pin "1") (pinfunction "1_1") (pintype "passive"))
      (node (ref "C97") (pin "1") (pinfunction "1_1") (pintype "passive"))
      (node (ref "IC16") (pin "4") (pinfunction "V-_4") (pintype "power_in"))
      (node (ref "IC17") (pin "4") (pinfunction "V-_4") (pintype "power_in"))
      (node (ref "IC18") (pin "4") (pinfunction "V-_4") (pintype "power_in"))
      (node (ref "IC21") (pin "4") (pinfunction "V-_4") (pintype "power_in"))
      (node (ref "IC22") (pin "7") (pinfunction "VEE_7") (pintype "power_in"))
      (node (ref "R173") (pin "2") (pinfunction "P$2_2") (pintype "bidirectional"))
    )
    (net (code "10") (name "1V2REF") (class "Default")
      (node (ref "C194") (pin "1") (pinfunction "1_1") (pintype "passive"))
      (node (ref "IC18") (pin "3") (pinfunction "+IN_3") (pintype "input"))
      (node (ref "IC18") (pin "5") (pinfunction "+IN_5") (pintype "input"))
      (node (ref "IC31") (pin "5") (pinfunction "+IN_5") (pintype "input"))
      (node (ref "L10") (pin "1") (pinfunction "1_1") (pintype "passive"))
      (node (ref "L9") (pin "1") (pinfunction "1_1") (pintype "passive"))
      (node (ref "R193") (pin "2") (pinfunction "P$2_2") (pintype "bidirectional"))
    )
    (net (code "11") (name "2V8REF") (class "Default")
      (node (ref "C177") (pin "2") (pinfunction "2_2") (pintype "passive"))
      (node (ref "C193") (pin "2") (pinfunction "2_2") (pintype "passive"))
      (node (ref "IC30") (pin "8") (pinfunction "V+_8") (pintype "power_in"))
      (node (ref "L11") (pin "1") (pinfunction "1_1") (pintype "passive"))
      (node (ref "L8") (pin "1") (pinfunction "1_1") (pintype "passive"))
      (node (ref "R180") (pin "1") (pinfunction "P$1_1") (pintype "bidirectional"))
      (node (ref "R190") (pin "1") (pinfunction "P$1_1") (pintype "bidirectional"))
      (node (ref "R195") (pin "1") (pinfunction "P$1_1") (pintype "bidirectional"))
    )
    (net (code "12") (name "3V3A") (class "Default")
      (node (ref "C197") (pin "2") (pinfunction "2_2") (pintype "passive"))
      (node (ref "C218") (pin "2") (pinfunction "2_2") (pintype "passive"))
      (node (ref "C243") (pin "2") (pinfunction "2_2") (pintype "passive"))
      (node (ref "C63") (pin "1") (pinfunction "1_1") (pintype "passive"))
      (node (ref "C64") (pin "1") (pinfunction "1_1") (pintype "passive"))
      (node (ref "C65") (pin "1") (pinfunction "1_1") (pintype "passive"))
      (node (ref "C66") (pin "1") (pinfunction "1_1") (pintype "passive"))
      (node (ref "C67") (pin "1") (pinfunction "1_1") (pintype "passive"))
      (node (ref "C68") (pin "1") (pinfunction "1_1") (pintype "passive"))
      (node (ref "C69") (pin "1") (pinfunction "1_1") (pintype "passive"))
      (node (ref "C70") (pin "1") (pinfunction "1_1") (pintype "passive"))
      (node (ref "C88") (pin "2") (pinfunction "2_2") (pintype "passive"))
      (node (ref "IC31") (pin "8") (pinfunction "V+_8") (pintype "power_in"))
      (node (ref "IC36") (pin "8") (pinfunction "V+_8") (pintype "power_in"))
      (node (ref "IC41") (pin "8") (pinfunction "V+_8") (pintype "power_in"))
      (node (ref "IC5") (pin "1") (pinfunction "VA_1") (pintype "power_in"))
      (node (ref "IC5") (pin "12") (pinfunction "VA_12") (pintype "power_in"))
      (node (ref "IC5") (pin "4") (pinfunction "VA_4") (pintype "power_in"))
      (node (ref "IC6") (pin "1") (pinfunction "VA_1") (pintype "power_in"))
      (node (ref "IC6") (pin "12") (pinfunction "VA_12") (pintype "power_in"))
      (node (ref "IC6") (pin "4") (pinfunction "VA_4") (pintype "power_in"))
      (node (ref "L4") (pin "1") (pinfunction "1_1") (pintype "passive"))
      (node (ref "L5") (pin "1") (pinfunction "1_1") (pintype "passive"))
      (node (ref "R168") (pin "2") (pinfunction "P$2_2") (pintype "bidirectional"))
    )
    (net (code "13") (name "A0") (class "Default")
      (node (ref "IC26") (pin "K3") (pinfunction "A0_K3") (pintype "input"))
      (node (ref "U2") (pin "K5") (pinfunction "IO_L47P_M3A0_3_K5") (pintype "bidirectional"))
    )
    (net (code "14") (name "A1") (class "Default")
      (node (ref "IC26") (pin "L7") (pinfunction "A1_L7") (pintype "input"))
      (node (ref "U2") (pin "K6") (pinfunction "IO_L47N_M3A1_3_K6") (pintype "bidirectional"))
    )
    (net (code "15") (name "A2") (class "Default")
      (node (ref "IC26") (pin "L3") (pinfunction "A2_L3") (pintype "input"))
      (node (ref "U2") (pin "D1") (pinfunction "IO_L49N_M3A2_3_D1") (pintype "bidirectional"))
    )
    (net (code "16") (name "A3") (class "Default")
      (node (ref "IC26") (pin "K2") (pinfunction "A3_K2") (pintype "input"))
      (node (ref "U2") (pin "L4") (pinfunction "IO_L45P_M3A3_3_L4") (pintype "bidirectional"))
    )
    (net (code "17") (name "A4") (class "Default")
      (node (ref "IC26") (pin "L8") (pinfunction "A4_L8") (pintype "input"))
      (node (ref "U2") (pin "G5") (pinfunction "IO_L51N_M3A4_3_G5") (pintype "bidirectional"))
    )
    (net (code "18") (name "A5") (class "Default")
      (node (ref "IC26") (pin "L2") (pinfunction "A5_L2") (pintype "input"))
      (node (ref "U2") (pin "H4") (pinfunction "IO_L44P_GCLK21_M3A5_3_H4") (pintype "bidirectional"))
    )
    (net (code "19") (name "A6") (class "Default")
      (node (ref "IC26") (pin "M8") (pinfunction "A6_M8") (pintype "input"))
      (node (ref "U2") (pin "H3") (pinfunction "IO_L44N_GCLK20_M3A6_3_H3") (pintype "bidirectional"))
    )
    (net (code "20") (name "A7") (class "Default")
      (node (ref "IC26") (pin "M2") (pinfunction "A7_M2") (pintype "input"))
      (node (ref "U2") (pin "D3") (pinfunction "IO_L49P_M3A7_3_D3") (pintype "bidirectional"))
    )
    (net (code "21") (name "A8") (class "Default")
      (node (ref "IC26") (pin "N8") (pinfunction "A8_N8") (pintype "input"))
      (node (ref "U2") (pin "B2") (pinfunction "IO_L52P_M3A8_3_B2") (pintype "bidirectional"))
    )
    (net (code "22") (name "A9") (class "Default")
      (node (ref "IC26") (pin "M3") (pinfunction "A9_M3") (pintype "input"))
      (node (ref "U2") (pin "A2") (pinfunction "IO_L52N_M3A9_3_A2") (pintype "bidirectional"))
    )
    (net (code "23") (name "A10") (class "Default")
      (node (ref "IC26") (pin "H7") (pinfunction "A10_H7") (pintype "input"))
      (node (ref "U2") (pin "G6") (pinfunction "IO_L51P_M3A10_3_G6") (pintype "bidirectional"))
    )
    (net (code "24") (name "A11") (class "Default")
      (node (ref "IC26") (pin "M7") (pinfunction "A11_M7") (pintype "input"))
      (node (ref "U2") (pin "E3") (pinfunction "IO_L54N_M3A11_3_E3") (pintype "bidirectional"))
    )
    (net (code "25") (name "A12") (class "Default")
      (node (ref "IC26") (pin "K7") (pinfunction "A12_K7") (pintype "input"))
      (node (ref "U2") (pin "F3") (pinfunction "IO_L53N_M3A12_3_F3") (pintype "bidirectional"))
    )
    (net (code "26") (name "A13") (class "Default")
      (node (ref "IC26") (pin "N3") (pinfunction "A13_N3") (pintype "input"))
      (node (ref "U2") (pin "F6") (pinfunction "IO_L55P_M3A13_3_F6") (pintype "bidirectional"))
    )
    (net (code "27") (name "ADA0") (class "Default")
      (node (ref "R29") (pin "2") (pinfunction "P$2_2") (pintype "bidirectional"))
      (node (ref "U2") (pin "E16") (pinfunction "IO_L34N_A12_M1BA2_1_E16") (pintype "bidirectional"))
    )
    (net (code "28") (name "ADA1") (class "Default")
      (node (ref "R28") (pin "2") (pinfunction "P$2_2") (pintype "bidirectional"))
      (node (ref "U2") (pin "E15") (pinfunction "IO_L34P_A13_M1WE_1_E15") (pintype "bidirectional"))
    )
    (net (code "29") (name "ADA2") (class "Default")
      (node (ref "R27") (pin "2") (pinfunction "P$2_2") (pintype "bidirectional"))
      (node (ref "U2") (pin "D16") (pinfunction "IO_L31N_A18_M1A12_1_D16") (pintype "bidirectional"))
    )
    (net (code "30") (name "ADA3") (class "Default")
      (node (ref "R26") (pin "2") (pinfunction "P$2_2") (pintype "bidirectional"))
      (node (ref "U2") (pin "D14") (pinfunction "IO_L31P_A19_M1CKE_1_D14") (pintype "bidirectional"))
    )
    (net (code "31") (name "ADA4") (class "Default")
      (node (ref "R25") (pin "2") (pinfunction "P$2_2") (pintype "bidirectional"))
      (node (ref "U2") (pin "C16") (pinfunction "IO_L33N_A14_M1A4_1_C16") (pintype "bidirectional"))
    )
    (net (code "32") (name "ADA5") (class "Default")
      (node (ref "R24") (pin "2") (pinfunction "P$2_2") (pintype "bidirectional"))
      (node (ref "U2") (pin "C15") (pinfunction "IO_L33P_A15_M1A10_1_C15") (pintype "bidirectional"))
    )
    (net (code "33") (name "ADA6") (class "Default")
      (node (ref "R23") (pin "2") (pinfunction "P$2_2") (pintype "bidirectional"))
      (node (ref "U2") (pin "B16") (pinfunction "IO_L29N_A22_M1A14_1_B16") (pintype "bidirectional"))
    )
    (net (code "34") (name "ADA7") (class "Default")
      (node (ref "R22") (pin "2") (pinfunction "P$2_2") (pintype "bidirectional"))
      (node (ref "U2") (pin "B15") (pinfunction "IO_L29P_A23_M1A13_1_B15") (pintype "bidirectional"))
    )
    (net (code "35") (name "ADAC") (class "Default")
      (node (ref "IC5") (pin "24") (pinfunction "CLK_24") (pintype "input"))
      (node (ref "U2") (pin "F15") (pinfunction "IO_L35P_A11_M1A7_1_F15") (pintype "bidirectional"))
    )
    (net (code "36") (name "ADAP") (class "Default")
      (node (ref "IC5") (pin "23") (pinfunction "PD_23") (pintype "input"))
      (node (ref "IC6") (pin "23") (pinfunction "PD_23") (pintype "input"))
      (node (ref "U2") (pin "F16") (pinfunction "IO_L35N_A10_M1A2_1_F16") (pintype "bidirectional"))
    )
    (net (code "37") (name "ADB0") (class "Default")
      (node (ref "R37") (pin "2") (pinfunction "P$2_2") (pintype "bidirectional"))
      (node (ref "U2") (pin "K14") (pinfunction "IO_L41N_GCLK8_M1CASN_1_K14") (pintype "bidirectional"))
    )
    (net (code "38") (name "ADB1") (class "Default")
      (node (ref "R36") (pin "2") (pinfunction "P$2_2") (pintype "bidirectional"))
      (node (ref "U2") (pin "K16") (pinfunction "IO_L44N_A2_M1DQ7_1_K16") (pintype "bidirectional"))
    )
    (net (code "39") (name "ADB2") (class "Default")
      (node (ref "R35") (pin "2") (pinfunction "P$2_2") (pintype "bidirectional"))
      (node (ref "U2") (pin "K15") (pinfunction "IO_L44P_A3_M1DQ6_1_K15") (pintype "bidirectional"))
    )
    (net (code "40") (name "ADB3") (class "Default")
      (node (ref "R34") (pin "2") (pinfunction "P$2_2") (pintype "bidirectional"))
      (node (ref "U2") (pin "J16") (pinfunction "IO_L43N_GCLK4_M1DQ5_1_J16") (pintype "bidirectional"))
    )
    (net (code "41") (name "ADB4") (class "Default")
      (node (ref "R33") (pin "2") (pinfunction "P$2_2") (pintype "bidirectional"))
      (node (ref "U2") (pin "H16") (pinfunction "IO_L37N_A6_M1A1_1_H16") (pintype "bidirectional"))
    )
    (net (code "42") (name "ADB5") (class "Default")
      (node (ref "R32") (pin "2") (pinfunction "P$2_2") (pintype "bidirectional"))
      (node (ref "U2") (pin "H15") (pinfunction "IO_L37P_A7_M1A0_1_H15") (pintype "bidirectional"))
    )
    (net (code "43") (name "ADB6") (class "Default")
      (node (ref "R31") (pin "2") (pinfunction "P$2_2") (pintype "bidirectional"))
      (node (ref "U2") (pin "G16") (pinfunction "IO_L36N_A8_M1BA1_1_G16") (pintype "bidirectional"))
    )
    (net (code "44") (name "ADB7") (class "Default")
      (node (ref "R30") (pin "2") (pinfunction "P$2_2") (pintype "bidirectional"))
      (node (ref "U2") (pin "F14") (pinfunction "IO_L32N_A16_M1A9_1_F14") (pintype "bidirectional"))
    )
    (net (code "45") (name "ADBC") (class "Default")
      (node (ref "IC6") (pin "24") (pinfunction "CLK_24") (pintype "input"))
      (node (ref "U2") (pin "L16") (pinfunction "IO_L47N_LDC_M1DQ1_1_L16") (pintype "bidirectional"))
    )
    (net (code "46") (name "AINL") (class "Default")
      (node (ref "R104") (pin "2") (pinfunction "P$2_2") (pintype "bidirectional"))
      (node (ref "SV4") (pin "8") (pinfunction "8_8") (pintype "passive"))
    )
    (net (code "47") (name "AINR") (class "Default")
      (node (ref "R151") (pin "2") (pinfunction "P$2_2") (pintype "bidirectional"))
      (node (ref "SV4") (pin "7") (pinfunction "7_7") (pintype "passive"))
    )
    (net (code "48") (name "AOUTL") (class "Default")
      (node (ref "R86") (pin "2") (pinfunction "P$2_2") (pintype "bidirectional"))
      (node (ref "SV4") (pin "6") (pinfunction "6_6") (pintype "passive"))
    )
    (net (code "49") (name "AOUTR") (class "Default")
      (node (ref "R87") (pin "2") (pinfunction "P$2_2") (pintype "bidirectional"))
      (node (ref "SV4") (pin "5") (pinfunction "5_5") (pintype "passive"))
    )
    (net (code "50") (name "ASEL0") (class "Default")
      (node (ref "R11") (pin "2") (pinfunction "P$2_2") (pintype "bidirectional"))
      (node (ref "U2") (pin "R3") (pinfunction "IO_L65P_INIT_B_2_R3") (pintype "bidirectional"))
    )
    (net (code "51") (name "ATTRL+") (class "Default")
      (node (ref "IC37") (pin "1") (pinfunction "QB_1") (pintype "tri_state"))
      (node (ref "R234") (pin "2") (pinfunction "P$2_2") (pintype "bidirectional"))
    )
    (net (code "52") (name "ATTRL+B") (class "Default")
      (node (ref "IC42") (pin "1") (pinfunction "QB_1") (pintype "tri_state"))
      (node (ref "R270") (pin "2") (pinfunction "P$2_2") (pintype "bidirectional"))
    )
    (net (code "53") (name "ATTRL-") (class "Default")
      (node (ref "IC37") (pin "15") (pinfunction "QA_15") (pintype "tri_state"))
      (node (ref "R236") (pin "1") (pinfunction "P$1_1") (pintype "bidirectional"))
    )
    (net (code "54") (name "ATTRL-B") (class "Default")
      (node (ref "IC42") (pin "15") (pinfunction "QA_15") (pintype "tri_state"))
      (node (ref "R272") (pin "1") (pinfunction "P$1_1") (pintype "bidirectional"))
    )
    (net (code "55") (name "AUADCINL") (class "Default")
      (node (ref "C132") (pin "1") (pinfunction "1_1") (pintype "passive"))
      (node (ref "IC17") (pin "6") (pinfunction "-IN_6") (pintype "input"))
      (node (ref "IC17") (pin "7") (pinfunction "OUT_7") (pintype "output"))
      (node (ref "R149") (pin "2") (pinfunction "P$2_2") (pintype "bidirectional"))
    )
    (net (code "56") (name "AUADCINR") (class "Default")
      (node (ref "C130") (pin "1") (pinfunction "1_1") (pintype "passive"))
      (node (ref "IC17") (pin "1") (pinfunction "OUT_1") (pintype "output"))
      (node (ref "IC17") (pin "2") (pinfunction "-IN_2") (pintype "input"))
      (node (ref "R147") (pin "2") (pinfunction "P$2_2") (pintype "bidirectional"))
    )
    (net (code "57") (name "AUBIAS") (class "Default")
      (node (ref "C133") (pin "2") (pinfunction "2_2") (pintype "passive"))
      (node (ref "C134") (pin "2") (pinfunction "2_2") (pintype "passive"))
      (node (ref "IC15") (pin "3") (pinfunction "+IN_3") (pintype "input"))
      (node (ref "IC15") (pin "5") (pinfunction "+IN_5") (pintype "input"))
      (node (ref "IC23") (pin "3") (pinfunction "+IN_3") (pintype "input"))
      (node (ref "IC23") (pin "5") (pinfunction "+IN_5") (pintype "input"))
      (node (ref "R143") (pin "1") (pinfunction "P$1_1") (pintype "bidirectional"))
      (node (ref "R144") (pin "2") (pinfunction "P$2_2") (pintype "bidirectional"))
    )
    (net (code "58") (name "AUPDN") (class "Default")
      (node (ref "IC13") (pin "21") (pinfunction "PDN_21") (pintype "input"))
      (node (ref "U2") (pin "R15") (pinfunction "IO_L49P_M1DQ10_1_R15") (pintype "bidirectional"))
    )
    (net (code "59") (name "AUXIN") (class "Default")
      (node (ref "IC34") (pin "11") (pinfunction "X3_11") (pintype "bidirectional"))
      (node (ref "R275") (pin "2") (pinfunction "P$2_2") (pintype "bidirectional"))
    )
    (net (code "60") (name "AUXINCH0") (class "Default")
      (node (ref "IC25") (pin "6") (pinfunction "VOUT_6") (pintype "output"))
      (node (ref "IC39") (pin "11") (pinfunction "X3_11") (pintype "bidirectional"))
      (node (ref "R202") (pin "2") (pinfunction "P$2_2") (pintype "bidirectional"))
    )
    (net (code "61") (name "AUXOUT") (class "Default")
      (node (ref "R239") (pin "2") (pinfunction "P$2_2") (pintype "bidirectional"))
    )
    (net (code "62") (name "AU_CCLK") (class "Default")
      (node (ref "IC13") (pin "18") (pinfunction "CCLK/CKS1_18") (pintype "input"))
      (node (ref "IC32") (pin "1") (pinfunction "SCLK_1") (pintype "input"))
      (node (ref "U2") (pin "T14") (pinfunction "IO_L51P_M1DQ12_1_T14") (pintype "bidirectional"))
    )
    (net (code "63") (name "AU_CDTI") (class "Default")
      (node (ref "IC13") (pin "17") (pinfunction "CDTI/CKS0_17") (pintype "input"))
      (node (ref "IC32") (pin "10") (pinfunction "DIN_10") (pintype "input"))
      (node (ref "U2") (pin "T15") (pinfunction "IO_L50N_M1UDQSN_1_T15") (pintype "bidirectional"))
    )
    (net (code "64") (name "AU_CSN") (class "Default")
      (node (ref "IC13") (pin "19") (pinfunction "CSN/DIF_19") (pintype "input"))
      (node (ref "U2") (pin "T13") (pinfunction "IO_L51N_M1DQ13_1_T13") (pintype "bidirectional"))
    )
    (net (code "65") (name "AU_OVFL") (class "Default")
      (node (ref "IC13") (pin "16") (pinfunction "OVFL/DZFL_16") (pintype "output"))
      (node (ref "U2") (pin "R14") (pinfunction "IO_L50P_M1UDQS_1_R14") (pintype "bidirectional"))
    )
    (net (code "66") (name "AU_OVFR") (class "Default")
      (node (ref "IC13") (pin "15") (pinfunction "OVFR/DZFR_15") (pintype "output"))
      (node (ref "U2") (pin "M15") (pinfunction "IO_L46P_FCS_B_M1DQ2_1_M15") (pintype "bidirectional"))
    )
    (net (code "67") (name "AVREFM") (class "Default")
      (node (ref "C192") (pin "1") (pinfunction "1_1") (pintype "passive"))
      (node (ref "C225") (pin "1") (pinfunction "1_1") (pintype "passive"))
      (node (ref "C226") (pin "1") (pinfunction "1_1") (pintype "passive"))
      (node (ref "C227") (pin "1") (pinfunction "1_1") (pintype "passive"))
      (node (ref "C250") (pin "1") (pinfunction "1_1") (pintype "passive"))
      (node (ref "C251") (pin "1") (pinfunction "1_1") (pintype "passive"))
      (node (ref "C252") (pin "1") (pinfunction "1_1") (pintype "passive"))
      (node (ref "IC25") (pin "5") (pinfunction "REF_5") (pintype "input"))
      (node (ref "R192") (pin "2") (pinfunction "P$2_2") (pintype "bidirectional"))
      (node (ref "R203") (pin "1") (pinfunction "P$1_1") (pintype "bidirectional"))
      (node (ref "R206") (pin "2") (pinfunction "P$2_2") (pintype "bidirectional"))
      (node (ref "R207") (pin "1") (pinfunction "P$1_1") (pintype "bidirectional"))
      (node (ref "R210") (pin "1") (pinfunction "P$1_1") (pintype "bidirectional"))
      (node (ref "R213") (pin "1") (pinfunction "P$1_1") (pintype "bidirectional"))
      (node (ref "R216") (pin "1") (pinfunction "P$1_1") (pintype "bidirectional"))
      (node (ref "R218") (pin "1") (pinfunction "P$1_1") (pintype "bidirectional"))
      (node (ref "R219") (pin "1") (pinfunction "P$1_1") (pintype "bidirectional"))
      (node (ref "R220") (pin "1") (pinfunction "P$1_1") (pintype "bidirectional"))
      (node (ref "R246") (pin "1") (pinfunction "P$1_1") (pintype "bidirectional"))
      (node (ref "R249") (pin "1") (pinfunction "P$1_1") (pintype "bidirectional"))
      (node (ref "R252") (pin "1") (pinfunction "P$1_1") (pintype "bidirectional"))
      (node (ref "R254") (pin "1") (pinfunction "P$1_1") (pintype "bidirectional"))
      (node (ref "R255") (pin "1") (pinfunction "P$1_1") (pintype "bidirectional"))
      (node (ref "R256") (pin "1") (pinfunction "P$1_1") (pintype "bidirectional"))
    )
    (net (code "68") (name "BA0") (class "Default")
      (node (ref "IC26") (pin "J2") (pinfunction "BA0_J2") (pintype "input"))
      (node (ref "U2") (pin "C3") (pinfunction "IO_L48P_M3BA0_3_C3") (pintype "bidirectional"))
    )
    (net (code "69") (name "BA1") (class "Default")
      (node (ref "IC26") (pin "K8") (pinfunction "BA1_K8") (pintype "input"))
      (node (ref "U2") (pin "C2") (pinfunction "IO_L48N_M3BA1_3_C2") (pintype "bidirectional"))
    )
    (net (code "70") (name "BA2") (class "Default")
      (node (ref "IC26") (pin "J3") (pinfunction "BA2_J3") (pintype "input"))
      (node (ref "U2") (pin "B1") (pinfunction "IO_L50N_M3BA2_3_B1") (pintype "bidirectional"))
    )
    (net (code "71") (name "CASN") (class "Default")
      (node (ref "IC26") (pin "G3") (pinfunction "CAS#_G3") (pintype "input"))
      (node (ref "U2") (pin "H5") (pinfunction "IO_L43N_GCLK22_IRDY2_M3CASN_3_H5") (pintype "bidirectional"))
    )
    (net (code "72") (name "CCLK") (class "Default")
      (node (ref "IC2") (pin "6") (pinfunction "SCK_6") (pintype "input"))
      (node (ref "R8") (pin "2") (pinfunction "P$2_2") (pintype "bidirectional"))
      (node (ref "R9") (pin "1") (pinfunction "P$1_1") (pintype "bidirectional"))
      (node (ref "U2") (pin "R11") (pinfunction "IO_L1P_CCLK_2_R11") (pintype "bidirectional"))
    )
    (net (code "73") (name "CK") (class "Default")
      (node (ref "IC26") (pin "F7") (pinfunction "CK_F7") (pintype "input"))
      (node (ref "U2") (pin "E2") (pinfunction "IO_L46P_M3CLK_3_E2") (pintype "bidirectional"))
    )
    (net (code "74") (name "CKE") (class "Default")
      (node (ref "IC26") (pin "G9") (pinfunction "CKE_G9") (pintype "input"))
      (node (ref "R7") (pin "2") (pinfunction "P$2_2") (pintype "bidirectional"))
      (node (ref "U2") (pin "F4") (pinfunction "IO_L53P_M3CKE_3_F4") (pintype "bidirectional"))
    )
    (net (code "75") (name "CKN") (class "Default")
      (node (ref "IC26") (pin "G7") (pinfunction "CK#_G7") (pintype "input"))
      (node (ref "U2") (pin "E1") (pinfunction "IO_L46N_M3CLKN_3_E1") (pintype "bidirectional"))
    )
    (net (code "76") (name "CMPMEAS_+") (class "Default")
      (node (ref "R153") (pin "1") (pinfunction "P$1_1") (pintype "bidirectional"))
      (node (ref "R154") (pin "1") (pinfunction "P$1_1") (pintype "bidirectional"))
      (node (ref "R155") (pin "1") (pinfunction "P$1_1") (pintype "bidirectional"))
      (node (ref "R156") (pin "1") (pinfunction "P$1_1") (pintype "bidirectional"))
      (node (ref "R59") (pin "2") (pinfunction "P$2_2") (pintype "bidirectional"))
      (node (ref "SV4") (pin "1") (pinfunction "1_1") (pintype "passive"))
    )
    (net (code "77") (name "CMPMEAS_-") (class "Default")
      (node (ref "IC20") (pin "9") (pinfunction "R2_9") (pintype "bidirectional"))
      (node (ref "IC22") (pin "3") (pinfunction "Y_3") (pintype "bidirectional"))
    )
    (net (code "78") (name "CMPMEAS_A") (class "Default")
      (node (ref "IC22") (pin "10") (pinfunction "A_10") (pintype "input"))
      (node (ref "U2") (pin "R12") (pinfunction "IO_L52P_M1DQ14_1_R12") (pintype "bidirectional"))
    )
    (net (code "79") (name "CMPMEAS_B") (class "Default")
      (node (ref "IC22") (pin "9") (pinfunction "B_9") (pintype "input"))
      (node (ref "U2") (pin "M13") (pinfunction "IO_L74P_AWAKE_1_M13") (pintype "bidirectional"))
    )
    (net (code "80") (name "CMPMEAS_EN") (class "Default")
      (node (ref "IC22") (pin "6") (pinfunction "INH_6") (pintype "input"))
      (node (ref "U2") (pin "N12") (pinfunction "IO_L12P_D1_MISO2_2_N12") (pintype "bidirectional"))
    )
    (net (code "81") (name "CMPMEAS_O") (class "Default")
      (node (ref "IC22") (pin "13") (pinfunction "X_13") (pintype "bidirectional"))
      (node (ref "R152") (pin "2") (pinfunction "P$2_2") (pintype "bidirectional"))
    )
    (net (code "82") (name "CMP_MEAS_SEL") (class "Default")
      (node (ref "IC20") (pin "4") (pinfunction "SEL_4") (pintype "input"))
      (node (ref "U2") (pin "R16") (pinfunction "IO_L49N_M1DQ11_1_R16") (pintype "bidirectional"))
    )
    (net (code "83") (name "CS") (class "Default")
      (node (ref "IC3") (pin "3") (pinfunction "A2_3") (pintype "input"))
      (node (ref "R40") (pin "1") (pinfunction "P$1_1") (pintype "bidirectional"))
    )
    (net (code "84") (name "CSO_B") (class "Default")
      (node (ref "IC2") (pin "1") (pinfunction "~{CS}_1") (pintype "input"))
      (node (ref "R6") (pin "2") (pinfunction "P$2_2") (pintype "bidirectional"))
      (node (ref "U2") (pin "T3") (pinfunction "IO_L65N_CSO_B_2_T3") (pintype "bidirectional"))
    )
    (net (code "85") (name "DCRL+") (class "Default")
      (node (ref "IC37") (pin "3") (pinfunction "QD_3") (pintype "tri_state"))
      (node (ref "R235") (pin "2") (pinfunction "P$2_2") (pintype "bidirectional"))
    )
    (net (code "86") (name "DCRL+B") (class "Default")
      (node (ref "IC42") (pin "3") (pinfunction "QD_3") (pintype "tri_state"))
      (node (ref "R271") (pin "2") (pinfunction "P$2_2") (pintype "bidirectional"))
    )
    (net (code "87") (name "DCRL-") (class "Default")
      (node (ref "IC37") (pin "2") (pinfunction "QC_2") (pintype "tri_state"))
      (node (ref "R233") (pin "1") (pinfunction "P$1_1") (pintype "bidirectional"))
    )
    (net (code "88") (name "DCRL-B") (class "Default")
      (node (ref "IC42") (pin "2") (pinfunction "QC_2") (pintype "tri_state"))
      (node (ref "R269") (pin "1") (pinfunction "P$1_1") (pintype "bidirectional"))
    )
    (net (code "89") (name "DC_CS") (class "Default")
      (node (ref "IC32") (pin "2") (pinfunction "~{CS}_2") (pintype "input"))
      (node (ref "U2") (pin "M14") (pinfunction "IO_L74N_DOUT_BUSY_1_M14") (pintype "bidirectional"))
    )
    (net (code "90") (name "DC_DOUT") (class "Default")
      (node (ref "R280") (pin "1") (pinfunction "P$1_1") (pintype "bidirectional"))
      (node (ref "R281") (pin "1") (pinfunction "P$1_1") (pintype "bidirectional"))
      (node (ref "U2") (pin "T12") (pinfunction "IO_L52N_M1DQ15_1_T12") (pintype "bidirectional"))
    )
    (net (code "91") (name "DI") (class "Default")
      (node (ref "IC4") (pin "15") (pinfunction "AD2/RTS#/TDO/FSDO_15") (pintype "bidirectional"))
      (node (ref "R44") (pin "2") (pinfunction "P$2_2") (pintype "bidirectional"))
    )
    (net (code "92") (name "DIN") (class "Default")
      (node (ref "R5") (pin "1") (pinfunction "P$1_1") (pintype "bidirectional"))
      (node (ref "U2") (pin "P10") (pinfunction "IO_L3P_D0_DIN_MISO_MISO1_2_P10") (pintype "bidirectional"))
    )
    (net (code "93") (name "DO") (class "Default")
      (node (ref "IC3") (pin "4") (pinfunction "A3_4") (pintype "input"))
      (node (ref "R39") (pin "1") (pinfunction "P$1_1") (pintype "bidirectional"))
    )
    (net (code "94") (name "DQ0") (class "Default")
      (node (ref "IC26") (pin "B3") (pinfunction "DQ0_B3") (pintype "bidirectional"))
      (node (ref "U2") (pin "G1") (pinfunction "IO_L40N_M3DQ7_3_G1") (pintype "bidirectional"))
    )
    (net (code "95") (name "DQ1") (class "Default")
      (node (ref "IC26") (pin "C7") (pinfunction "DQ1_C7") (pintype "bidirectional"))
      (node (ref "U2") (pin "J1") (pinfunction "IO_L38N_M3DQ3_3_J1") (pintype "bidirectional"))
    )
    (net (code "96") (name "DQ2") (class "Default")
      (node (ref "IC26") (pin "C2") (pinfunction "DQ2_C2") (pintype "bidirectional"))
      (node (ref "U2") (pin "G3") (pinfunction "IO_L40P_M3DQ6_3_G3") (pintype "bidirectional"))
    )
    (net (code "97") (name "DQ3") (class "Default")
      (node (ref "IC26") (pin "C8") (pinfunction "DQ3_C8") (pintype "bidirectional"))
      (node (ref "U2") (pin "K1") (pinfunction "IO_L37N_M3DQ1_3_K1") (pintype "bidirectional"))
    )
    (net (code "98") (name "DQ4") (class "Default")
      (node (ref "IC26") (pin "E3") (pinfunction "DQ4_E3") (pintype "bidirectional"))
      (node (ref "U2") (pin "F2") (pinfunction "IO_L41P_GCLK27_M3DQ4_3_F2") (pintype "bidirectional"))
    )
    (net (code "99") (name "DQ5") (class "Default")
      (node (ref "IC26") (pin "E8") (pinfunction "DQ5_E8") (pintype "bidirectional"))
      (node (ref "U2") (pin "J3") (pinfunction "IO_L38P_M3DQ2_3_J3") (pintype "bidirectional"))
    )
    (net (code "100") (name "DQ6") (class "Default")
      (node (ref "IC26") (pin "D2") (pinfunction "DQ6_D2") (pintype "bidirectional"))
      (node (ref "U2") (pin "F1") (pinfunction "IO_L41N_GCLK26_M3DQ5_3_F1") (pintype "bidirectional"))
    )
    (net (code "101") (name "DQ7") (class "Default")
      (node (ref "IC26") (pin "E7") (pinfunction "DQ7_E7") (pintype "bidirectional"))
      (node (ref "U2") (pin "K2") (pinfunction "IO_L37P_M3DQ0_3_K2") (pintype "bidirectional"))
    )
    (net (code "102") (name "EXVO") (class "Default")
      (node (ref "C184") (pin "1") (pinfunction "1_1") (pintype "passive"))
      (node (ref "R111") (pin "1") (pinfunction "P$1_1") (pintype "bidirectional"))
      (node (ref "R185") (pin "2") (pinfunction "P$2_2") (pintype "bidirectional"))
      (node (ref "SV4") (pin "2") (pinfunction "2_2") (pintype "passive"))
    )
    (net (code "103") (name "GMUXA") (class "Default")
      (node (ref "IC34") (pin "10") (pinfunction "A_10") (pintype "input"))
      (node (ref "IC37") (pin "4") (pinfunction "QE_4") (pintype "tri_state"))
    )
    (net (code "104") (name "GMUXAB") (class "Default")
      (node (ref "IC39") (pin "10") (pinfunction "A_10") (pintype "input"))
      (node (ref "IC42") (pin "4") (pinfunction "QE_4") (pintype "tri_state"))
    )
    (net (code "105") (name "GMUXB") (class "Default")
      (node (ref "IC34") (pin "9") (pinfunction "B_9") (pintype "input"))
      (node (ref "IC37") (pin "5") (pinfunction "QF_5") (pintype "tri_state"))
    )
    (net (code "106") (name "GMUXBB") (class "Default")
      (node (ref "IC39") (pin "9") (pinfunction "B_9") (pintype "input"))
      (node (ref "IC42") (pin "5") (pinfunction "QF_5") (pintype "tri_state"))
    )
    (net (code "107") (name "GMUXC") (class "Default")
      (node (ref "IC35") (pin "10") (pinfunction "A_10") (pintype "input"))
      (node (ref "IC37") (pin "6") (pinfunction "QG_6") (pintype "tri_state"))
    )
    (net (code "108") (name "GMUXCB") (class "Default")
      (node (ref "IC40") (pin "10") (pinfunction "A_10") (pintype "input"))
      (node (ref "IC42") (pin "6") (pinfunction "QG_6") (pintype "tri_state"))
    )
    (net (code "109") (name "GMUXD") (class "Default")
      (node (ref "IC35") (pin "9") (pinfunction "B_9") (pintype "input"))
      (node (ref "IC37") (pin "7") (pinfunction "QH_7") (pintype "tri_state"))
    )
    (net (code "110") (name "GMUXDB") (class "Default")
      (node (ref "IC40") (pin "9") (pinfunction "B_9") (pintype "input"))
      (node (ref "IC42") (pin "7") (pinfunction "QH_7") (pintype "tri_state"))
    )
    (net (code "111") (name "GND") (class "Default")
      (node (ref "C10") (pin "2") (pinfunction "2_2") (pintype "passive"))
      (node (ref "C104") (pin "1") (pinfunction "1_1") (pintype "passive"))
      (node (ref "C105") (pin "1") (pinfunction "1_1") (pintype "passive"))
      (node (ref "C106") (pin "2") (pinfunction "2_2") (pintype "passive"))
      (node (ref "C107") (pin "2") (pinfunction "2_2") (pintype "passive"))
      (node (ref "C108") (pin "2") (pinfunction "2_2") (pintype "passive"))
      (node (ref "C109") (pin "2") (pinfunction "2_2") (pintype "passive"))
      (node (ref "C11") (pin "2") (pinfunction "2_2") (pintype "passive"))
      (node (ref "C110") (pin "2") (pinfunction "2_2") (pintype "passive"))
      (node (ref "C111") (pin "2") (pinfunction "2_2") (pintype "passive"))
      (node (ref "C112") (pin "1") (pinfunction "1_1") (pintype "passive"))
      (node (ref "C114") (pin "1") (pinfunction "1_1") (pintype "passive"))
      (node (ref "C115") (pin "1") (pinfunction "1_1") (pintype "passive"))
      (node (ref "C116") (pin "2") (pinfunction "2_2") (pintype "passive"))
      (node (ref "C117") (pin "2") (pinfunction "2_2") (pintype "passive"))
      (node (ref "C118") (pin "1") (pinfunction "1_1") (pintype "passive"))
      (node (ref "C119") (pin "1") (pinfunction "1_1") (pintype "passive"))
      (node (ref "C12") (pin "2") (pinfunction "2_2") (pintype "passive"))
      (node (ref "C120") (pin "1") (pinfunction "1_1") (pintype "passive"))
      (node (ref "C125") (pin "2") (pinfunction "2_2") (pintype "passive"))
      (node (ref "C126") (pin "2") (pinfunction "2_2") (pintype "passive"))
      (node (ref "C13") (pin "2") (pinfunction "2_2") (pintype "passive"))
      (node (ref "C133") (pin "1") (pinfunction "1_1") (pintype "passive"))
      (node (ref "C134") (pin "1") (pinfunction "1_1") (pintype "passive"))
      (node (ref "C137") (pin "2") (pinfunction "2_2") (pintype "passive"))
      (node (ref "C138") (pin "2") (pinfunction "2_2") (pintype "passive"))
      (node (ref "C139") (pin "2") (pinfunction "2_2") (pintype "passive"))
      (node (ref "C14") (pin "2") (pinfunction "2_2") (pintype "passive"))
      (node (ref "C140") (pin "2") (pinfunction "2_2") (pintype "passive"))
      (node (ref "C141") (pin "2") (pinfunction "2_2") (pintype "passive"))
      (node (ref "C142") (pin "1") (pinfunction "1_1") (pintype "passive"))
      (node (ref "C143") (pin "1") (pinfunction "1_1") (pintype "passive"))
      (node (ref "C144") (pin "1") (pinfunction "1_1") (pintype "passive"))
      (node (ref "C145") (pin "2") (pinfunction "2_2") (pintype "passive"))
      (node (ref "C146") (pin "1") (pinfunction "1_1") (pintype "passive"))
      (node (ref "C147") (pin "1") (pinfunction "1_1") (pintype "passive"))
      (node (ref "C148") (pin "2") (pinfunction "2_2") (pintype "passive"))
      (node (ref "C15") (pin "2") (pinfunction "2_2") (pintype "passive"))
      (node (ref "C150") (pin "1") (pinfunction "1_1") (pintype "passive"))
      (node (ref "C155") (pin "1") (pinfunction "1_1") (pintype "passive"))
      (node (ref "C156") (pin "2") (pinfunction "2_2") (pintype "passive"))
      (node (ref "C157") (pin "-") (pinfunction "-_-") (pintype "passive"))
      (node (ref "C158") (pin "+") (pinfunction "+_+") (pintype "passive"))
      (node (ref "C16") (pin "2") (pinfunction "2_2") (pintype "passive"))
      (node (ref "C160") (pin "2") (pinfunction "2_2") (pintype "passive"))
      (node (ref "C161") (pin "-") (pinfunction "-_-") (pintype "passive"))
      (node (ref "C162") (pin "1") (pinfunction "1_1") (pintype "passive"))
      (node (ref "C164") (pin "1") (pinfunction "1_1") (pintype "passive"))
      (node (ref "C165") (pin "1") (pinfunction "1_1") (pintype "passive"))
      (node (ref "C166") (pin "1") (pinfunction "1_1") (pintype "passive"))
      (node (ref "C167") (pin "2") (pinfunction "2_2") (pintype "passive"))
      (node (ref "C168") (pin "2") (pinfunction "2_2") (pintype "passive"))
      (node (ref "C169") (pin "2") (pinfunction "2_2") (pintype "passive"))
      (node (ref "C17") (pin "2") (pinfunction "2_2") (pintype "passive"))
      (node (ref "C170") (pin "1") (pinfunction "1_1") (pintype "passive"))
      (node (ref "C171") (pin "1") (pinfunction "1_1") (pintype "passive"))
      (node (ref "C172") (pin "1") (pinfunction "1_1") (pintype "passive"))
      (node (ref "C173") (pin "1") (pinfunction "1_1") (pintype "passive"))
      (node (ref "C175") (pin "2") (pinfunction "2_2") (pintype "passive"))
      (node (ref "C176") (pin "2") (pinfunction "2_2") (pintype "passive"))
      (node (ref "C177") (pin "1") (pinfunction "1_1") (pintype "passive"))
      (node (ref "C179") (pin "2") (pinfunction "2_2") (pintype "passive"))
      (node (ref "C18") (pin "2") (pinfunction "2_2") (pintype "passive"))
      (node (ref "C180") (pin "2") (pinfunction "2_2") (pintype "passive"))
      (node (ref "C182") (pin "2") (pinfunction "2_2") (pintype "passive"))
      (node (ref "C183") (pin "2") (pinfunction "2_2") (pintype "passive"))
      (node (ref "C184") (pin "2") (pinfunction "2_2") (pintype "passive"))
      (node (ref "C185") (pin "2") (pinfunction "2_2") (pintype "passive"))
      (node (ref "C186") (pin "2") (pinfunction "2_2") (pintype "passive"))
      (node (ref "C187") (pin "2") (pinfunction "2_2") (pintype "passive"))
      (node (ref "C191") (pin "2") (pinfunction "2_2") (pintype "passive"))
      (node (ref "C192") (pin "2") (pinfunction "2_2") (pintype "passive"))
      (node (ref "C193") (pin "1") (pinfunction "1_1") (pintype "passive"))
      (node (ref "C194") (pin "2") (pinfunction "2_2") (pintype "passive"))
      (node (ref "C196") (pin "2") (pinfunction "2_2") (pintype "passive"))
      (node (ref "C197") (pin "1") (pinfunction "1_1") (pintype "passive"))
      (node (ref "C198") (pin "1") (pinfunction "1_1") (pintype "passive"))
      (node (ref "C2") (pin "1") (pinfunction "1_1") (pintype "passive"))
      (node (ref "C20") (pin "1") (pinfunction "1_1") (pintype "passive"))
      (node (ref "C200") (pin "2") (pinfunction "2_2") (pintype "passive"))
      (node (ref "C201") (pin "2") (pinfunction "2_2") (pintype "passive"))
      (node (ref "C202") (pin "2") (pinfunction "2_2") (pintype "passive"))
      (node (ref "C203") (pin "2") (pinfunction "2_2") (pintype "passive"))
      (node (ref "C204") (pin "1") (pinfunction "1_1") (pintype "passive"))
      (node (ref "C205") (pin "1") (pinfunction "1_1") (pintype "passive"))
      (node (ref "C206") (pin "1") (pinfunction "1_1") (pintype "passive"))
      (node (ref "C207") (pin "2") (pinfunction "2_2") (pintype "passive"))
      (node (ref "C208") (pin "1") (pinfunction "1_1") (pintype "passive"))
      (node (ref "C209") (pin "2") (pinfunction "2_2") (pintype "passive"))
      (node (ref "C21") (pin "1") (pinfunction "1_1") (pintype "passive"))
      (node (ref "C210") (pin "1") (pinfunction "1_1") (pintype "passive"))
      (node (ref "C212") (pin "1") (pinfunction "1_1") (pintype "passive"))
      (node (ref "C213") (pin "2") (pinfunction "A_2") (pintype "passive"))
      (node (ref "C215") (pin "1") (pinfunction "1_1") (pintype "passive"))
      (node (ref "C216") (pin "2") (pinfunction "A_2") (pintype "passive"))
      (node (ref "C218") (pin "1") (pinfunction "1_1") (pintype "passive"))
      (node (ref "C219") (pin "2") (pinfunction "2_2") (pintype "passive"))
      (node (ref "C22") (pin "2") (pinfunction "2_2") (pintype "passive"))
      (node (ref "C220") (pin "1") (pinfunction "1_1") (pintype "passive"))
      (node (ref "C221") (pin "1") (pinfunction "1_1") (pintype "passive"))
      (node (ref "C224") (pin "2") (pinfunction "2_2") (pintype "passive"))
      (node (ref "C225") (pin "2") (pinfunction "2_2") (pintype "passive"))
      (node (ref "C226") (pin "2") (pinfunction "2_2") (pintype "passive"))
      (node (ref "C227") (pin "2") (pinfunction "2_2") (pintype "passive"))
      (node (ref "C23") (pin "2") (pinfunction "2_2") (pintype "passive"))
      (node (ref "C230") (pin "1") (pinfunction "1_1") (pintype "passive"))
      (node (ref "C231") (pin "1") (pinfunction "1_1") (pintype "passive"))
      (node (ref "C232") (pin "2") (pinfunction "2_2") (pintype "passive"))
      (node (ref "C233") (pin "1") (pinfunction "1_1") (pintype "passive"))
      (node (ref "C234") (pin "2") (pinfunction "2_2") (pintype "passive"))
      (node (ref "C235") (pin "1") (pinfunction "1_1") (pintype "passive"))
      (node (ref "C237") (pin "1") (pinfunction "1_1") (pintype "passive"))
      (node (ref "C238") (pin "2") (pinfunction "A_2") (pintype "passive"))
      (node (ref "C24") (pin "2") (pinfunction "2_2") (pintype "passive"))
      (node (ref "C240") (pin "1") (pinfunction "1_1") (pintype "passive"))
      (node (ref "C241") (pin "2") (pinfunction "A_2") (pintype "passive"))
      (node (ref "C243") (pin "1") (pinfunction "1_1") (pintype "passive"))
      (node (ref "C244") (pin "2") (pinfunction "2_2") (pintype "passive"))
      (node (ref "C245") (pin "1") (pinfunction "1_1") (pintype "passive"))
      (node (ref "C246") (pin "1") (pinfunction "1_1") (pintype "passive"))
      (node (ref "C249") (pin "2") (pinfunction "2_2") (pintype "passive"))
      (node (ref "C25") (pin "2") (pinfunction "2_2") (pintype "passive"))
      (node (ref "C250") (pin "2") (pinfunction "2_2") (pintype "passive"))
      (node (ref "C251") (pin "2") (pinfunction "2_2") (pintype "passive"))
      (node (ref "C252") (pin "2") (pinfunction "2_2") (pintype "passive"))
      (node (ref "C255") (pin "2") (pinfunction "2_2") (pintype "passive"))
      (node (ref "C256") (pin "2") (pinfunction "2_2") (pintype "passive"))
      (node (ref "C26") (pin "2") (pinfunction "2_2") (pintype "passive"))
      (node (ref "C27") (pin "1") (pinfunction "1_1") (pintype "passive"))
      (node (ref "C28") (pin "2") (pinfunction "2_2") (pintype "passive"))
      (node (ref "C29") (pin "2") (pinfunction "2_2") (pintype "passive"))
      (node (ref "C3") (pin "1") (pinfunction "1_1") (pintype "passive"))
      (node (ref "C30") (pin "2") (pinfunction "2_2") (pintype "passive"))
      (node (ref "C31") (pin "2") (pinfunction "2_2") (pintype "passive"))
      (node (ref "C32") (pin "2") (pinfunction "2_2") (pintype "passive"))
      (node (ref "C33") (pin "2") (pinfunction "2_2") (pintype "passive"))
      (node (ref "C34") (pin "2") (pinfunction "2_2") (pintype "passive"))
      (node (ref "C35") (pin "2") (pinfunction "2_2") (pintype "passive"))
      (node (ref "C37") (pin "2") (pinfunction "2_2") (pintype "passive"))
      (node (ref "C38") (pin "2") (pinfunction "2_2") (pintype "passive"))
      (node (ref "C57") (pin "2") (pinfunction "2_2") (pintype "passive"))
      (node (ref "C58") (pin "2") (pinfunction "2_2") (pintype "passive"))
      (node (ref "C59") (pin "2") (pinfunction "2_2") (pintype "passive"))
      (node (ref "C60") (pin "2") (pinfunction "2_2") (pintype "passive"))
      (node (ref "C61") (pin "2") (pinfunction "2_2") (pintype "passive"))
      (node (ref "C62") (pin "2") (pinfunction "2_2") (pintype "passive"))
      (node (ref "C63") (pin "2") (pinfunction "2_2") (pintype "passive"))
      (node (ref "C64") (pin "2") (pinfunction "2_2") (pintype "passive"))
      (node (ref "C65") (pin "2") (pinfunction "2_2") (pintype "passive"))
      (node (ref "C66") (pin "2") (pinfunction "2_2") (pintype "passive"))
      (node (ref "C67") (pin "2") (pinfunction "2_2") (pintype "passive"))
      (node (ref "C68") (pin "2") (pinfunction "2_2") (pintype "passive"))
      (node (ref "C69") (pin "2") (pinfunction "2_2") (pintype "passive"))
      (node (ref "C70") (pin "2") (pinfunction "2_2") (pintype "passive"))
      (node (ref "C71") (pin "2") (pinfunction "2_2") (pintype "passive"))
      (node (ref "C72") (pin "2") (pinfunction "2_2") (pintype "passive"))
      (node (ref "C73") (pin "2") (pinfunction "2_2") (pintype "passive"))
      (node (ref "C76") (pin "2") (pinfunction "2_2") (pintype "passive"))
      (node (ref "C77") (pin "1") (pinfunction "1_1") (pintype "passive"))
      (node (ref "C79") (pin "1") (pinfunction "1_1") (pintype "passive"))
      (node (ref "C8") (pin "2") (pinfunction "2_2") (pintype "passive"))
      (node (ref "C80") (pin "1") (pinfunction "1_1") (pintype "passive"))
      (node (ref "C81") (pin "1") (pinfunction "1_1") (pintype "passive"))
      (node (ref "C82") (pin "1") (pinfunction "1_1") (pintype "passive"))
      (node (ref "C83") (pin "1") (pinfunction "1_1") (pintype "passive"))
      (node (ref "C84") (pin "1") (pinfunction "1_1") (pintype "passive"))
      (node (ref "C86") (pin "1") (pinfunction "1_1") (pintype "passive"))
      (node (ref "C87") (pin "1") (pinfunction "1_1") (pintype "passive"))
      (node (ref "C88") (pin "1") (pinfunction "1_1") (pintype "passive"))
      (node (ref "C9") (pin "2") (pinfunction "2_2") (pintype "passive"))
      (node (ref "C91") (pin "1") (pinfunction "1_1") (pintype "passive"))
      (node (ref "C92") (pin "2") (pinfunction "2_2") (pintype "passive"))
      (node (ref "C93") (pin "2") (pinfunction "2_2") (pintype "passive"))
      (node (ref "C94") (pin "1") (pinfunction "1_1") (pintype "passive"))
      (node (ref "C96") (pin "2") (pinfunction "2_2") (pintype "passive"))
      (node (ref "C97") (pin "2") (pinfunction "2_2") (pintype "passive"))
      (node (ref "C99") (pin "1") (pinfunction "1_1") (pintype "passive"))
      (node (ref "IC1") (pin "2") (pinfunction "GND_2") (pintype "bidirectional"))
      (node (ref "IC10") (pin "2") (pinfunction "GND_2") (pintype "bidirectional"))
      (node (ref "IC11") (pin "2") (pinfunction "GND_2") (pintype "power_in"))
      (node (ref "IC12") (pin "2") (pinfunction "GND_2") (pintype "power_in"))
      (node (ref "IC13") (pin "20") (pinfunction "DFS0_20") (pintype "input"))
      (node (ref "IC13") (pin "22") (pinfunction "DEM0_22") (pintype "input"))
      (node (ref "IC13") (pin "23") (pinfunction "SDFIL_23") (pintype "input"))
      (node (ref "IC13") (pin "26") (pinfunction "VSS2_26") (pintype "power_in"))
      (node (ref "IC13") (pin "7") (pinfunction "VSS1_7") (pintype "power_in"))
      (node (ref "IC13") (pin "9") (pinfunction "PS_9") (pintype "input"))
      (node (ref "IC14") (pin "1") (pinfunction "GND_1") (pintype "power_in"))
      (node (ref "IC15") (pin "4") (pinfunction "V-_4") (pintype "power_in"))
      (node (ref "IC16") (pin "3") (pinfunction "+IN_3") (pintype "input"))
      (node (ref "IC16") (pin "5") (pinfunction "+IN_5") (pintype "input"))
      (node (ref "IC19") (pin "4") (pinfunction "V-_4") (pintype "power_in"))
      (node (ref "IC2") (pin "4") (pinfunction "GND_4") (pintype "power_in"))
      (node (ref "IC20") (pin "1") (pinfunction "MUTE_1") (pintype "input"))
      (node (ref "IC20") (pin "5") (pinfunction "GND_5") (pintype "power_in"))
      (node (ref "IC20") (pin "7") (pinfunction "GND_7") (pintype "power_in"))
      (node (ref "IC20") (pin "8") (pinfunction "GND_8") (pintype "power_in"))
      (node (ref "IC20") (pin "GPD") (pinfunction "GND_GPD") (pintype "power_in"))
      (node (ref "IC22") (pin "8") (pinfunction "GND_8") (pintype "power_in"))
      (node (ref "IC23") (pin "4") (pinfunction "V-_4") (pintype "power_in"))
      (node (ref "IC25") (pin "4") (pinfunction "V-_4") (pintype "power_in"))
      (node (ref "IC26") (pin "A1") (pinfunction "VSS_A1") (pintype "power_in"))
      (node (ref "IC26") (pin "A8") (pinfunction "VSS_A8") (pintype "power_in"))
      (node (ref "IC26") (pin "B1") (pinfunction "VSS_B1") (pintype "power_in"))
      (node (ref "IC26") (pin "B2") (pinfunction "VSSQ_B2") (pintype "power_in"))
      (node (ref "IC26") (pin "B8") (pinfunction "VSSQ_B8") (pintype "power_in"))
      (node (ref "IC26") (pin "C9") (pinfunction "VSSQ_C9") (pintype "power_in"))
      (node (ref "IC26") (pin "D1") (pinfunction "VSSQ_D1") (pintype "power_in"))
      (node (ref "IC26") (pin "D8") (pinfunction "VSS_D8") (pintype "power_in"))
      (node (ref "IC26") (pin "D9") (pinfunction "VSSQ_D9") (pintype "power_in"))
      (node (ref "IC26") (pin "F2") (pinfunction "VSS_F2") (pintype "power_in"))
      (node (ref "IC26") (pin "F8") (pinfunction "VSS_F8") (pintype "power_in"))
      (node (ref "IC26") (pin "H2") (pinfunction "CS#_H2") (pintype "input"))
      (node (ref "IC26") (pin "J1") (pinfunction "VSS_J1") (pintype "power_in"))
      (node (ref "IC26") (pin "J9") (pinfunction "VSS_J9") (pintype "power_in"))
      (node (ref "IC26") (pin "L1") (pinfunction "VSS_L1") (pintype "power_in"))
      (node (ref "IC26") (pin "L9") (pinfunction "VSS_L9") (pintype "power_in"))
      (node (ref "IC26") (pin "N1") (pinfunction "VSS_N1") (pintype "power_in"))
      (node (ref "IC26") (pin "N9") (pinfunction "VSS_N9") (pintype "power_in"))
      (node (ref "IC28") (pin "1") (pinfunction "GND_1") (pintype "power_in"))
      (node (ref "IC29") (pin "2") (pinfunction "GND_2") (pintype "power_in"))
      (node (ref "IC3") (pin "9") (pinfunction "GND2_9") (pintype "power_in"))
      (node (ref "IC30") (pin "4") (pinfunction "V-_4") (pintype "power_in"))
      (node (ref "IC31") (pin "2") (pinfunction "-IN_2") (pintype "input"))
      (node (ref "IC31") (pin "3") (pinfunction "+IN_3") (pintype "input"))
      (node (ref "IC32") (pin "3") (pinfunction "GND_3") (pintype "power_in"))
      (node (ref "IC33") (pin "1") (pinfunction "~{POWERDOWN}_1") (pintype "passive"))
      (node (ref "IC33") (pin "11") (pinfunction "V-_11") (pintype "power_in"))
      (node (ref "IC33") (pin "2") (pinfunction "~{POWERDOWN}_2") (pintype "passive"))
      (node (ref "IC33") (pin "3") (pinfunction "~{POWERDOWN}_3") (pintype "passive"))
      (node (ref "IC34") (pin "6") (pinfunction "INH_6") (pintype "input"))
      (node (ref "IC34") (pin "8") (pinfunction "GND_8") (pintype "power_in"))
      (node (ref "IC35") (pin "6") (pinfunction "INH_6") (pintype "input"))
      (node (ref "IC35") (pin "8") (pinfunction "GND_8") (pintype "power_in"))
      (node (ref "IC37") (pin "13") (pinfunction "G_13") (pintype "input"))
      (node (ref "IC37") (pin "8") (pinfunction "GND_8") (pintype "power_in"))
      (node (ref "IC38") (pin "1") (pinfunction "~{POWERDOWN}_1") (pintype "passive"))
      (node (ref "IC38") (pin "11") (pinfunction "V-_11") (pintype "power_in"))
      (node (ref "IC38") (pin "2") (pinfunction "~{POWERDOWN}_2") (pintype "passive"))
      (node (ref "IC38") (pin "3") (pinfunction "~{POWERDOWN}_3") (pintype "passive"))
      (node (ref "IC39") (pin "6") (pinfunction "INH_6") (pintype "input"))
      (node (ref "IC39") (pin "8") (pinfunction "GND_8") (pintype "power_in"))
      (node (ref "IC40") (pin "6") (pinfunction "INH_6") (pintype "input"))
      (node (ref "IC40") (pin "8") (pinfunction "GND_8") (pintype "power_in"))
      (node (ref "IC42") (pin "13") (pinfunction "G_13") (pintype "input"))
      (node (ref "IC42") (pin "8") (pinfunction "GND_8") (pintype "power_in"))
      (node (ref "IC43") (pin "2") (pinfunction "V-_2") (pintype "power_in"))
      (node (ref "IC44") (pin "13") (pinfunction "G_13") (pintype "input"))
      (node (ref "IC44") (pin "8") (pinfunction "GND_8") (pintype "power_in"))
      (node (ref "IC5") (pin "11") (pinfunction "AGND_11") (pintype "power_in"))
      (node (ref "IC5") (pin "17") (pinfunction "DRGND_17") (pintype "power_in"))
      (node (ref "IC5") (pin "2") (pinfunction "AGND_2") (pintype "power_in"))
      (node (ref "IC5") (pin "5") (pinfunction "AGND_5") (pintype "power_in"))
      (node (ref "IC5") (pin "7") (pinfunction "VINGND_7") (pintype "power_in"))
      (node (ref "IC5") (pin "8") (pinfunction "AGND_8") (pintype "power_in"))
      (node (ref "IC6") (pin "11") (pinfunction "AGND_11") (pintype "power_in"))
      (node (ref "IC6") (pin "17") (pinfunction "DRGND_17") (pintype "power_in"))
      (node (ref "IC6") (pin "2") (pinfunction "AGND_2") (pintype "power_in"))
      (node (ref "IC6") (pin "5") (pinfunction "AGND_5") (pintype "power_in"))
      (node (ref "IC6") (pin "7") (pinfunction "VINGND_7") (pintype "power_in"))
      (node (ref "IC6") (pin "8") (pinfunction "AGND_8") (pintype "power_in"))
      (node (ref "IC7") (pin "2") (pinfunction "GND_2") (pintype "power_in"))
      (node (ref "IC9") (pin "11") (pinfunction "GND_11") (pintype "power_in"))
      (node (ref "IC9") (pin "12") (pinfunction "GND_12") (pintype "power_in"))
      (node (ref "IC9") (pin "13") (pinfunction "GND_13") (pintype "power_in"))
      (node (ref "IC9") (pin "22") (pinfunction "~{OE}_22") (pintype "input"))
      (node (ref "QG1") (pin "2") (pinfunction "GND_2") (pintype "power_in"))
      (node (ref "R112") (pin "1") (pinfunction "P$1_1") (pintype "bidirectional"))
      (node (ref "R144") (pin "1") (pinfunction "P$1_1") (pintype "bidirectional"))
      (node (ref "R146") (pin "1") (pinfunction "P$1_1") (pintype "bidirectional"))
      (node (ref "R150") (pin "1") (pinfunction "P$1_1") (pintype "bidirectional"))
      (node (ref "R164") (pin "1") (pinfunction "P$1_1") (pintype "bidirectional"))
      (node (ref "R167") (pin "1") (pinfunction "P$1_1") (pintype "bidirectional"))
      (node (ref "R171") (pin "1") (pinfunction "P$1_1") (pintype "bidirectional"))
      (node (ref "R176") (pin "1") (pinfunction "P$1_1") (pintype "bidirectional"))
      (node (ref "R196") (pin "2") (pinfunction "P$2_2") (pintype "bidirectional"))
      (node (ref "R2") (pin "1") (pinfunction "P$1_1") (pintype "bidirectional"))
      (node (ref "R201") (pin "2") (pinfunction "P$2_2") (pintype "bidirectional"))
      (node (ref "R224") (pin "1") (pinfunction "P$1_1") (pintype "bidirectional"))
      (node (ref "R228") (pin "1") (pinfunction "P$1_1") (pintype "bidirectional"))
      (node (ref "R240") (pin "1") (pinfunction "P$1_1") (pintype "bidirectional"))
      (node (ref "R260") (pin "1") (pinfunction "P$1_1") (pintype "bidirectional"))
      (node (ref "R264") (pin "1") (pinfunction "P$1_1") (pintype "bidirectional"))
      (node (ref "R276") (pin "1") (pinfunction "P$1_1") (pintype "bidirectional"))
      (node (ref "R281") (pin "2") (pinfunction "P$2_2") (pintype "bidirectional"))
      (node (ref "R299") (pin "1") (pinfunction "P$1_1") (pintype "bidirectional"))
      (node (ref "R3") (pin "2") (pinfunction "P$2_2") (pintype "bidirectional"))
      (node (ref "R4") (pin "1") (pinfunction "P$1_1") (pintype "bidirectional"))
      (node (ref "R47") (pin "1") (pinfunction "P$1_1") (pintype "bidirectional"))
      (node (ref "R53") (pin "1") (pinfunction "P$1_1") (pintype "bidirectional"))
      (node (ref "R55") (pin "1") (pinfunction "P$1_1") (pintype "bidirectional"))
      (node (ref "R60") (pin "2") (pinfunction "P$2_2") (pintype "bidirectional"))
      (node (ref "R7") (pin "1") (pinfunction "P$1_1") (pintype "bidirectional"))
      (node (ref "R77") (pin "2") (pinfunction "P$2_2") (pintype "bidirectional"))
      (node (ref "R78") (pin "2") (pinfunction "P$2_2") (pintype "bidirectional"))
      (node (ref "R84") (pin "1") (pinfunction "P$1_1") (pintype "bidirectional"))
      (node (ref "R88") (pin "2") (pinfunction "P$2_2") (pintype "bidirectional"))
      (node (ref "R9") (pin "2") (pinfunction "P$2_2") (pintype "bidirectional"))
      (node (ref "R93") (pin "1") (pinfunction "P$1_1") (pintype "bidirectional"))
      (node (ref "SV1") (pin "1") (pinfunction "1_1") (pintype "passive"))
      (node (ref "SV1") (pin "3") (pinfunction "3_3") (pintype "passive"))
      (node (ref "SV1") (pin "5") (pinfunction "5_5") (pintype "passive"))
      (node (ref "SV1") (pin "7") (pinfunction "7_7") (pintype "passive"))
      (node (ref "SV1") (pin "9") (pinfunction "9_9") (pintype "passive"))
      (node (ref "SV2") (pin "10") (pinfunction "10_10") (pintype "passive"))
      (node (ref "SV2") (pin "12") (pinfunction "12_12") (pintype "passive"))
      (node (ref "SV2") (pin "14") (pinfunction "14_14") (pintype "passive"))
      (node (ref "SV2") (pin "16") (pinfunction "16_16") (pintype "passive"))
      (node (ref "SV2") (pin "2") (pinfunction "2_2") (pintype "passive"))
      (node (ref "SV2") (pin "4") (pinfunction "4_4") (pintype "passive"))
      (node (ref "SV2") (pin "6") (pinfunction "6_6") (pintype "passive"))
      (node (ref "SV2") (pin "8") (pinfunction "8_8") (pintype "passive"))
      (node (ref "SV3") (pin "10") (pinfunction "10_10") (pintype "passive"))
      (node (ref "SV3") (pin "12") (pinfunction "12_12") (pintype "passive"))
      (node (ref "SV3") (pin "14") (pinfunction "14_14") (pintype "passive"))
      (node (ref "SV3") (pin "16") (pinfunction "16_16") (pintype "passive"))
      (node (ref "SV3") (pin "2") (pinfunction "2_2") (pintype "passive"))
      (node (ref "SV3") (pin "4") (pinfunction "4_4") (pintype "passive"))
      (node (ref "SV3") (pin "6") (pinfunction "6_6") (pintype "passive"))
      (node (ref "SV3") (pin "8") (pinfunction "8_8") (pintype "passive"))
      (node (ref "SV4") (pin "10") (pinfunction "10_10") (pintype "passive"))
      (node (ref "SV4") (pin "12") (pinfunction "12_12") (pintype "passive"))
      (node (ref "SV4") (pin "13") (pinfunction "13_13") (pintype "passive"))
      (node (ref "SV4") (pin "3") (pinfunction "3_3") (pintype "passive"))
      (node (ref "SV4") (pin "4") (pinfunction "4_4") (pintype "passive"))
      (node (ref "SV4") (pin "9") (pinfunction "9_9") (pintype "passive"))
      (node (ref "SV5") (pin "2") (pinfunction "2_2") (pintype "passive"))
      (node (ref "T1") (pin "4") (pinfunction "SM_4") (pintype "passive"))
      (node (ref "T12") (pin "C") (pinfunction "C_C") (pintype "passive"))
      (node (ref "T13") (pin "C") (pinfunction "C_C") (pintype "passive"))
      (node (ref "T15") (pin "C") (pinfunction "C_C") (pintype "passive"))
      (node (ref "T17") (pin "C") (pinfunction "C_C") (pintype "passive"))
      (node (ref "T5") (pin "C") (pinfunction "C_C") (pintype "passive"))
      (node (ref "T6") (pin "C") (pinfunction "C_C") (pintype "passive"))
      (node (ref "T7") (pin "C") (pinfunction "C_C") (pintype "passive"))
      (node (ref "T9") (pin "C") (pinfunction "C_C") (pintype "passive"))
      (node (ref "U2") (pin "A1") (pinfunction "GND_A1") (pintype "power_in"))
      (node (ref "U2") (pin "A16") (pinfunction "GND_A16") (pintype "power_in"))
      (node (ref "U2") (pin "B11") (pinfunction "GND_B11") (pintype "power_in"))
      (node (ref "U2") (pin "B7") (pinfunction "GND_B7") (pintype "power_in"))
      (node (ref "U2") (pin "D13") (pinfunction "GND_D13") (pintype "power_in"))
      (node (ref "U2") (pin "D4") (pinfunction "GND_D4") (pintype "power_in"))
      (node (ref "U2") (pin "D5") (pinfunction "IO_L3P_0_D5") (pintype "bidirectional"))
      (node (ref "U2") (pin "E9") (pinfunction "GND_E9") (pintype "power_in"))
      (node (ref "U2") (pin "G15") (pinfunction "GND_G15") (pintype "power_in"))
      (node (ref "U2") (pin "G2") (pinfunction "GND_G2") (pintype "power_in"))
      (node (ref "U2") (pin "G8") (pinfunction "GND_G8") (pintype "power_in"))
      (node (ref "U2") (pin "H12") (pinfunction "GND_H12") (pintype "power_in"))
      (node (ref "U2") (pin "H7") (pinfunction "GND_H7") (pintype "power_in"))
      (node (ref "U2") (pin "H9") (pinfunction "GND_H9") (pintype "power_in"))
      (node (ref "U2") (pin "J5") (pinfunction "GND_J5") (pintype "power_in"))
      (node (ref "U2") (pin "J8") (pinfunction "GND_J8") (pintype "power_in"))
      (node (ref "U2") (pin "K7") (pinfunction "GND_K7") (pintype "power_in"))
      (node (ref "U2") (pin "K9") (pinfunction "GND_K9") (pintype "power_in"))
      (node (ref "U2") (pin "L15") (pinfunction "GND_L15") (pintype "power_in"))
      (node (ref "U2") (pin "L2") (pinfunction "GND_L2") (pintype "power_in"))
      (node (ref "U2") (pin "M8") (pinfunction "GND_M8") (pintype "power_in"))
      (node (ref "U2") (pin "N13") (pinfunction "GND_N13") (pintype "power_in"))
      (node (ref "U2") (pin "P14") (pinfunction "SUSPEND_P14") (pintype "input"))
      (node (ref "U2") (pin "P3") (pinfunction "GND_P3") (pintype "power_in"))
      (node (ref "U2") (pin "R10") (pinfunction "GND_R10") (pintype "power_in"))
      (node (ref "U2") (pin "R6") (pinfunction "GND_R6") (pintype "power_in"))
      (node (ref "U2") (pin "T1") (pinfunction "GND_T1") (pintype "power_in"))
      (node (ref "U2") (pin "T16") (pinfunction "GND_T16") (pintype "power_in"))
    )
    (net (code "112") (name "GNDIO") (class "Default")
      (node (ref "C151") (pin "1") (pinfunction "1_1") (pintype "passive"))
      (node (ref "C152") (pin "1") (pinfunction "1_1") (pintype "passive"))
      (node (ref "C153") (pin "1") (pinfunction "1_1") (pintype "passive"))
      (node (ref "C154") (pin "1") (pinfunction "1_1") (pintype "passive"))
      (node (ref "C159") (pin "-") (pinfunction "-_-") (pintype "passive"))
      (node (ref "C36") (pin "2") (pinfunction "2_2") (pintype "passive"))
      (node (ref "C39") (pin "2") (pinfunction "2_2") (pintype "passive"))
      (node (ref "C40") (pin "2") (pinfunction "2_2") (pintype "passive"))
      (node (ref "C41") (pin "2") (pinfunction "2_2") (pintype "passive"))
      (node (ref "C42") (pin "1") (pinfunction "1_1") (pintype "passive"))
      (node (ref "C43") (pin "1") (pinfunction "1_1") (pintype "passive"))
      (node (ref "C44") (pin "2") (pinfunction "2_2") (pintype "passive"))
      (node (ref "C45") (pin "2") (pinfunction "2_2") (pintype "passive"))
      (node (ref "C46") (pin "2") (pinfunction "2_2") (pintype "passive"))
      (node (ref "C47") (pin "2") (pinfunction "2_2") (pintype "passive"))
      (node (ref "C48") (pin "2") (pinfunction "2_2") (pintype "passive"))
      (node (ref "C49") (pin "2") (pinfunction "2_2") (pintype "passive"))
      (node (ref "C50") (pin "2") (pinfunction "2_2") (pintype "passive"))
      (node (ref "C51") (pin "2") (pinfunction "2_2") (pintype "passive"))
      (node (ref "C52") (pin "2") (pinfunction "2_2") (pintype "passive"))
      (node (ref "C53") (pin "2") (pinfunction "2_2") (pintype "passive"))
      (node (ref "C54") (pin "2") (pinfunction "2_2") (pintype "passive"))
      (node (ref "C55") (pin "1") (pinfunction "1_1") (pintype "passive"))
      (node (ref "C56") (pin "1") (pinfunction "1_1") (pintype "passive"))
      (node (ref "C74") (pin "2") (pinfunction "2_2") (pintype "passive"))
      (node (ref "IC24") (pin "7") (pinfunction "GND_7") (pintype "power_in"))
      (node (ref "IC27") (pin "7") (pinfunction "GND_7") (pintype "power_in"))
      (node (ref "IC3") (pin "8") (pinfunction "GND1_8") (pintype "power_in"))
      (node (ref "IC4") (pin "10") (pinfunction "GND_10") (pintype "power_in"))
      (node (ref "IC4") (pin "11") (pinfunction "GND_11") (pintype "power_in"))
      (node (ref "IC4") (pin "22") (pinfunction "GND_22") (pintype "power_in"))
      (node (ref "IC4") (pin "23") (pinfunction "GND_23") (pintype "power_in"))
      (node (ref "IC4") (pin "35") (pinfunction "GND_35") (pintype "power_in"))
      (node (ref "IC4") (pin "36") (pinfunction "GND_36") (pintype "power_in"))
      (node (ref "IC4") (pin "4") (pinfunction "AGND_4") (pintype "power_in"))
      (node (ref "IC4") (pin "41") (pinfunction "AGND_41") (pintype "power_in"))
      (node (ref "IC4") (pin "47") (pinfunction "GND_47") (pintype "power_in"))
      (node (ref "IC4") (pin "48") (pinfunction "GND_48") (pintype "power_in"))
      (node (ref "IC4") (pin "9") (pinfunction "AGND_9") (pintype "power_in"))
      (node (ref "IC8") (pin "5") (pinfunction "GND_5") (pintype "power_in"))
      (node (ref "Q2") (pin "2") (pinfunction "S_2") (pintype "passive"))
      (node (ref "Q3") (pin "2") (pinfunction "S_2") (pintype "passive"))
      (node (ref "R17") (pin "1") (pinfunction "P$1_1") (pintype "bidirectional"))
      (node (ref "X1") (pin "5") (pinfunction "5_5") (pintype "passive"))
    )
    (net (code "113") (name "GPIO0") (class "Default")
      (node (ref "IC3") (pin "6") (pinfunction "A5_6") (pintype "output"))
      (node (ref "IC4") (pin "17") (pinfunction "AD4/DTR#/GPIOL0_17") (pintype "bidirectional"))
    )
    (net (code "114") (name "GPIO1") (class "Default")
      (node (ref "IC3") (pin "2") (pinfunction "A1_2") (pintype "input"))
      (node (ref "IC4") (pin "18") (pinfunction "AD5/DSR#/GPIOL1_18") (pintype "bidirectional"))
    )
    (net (code "115") (name "HFDAC") (class "Default")
      (node (ref "R282") (pin "2") (pinfunction "P$2_2") (pintype "bidirectional"))
      (node (ref "SV4") (pin "11") (pinfunction "11_11") (pintype "passive"))
    )
    (net (code "116") (name "HFDAC_CLK") (class "Default")
      (node (ref "IC44") (pin "11") (pinfunction "SCK_11") (pintype "input"))
      (node (ref "U2") (pin "F13") (pinfunction "IO_L32P_A17_M1A8_1_F13") (pintype "bidirectional"))
    )
    (net (code "117") (name "HFDAC_CS") (class "Default")
      (node (ref "IC44") (pin "12") (pinfunction "RCK_12") (pintype "input"))
      (node (ref "U2") (pin "J13") (pinfunction "IO_L41P_GCLK9_IRDY1_M1RASN_1_J13") (pintype "bidirectional"))
    )
    (net (code "118") (name "HFDAC_DI") (class "Default")
      (node (ref "IC44") (pin "14") (pinfunction "SER_14") (pintype "input"))
      (node (ref "U2") (pin "L13") (pinfunction "IO_L53N_VREF_1_L13") (pintype "bidirectional"))
    )
    (net (code "119") (name "I2SBCK") (class "Default")
      (node (ref "IC13") (pin "12") (pinfunction "BICK_12") (pintype "input"))
      (node (ref "U2") (pin "N16") (pinfunction "IO_L45N_A0_M1LDQSN_1_N16") (pintype "bidirectional"))
    )
    (net (code "120") (name "I2SDATAIN") (class "Default")
      (node (ref "IC13") (pin "14") (pinfunction "SDTI_14") (pintype "input"))
      (node (ref "U2") (pin "M16") (pinfunction "IO_L46N_FOE_B_M1DQ3_1_M16") (pintype "bidirectional"))
    )
    (net (code "121") (name "I2SDATAOUT") (class "Default")
      (node (ref "R90") (pin "1") (pinfunction "P$1_1") (pintype "bidirectional"))
      (node (ref "U2") (pin "N14") (pinfunction "IO_L45P_A1_M1LDQS_1_N14") (pintype "bidirectional"))
    )
    (net (code "122") (name "I2SLRCK") (class "Default")
      (node (ref "IC13") (pin "11") (pinfunction "LRCK_11") (pintype "input"))
      (node (ref "U2") (pin "P15") (pinfunction "IO_L48P_HDC_M1DQ8_1_P15") (pintype "bidirectional"))
    )
    (net (code "123") (name "I2SSCLK") (class "Default")
      (node (ref "IC13") (pin "10") (pinfunction "MCLK_10") (pintype "input"))
      (node (ref "U2") (pin "P16") (pinfunction "IO_L48N_M1DQ9_1_P16") (pintype "bidirectional"))
    )
    (net (code "124") (name "LAD0") (class "Default")
      (node (ref "R116") (pin "1") (pinfunction "P$1_1") (pintype "bidirectional"))
      (node (ref "U2") (pin "T9") (pinfunction "IO_L23N_2_T9") (pintype "bidirectional"))
    )
    (net (code "125") (name "LAD1") (class "Default")
      (node (ref "R117") (pin "1") (pinfunction "P$1_1") (pintype "bidirectional"))
      (node (ref "U2") (pin "P7") (pinfunction "IO_L31P_GCLK31_D14_2_P7") (pintype "bidirectional"))
    )
    (net (code "126") (name "LAD2") (class "Default")
      (node (ref "R118") (pin "1") (pinfunction "P$1_1") (pintype "bidirectional"))
      (node (ref "U2") (pin "T8") (pinfunction "IO_L30N_GCLK0_USERCCLK_2_T8") (pintype "bidirectional"))
    )
    (net (code "127") (name "LAD3") (class "Default")
      (node (ref "R119") (pin "1") (pinfunction "P$1_1") (pintype "bidirectional"))
      (node (ref "U2") (pin "T7") (pinfunction "IO_L32N_GCLK28_2_T7") (pintype "bidirectional"))
    )
    (net (code "128") (name "LAD4") (class "Default")
      (node (ref "R120") (pin "1") (pinfunction "P$1_1") (pintype "bidirectional"))
      (node (ref "U2") (pin "R7") (pinfunction "IO_L32P_GCLK29_2_R7") (pintype "bidirectional"))
    )
    (net (code "129") (name "LAD5") (class "Default")
      (node (ref "R121") (pin "1") (pinfunction "P$1_1") (pintype "bidirectional"))
      (node (ref "U2") (pin "T6") (pinfunction "IO_L47N_2_T6") (pintype "bidirectional"))
    )
    (net (code "130") (name "LAD6") (class "Default")
      (node (ref "R122") (pin "1") (pinfunction "P$1_1") (pintype "bidirectional"))
      (node (ref "U2") (pin "R5") (pinfunction "IO_L48P_D7_2_R5") (pintype "bidirectional"))
    )
    (net (code "131") (name "LAD7") (class "Default")
      (node (ref "R123") (pin "1") (pinfunction "P$1_1") (pintype "bidirectional"))
      (node (ref "U2") (pin "T4") (pinfunction "IO_L63N_2_T4") (pintype "bidirectional"))
    )
    (net (code "132") (name "LAD8") (class "Default")
      (node (ref "IC9") (pin "3") (pinfunction "A1_3") (pintype "bidirectional"))
      (node (ref "U2") (pin "N5") (pinfunction "IO_L49P_D3_2_N5") (pintype "bidirectional"))
    )
    (net (code "133") (name "LAD9") (class "Default")
      (node (ref "IC9") (pin "4") (pinfunction "A2_4") (pintype "bidirectional"))
      (node (ref "U2") (pin "P5") (pinfunction "IO_L49N_D4_2_P5") (pintype "bidirectional"))
    )
    (net (code "134") (name "LAD10") (class "Default")
      (node (ref "IC9") (pin "5") (pinfunction "A3_5") (pintype "bidirectional"))
      (node (ref "U2") (pin "P6") (pinfunction "IO_L47P_2_P6") (pintype "bidirectional"))
    )
    (net (code "135") (name "LAD11") (class "Default")
      (node (ref "IC9") (pin "6") (pinfunction "A4_6") (pintype "bidirectional"))
      (node (ref "U2") (pin "N8") (pinfunction "IO_L29N_GCLK2_2_N8") (pintype "bidirectional"))
    )
    (net (code "136") (name "LAD12") (class "Default")
      (node (ref "IC9") (pin "7") (pinfunction "A5_7") (pintype "bidirectional"))
      (node (ref "U2") (pin "N9") (pinfunction "IO_L14P_D11_2_N9") (pintype "bidirectional"))
    )
    (net (code "137") (name "LAD13") (class "Default")
      (node (ref "IC9") (pin "8") (pinfunction "A6_8") (pintype "bidirectional"))
      (node (ref "U2") (pin "P9") (pinfunction "IO_L14N_D12_2_P9") (pintype "bidirectional"))
    )
    (net (code "138") (name "LAD14") (class "Default")
      (node (ref "IC9") (pin "9") (pinfunction "A7_9") (pintype "bidirectional"))
      (node (ref "R88") (pin "1") (pinfunction "P$1_1") (pintype "bidirectional"))
      (node (ref "U2") (pin "N11") (pinfunction "IO_L13P_M1_2_N11") (pintype "bidirectional"))
    )
    (net (code "139") (name "LAD15") (class "Default")
      (node (ref "IC9") (pin "10") (pinfunction "A8_10") (pintype "bidirectional"))
      (node (ref "U2") (pin "P12") (pinfunction "IO_L12N_D2_MISO3_2_P12") (pintype "bidirectional"))
    )
    (net (code "140") (name "LADVREF") (class "Default")
      (node (ref "C167") (pin "1") (pinfunction "1_1") (pintype "passive"))
      (node (ref "R169") (pin "2") (pinfunction "P$2_2") (pintype "bidirectional"))
      (node (ref "U2") (pin "M10") (pinfunction "IO_L16N_VREF_2_M10") (pintype "bidirectional"))
      (node (ref "U2") (pin "T5") (pinfunction "IO_L48N_RDWR_B_VREF_2_T5") (pintype "bidirectional"))
    )
    (net (code "141") (name "LAVIO") (class "Default")
      (node (ref "C185") (pin "1") (pinfunction "1_1") (pintype "passive"))
      (node (ref "C77") (pin "2") (pinfunction "2_2") (pintype "passive"))
      (node (ref "IC9") (pin "23") (pinfunction "VCCB_23") (pintype "power_in"))
      (node (ref "IC9") (pin "24") (pinfunction "VCCB_24") (pintype "power_in"))
      (node (ref "R186") (pin "2") (pinfunction "P$2_2") (pintype "bidirectional"))
    )
    (net (code "142") (name "LDM") (class "Default")
      (node (ref "IC26") (pin "B7") (pinfunction "DM_TDQS_B7") (pintype "output"))
      (node (ref "U2") (pin "J4") (pinfunction "IO_L42N_GCLK24_M3LDM_3_J4") (pintype "bidirectional"))
    )
    (net (code "143") (name "LDQS") (class "Default")
      (node (ref "IC26") (pin "C3") (pinfunction "DQS_C3") (pintype "bidirectional"))
      (node (ref "U2") (pin "H2") (pinfunction "IO_L39P_M3LDQS_3_H2") (pintype "bidirectional"))
    )
    (net (code "144") (name "LDQSN") (class "Default")
      (node (ref "IC26") (pin "D3") (pinfunction "DQS#_D3") (pintype "bidirectional"))
      (node (ref "U2") (pin "H1") (pinfunction "IO_L39N_M3LDQSN_3_H1") (pintype "bidirectional"))
    )
    (net (code "145") (name "LOGICOFFSET") (class "Default")
      (node (ref "C199") (pin "2") (pinfunction "2_2") (pintype "passive"))
      (node (ref "IC31") (pin "7") (pinfunction "OUT_7") (pintype "output"))
      (node (ref "R124") (pin "1") (pinfunction "P$1_1") (pintype "bidirectional"))
      (node (ref "R125") (pin "1") (pinfunction "P$1_1") (pintype "bidirectional"))
      (node (ref "R126") (pin "1") (pinfunction "P$1_1") (pintype "bidirectional"))
      (node (ref "R127") (pin "1") (pinfunction "P$1_1") (pintype "bidirectional"))
      (node (ref "R128") (pin "1") (pinfunction "P$1_1") (pintype "bidirectional"))
      (node (ref "R129") (pin "1") (pinfunction "P$1_1") (pintype "bidirectional"))
      (node (ref "R130") (pin "1") (pinfunction "P$1_1") (pintype "bidirectional"))
      (node (ref "R131") (pin "1") (pinfunction "P$1_1") (pintype "bidirectional"))
      (node (ref "R198") (pin "1") (pinfunction "P$1_1") (pintype "bidirectional"))
    )
    (net (code "146") (name "MOSI") (class "Default")
      (node (ref "IC2") (pin "5") (pinfunction "SI_5") (pintype "input"))
      (node (ref "U2") (pin "T10") (pinfunction "IO_L3N_MOSI_CSI_B_MISO0_2_T10") (pintype "bidirectional"))
    )
    (net (code "147") (name "MSTCLK") (class "Default")
      (node (ref "R45") (pin "1") (pinfunction "P$1_1") (pintype "bidirectional"))
      (node (ref "U2") (pin "B10") (pinfunction "IO_L35P_GCLK17_0_B10") (pintype "bidirectional"))
    )
    (net (code "148") (name "Net-(C39-Pad1)") (class "Default")
      (node (ref "C39") (pin "1") (pinfunction "1_1") (pintype "passive"))
      (node (ref "L2") (pin "2") (pinfunction "2_2") (pintype "passive"))
      (node (ref "L6") (pin "2") (pinfunction "2_2") (pintype "passive"))
      (node (ref "X1") (pin "1") (pinfunction "1_1") (pintype "passive"))
    )
    (net (code "149") (name "Net-(C213-E)") (class "Default")
      (node (ref "C213") (pin "1") (pinfunction "E_1") (pintype "passive"))
      (node (ref "C223") (pin "1") (pinfunction "1_1") (pintype "passive"))
    )
    (net (code "150") (name "Net-(C216-E)") (class "Default")
      (node (ref "C216") (pin "1") (pinfunction "E_1") (pintype "passive"))
      (node (ref "C222") (pin "1") (pinfunction "1_1") (pintype "passive"))
    )
    (net (code "151") (name "Net-(C238-E)") (class "Default")
      (node (ref "C238") (pin "1") (pinfunction "E_1") (pintype "passive"))
      (node (ref "C248") (pin "1") (pinfunction "1_1") (pintype "passive"))
    )
    (net (code "152") (name "Net-(C241-E)") (class "Default")
      (node (ref "C241") (pin "1") (pinfunction "E_1") (pintype "passive"))
      (node (ref "C247") (pin "1") (pinfunction "1_1") (pintype "passive"))
    )
    (net (code "153") (name "Net-(IC1-FB)") (class "Default")
      (node (ref "C1") (pin "1") (pinfunction "1_1") (pintype "passive"))
      (node (ref "IC1") (pin "4") (pinfunction "FB_4") (pintype "bidirectional"))
      (node (ref "R107") (pin "1") (pinfunction "P$1_1") (pintype "bidirectional"))
      (node (ref "R112") (pin "2") (pinfunction "P$2_2") (pintype "bidirectional"))
    )
    (net (code "154") (name "Net-(IC1-SW)") (class "Default")
      (node (ref "IC1") (pin "5") (pinfunction "SW_5") (pintype "bidirectional"))
      (node (ref "L13") (pin "1") (pinfunction "1_1") (pintype "passive"))
    )
    (net (code "155") (name "Net-(IC2-SO)") (class "Default")
      (node (ref "IC2") (pin "2") (pinfunction "SO_2") (pintype "bidirectional"))
      (node (ref "R5") (pin "2") (pinfunction "P$2_2") (pintype "bidirectional"))
    )
    (net (code "156") (name "Net-(IC3-A6)") (class "Default")
      (node (ref "IC3") (pin "7") (pinfunction "A6_7") (pintype "output"))
      (node (ref "R44") (pin "1") (pinfunction "P$1_1") (pintype "bidirectional"))
    )
    (net (code "157") (name "Net-(IC3-B1)") (class "Default")
      (node (ref "IC3") (pin "15") (pinfunction "B1_15") (pintype "output"))
      (node (ref "U2") (pin "A10") (pinfunction "IO_L35N_GCLK16_0_A10") (pintype "bidirectional"))
    )
    (net (code "158") (name "Net-(IC3-B2)") (class "Default")
      (node (ref "IC3") (pin "14") (pinfunction "B2_14") (pintype "output"))
      (node (ref "R41") (pin "2") (pinfunction "P$2_2") (pintype "bidirectional"))
    )
    (net (code "159") (name "Net-(IC3-B3)") (class "Default")
      (node (ref "IC3") (pin "13") (pinfunction "B3_13") (pintype "output"))
      (node (ref "R42") (pin "2") (pinfunction "P$2_2") (pintype "bidirectional"))
    )
    (net (code "160") (name "Net-(IC3-B4)") (class "Default")
      (node (ref "IC3") (pin "12") (pinfunction "B4_12") (pintype "output"))
      (node (ref "R43") (pin "2") (pinfunction "P$2_2") (pintype "bidirectional"))
    )
    (net (code "161") (name "Net-(IC3-B5)") (class "Default")
      (node (ref "IC3") (pin "11") (pinfunction "B5_11") (pintype "input"))
      (node (ref "U2") (pin "A8") (pinfunction "IO_L33N_0_A8") (pintype "bidirectional"))
    )
    (net (code "162") (name "Net-(IC3-B6)") (class "Default")
      (node (ref "IC3") (pin "10") (pinfunction "B6_10") (pintype "input"))
      (node (ref "U2") (pin "A7") (pinfunction "IO_L6N_0_A7") (pintype "bidirectional"))
    )
    (net (code "163") (name "Net-(IC4-AD0{slash}TXD{slash}TCK{slash}FSDI)") (class "Default")
      (node (ref "IC4") (pin "13") (pinfunction "AD0/TXD/TCK/FSDI_13") (pintype "bidirectional"))
      (node (ref "R38") (pin "2") (pinfunction "P$2_2") (pintype "bidirectional"))
    )
    (net (code "164") (name "Net-(IC4-AD1{slash}RXD{slash}TDI{slash}FSCLK)") (class "Default")
      (node (ref "IC4") (pin "14") (pinfunction "AD1/RXD/TDI/FSCLK_14") (pintype "bidirectional"))
      (node (ref "R39") (pin "2") (pinfunction "P$2_2") (pintype "bidirectional"))
    )
    (net (code "165") (name "Net-(IC4-AD3{slash}CTS#{slash}TMS{slash}FSCTS)") (class "Default")
      (node (ref "IC4") (pin "16") (pinfunction "AD3/CTS#/TMS/FSCTS_16") (pintype "bidirectional"))
      (node (ref "R40") (pin "2") (pinfunction "P$2_2") (pintype "bidirectional"))
    )
    (net (code "166") (name "Net-(IC4-DM)") (class "Default")
      (node (ref "IC4") (pin "6") (pinfunction "DM_6") (pintype "bidirectional"))
      (node (ref "R14") (pin "2") (pinfunction "P$2_2") (pintype "bidirectional"))
    )
    (net (code "167") (name "Net-(IC4-DP)") (class "Default")
      (node (ref "IC4") (pin "7") (pinfunction "DP_7") (pintype "bidirectional"))
      (node (ref "R15") (pin "1") (pinfunction "P$1_1") (pintype "bidirectional"))
    )
    (net (code "168") (name "Net-(IC4-EECLK)") (class "Default")
      (node (ref "IC4") (pin "44") (pinfunction "EECLK_44") (pintype "bidirectional"))
      (node (ref "IC8") (pin "2") (pinfunction "CLK_2") (pintype "input"))
      (node (ref "R20") (pin "1") (pinfunction "P$1_1") (pintype "bidirectional"))
    )
    (net (code "169") (name "Net-(IC4-EECS)") (class "Default")
      (node (ref "IC4") (pin "45") (pinfunction "EECS_45") (pintype "bidirectional"))
      (node (ref "IC8") (pin "1") (pinfunction "CS_1") (pintype "input"))
      (node (ref "R21") (pin "1") (pinfunction "P$1_1") (pintype "bidirectional"))
    )
    (net (code "170") (name "Net-(IC4-EEDATA)") (class "Default")
      (node (ref "IC4") (pin "43") (pinfunction "EEDATA_43") (pintype "bidirectional"))
      (node (ref "IC8") (pin "3") (pinfunction "DI_3") (pintype "input"))
      (node (ref "R18") (pin "1") (pinfunction "P$1_1") (pintype "bidirectional"))
    )
    (net (code "171") (name "Net-(IC4-REF)") (class "Default")
      (node (ref "IC4") (pin "5") (pinfunction "REF_5") (pintype "bidirectional"))
      (node (ref "R17") (pin "2") (pinfunction "P$2_2") (pintype "bidirectional"))
    )
    (net (code "172") (name "Net-(IC4-VCCA)") (class "Default")
      (node (ref "C41") (pin "1") (pinfunction "1_1") (pintype "passive"))
      (node (ref "IC4") (pin "37") (pinfunction "VCCA_37") (pintype "bidirectional"))
    )
    (net (code "173") (name "Net-(IC4-VCCCORE)") (class "Default")
      (node (ref "C40") (pin "1") (pinfunction "1_1") (pintype "passive"))
      (node (ref "IC4") (pin "38") (pinfunction "VCCCORE_38") (pintype "bidirectional"))
    )
    (net (code "174") (name "Net-(IC4-VPHY)") (class "Default")
      (node (ref "C48") (pin "1") (pinfunction "1_1") (pintype "passive"))
      (node (ref "C49") (pin "1") (pinfunction "1_1") (pintype "passive"))
      (node (ref "IC4") (pin "3") (pinfunction "VPHY_3") (pintype "power_in"))
      (node (ref "L3") (pin "1") (pinfunction "1_1") (pintype "passive"))
    )
    (net (code "175") (name "Net-(IC4-VPLL)") (class "Default")
      (node (ref "C46") (pin "1") (pinfunction "1_1") (pintype "passive"))
      (node (ref "C47") (pin "1") (pinfunction "1_1") (pintype "passive"))
      (node (ref "IC4") (pin "8") (pinfunction "VPLL_8") (pintype "power_in"))
      (node (ref "L1") (pin "1") (pinfunction "1_1") (pintype "passive"))
    )
    (net (code "176") (name "Net-(IC4-VREGIN)") (class "Default")
      (node (ref "C42") (pin "2") (pinfunction "2_2") (pintype "passive"))
      (node (ref "C43") (pin "2") (pinfunction "2_2") (pintype "passive"))
      (node (ref "IC4") (pin "40") (pinfunction "VREGIN_40") (pintype "power_in"))
      (node (ref "L2") (pin "1") (pinfunction "1_1") (pintype "passive"))
    )
    (net (code "177") (name "Net-(IC4-XCSI)") (class "Default")
      (node (ref "C55") (pin "2") (pinfunction "2_2") (pintype "passive"))
      (node (ref "IC4") (pin "1") (pinfunction "XCSI_1") (pintype "bidirectional"))
      (node (ref "Q1") (pin "2") (pinfunction "2_2") (pintype "passive"))
    )
    (net (code "178") (name "Net-(IC4-XCSO)") (class "Default")
      (node (ref "C56") (pin "2") (pinfunction "2_2") (pintype "passive"))
      (node (ref "IC4") (pin "2") (pinfunction "XCSO_2") (pintype "bidirectional"))
      (node (ref "Q1") (pin "1") (pinfunction "1_1") (pintype "passive"))
    )
    (net (code "179") (name "Net-(IC4-~{RESET})") (class "Default")
      (node (ref "C53") (pin "1") (pinfunction "1_1") (pintype "passive"))
      (node (ref "IC4") (pin "34") (pinfunction "~{RESET}_34") (pintype "bidirectional"))
      (node (ref "R16") (pin "1") (pinfunction "P$1_1") (pintype "bidirectional"))
    )
    (net (code "180") (name "Net-(IC5-D0)") (class "Default")
      (node (ref "IC5") (pin "22") (pinfunction "D0_22") (pintype "output"))
      (node (ref "R29") (pin "1") (pinfunction "P$1_1") (pintype "bidirectional"))
    )
    (net (code "181") (name "Net-(IC5-D1)") (class "Default")
      (node (ref "IC5") (pin "21") (pinfunction "D1_21") (pintype "output"))
      (node (ref "R28") (pin "1") (pinfunction "P$1_1") (pintype "bidirectional"))
    )
    (net (code "182") (name "Net-(IC5-D2)") (class "Default")
      (node (ref "IC5") (pin "20") (pinfunction "D2_20") (pintype "output"))
      (node (ref "R27") (pin "1") (pinfunction "P$1_1") (pintype "bidirectional"))
    )
    (net (code "183") (name "Net-(IC5-D3)") (class "Default")
      (node (ref "IC5") (pin "19") (pinfunction "D3_19") (pintype "output"))
      (node (ref "R26") (pin "1") (pinfunction "P$1_1") (pintype "bidirectional"))
    )
    (net (code "184") (name "Net-(IC5-D4)") (class "Default")
      (node (ref "IC5") (pin "16") (pinfunction "D4_16") (pintype "output"))
      (node (ref "R25") (pin "1") (pinfunction "P$1_1") (pintype "bidirectional"))
    )
    (net (code "185") (name "Net-(IC5-D5)") (class "Default")
      (node (ref "IC5") (pin "15") (pinfunction "D5_15") (pintype "output"))
      (node (ref "R24") (pin "1") (pinfunction "P$1_1") (pintype "bidirectional"))
    )
    (net (code "186") (name "Net-(IC5-D6)") (class "Default")
      (node (ref "IC5") (pin "14") (pinfunction "D6_14") (pintype "output"))
      (node (ref "R23") (pin "1") (pinfunction "P$1_1") (pintype "bidirectional"))
    )
    (net (code "187") (name "Net-(IC5-D7)") (class "Default")
      (node (ref "IC5") (pin "13") (pinfunction "D7_13") (pintype "output"))
      (node (ref "R22") (pin "1") (pinfunction "P$1_1") (pintype "bidirectional"))
    )
    (net (code "188") (name "Net-(IC5-DRVD)") (class "Default")
      (node (ref "C57") (pin "1") (pinfunction "1_1") (pintype "passive"))
      (node (ref "C58") (pin "1") (pinfunction "1_1") (pintype "passive"))
      (node (ref "IC5") (pin "18") (pinfunction "DRVD_18") (pintype "power_in"))
      (node (ref "L4") (pin "2") (pinfunction "2_2") (pintype "passive"))
    )
    (net (code "189") (name "Net-(IC5-VRB)") (class "Default")
      (node (ref "C111") (pin "1") (pinfunction "1_1") (pintype "passive"))
      (node (ref "IC5") (pin "10") (pinfunction "VRB_10") (pintype "bidirectional"))
      (node (ref "L10") (pin "2") (pinfunction "2_2") (pintype "passive"))
    )
    (net (code "190") (name "Net-(IC5-VRM)") (class "Default")
      (node (ref "C110") (pin "1") (pinfunction "1_1") (pintype "passive"))
      (node (ref "IC5") (pin "9") (pinfunction "VRM_9") (pintype "bidirectional"))
    )
    (net (code "191") (name "Net-(IC5-VRT)") (class "Default")
      (node (ref "C109") (pin "1") (pinfunction "1_1") (pintype "passive"))
      (node (ref "IC5") (pin "3") (pinfunction "VRT_3") (pintype "bidirectional"))
      (node (ref "L11") (pin "2") (pinfunction "2_2") (pintype "passive"))
    )
    (net (code "192") (name "Net-(IC6-D0)") (class "Default")
      (node (ref "IC6") (pin "22") (pinfunction "D0_22") (pintype "output"))
      (node (ref "R37") (pin "1") (pinfunction "P$1_1") (pintype "bidirectional"))
    )
    (net (code "193") (name "Net-(IC6-D1)") (class "Default")
      (node (ref "IC6") (pin "21") (pinfunction "D1_21") (pintype "output"))
      (node (ref "R36") (pin "1") (pinfunction "P$1_1") (pintype "bidirectional"))
    )
    (net (code "194") (name "Net-(IC6-D2)") (class "Default")
      (node (ref "IC6") (pin "20") (pinfunction "D2_20") (pintype "output"))
      (node (ref "R35") (pin "1") (pinfunction "P$1_1") (pintype "bidirectional"))
    )
    (net (code "195") (name "Net-(IC6-D3)") (class "Default")
      (node (ref "IC6") (pin "19") (pinfunction "D3_19") (pintype "output"))
      (node (ref "R34") (pin "1") (pinfunction "P$1_1") (pintype "bidirectional"))
    )
    (net (code "196") (name "Net-(IC6-D4)") (class "Default")
      (node (ref "IC6") (pin "16") (pinfunction "D4_16") (pintype "output"))
      (node (ref "R33") (pin "1") (pinfunction "P$1_1") (pintype "bidirectional"))
    )
    (net (code "197") (name "Net-(IC6-D5)") (class "Default")
      (node (ref "IC6") (pin "15") (pinfunction "D5_15") (pintype "output"))
      (node (ref "R32") (pin "1") (pinfunction "P$1_1") (pintype "bidirectional"))
    )
    (net (code "198") (name "Net-(IC6-D6)") (class "Default")
      (node (ref "IC6") (pin "14") (pinfunction "D6_14") (pintype "output"))
      (node (ref "R31") (pin "1") (pinfunction "P$1_1") (pintype "bidirectional"))
    )
    (net (code "199") (name "Net-(IC6-D7)") (class "Default")
      (node (ref "IC6") (pin "13") (pinfunction "D7_13") (pintype "output"))
      (node (ref "R30") (pin "1") (pinfunction "P$1_1") (pintype "bidirectional"))
    )
    (net (code "200") (name "Net-(IC6-DRVD)") (class "Default")
      (node (ref "C59") (pin "1") (pinfunction "1_1") (pintype "passive"))
      (node (ref "C60") (pin "1") (pinfunction "1_1") (pintype "passive"))
      (node (ref "IC6") (pin "18") (pinfunction "DRVD_18") (pintype "power_in"))
      (node (ref "L5") (pin "2") (pinfunction "2_2") (pintype "passive"))
    )
    (net (code "201") (name "Net-(IC6-VRB)") (class "Default")
      (node (ref "C108") (pin "1") (pinfunction "1_1") (pintype "passive"))
      (node (ref "IC6") (pin "10") (pinfunction "VRB_10") (pintype "bidirectional"))
      (node (ref "L9") (pin "2") (pinfunction "2_2") (pintype "passive"))
    )
    (net (code "202") (name "Net-(IC6-VRM)") (class "Default")
      (node (ref "C107") (pin "1") (pinfunction "1_1") (pintype "passive"))
      (node (ref "IC6") (pin "9") (pinfunction "VRM_9") (pintype "bidirectional"))
    )
    (net (code "203") (name "Net-(IC6-VRT)") (class "Default")
      (node (ref "C106") (pin "1") (pinfunction "1_1") (pintype "passive"))
      (node (ref "IC6") (pin "3") (pinfunction "VRT_3") (pintype "bidirectional"))
      (node (ref "L8") (pin "2") (pinfunction "2_2") (pintype "passive"))
    )
    (net (code "204") (name "Net-(IC7-EN)") (class "Default")
      (node (ref "C94") (pin "2") (pinfunction "2_2") (pintype "passive"))
      (node (ref "IC7") (pin "1") (pinfunction "IN_1") (pintype "power_in"))
      (node (ref "IC7") (pin "3") (pinfunction "EN_3") (pintype "input"))
      (node (ref "R179") (pin "1") (pinfunction "P$1_1") (pintype "bidirectional"))
    )
    (net (code "205") (name "Net-(IC7-FB)") (class "Default")
      (node (ref "C95") (pin "1") (pinfunction "1_1") (pintype "passive"))
      (node (ref "IC7") (pin "5") (pinfunction "FB_5") (pintype "input"))
      (node (ref "R54") (pin "1") (pinfunction "P$1_1") (pintype "bidirectional"))
      (node (ref "R55") (pin "2") (pinfunction "P$2_2") (pintype "bidirectional"))
    )
    (net (code "206") (name "Net-(IC7-NR)") (class "Default")
      (node (ref "C91") (pin "2") (pinfunction "2_2") (pintype "passive"))
      (node (ref "IC7") (pin "4") (pinfunction "NR_4") (pintype "input"))
    )
    (net (code "207") (name "Net-(IC7-OUT)") (class "Default")
      (node (ref "C27") (pin "2") (pinfunction "2_2") (pintype "passive"))
      (node (ref "C95") (pin "2") (pinfunction "2_2") (pintype "passive"))
      (node (ref "IC7") (pin "6") (pinfunction "OUT_6") (pintype "power_in"))
      (node (ref "R180") (pin "2") (pinfunction "P$2_2") (pintype "bidirectional"))
      (node (ref "R54") (pin "2") (pinfunction "P$2_2") (pintype "bidirectional"))
    )
    (net (code "208") (name "Net-(IC8-DO)") (class "Default")
      (node (ref "IC8") (pin "4") (pinfunction "DO_4") (pintype "tri_state"))
      (node (ref "R18") (pin "2") (pinfunction "P$2_2") (pintype "bidirectional"))
      (node (ref "R19") (pin "1") (pinfunction "P$1_1") (pintype "bidirectional"))
    )
    (net (code "209") (name "Net-(IC9-B1)") (class "Default")
      (node (ref "IC9") (pin "21") (pinfunction "B1_21") (pintype "bidirectional"))
      (node (ref "R97") (pin "1") (pinfunction "P$1_1") (pintype "bidirectional"))
    )
    (net (code "210") (name "Net-(IC9-B2)") (class "Default")
      (node (ref "IC9") (pin "20") (pinfunction "B2_20") (pintype "bidirectional"))
      (node (ref "R98") (pin "1") (pinfunction "P$1_1") (pintype "bidirectional"))
    )
    (net (code "211") (name "Net-(IC9-B3)") (class "Default")
      (node (ref "IC9") (pin "19") (pinfunction "B3_19") (pintype "bidirectional"))
      (node (ref "R99") (pin "1") (pinfunction "P$1_1") (pintype "bidirectional"))
    )
    (net (code "212") (name "Net-(IC9-B4)") (class "Default")
      (node (ref "IC9") (pin "18") (pinfunction "B4_18") (pintype "bidirectional"))
      (node (ref "R100") (pin "1") (pinfunction "P$1_1") (pintype "bidirectional"))
    )
    (net (code "213") (name "Net-(IC9-B5)") (class "Default")
      (node (ref "IC9") (pin "17") (pinfunction "B5_17") (pintype "bidirectional"))
      (node (ref "R101") (pin "1") (pinfunction "P$1_1") (pintype "bidirectional"))
    )
    (net (code "214") (name "Net-(IC9-B6)") (class "Default")
      (node (ref "IC9") (pin "16") (pinfunction "B6_16") (pintype "bidirectional"))
      (node (ref "R102") (pin "1") (pinfunction "P$1_1") (pintype "bidirectional"))
    )
    (net (code "215") (name "Net-(IC9-B7)") (class "Default")
      (node (ref "IC9") (pin "15") (pinfunction "B7_15") (pintype "bidirectional"))
      (node (ref "R103") (pin "1") (pinfunction "P$1_1") (pintype "bidirectional"))
    )
    (net (code "216") (name "Net-(IC9-B8)") (class "Default")
      (node (ref "IC9") (pin "14") (pinfunction "B8_14") (pintype "bidirectional"))
      (node (ref "R79") (pin "1") (pinfunction "P$1_1") (pintype "bidirectional"))
    )
    (net (code "217") (name "Net-(IC10-FB)") (class "Default")
      (node (ref "C78") (pin "1") (pinfunction "1_1") (pintype "passive"))
      (node (ref "IC10") (pin "4") (pinfunction "FB_4") (pintype "bidirectional"))
      (node (ref "R46") (pin "1") (pinfunction "P$1_1") (pintype "bidirectional"))
      (node (ref "R47") (pin "2") (pinfunction "P$2_2") (pintype "bidirectional"))
    )
    (net (code "218") (name "Net-(IC10-SW)") (class "Default")
      (node (ref "IC10") (pin "5") (pinfunction "SW_5") (pintype "bidirectional"))
      (node (ref "L7") (pin "1") (pinfunction "1_1") (pintype "passive"))
    )
    (net (code "219") (name "Net-(IC11-FB)") (class "Default")
      (node (ref "C85") (pin "1") (pinfunction "1_1") (pintype "passive"))
      (node (ref "IC11") (pin "5") (pinfunction "FB_5") (pintype "input"))
      (node (ref "R163") (pin "1") (pinfunction "P$1_1") (pintype "bidirectional"))
      (node (ref "R164") (pin "2") (pinfunction "P$2_2") (pintype "bidirectional"))
    )
    (net (code "220") (name "Net-(IC11-NR)") (class "Default")
      (node (ref "C83") (pin "2") (pinfunction "2_2") (pintype "passive"))
      (node (ref "IC11") (pin "4") (pinfunction "NR_4") (pintype "input"))
    )
    (net (code "221") (name "Net-(IC11-OUT)") (class "Default")
      (node (ref "C81") (pin "2") (pinfunction "2_2") (pintype "passive"))
      (node (ref "C85") (pin "2") (pinfunction "2_2") (pintype "passive"))
      (node (ref "IC11") (pin "6") (pinfunction "OUT_6") (pintype "power_in"))
      (node (ref "R163") (pin "2") (pinfunction "P$2_2") (pintype "bidirectional"))
      (node (ref "R165") (pin "1") (pinfunction "P$1_1") (pintype "bidirectional"))
    )
    (net (code "222") (name "Net-(IC12-FB)") (class "Default")
      (node (ref "C163") (pin "1") (pinfunction "1_1") (pintype "passive"))
      (node (ref "IC12") (pin "5") (pinfunction "FB_5") (pintype "input"))
      (node (ref "R166") (pin "1") (pinfunction "P$1_1") (pintype "bidirectional"))
      (node (ref "R167") (pin "2") (pinfunction "P$2_2") (pintype "bidirectional"))
    )
    (net (code "223") (name "Net-(IC12-NR)") (class "Default")
      (node (ref "C87") (pin "2") (pinfunction "2_2") (pintype "passive"))
      (node (ref "IC12") (pin "4") (pinfunction "NR_4") (pintype "input"))
    )
    (net (code "224") (name "Net-(IC12-OUT)") (class "Default")
      (node (ref "C163") (pin "2") (pinfunction "2_2") (pintype "passive"))
      (node (ref "C86") (pin "2") (pinfunction "2_2") (pintype "passive"))
      (node (ref "IC12") (pin "6") (pinfunction "OUT_6") (pintype "power_in"))
      (node (ref "R166") (pin "2") (pinfunction "P$2_2") (pintype "bidirectional"))
      (node (ref "R168") (pin "1") (pinfunction "P$1_1") (pintype "bidirectional"))
    )
    (net (code "225") (name "Net-(IC13-AINL+)") (class "Default")
      (node (ref "C127") (pin "2") (pinfunction "2_2") (pintype "passive"))
      (node (ref "IC13") (pin "4") (pinfunction "AINL+_4") (pintype "input"))
      (node (ref "R140") (pin "1") (pinfunction "P$1_1") (pintype "bidirectional"))
    )
    (net (code "226") (name "Net-(IC13-AINL-)") (class "Default")
      (node (ref "C127") (pin "1") (pinfunction "1_1") (pintype "passive"))
      (node (ref "IC13") (pin "5") (pinfunction "AINL-_5") (pintype "input"))
      (node (ref "R139") (pin "2") (pinfunction "P$2_2") (pintype "bidirectional"))
    )
    (net (code "227") (name "Net-(IC13-AINR+)") (class "Default")
      (node (ref "C128") (pin "2") (pinfunction "2_2") (pintype "passive"))
      (node (ref "IC13") (pin "2") (pinfunction "AINR+_2") (pintype "input"))
      (node (ref "R141") (pin "1") (pinfunction "P$1_1") (pintype "bidirectional"))
    )
    (net (code "228") (name "Net-(IC13-AINR-)") (class "Default")
      (node (ref "C128") (pin "1") (pinfunction "1_1") (pintype "passive"))
      (node (ref "IC13") (pin "3") (pinfunction "AINR-_3") (pintype "input"))
      (node (ref "R142") (pin "2") (pinfunction "P$2_2") (pintype "bidirectional"))
    )
    (net (code "229") (name "Net-(IC13-AOUTL+)") (class "Default")
      (node (ref "C136") (pin "1") (pinfunction "1_1") (pintype "passive"))
      (node (ref "IC13") (pin "28") (pinfunction "AOUTL+_28") (pintype "output"))
    )
    (net (code "230") (name "Net-(IC13-AOUTL-)") (class "Default")
      (node (ref "C135") (pin "1") (pinfunction "1_1") (pintype "passive"))
      (node (ref "IC13") (pin "27") (pinfunction "AOUTL-_27") (pintype "output"))
    )
    (net (code "231") (name "Net-(IC13-AOUTR+)") (class "Default")
      (node (ref "C113") (pin "1") (pinfunction "1_1") (pintype "passive"))
      (node (ref "IC13") (pin "30") (pinfunction "AOUTR+_30") (pintype "output"))
    )
    (net (code "232") (name "Net-(IC13-AOUTR-)") (class "Default")
      (node (ref "C103") (pin "1") (pinfunction "1_1") (pintype "passive"))
      (node (ref "IC13") (pin "29") (pinfunction "AOUTR-_29") (pintype "output"))
    )
    (net (code "233") (name "Net-(IC13-SDTO)") (class "Default")
      (node (ref "IC13") (pin "13") (pinfunction "SDTO_13") (pintype "bidirectional"))
      (node (ref "R90") (pin "2") (pinfunction "P$2_2") (pintype "bidirectional"))
    )
    (net (code "234") (name "Net-(IC13-VCOM)") (class "Default")
      (node (ref "C118") (pin "2") (pinfunction "2_2") (pintype "passive"))
      (node (ref "C120") (pin "2") (pinfunction "2_2") (pintype "passive"))
      (node (ref "IC13") (pin "1") (pinfunction "VCOM_1") (pintype "passive"))
    )
    (net (code "235") (name "Net-(IC14-EN)") (class "Default")
      (node (ref "C168") (pin "1") (pinfunction "1_1") (pintype "passive"))
      (node (ref "C92") (pin "1") (pinfunction "1_1") (pintype "passive"))
      (node (ref "IC14") (pin "2") (pinfunction "IN_2") (pintype "power_in"))
      (node (ref "IC14") (pin "3") (pinfunction "EN_3") (pintype "input"))
      (node (ref "IC28") (pin "2") (pinfunction "IN_2") (pintype "power_in"))
      (node (ref "IC28") (pin "3") (pinfunction "EN_3") (pintype "input"))
      (node (ref "R172") (pin "2") (pinfunction "P$2_2") (pintype "bidirectional"))
    )
    (net (code "236") (name "Net-(IC14-FB)") (class "Default")
      (node (ref "IC14") (pin "4") (pinfunction "FB_4") (pintype "input"))
      (node (ref "R52") (pin "1") (pinfunction "P$1_1") (pintype "bidirectional"))
      (node (ref "R53") (pin "2") (pinfunction "P$2_2") (pintype "bidirectional"))
    )
    (net (code "237") (name "Net-(IC14-OUT)") (class "Default")
      (node (ref "C93") (pin "1") (pinfunction "1_1") (pintype "passive"))
      (node (ref "IC14") (pin "5") (pinfunction "OUT_5") (pintype "power_in"))
      (node (ref "R174") (pin "1") (pinfunction "P$1_1") (pintype "bidirectional"))
      (node (ref "R52") (pin "2") (pinfunction "P$2_2") (pintype "bidirectional"))
    )
    (net (code "238") (name "Net-(IC15A--IN)") (class "Default")
      (node (ref "C122") (pin "1") (pinfunction "1_1") (pintype "passive"))
      (node (ref "IC15") (pin "2") (pinfunction "-IN_2") (pintype "input"))
      (node (ref "R134") (pin "1") (pinfunction "P$1_1") (pintype "bidirectional"))
      (node (ref "R137") (pin "2") (pinfunction "P$2_2") (pintype "bidirectional"))
    )
    (net (code "239") (name "Net-(IC15A-OUT)") (class "Default")
      (node (ref "C122") (pin "2") (pinfunction "2_2") (pintype "passive"))
      (node (ref "IC15") (pin "1") (pinfunction "OUT_1") (pintype "output"))
      (node (ref "R134") (pin "2") (pinfunction "P$2_2") (pintype "bidirectional"))
      (node (ref "R139") (pin "1") (pinfunction "P$1_1") (pintype "bidirectional"))
    )
    (net (code "240") (name "Net-(IC15B--IN)") (class "Default")
      (node (ref "C123") (pin "1") (pinfunction "1_1") (pintype "passive"))
      (node (ref "IC15") (pin "6") (pinfunction "-IN_6") (pintype "input"))
      (node (ref "R133") (pin "1") (pinfunction "P$1_1") (pintype "bidirectional"))
      (node (ref "R136") (pin "2") (pinfunction "P$2_2") (pintype "bidirectional"))
    )
    (net (code "241") (name "Net-(IC15B-OUT)") (class "Default")
      (node (ref "C123") (pin "2") (pinfunction "2_2") (pintype "passive"))
      (node (ref "IC15") (pin "7") (pinfunction "OUT_7") (pintype "output"))
      (node (ref "R133") (pin "2") (pinfunction "P$2_2") (pintype "bidirectional"))
      (node (ref "R140") (pin "2") (pinfunction "P$2_2") (pintype "bidirectional"))
    )
    (net (code "242") (name "Net-(IC16A--IN)") (class "Default")
      (node (ref "IC16") (pin "2") (pinfunction "-IN_2") (pintype "input"))
      (node (ref "R145") (pin "2") (pinfunction "P$2_2") (pintype "bidirectional"))
      (node (ref "R147") (pin "1") (pinfunction "P$1_1") (pintype "bidirectional"))
    )
    (net (code "243") (name "Net-(IC16A-OUT)") (class "Default")
      (node (ref "C129") (pin "1") (pinfunction "1_1") (pintype "passive"))
      (node (ref "IC16") (pin "1") (pinfunction "OUT_1") (pintype "output"))
      (node (ref "R145") (pin "1") (pinfunction "P$1_1") (pintype "bidirectional"))
    )
    (net (code "244") (name "Net-(IC16B--IN)") (class "Default")
      (node (ref "IC16") (pin "6") (pinfunction "-IN_6") (pintype "input"))
      (node (ref "R148") (pin "2") (pinfunction "P$2_2") (pintype "bidirectional"))
      (node (ref "R149") (pin "1") (pinfunction "P$1_1") (pintype "bidirectional"))
    )
    (net (code "245") (name "Net-(IC16B-OUT)") (class "Default")
      (node (ref "C131") (pin "1") (pinfunction "1_1") (pintype "passive"))
      (node (ref "IC16") (pin "7") (pinfunction "OUT_7") (pintype "output"))
      (node (ref "R148") (pin "1") (pinfunction "P$1_1") (pintype "bidirectional"))
    )
    (net (code "246") (name "Net-(IC17A-+IN)") (class "Default")
      (node (ref "IC17") (pin "3") (pinfunction "+IN_3") (pintype "input"))
      (node (ref "IC20") (pin "2") (pinfunction "L_2") (pintype "bidirectional"))
      (node (ref "R146") (pin "2") (pinfunction "P$2_2") (pintype "bidirectional"))
    )
    (net (code "247") (name "Net-(IC17B-+IN)") (class "Default")
      (node (ref "IC17") (pin "5") (pinfunction "+IN_5") (pintype "input"))
      (node (ref "IC20") (pin "3") (pinfunction "R_3") (pintype "bidirectional"))
      (node (ref "R150") (pin "2") (pinfunction "P$2_2") (pintype "bidirectional"))
    )
    (net (code "248") (name "Net-(IC18A--IN)") (class "Default")
      (node (ref "C178") (pin "2") (pinfunction "2_2") (pintype "passive"))
      (node (ref "IC18") (pin "2") (pinfunction "-IN_2") (pintype "input"))
      (node (ref "R61") (pin "2") (pinfunction "P$2_2") (pintype "bidirectional"))
      (node (ref "R62") (pin "1") (pinfunction "P$1_1") (pintype "bidirectional"))
    )
    (net (code "249") (name "Net-(IC18A-OUT)") (class "Default")
      (node (ref "C178") (pin "1") (pinfunction "1_1") (pintype "passive"))
      (node (ref "IC18") (pin "1") (pinfunction "OUT_1") (pintype "output"))
      (node (ref "R183") (pin "1") (pinfunction "P$1_1") (pintype "bidirectional"))
      (node (ref "R61") (pin "1") (pinfunction "P$1_1") (pintype "bidirectional"))
    )
    (net (code "250") (name "Net-(IC18B--IN)") (class "Default")
      (node (ref "C181") (pin "1") (pinfunction "1_1") (pintype "passive"))
      (node (ref "IC18") (pin "6") (pinfunction "-IN_6") (pintype "input"))
      (node (ref "R63") (pin "2") (pinfunction "P$2_2") (pintype "bidirectional"))
      (node (ref "R64") (pin "1") (pinfunction "P$1_1") (pintype "bidirectional"))
    )
    (net (code "251") (name "Net-(IC18B-OUT)") (class "Default")
      (node (ref "C181") (pin "2") (pinfunction "2_2") (pintype "passive"))
      (node (ref "IC18") (pin "7") (pinfunction "OUT_7") (pintype "output"))
      (node (ref "R184") (pin "1") (pinfunction "P$1_1") (pintype "bidirectional"))
      (node (ref "R63") (pin "1") (pinfunction "P$1_1") (pintype "bidirectional"))
    )
    (net (code "252") (name "Net-(IC19A-+IN)") (class "Default")
      (node (ref "C186") (pin "1") (pinfunction "1_1") (pintype "passive"))
      (node (ref "IC19") (pin "3") (pinfunction "+IN_3") (pintype "input"))
      (node (ref "R187") (pin "1") (pinfunction "P$1_1") (pintype "bidirectional"))
    )
    (net (code "253") (name "Net-(IC19A--IN)") (class "Default")
      (node (ref "C188") (pin "1") (pinfunction "1_1") (pintype "passive"))
      (node (ref "IC19") (pin "2") (pinfunction "-IN_2") (pintype "input"))
      (node (ref "R65") (pin "1") (pinfunction "P$1_1") (pintype "bidirectional"))
      (node (ref "R66") (pin "2") (pinfunction "P$2_2") (pintype "bidirectional"))
    )
    (net (code "254") (name "Net-(IC19A-OUT)") (class "Default")
      (node (ref "C188") (pin "2") (pinfunction "2_2") (pintype "passive"))
      (node (ref "IC19") (pin "1") (pinfunction "OUT_1") (pintype "output"))
      (node (ref "R186") (pin "1") (pinfunction "P$1_1") (pintype "bidirectional"))
      (node (ref "R66") (pin "1") (pinfunction "P$1_1") (pintype "bidirectional"))
    )
    (net (code "255") (name "Net-(IC19B-+IN)") (class "Default")
      (node (ref "C187") (pin "1") (pinfunction "1_1") (pintype "passive"))
      (node (ref "IC19") (pin "5") (pinfunction "+IN_5") (pintype "input"))
      (node (ref "R188") (pin "1") (pinfunction "P$1_1") (pintype "bidirectional"))
    )
    (net (code "256") (name "Net-(IC19B--IN)") (class "Default")
      (node (ref "C189") (pin "1") (pinfunction "1_1") (pintype "passive"))
      (node (ref "IC19") (pin "6") (pinfunction "-IN_6") (pintype "input"))
      (node (ref "R75") (pin "2") (pinfunction "P$2_2") (pintype "bidirectional"))
      (node (ref "R76") (pin "1") (pinfunction "P$1_1") (pintype "bidirectional"))
    )
    (net (code "257") (name "Net-(IC19B-OUT)") (class "Default")
      (node (ref "C189") (pin "2") (pinfunction "2_2") (pintype "passive"))
      (node (ref "IC19") (pin "7") (pinfunction "OUT_7") (pintype "output"))
      (node (ref "R185") (pin "1") (pinfunction "P$1_1") (pintype "bidirectional"))
      (node (ref "R75") (pin "1") (pinfunction "P$1_1") (pintype "bidirectional"))
    )
    (net (code "258") (name "Net-(IC20-AC{slash}DC)") (class "Default")
      (node (ref "IC20") (pin "16") (pinfunction "AC/DC_16") (pintype "input"))
      (node (ref "R201") (pin "1") (pinfunction "P$1_1") (pintype "bidirectional"))
    )
    (net (code "259") (name "Net-(IC20-CAP_SS)") (class "Default")
      (node (ref "C146") (pin "2") (pinfunction "2_2") (pintype "passive"))
      (node (ref "IC20") (pin "13") (pinfunction "CAP_SS_13") (pintype "passive"))
    )
    (net (code "260") (name "Net-(IC20-DIR_SEL)") (class "Default")
      (node (ref "IC20") (pin "6") (pinfunction "DIR_SEL_6") (pintype "input"))
      (node (ref "R60") (pin "1") (pinfunction "P$1_1") (pintype "bidirectional"))
    )
    (net (code "261") (name "Net-(IC20-L1)") (class "Default")
      (node (ref "IC20") (pin "12") (pinfunction "L1_12") (pintype "bidirectional"))
      (node (ref "R104") (pin "1") (pinfunction "P$1_1") (pintype "bidirectional"))
    )
    (net (code "262") (name "Net-(IC20-L2)") (class "Default")
      (node (ref "IC20") (pin "11") (pinfunction "L2_11") (pintype "bidirectional"))
      (node (ref "R59") (pin "1") (pinfunction "P$1_1") (pintype "bidirectional"))
    )
    (net (code "263") (name "Net-(IC20-R1)") (class "Default")
      (node (ref "IC20") (pin "10") (pinfunction "R1_10") (pintype "bidirectional"))
      (node (ref "R151") (pin "1") (pinfunction "P$1_1") (pintype "bidirectional"))
    )
    (net (code "264") (name "Net-(IC21A-+IN)") (class "Default")
      (node (ref "C114") (pin "2") (pinfunction "2_2") (pintype "passive"))
      (node (ref "IC21") (pin "3") (pinfunction "+IN_3") (pintype "input"))
      (node (ref "R105") (pin "2") (pinfunction "P$2_2") (pintype "bidirectional"))
    )
    (net (code "265") (name "Net-(IC21A--IN)") (class "Default")
      (node (ref "C101") (pin "1") (pinfunction "1_1") (pintype "passive"))
      (node (ref "IC21") (pin "2") (pinfunction "-IN_2") (pintype "input"))
      (node (ref "R94") (pin "2") (pinfunction "P$2_2") (pintype "bidirectional"))
    )
    (net (code "266") (name "Net-(IC21A-OUT)") (class "Default")
      (node (ref "C101") (pin "2") (pinfunction "2_2") (pintype "passive"))
      (node (ref "IC21") (pin "1") (pinfunction "OUT_1") (pintype "output"))
      (node (ref "R152") (pin "1") (pinfunction "P$1_1") (pintype "bidirectional"))
      (node (ref "R85") (pin "2") (pinfunction "P$2_2") (pintype "bidirectional"))
      (node (ref "R86") (pin "1") (pinfunction "P$1_1") (pintype "bidirectional"))
    )
    (net (code "267") (name "Net-(IC21B-+IN)") (class "Default")
      (node (ref "C99") (pin "2") (pinfunction "2_2") (pintype "passive"))
      (node (ref "IC21") (pin "5") (pinfunction "+IN_5") (pintype "input"))
      (node (ref "R57") (pin "2") (pinfunction "P$2_2") (pintype "bidirectional"))
    )
    (net (code "268") (name "Net-(IC21B--IN)") (class "Default")
      (node (ref "C98") (pin "1") (pinfunction "1_1") (pintype "passive"))
      (node (ref "IC21") (pin "6") (pinfunction "-IN_6") (pintype "input"))
      (node (ref "R56") (pin "2") (pinfunction "P$2_2") (pintype "bidirectional"))
    )
    (net (code "269") (name "Net-(IC21B-OUT)") (class "Default")
      (node (ref "C98") (pin "2") (pinfunction "2_2") (pintype "passive"))
      (node (ref "IC21") (pin "7") (pinfunction "OUT_7") (pintype "output"))
      (node (ref "R83") (pin "2") (pinfunction "P$2_2") (pintype "bidirectional"))
      (node (ref "R87") (pin "1") (pinfunction "P$1_1") (pintype "bidirectional"))
    )
    (net (code "270") (name "Net-(IC22A-X0)") (class "Default")
      (node (ref "IC22") (pin "1") (pinfunction "Y0_1") (pintype "bidirectional"))
      (node (ref "IC22") (pin "12") (pinfunction "X0_12") (pintype "bidirectional"))
      (node (ref "R153") (pin "2") (pinfunction "P$2_2") (pintype "bidirectional"))
    )
    (net (code "271") (name "Net-(IC22A-X1)") (class "Default")
      (node (ref "IC22") (pin "14") (pinfunction "X1_14") (pintype "bidirectional"))
      (node (ref "IC22") (pin "5") (pinfunction "Y1_5") (pintype "bidirectional"))
      (node (ref "R154") (pin "2") (pinfunction "P$2_2") (pintype "bidirectional"))
    )
    (net (code "272") (name "Net-(IC22A-X2)") (class "Default")
      (node (ref "IC22") (pin "15") (pinfunction "X2_15") (pintype "bidirectional"))
      (node (ref "IC22") (pin "2") (pinfunction "Y2_2") (pintype "bidirectional"))
      (node (ref "R155") (pin "2") (pinfunction "P$2_2") (pintype "bidirectional"))
    )
    (net (code "273") (name "Net-(IC22A-X3)") (class "Default")
      (node (ref "IC22") (pin "11") (pinfunction "X3_11") (pintype "bidirectional"))
      (node (ref "IC22") (pin "4") (pinfunction "Y3_4") (pintype "bidirectional"))
      (node (ref "R156") (pin "2") (pinfunction "P$2_2") (pintype "bidirectional"))
    )
    (net (code "274") (name "Net-(IC23A--IN)") (class "Default")
      (node (ref "C124") (pin "1") (pinfunction "1_1") (pintype "passive"))
      (node (ref "IC23") (pin "2") (pinfunction "-IN_2") (pintype "input"))
      (node (ref "R132") (pin "1") (pinfunction "P$1_1") (pintype "bidirectional"))
      (node (ref "R138") (pin "2") (pinfunction "P$2_2") (pintype "bidirectional"))
    )
    (net (code "275") (name "Net-(IC23A-OUT)") (class "Default")
      (node (ref "C124") (pin "2") (pinfunction "2_2") (pintype "passive"))
      (node (ref "IC23") (pin "1") (pinfunction "OUT_1") (pintype "output"))
      (node (ref "R132") (pin "2") (pinfunction "P$2_2") (pintype "bidirectional"))
      (node (ref "R142") (pin "1") (pinfunction "P$1_1") (pintype "bidirectional"))
    )
    (net (code "276") (name "Net-(IC23B--IN)") (class "Default")
      (node (ref "C121") (pin "1") (pinfunction "1_1") (pintype "passive"))
      (node (ref "IC23") (pin "6") (pinfunction "-IN_6") (pintype "input"))
      (node (ref "R106") (pin "1") (pinfunction "P$1_1") (pintype "bidirectional"))
      (node (ref "R135") (pin "2") (pinfunction "P$2_2") (pintype "bidirectional"))
    )
    (net (code "277") (name "Net-(IC23B-OUT)") (class "Default")
      (node (ref "C121") (pin "2") (pinfunction "2_2") (pintype "passive"))
      (node (ref "IC23") (pin "7") (pinfunction "OUT_7") (pintype "output"))
      (node (ref "R106") (pin "2") (pinfunction "P$2_2") (pintype "bidirectional"))
      (node (ref "R141") (pin "2") (pinfunction "P$2_2") (pintype "bidirectional"))
    )
    (net (code "278") (name "Net-(IC24A-I0)") (class "Default")
      (node (ref "C149") (pin "2") (pinfunction "2_2") (pintype "passive"))
      (node (ref "IC24") (pin "1") (pinfunction "I0_1") (pintype "input"))
      (node (ref "IC24") (pin "2") (pinfunction "I1_2") (pintype "input"))
      (node (ref "IC24") (pin "6") (pinfunction "O_6") (pintype "output"))
    )
    (net (code "279") (name "Net-(IC24A-O)") (class "Default")
      (node (ref "IC24") (pin "3") (pinfunction "O_3") (pintype "output"))
      (node (ref "IC27") (pin "12") (pinfunction "I0_12") (pintype "input"))
      (node (ref "IC27") (pin "4") (pinfunction "I0_4") (pintype "input"))
      (node (ref "IC27") (pin "5") (pinfunction "I1_5") (pintype "input"))
      (node (ref "R158") (pin "2") (pinfunction "P$2_2") (pintype "bidirectional"))
      (node (ref "R160") (pin "1") (pinfunction "P$1_1") (pintype "bidirectional"))
    )
    (net (code "280") (name "Net-(IC24B-I0)") (class "Default")
      (node (ref "IC24") (pin "4") (pinfunction "I0_4") (pintype "input"))
      (node (ref "IC24") (pin "5") (pinfunction "I1_5") (pintype "input"))
      (node (ref "IC27") (pin "3") (pinfunction "O_3") (pintype "output"))
    )
    (net (code "281") (name "Net-(IC24C-I0)") (class "Default")
      (node (ref "IC24") (pin "10") (pinfunction "I1_10") (pintype "input"))
      (node (ref "IC24") (pin "9") (pinfunction "I0_9") (pintype "input"))
      (node (ref "IC27") (pin "8") (pinfunction "O_8") (pintype "output"))
    )
    (net (code "282") (name "Net-(IC24C-O)") (class "Default")
      (node (ref "IC24") (pin "8") (pinfunction "O_8") (pintype "output"))
      (node (ref "R162") (pin "1") (pinfunction "P$1_1") (pintype "bidirectional"))
    )
    (net (code "283") (name "Net-(IC24D-I0)") (class "Default")
      (node (ref "IC24") (pin "12") (pinfunction "I0_12") (pintype "input"))
      (node (ref "IC24") (pin "13") (pinfunction "I1_13") (pintype "input"))
      (node (ref "IC27") (pin "11") (pinfunction "O_11") (pintype "output"))
    )
    (net (code "284") (name "Net-(IC24D-O)") (class "Default")
      (node (ref "IC24") (pin "11") (pinfunction "O_11") (pintype "output"))
      (node (ref "R161") (pin "1") (pinfunction "P$1_1") (pintype "bidirectional"))
    )
    (net (code "285") (name "Net-(IC25-RG)") (class "Default")
      (node (ref "IC25") (pin "1") (pinfunction "RG_1") (pintype "passive"))
      (node (ref "R202") (pin "1") (pinfunction "P$1_1") (pintype "bidirectional"))
      (node (ref "R203") (pin "2") (pinfunction "P$2_2") (pintype "bidirectional"))
    )
    (net (code "286") (name "Net-(IC25-VIN+)") (class "Default")
      (node (ref "IC25") (pin "3") (pinfunction "VIN+_3") (pintype "input"))
      (node (ref "R204") (pin "2") (pinfunction "P$2_2") (pintype "bidirectional"))
      (node (ref "R207") (pin "2") (pinfunction "P$2_2") (pintype "bidirectional"))
    )
    (net (code "287") (name "Net-(IC25-VIN-)") (class "Default")
      (node (ref "IC25") (pin "2") (pinfunction "VIN-_2") (pintype "input"))
      (node (ref "R205") (pin "2") (pinfunction "P$2_2") (pintype "bidirectional"))
      (node (ref "R206") (pin "1") (pinfunction "P$1_1") (pintype "bidirectional"))
    )
    (net (code "288") (name "Net-(IC26-ZQ)") (class "Default")
      (node (ref "IC26") (pin "H8") (pinfunction "ZQ_H8") (pintype "bidirectional"))
      (node (ref "R3") (pin "1") (pinfunction "P$1_1") (pintype "bidirectional"))
    )
    (net (code "289") (name "Net-(IC27A-I0)") (class "Default")
      (node (ref "IC27") (pin "1") (pinfunction "I0_1") (pintype "input"))
      (node (ref "IC27") (pin "2") (pinfunction "I1_2") (pintype "input"))
      (node (ref "R157") (pin "1") (pinfunction "P$1_1") (pintype "bidirectional"))
    )
    (net (code "290") (name "Net-(IC27B-O)") (class "Default")
      (node (ref "IC27") (pin "6") (pinfunction "O_6") (pintype "output"))
      (node (ref "IC27") (pin "9") (pinfunction "I0_9") (pintype "input"))
      (node (ref "R159") (pin "1") (pinfunction "P$1_1") (pintype "bidirectional"))
    )
    (net (code "291") (name "Net-(IC27C-I1)") (class "Default")
      (node (ref "C152") (pin "2") (pinfunction "2_2") (pintype "passive"))
      (node (ref "IC27") (pin "10") (pinfunction "I1_10") (pintype "input"))
      (node (ref "R159") (pin "2") (pinfunction "P$2_2") (pintype "bidirectional"))
    )
    (net (code "292") (name "Net-(IC27D-I1)") (class "Default")
      (node (ref "C151") (pin "2") (pinfunction "2_2") (pintype "passive"))
      (node (ref "IC27") (pin "13") (pinfunction "I1_13") (pintype "input"))
      (node (ref "R160") (pin "2") (pinfunction "P$2_2") (pintype "bidirectional"))
    )
    (net (code "293") (name "Net-(IC28-FB)") (class "Default")
      (node (ref "IC28") (pin "4") (pinfunction "FB_4") (pintype "input"))
      (node (ref "R170") (pin "1") (pinfunction "P$1_1") (pintype "bidirectional"))
      (node (ref "R171") (pin "2") (pinfunction "P$2_2") (pintype "bidirectional"))
    )
    (net (code "294") (name "Net-(IC28-OUT)") (class "Default")
      (node (ref "C169") (pin "1") (pinfunction "1_1") (pintype "passive"))
      (node (ref "IC28") (pin "5") (pinfunction "OUT_5") (pintype "power_in"))
      (node (ref "R170") (pin "2") (pinfunction "P$2_2") (pintype "bidirectional"))
      (node (ref "R173") (pin "1") (pinfunction "P$1_1") (pintype "bidirectional"))
    )
    (net (code "295") (name "Net-(IC29-EN)") (class "Default")
      (node (ref "C173") (pin "2") (pinfunction "2_2") (pintype "passive"))
      (node (ref "IC29") (pin "1") (pinfunction "IN_1") (pintype "power_in"))
      (node (ref "IC29") (pin "3") (pinfunction "EN_3") (pintype "input"))
      (node (ref "R178") (pin "2") (pinfunction "P$2_2") (pintype "bidirectional"))
    )
    (net (code "296") (name "Net-(IC29-FB)") (class "Default")
      (node (ref "C174") (pin "1") (pinfunction "1_1") (pintype "passive"))
      (node (ref "IC29") (pin "5") (pinfunction "FB_5") (pintype "input"))
      (node (ref "R175") (pin "1") (pinfunction "P$1_1") (pintype "bidirectional"))
      (node (ref "R176") (pin "2") (pinfunction "P$2_2") (pintype "bidirectional"))
    )
    (net (code "297") (name "Net-(IC29-NR)") (class "Default")
      (node (ref "C172") (pin "2") (pinfunction "2_2") (pintype "passive"))
      (node (ref "IC29") (pin "4") (pinfunction "NR_4") (pintype "input"))
    )
    (net (code "298") (name "Net-(IC29-OUT)") (class "Default")
      (node (ref "C171") (pin "2") (pinfunction "2_2") (pintype "passive"))
      (node (ref "C174") (pin "2") (pinfunction "2_2") (pintype "passive"))
      (node (ref "IC29") (pin "6") (pinfunction "OUT_6") (pintype "power_in"))
      (node (ref "R175") (pin "2") (pinfunction "P$2_2") (pintype "bidirectional"))
      (node (ref "R177") (pin "1") (pinfunction "P$1_1") (pintype "bidirectional"))
    )
    (net (code "299") (name "Net-(IC30A-+IN)") (class "Default")
      (node (ref "C191") (pin "1") (pinfunction "1_1") (pintype "passive"))
      (node (ref "IC30") (pin "3") (pinfunction "+IN_3") (pintype "input"))
      (node (ref "R190") (pin "2") (pinfunction "P$2_2") (pintype "bidirectional"))
      (node (ref "R191") (pin "1") (pinfunction "P$1_1") (pintype "bidirectional"))
    )
    (net (code "300") (name "Net-(IC30A--IN)") (class "Default")
      (node (ref "C190") (pin "2") (pinfunction "2_2") (pintype "passive"))
      (node (ref "IC30") (pin "2") (pinfunction "-IN_2") (pintype "input"))
      (node (ref "R189") (pin "2") (pinfunction "P$2_2") (pintype "bidirectional"))
    )
    (net (code "301") (name "Net-(IC30A-OUT)") (class "Default")
      (node (ref "C190") (pin "1") (pinfunction "1_1") (pintype "passive"))
      (node (ref "IC30") (pin "1") (pinfunction "OUT_1") (pintype "output"))
      (node (ref "R189") (pin "1") (pinfunction "P$1_1") (pintype "bidirectional"))
      (node (ref "R192") (pin "1") (pinfunction "P$1_1") (pintype "bidirectional"))
    )
    (net (code "302") (name "Net-(IC30B-+IN)") (class "Default")
      (node (ref "C196") (pin "1") (pinfunction "1_1") (pintype "passive"))
      (node (ref "IC30") (pin "5") (pinfunction "+IN_5") (pintype "input"))
      (node (ref "R196") (pin "1") (pinfunction "P$1_1") (pintype "bidirectional"))
      (node (ref "R197") (pin "2") (pinfunction "P$2_2") (pintype "bidirectional"))
    )
    (net (code "303") (name "Net-(IC30B--IN)") (class "Default")
      (node (ref "C195") (pin "2") (pinfunction "2_2") (pintype "passive"))
      (node (ref "IC30") (pin "6") (pinfunction "-IN_6") (pintype "input"))
      (node (ref "R194") (pin "2") (pinfunction "P$2_2") (pintype "bidirectional"))
    )
    (net (code "304") (name "Net-(IC30B-OUT)") (class "Default")
      (node (ref "C195") (pin "1") (pinfunction "1_1") (pintype "passive"))
      (node (ref "IC30") (pin "7") (pinfunction "OUT_7") (pintype "output"))
      (node (ref "R191") (pin "2") (pinfunction "P$2_2") (pintype "bidirectional"))
      (node (ref "R193") (pin "1") (pinfunction "P$1_1") (pintype "bidirectional"))
      (node (ref "R194") (pin "1") (pinfunction "P$1_1") (pintype "bidirectional"))
    )
    (net (code "305") (name "Net-(IC31B--IN)") (class "Default")
      (node (ref "C199") (pin "1") (pinfunction "1_1") (pintype "passive"))
      (node (ref "IC31") (pin "6") (pinfunction "-IN_6") (pintype "input"))
      (node (ref "R198") (pin "2") (pinfunction "P$2_2") (pintype "bidirectional"))
      (node (ref "R199") (pin "1") (pinfunction "P$1_1") (pintype "bidirectional"))
    )
    (net (code "306") (name "Net-(IC32-AIN0)") (class "Default")
      (node (ref "C203") (pin "1") (pinfunction "1_1") (pintype "passive"))
      (node (ref "IC32") (pin "4") (pinfunction "AIN0_4") (pintype "input"))
      (node (ref "R108") (pin "2") (pinfunction "P$2_2") (pintype "bidirectional"))
    )
    (net (code "307") (name "Net-(IC32-AIN1)") (class "Default")
      (node (ref "C202") (pin "1") (pinfunction "1_1") (pintype "passive"))
      (node (ref "IC32") (pin "5") (pinfunction "AIN1_5") (pintype "input"))
      (node (ref "R109") (pin "2") (pinfunction "P$2_2") (pintype "bidirectional"))
    )
    (net (code "308") (name "Net-(IC32-AIN2)") (class "Default")
      (node (ref "C201") (pin "1") (pinfunction "1_1") (pintype "passive"))
      (node (ref "IC32") (pin "6") (pinfunction "AIN2_6") (pintype "input"))
      (node (ref "R110") (pin "2") (pinfunction "P$2_2") (pintype "bidirectional"))
    )
    (net (code "309") (name "Net-(IC32-AIN3)") (class "Default")
      (node (ref "IC32") (pin "7") (pinfunction "AIN3_7") (pintype "input"))
      (node (ref "R111") (pin "2") (pinfunction "P$2_2") (pintype "bidirectional"))
    )
    (net (code "310") (name "Net-(IC32-DOUT{slash}~{DRDY})") (class "Default")
      (node (ref "IC32") (pin "9") (pinfunction "DOUT/~{DRDY}_9") (pintype "output"))
      (node (ref "R280") (pin "2") (pinfunction "P$2_2") (pintype "bidirectional"))
    )
    (net (code "311") (name "Net-(IC33A-IN+)") (class "Default")
      (node (ref "IC33") (pin "5") (pinfunction "IN+_5") (pintype "input"))
      (node (ref "IC34") (pin "12") (pinfunction "X0_12") (pintype "bidirectional"))
      (node (ref "IC35") (pin "15") (pinfunction "X2_15") (pintype "bidirectional"))
      (node (ref "IC35") (pin "5") (pinfunction "Y1_5") (pintype "bidirectional"))
      (node (ref "R220") (pin "2") (pinfunction "P$2_2") (pintype "bidirectional"))
      (node (ref "R231") (pin "1") (pinfunction "P$1_1") (pintype "bidirectional"))
    )
    (net (code "312") (name "Net-(IC33A-IN-)") (class "Default")
      (node (ref "IC33") (pin "6") (pinfunction "IN-_6") (pintype "input"))
      (node (ref "R208") (pin "1") (pinfunction "P$1_1") (pintype "bidirectional"))
      (node (ref "R209") (pin "2") (pinfunction "P$2_2") (pintype "bidirectional"))
    )
    (net (code "313") (name "Net-(IC33A-OUT)") (class "Default")
      (node (ref "IC33") (pin "7") (pinfunction "OUT_7") (pintype "output"))
      (node (ref "R208") (pin "2") (pinfunction "P$2_2") (pintype "bidirectional"))
      (node (ref "R211") (pin "2") (pinfunction "P$2_2") (pintype "bidirectional"))
    )
    (net (code "314") (name "Net-(IC33B-IN+)") (class "Default")
      (node (ref "IC33") (pin "10") (pinfunction "IN+_10") (pintype "input"))
      (node (ref "IC35") (pin "3") (pinfunction "Y_3") (pintype "bidirectional"))
      (node (ref "R218") (pin "2") (pinfunction "P$2_2") (pintype "bidirectional"))
    )
    (net (code "315") (name "Net-(IC33B-IN-)") (class "Default")
      (node (ref "IC33") (pin "9") (pinfunction "IN-_9") (pintype "input"))
      (node (ref "R212") (pin "1") (pinfunction "P$1_1") (pintype "bidirectional"))
      (node (ref "R213") (pin "2") (pinfunction "P$2_2") (pintype "bidirectional"))
    )
    (net (code "316") (name "Net-(IC33B-OUT)") (class "Default")
      (node (ref "IC33") (pin "8") (pinfunction "OUT_8") (pintype "output"))
      (node (ref "R212") (pin "2") (pinfunction "P$2_2") (pintype "bidirectional"))
      (node (ref "R214") (pin "2") (pinfunction "P$2_2") (pintype "bidirectional"))
    )
    (net (code "317") (name "Net-(IC33C-IN+)") (class "Default")
      (node (ref "IC33") (pin "12") (pinfunction "IN+_12") (pintype "input"))
      (node (ref "IC35") (pin "13") (pinfunction "X_13") (pintype "bidirectional"))
      (node (ref "R219") (pin "2") (pinfunction "P$2_2") (pintype "bidirectional"))
    )
    (net (code "318") (name "Net-(IC33C-IN-)") (class "Default")
      (node (ref "IC33") (pin "13") (pinfunction "IN-_13") (pintype "input"))
      (node (ref "R215") (pin "1") (pinfunction "P$1_1") (pintype "bidirectional"))
      (node (ref "R216") (pin "2") (pinfunction "P$2_2") (pintype "bidirectional"))
    )
    (net (code "319") (name "Net-(IC33C-OUT)") (class "Default")
      (node (ref "IC33") (pin "14") (pinfunction "OUT_14") (pintype "output"))
      (node (ref "R215") (pin "2") (pinfunction "P$2_2") (pintype "bidirectional"))
      (node (ref "R217") (pin "2") (pinfunction "P$2_2") (pintype "bidirectional"))
    )
    (net (code "320") (name "Net-(IC34A-X)") (class "Default")
      (node (ref "IC34") (pin "13") (pinfunction "X_13") (pintype "bidirectional"))
      (node (ref "IC36") (pin "5") (pinfunction "+IN_5") (pintype "input"))
    )
    (net (code "321") (name "Net-(IC34A-X1)") (class "Default")
      (node (ref "IC34") (pin "14") (pinfunction "X1_14") (pintype "bidirectional"))
      (node (ref "IC35") (pin "12") (pinfunction "X0_12") (pintype "bidirectional"))
      (node (ref "R214") (pin "1") (pinfunction "P$1_1") (pintype "bidirectional"))
    )
    (net (code "322") (name "Net-(IC34A-X2)") (class "Default")
      (node (ref "IC34") (pin "15") (pinfunction "X2_15") (pintype "bidirectional"))
      (node (ref "R217") (pin "1") (pinfunction "P$1_1") (pintype "bidirectional"))
    )
    (net (code "323") (name "Net-(IC35A-X3)") (class "Default")
      (node (ref "IC35") (pin "1") (pinfunction "Y0_1") (pintype "bidirectional"))
      (node (ref "IC35") (pin "11") (pinfunction "X3_11") (pintype "bidirectional"))
      (node (ref "R211") (pin "1") (pinfunction "P$1_1") (pintype "bidirectional"))
    )
    (net (code "324") (name "Net-(IC36A-+IN)") (class "Default")
      (node (ref "IC36") (pin "3") (pinfunction "+IN_3") (pintype "input"))
      (node (ref "K2") (pin "6") (pinfunction "P_6") (pintype "passive"))
    )
    (net (code "325") (name "Net-(IC36A--IN)") (class "Default")
      (node (ref "IC36") (pin "2") (pinfunction "-IN_2") (pintype "input"))
      (node (ref "R229") (pin "1") (pinfunction "P$1_1") (pintype "bidirectional"))
      (node (ref "R230") (pin "2") (pinfunction "P$2_2") (pintype "bidirectional"))
    )
    (net (code "326") (name "Net-(IC36A-OUT)") (class "Default")
      (node (ref "IC36") (pin "1") (pinfunction "OUT_1") (pintype "output"))
      (node (ref "R229") (pin "2") (pinfunction "P$2_2") (pintype "bidirectional"))
      (node (ref "R231") (pin "2") (pinfunction "P$2_2") (pintype "bidirectional"))
    )
    (net (code "327") (name "Net-(IC36B--IN)") (class "Default")
      (node (ref "IC36") (pin "6") (pinfunction "-IN_6") (pintype "input"))
      (node (ref "R238") (pin "1") (pinfunction "P$1_1") (pintype "bidirectional"))
    )
    (net (code "328") (name "Net-(IC36B-OUT)") (class "Default")
      (node (ref "IC36") (pin "7") (pinfunction "OUT_7") (pintype "output"))
      (node (ref "R237") (pin "2") (pinfunction "P$2_2") (pintype "bidirectional"))
      (node (ref "R238") (pin "2") (pinfunction "P$2_2") (pintype "bidirectional"))
      (node (ref "R239") (pin "1") (pinfunction "P$1_1") (pintype "bidirectional"))
    )
    (net (code "329") (name "Net-(IC38A-IN+)") (class "Default")
      (node (ref "IC38") (pin "5") (pinfunction "IN+_5") (pintype "input"))
      (node (ref "IC39") (pin "12") (pinfunction "X0_12") (pintype "bidirectional"))
      (node (ref "IC40") (pin "15") (pinfunction "X2_15") (pintype "bidirectional"))
      (node (ref "IC40") (pin "5") (pinfunction "Y1_5") (pintype "bidirectional"))
      (node (ref "R256") (pin "2") (pinfunction "P$2_2") (pintype "bidirectional"))
      (node (ref "R267") (pin "1") (pinfunction "P$1_1") (pintype "bidirectional"))
    )
    (net (code "330") (name "Net-(IC38A-IN-)") (class "Default")
      (node (ref "IC38") (pin "6") (pinfunction "IN-_6") (pintype "input"))
      (node (ref "R244") (pin "1") (pinfunction "P$1_1") (pintype "bidirectional"))
      (node (ref "R245") (pin "2") (pinfunction "P$2_2") (pintype "bidirectional"))
    )
    (net (code "331") (name "Net-(IC38A-OUT)") (class "Default")
      (node (ref "IC38") (pin "7") (pinfunction "OUT_7") (pintype "output"))
      (node (ref "R244") (pin "2") (pinfunction "P$2_2") (pintype "bidirectional"))
      (node (ref "R247") (pin "2") (pinfunction "P$2_2") (pintype "bidirectional"))
    )
    (net (code "332") (name "Net-(IC38B-IN+)") (class "Default")
      (node (ref "IC38") (pin "10") (pinfunction "IN+_10") (pintype "input"))
      (node (ref "IC40") (pin "3") (pinfunction "Y_3") (pintype "bidirectional"))
      (node (ref "R254") (pin "2") (pinfunction "P$2_2") (pintype "bidirectional"))
    )
    (net (code "333") (name "Net-(IC38B-IN-)") (class "Default")
      (node (ref "IC38") (pin "9") (pinfunction "IN-_9") (pintype "input"))
      (node (ref "R248") (pin "1") (pinfunction "P$1_1") (pintype "bidirectional"))
      (node (ref "R249") (pin "2") (pinfunction "P$2_2") (pintype "bidirectional"))
    )
    (net (code "334") (name "Net-(IC38B-OUT)") (class "Default")
      (node (ref "IC38") (pin "8") (pinfunction "OUT_8") (pintype "output"))
      (node (ref "R248") (pin "2") (pinfunction "P$2_2") (pintype "bidirectional"))
      (node (ref "R250") (pin "2") (pinfunction "P$2_2") (pintype "bidirectional"))
    )
    (net (code "335") (name "Net-(IC38C-IN+)") (class "Default")
      (node (ref "IC38") (pin "12") (pinfunction "IN+_12") (pintype "input"))
      (node (ref "IC40") (pin "13") (pinfunction "X_13") (pintype "bidirectional"))
      (node (ref "R255") (pin "2") (pinfunction "P$2_2") (pintype "bidirectional"))
    )
    (net (code "336") (name "Net-(IC38C-IN-)") (class "Default")
      (node (ref "IC38") (pin "13") (pinfunction "IN-_13") (pintype "input"))
      (node (ref "R251") (pin "1") (pinfunction "P$1_1") (pintype "bidirectional"))
      (node (ref "R252") (pin "2") (pinfunction "P$2_2") (pintype "bidirectional"))
    )
    (net (code "337") (name "Net-(IC38C-OUT)") (class "Default")
      (node (ref "IC38") (pin "14") (pinfunction "OUT_14") (pintype "output"))
      (node (ref "R251") (pin "2") (pinfunction "P$2_2") (pintype "bidirectional"))
      (node (ref "R253") (pin "2") (pinfunction "P$2_2") (pintype "bidirectional"))
    )
    (net (code "338") (name "Net-(IC39A-X)") (class "Default")
      (node (ref "IC39") (pin "13") (pinfunction "X_13") (pintype "bidirectional"))
      (node (ref "IC41") (pin "5") (pinfunction "+IN_5") (pintype "input"))
    )
    (net (code "339") (name "Net-(IC39A-X1)") (class "Default")
      (node (ref "IC39") (pin "14") (pinfunction "X1_14") (pintype "bidirectional"))
      (node (ref "IC40") (pin "12") (pinfunction "X0_12") (pintype "bidirectional"))
      (node (ref "R250") (pin "1") (pinfunction "P$1_1") (pintype "bidirectional"))
    )
    (net (code "340") (name "Net-(IC39A-X2)") (class "Default")
      (node (ref "IC39") (pin "15") (pinfunction "X2_15") (pintype "bidirectional"))
      (node (ref "R253") (pin "1") (pinfunction "P$1_1") (pintype "bidirectional"))
    )
    (net (code "341") (name "Net-(IC40A-X3)") (class "Default")
      (node (ref "IC40") (pin "1") (pinfunction "Y0_1") (pintype "bidirectional"))
      (node (ref "IC40") (pin "11") (pinfunction "X3_11") (pintype "bidirectional"))
      (node (ref "R247") (pin "1") (pinfunction "P$1_1") (pintype "bidirectional"))
    )
    (net (code "342") (name "Net-(IC41A-+IN)") (class "Default")
      (node (ref "IC41") (pin "3") (pinfunction "+IN_3") (pintype "input"))
      (node (ref "K4") (pin "6") (pinfunction "P_6") (pintype "passive"))
    )
    (net (code "343") (name "Net-(IC41A--IN)") (class "Default")
      (node (ref "IC41") (pin "2") (pinfunction "-IN_2") (pintype "input"))
      (node (ref "R265") (pin "1") (pinfunction "P$1_1") (pintype "bidirectional"))
      (node (ref "R266") (pin "2") (pinfunction "P$2_2") (pintype "bidirectional"))
    )
    (net (code "344") (name "Net-(IC41A-OUT)") (class "Default")
      (node (ref "IC41") (pin "1") (pinfunction "OUT_1") (pintype "output"))
      (node (ref "R265") (pin "2") (pinfunction "P$2_2") (pintype "bidirectional"))
      (node (ref "R267") (pin "2") (pinfunction "P$2_2") (pintype "bidirectional"))
    )
    (net (code "345") (name "Net-(IC41B--IN)") (class "Default")
      (node (ref "IC41") (pin "6") (pinfunction "-IN_6") (pintype "input"))
      (node (ref "R274") (pin "1") (pinfunction "P$1_1") (pintype "bidirectional"))
    )
    (net (code "346") (name "Net-(IC41B-OUT)") (class "Default")
      (node (ref "IC41") (pin "7") (pinfunction "OUT_7") (pintype "output"))
      (node (ref "R273") (pin "2") (pinfunction "P$2_2") (pintype "bidirectional"))
      (node (ref "R274") (pin "2") (pinfunction "P$2_2") (pintype "bidirectional"))
      (node (ref "R275") (pin "1") (pinfunction "P$1_1") (pintype "bidirectional"))
    )
    (net (code "347") (name "Net-(IC43-+IN)") (class "Default")
      (node (ref "IC43") (pin "1") (pinfunction "+IN_1") (pintype "input"))
      (node (ref "R283") (pin "2") (pinfunction "P$2_2") (pintype "bidirectional"))
      (node (ref "R284") (pin "2") (pinfunction "P$2_2") (pintype "bidirectional"))
    )
    (net (code "348") (name "Net-(IC43--IN)") (class "Default")
      (node (ref "IC43") (pin "3") (pinfunction "-IN_3") (pintype "input"))
      (node (ref "R300") (pin "1") (pinfunction "P$1_1") (pintype "bidirectional"))
    )
    (net (code "349") (name "Net-(IC43-OUT)") (class "Default")
      (node (ref "IC43") (pin "4") (pinfunction "OUT_4") (pintype "output"))
      (node (ref "R282") (pin "1") (pinfunction "P$1_1") (pintype "bidirectional"))
      (node (ref "R300") (pin "2") (pinfunction "P$2_2") (pintype "bidirectional"))
    )
    (net (code "350") (name "Net-(IC44A-QA)") (class "Default")
      (node (ref "IC44") (pin "15") (pinfunction "QA_15") (pintype "tri_state"))
      (node (ref "R283") (pin "1") (pinfunction "P$1_1") (pintype "bidirectional"))
    )
    (net (code "351") (name "Net-(IC44A-QB)") (class "Default")
      (node (ref "IC44") (pin "1") (pinfunction "QB_1") (pintype "tri_state"))
      (node (ref "R285") (pin "2") (pinfunction "P$2_2") (pintype "bidirectional"))
    )
    (net (code "352") (name "Net-(IC44A-QC)") (class "Default")
      (node (ref "IC44") (pin "2") (pinfunction "QC_2") (pintype "tri_state"))
      (node (ref "R293") (pin "2") (pinfunction "P$2_2") (pintype "bidirectional"))
    )
    (net (code "353") (name "Net-(IC44A-QD)") (class "Default")
      (node (ref "IC44") (pin "3") (pinfunction "QD_3") (pintype "tri_state"))
      (node (ref "R294") (pin "2") (pinfunction "P$2_2") (pintype "bidirectional"))
    )
    (net (code "354") (name "Net-(IC44A-QE)") (class "Default")
      (node (ref "IC44") (pin "4") (pinfunction "QE_4") (pintype "tri_state"))
      (node (ref "R295") (pin "2") (pinfunction "P$2_2") (pintype "bidirectional"))
    )
    (net (code "355") (name "Net-(IC44A-QF)") (class "Default")
      (node (ref "IC44") (pin "5") (pinfunction "QF_5") (pintype "tri_state"))
      (node (ref "R296") (pin "2") (pinfunction "P$2_2") (pintype "bidirectional"))
    )
    (net (code "356") (name "Net-(IC44A-QG)") (class "Default")
      (node (ref "IC44") (pin "6") (pinfunction "QG_6") (pintype "tri_state"))
      (node (ref "R297") (pin "2") (pinfunction "P$2_2") (pintype "bidirectional"))
    )
    (net (code "357") (name "Net-(IC44A-QH)") (class "Default")
      (node (ref "IC44") (pin "7") (pinfunction "QH_7") (pintype "tri_state"))
      (node (ref "R298") (pin "2") (pinfunction "P$2_2") (pintype "bidirectional"))
    )
    (net (code "358") (name "Net-(K1A-+)") (class "Default")
      (node (ref "K1") (pin "1") (pinfunction "+_1") (pintype "passive"))
      (node (ref "T2") (pin "2") (pinfunction "E_2") (pintype "passive"))
      (node (ref "T5") (pin "E") (pinfunction "E_E") (pintype "passive"))
    )
    (net (code "359") (name "Net-(K1A--)") (class "Default")
      (node (ref "K1") (pin "8") (pinfunction "-_8") (pintype "passive"))
      (node (ref "T3") (pin "2") (pinfunction "E_2") (pintype "passive"))
      (node (ref "T6") (pin "E") (pinfunction "E_E") (pintype "passive"))
    )
    (net (code "360") (name "Net-(K1B-O)") (class "Default")
      (node (ref "C211") (pin "1") (pinfunction "1_1") (pintype "passive"))
      (node (ref "K1") (pin "2") (pinfunction "O_2") (pintype "passive"))
      (node (ref "K2") (pin "3") (pinfunction "P_3") (pintype "passive"))
    )
    (net (code "361") (name "Net-(K1B-P)") (class "Default")
      (node (ref "C211") (pin "2") (pinfunction "2_2") (pintype "passive"))
      (node (ref "K1") (pin "3") (pinfunction "P_3") (pintype "passive"))
      (node (ref "R241") (pin "1") (pinfunction "P$1_1") (pintype "bidirectional"))
    )
    (net (code "362") (name "Net-(K2A-+)") (class "Default")
      (node (ref "K2") (pin "1") (pinfunction "+_1") (pintype "passive"))
      (node (ref "T4") (pin "2") (pinfunction "E_2") (pintype "passive"))
      (node (ref "T7") (pin "E") (pinfunction "E_E") (pintype "passive"))
    )
    (net (code "363") (name "Net-(K2A--)") (class "Default")
      (node (ref "K2") (pin "8") (pinfunction "-_8") (pintype "passive"))
      (node (ref "T8") (pin "2") (pinfunction "E_2") (pintype "passive"))
      (node (ref "T9") (pin "E") (pinfunction "E_E") (pintype "passive"))
    )
    (net (code "364") (name "Net-(K2B-O)") (class "Default")
      (node (ref "C217") (pin "2") (pinfunction "2_2") (pintype "passive"))
      (node (ref "C222") (pin "2") (pinfunction "2_2") (pintype "passive"))
      (node (ref "C229") (pin "2") (pinfunction "2_2") (pintype "passive"))
      (node (ref "K2") (pin "2") (pinfunction "O_2") (pintype "passive"))
      (node (ref "R227") (pin "2") (pinfunction "P$2_2") (pintype "bidirectional"))
    )
    (net (code "365") (name "Net-(K2B-S)") (class "Default")
      (node (ref "C214") (pin "2") (pinfunction "2_2") (pintype "passive"))
      (node (ref "C223") (pin "2") (pinfunction "2_2") (pintype "passive"))
      (node (ref "C228") (pin "2") (pinfunction "2_2") (pintype "passive"))
      (node (ref "K2") (pin "4") (pinfunction "S_4") (pintype "passive"))
      (node (ref "R223") (pin "2") (pinfunction "P$2_2") (pintype "bidirectional"))
    )
    (net (code "366") (name "Net-(K2C-O)") (class "Default")
      (node (ref "K2") (pin "7") (pinfunction "O_7") (pintype "passive"))
      (node (ref "R243") (pin "1") (pinfunction "P$1_1") (pintype "bidirectional"))
    )
    (net (code "367") (name "Net-(K2C-S)") (class "Default")
      (node (ref "K2") (pin "5") (pinfunction "S_5") (pintype "passive"))
      (node (ref "R242") (pin "1") (pinfunction "P$1_1") (pintype "bidirectional"))
    )
    (net (code "368") (name "Net-(K3A-+)") (class "Default")
      (node (ref "K3") (pin "1") (pinfunction "+_1") (pintype "passive"))
      (node (ref "T10") (pin "2") (pinfunction "E_2") (pintype "passive"))
      (node (ref "T12") (pin "E") (pinfunction "E_E") (pintype "passive"))
    )
    (net (code "369") (name "Net-(K3A--)") (class "Default")
      (node (ref "K3") (pin "8") (pinfunction "-_8") (pintype "passive"))
      (node (ref "T11") (pin "2") (pinfunction "E_2") (pintype "passive"))
      (node (ref "T13") (pin "E") (pinfunction "E_E") (pintype "passive"))
    )
    (net (code "370") (name "Net-(K3B-O)") (class "Default")
      (node (ref "C236") (pin "1") (pinfunction "1_1") (pintype "passive"))
      (node (ref "K3") (pin "2") (pinfunction "O_2") (pintype "passive"))
      (node (ref "K4") (pin "3") (pinfunction "P_3") (pintype "passive"))
    )
    (net (code "371") (name "Net-(K3B-P)") (class "Default")
      (node (ref "C236") (pin "2") (pinfunction "2_2") (pintype "passive"))
      (node (ref "K3") (pin "3") (pinfunction "P_3") (pintype "passive"))
      (node (ref "R277") (pin "1") (pinfunction "P$1_1") (pintype "bidirectional"))
    )
    (net (code "372") (name "Net-(K4A-+)") (class "Default")
      (node (ref "K4") (pin "1") (pinfunction "+_1") (pintype "passive"))
      (node (ref "T14") (pin "2") (pinfunction "E_2") (pintype "passive"))
      (node (ref "T15") (pin "E") (pinfunction "E_E") (pintype "passive"))
    )
    (net (code "373") (name "Net-(K4A--)") (class "Default")
      (node (ref "K4") (pin "8") (pinfunction "-_8") (pintype "passive"))
      (node (ref "T16") (pin "2") (pinfunction "E_2") (pintype "passive"))
      (node (ref "T17") (pin "E") (pinfunction "E_E") (pintype "passive"))
    )
    (net (code "374") (name "Net-(K4B-O)") (class "Default")
      (node (ref "C242") (pin "2") (pinfunction "2_2") (pintype "passive"))
      (node (ref "C247") (pin "2") (pinfunction "2_2") (pintype "passive"))
      (node (ref "C254") (pin "2") (pinfunction "2_2") (pintype "passive"))
      (node (ref "K4") (pin "2") (pinfunction "O_2") (pintype "passive"))
      (node (ref "R263") (pin "2") (pinfunction "P$2_2") (pintype "bidirectional"))
    )
    (net (code "375") (name "Net-(K4B-S)") (class "Default")
      (node (ref "C239") (pin "2") (pinfunction "2_2") (pintype "passive"))
      (node (ref "C248") (pin "2") (pinfunction "2_2") (pintype "passive"))
      (node (ref "C253") (pin "2") (pinfunction "2_2") (pintype "passive"))
      (node (ref "K4") (pin "4") (pinfunction "S_4") (pintype "passive"))
      (node (ref "R259") (pin "2") (pinfunction "P$2_2") (pintype "bidirectional"))
    )
    (net (code "376") (name "Net-(K4C-O)") (class "Default")
      (node (ref "K4") (pin "7") (pinfunction "O_7") (pintype "passive"))
      (node (ref "R279") (pin "1") (pinfunction "P$1_1") (pintype "bidirectional"))
    )
    (net (code "377") (name "Net-(K4C-S)") (class "Default")
      (node (ref "K4") (pin "5") (pinfunction "S_5") (pintype "passive"))
      (node (ref "R278") (pin "1") (pinfunction "P$1_1") (pintype "bidirectional"))
    )
    (net (code "378") (name "Net-(Q2-D)") (class "Default")
      (node (ref "Q2") (pin "3") (pinfunction "D_3") (pintype "passive"))
      (node (ref "T1") (pin "1") (pinfunction "P1P_1") (pintype "passive"))
    )
    (net (code "379") (name "Net-(Q2-G)") (class "Default")
      (node (ref "Q2") (pin "1") (pinfunction "G_1") (pintype "passive"))
      (node (ref "R161") (pin "2") (pinfunction "P$2_2") (pintype "bidirectional"))
    )
    (net (code "380") (name "Net-(Q3-D)") (class "Default")
      (node (ref "Q3") (pin "3") (pinfunction "D_3") (pintype "passive"))
      (node (ref "T1") (pin "3") (pinfunction "P1N_3") (pintype "passive"))
    )
    (net (code "381") (name "Net-(Q3-G)") (class "Default")
      (node (ref "Q3") (pin "1") (pinfunction "G_1") (pintype "passive"))
      (node (ref "R162") (pin "2") (pinfunction "P$2_2") (pintype "bidirectional"))
    )
    (net (code "382") (name "Net-(QG1-OUT)") (class "Default")
      (node (ref "QG1") (pin "3") (pinfunction "OUT_3") (pintype "output"))
      (node (ref "R45") (pin "2") (pinfunction "P$2_2") (pintype "bidirectional"))
    )
    (net (code "383") (name "Net-(R10-P$2)") (class "Default")
      (node (ref "R10") (pin "2") (pinfunction "P$2_2") (pintype "bidirectional"))
      (node (ref "U2") (pin "T2") (pinfunction "PROGRAM_B_2_T2") (pintype "input"))
    )
    (net (code "384") (name "Net-(R12-P$2)") (class "Default")
      (node (ref "R12") (pin "2") (pinfunction "P$2_2") (pintype "bidirectional"))
      (node (ref "U2") (pin "P13") (pinfunction "DONE_2_P13") (pintype "bidirectional"))
    )
    (net (code "385") (name "Net-(R13-P$1)") (class "Default")
      (node (ref "C4") (pin "2") (pinfunction "2_2") (pintype "passive"))
      (node (ref "R13") (pin "1") (pinfunction "P$1_1") (pintype "bidirectional"))
      (node (ref "R131") (pin "2") (pinfunction "P$2_2") (pintype "bidirectional"))
      (node (ref "R80") (pin "2") (pinfunction "P$2_2") (pintype "bidirectional"))
    )
    (net (code "386") (name "Net-(R13-P$2)") (class "Default")
      (node (ref "R13") (pin "2") (pinfunction "P$2_2") (pintype "bidirectional"))
      (node (ref "SV2") (pin "1") (pinfunction "1_1") (pintype "passive"))
    )
    (net (code "387") (name "Net-(R14-P$1)") (class "Default")
      (node (ref "R14") (pin "1") (pinfunction "P$1_1") (pintype "bidirectional"))
      (node (ref "X1") (pin "2") (pinfunction "2_2") (pintype "passive"))
    )
    (net (code "388") (name "Net-(R15-P$2)") (class "Default")
      (node (ref "R15") (pin "2") (pinfunction "P$2_2") (pintype "bidirectional"))
      (node (ref "X1") (pin "3") (pinfunction "3_3") (pintype "passive"))
    )
    (net (code "389") (name "Net-(R41-P$1)") (class "Default")
      (node (ref "R41") (pin "1") (pinfunction "P$1_1") (pintype "bidirectional"))
      (node (ref "U2") (pin "C9") (pinfunction "IO_L34P_GCLK19_0_C9") (pintype "bidirectional"))
    )
    (net (code "390") (name "Net-(R42-P$1)") (class "Default")
      (node (ref "R42") (pin "1") (pinfunction "P$1_1") (pintype "bidirectional"))
      (node (ref "U2") (pin "A9") (pinfunction "IO_L34N_GCLK18_0_A9") (pintype "bidirectional"))
    )
    (net (code "391") (name "Net-(R43-P$1)") (class "Default")
      (node (ref "R43") (pin "1") (pinfunction "P$1_1") (pintype "bidirectional"))
      (node (ref "U2") (pin "B8") (pinfunction "IO_L33P_0_B8") (pintype "bidirectional"))
    )
    (net (code "392") (name "Net-(R46-P$2)") (class "Default")
      (node (ref "C78") (pin "2") (pinfunction "2_2") (pintype "passive"))
      (node (ref "C79") (pin "2") (pinfunction "2_2") (pintype "passive"))
      (node (ref "L7") (pin "2") (pinfunction "2_2") (pintype "passive"))
      (node (ref "R46") (pin "2") (pinfunction "P$2_2") (pintype "bidirectional"))
      (node (ref "R49") (pin "1") (pinfunction "P$1_1") (pintype "bidirectional"))
    )
    (net (code "393") (name "Net-(R51-P$1)") (class "Default")
      (node (ref "C74") (pin "1") (pinfunction "1_1") (pintype "passive"))
      (node (ref "L6") (pin "1") (pinfunction "1_1") (pintype "passive"))
      (node (ref "R51") (pin "1") (pinfunction "P$1_1") (pintype "bidirectional"))
    )
    (net (code "394") (name "Net-(R56-P$1)") (class "Default")
      (node (ref "C100") (pin "2") (pinfunction "2_2") (pintype "passive"))
      (node (ref "R56") (pin "1") (pinfunction "P$1_1") (pintype "bidirectional"))
      (node (ref "R58") (pin "2") (pinfunction "P$2_2") (pintype "bidirectional"))
      (node (ref "R83") (pin "1") (pinfunction "P$1_1") (pintype "bidirectional"))
    )
    (net (code "395") (name "Net-(R57-P$1)") (class "Default")
      (node (ref "C100") (pin "1") (pinfunction "1_1") (pintype "passive"))
      (node (ref "R57") (pin "1") (pinfunction "P$1_1") (pintype "bidirectional"))
      (node (ref "R74") (pin "2") (pinfunction "P$2_2") (pintype "bidirectional"))
      (node (ref "R84") (pin "2") (pinfunction "P$2_2") (pintype "bidirectional"))
    )
    (net (code "396") (name "Net-(R58-P$1)") (class "Default")
      (node (ref "C135") (pin "2") (pinfunction "2_2") (pintype "passive"))
      (node (ref "R58") (pin "1") (pinfunction "P$1_1") (pintype "bidirectional"))
    )
    (net (code "397") (name "Net-(R65-P$2)") (class "Default")
      (node (ref "R65") (pin "2") (pinfunction "P$2_2") (pintype "bidirectional"))
      (node (ref "R78") (pin "1") (pinfunction "P$1_1") (pintype "bidirectional"))
    )
    (net (code "398") (name "Net-(R67-P$2)") (class "Default")
      (node (ref "R67") (pin "2") (pinfunction "P$2_2") (pintype "bidirectional"))
      (node (ref "SV2") (pin "3") (pinfunction "3_3") (pintype "passive"))
    )
    (net (code "399") (name "Net-(R68-P$2)") (class "Default")
      (node (ref "R68") (pin "2") (pinfunction "P$2_2") (pintype "bidirectional"))
      (node (ref "SV2") (pin "5") (pinfunction "5_5") (pintype "passive"))
    )
    (net (code "400") (name "Net-(R69-P$2)") (class "Default")
      (node (ref "R69") (pin "2") (pinfunction "P$2_2") (pintype "bidirectional"))
      (node (ref "SV2") (pin "7") (pinfunction "7_7") (pintype "passive"))
    )
    (net (code "401") (name "Net-(R70-P$2)") (class "Default")
      (node (ref "R70") (pin "2") (pinfunction "P$2_2") (pintype "bidirectional"))
      (node (ref "SV2") (pin "9") (pinfunction "9_9") (pintype "passive"))
    )
    (net (code "402") (name "Net-(R71-P$2)") (class "Default")
      (node (ref "R71") (pin "2") (pinfunction "P$2_2") (pintype "bidirectional"))
      (node (ref "SV2") (pin "11") (pinfunction "11_11") (pintype "passive"))
    )
    (net (code "403") (name "Net-(R72-P$2)") (class "Default")
      (node (ref "R72") (pin "2") (pinfunction "P$2_2") (pintype "bidirectional"))
      (node (ref "SV2") (pin "13") (pinfunction "13_13") (pintype "passive"))
    )
    (net (code "404") (name "Net-(R73-P$2)") (class "Default")
      (node (ref "R73") (pin "2") (pinfunction "P$2_2") (pintype "bidirectional"))
      (node (ref "SV2") (pin "15") (pinfunction "15_15") (pintype "passive"))
    )
    (net (code "405") (name "Net-(R74-P$1)") (class "Default")
      (node (ref "C136") (pin "2") (pinfunction "2_2") (pintype "passive"))
      (node (ref "R74") (pin "1") (pinfunction "P$1_1") (pintype "bidirectional"))
    )
    (net (code "406") (name "Net-(R76-P$2)") (class "Default")
      (node (ref "R76") (pin "2") (pinfunction "P$2_2") (pintype "bidirectional"))
      (node (ref "R77") (pin "1") (pinfunction "P$1_1") (pintype "bidirectional"))
    )
    (net (code "407") (name "Net-(R79-P$2)") (class "Default")
      (node (ref "R79") (pin "2") (pinfunction "P$2_2") (pintype "bidirectional"))
      (node (ref "SV3") (pin "1") (pinfunction "1_1") (pintype "passive"))
    )
    (net (code "408") (name "Net-(R85-P$1)") (class "Default")
      (node (ref "C102") (pin "2") (pinfunction "2_2") (pintype "passive"))
      (node (ref "R85") (pin "1") (pinfunction "P$1_1") (pintype "bidirectional"))
      (node (ref "R91") (pin "2") (pinfunction "P$2_2") (pintype "bidirectional"))
      (node (ref "R94") (pin "1") (pinfunction "P$1_1") (pintype "bidirectional"))
    )
    (net (code "409") (name "Net-(R89-P$2)") (class "Default")
      (node (ref "R89") (pin "2") (pinfunction "P$2_2") (pintype "bidirectional"))
      (node (ref "U2") (pin "T11") (pinfunction "IO_L1N_M0_CMPMISO_2_T11") (pintype "bidirectional"))
    )
    (net (code "410") (name "Net-(R91-P$1)") (class "Default")
      (node (ref "C103") (pin "2") (pinfunction "2_2") (pintype "passive"))
      (node (ref "R91") (pin "1") (pinfunction "P$1_1") (pintype "bidirectional"))
    )
    (net (code "411") (name "Net-(R92-P$1)") (class "Default")
      (node (ref "C113") (pin "2") (pinfunction "2_2") (pintype "passive"))
      (node (ref "R92") (pin "1") (pinfunction "P$1_1") (pintype "bidirectional"))
    )
    (net (code "412") (name "Net-(R97-P$2)") (class "Default")
      (node (ref "R97") (pin "2") (pinfunction "P$2_2") (pintype "bidirectional"))
      (node (ref "SV3") (pin "15") (pinfunction "15_15") (pintype "passive"))
    )
    (net (code "413") (name "Net-(R98-P$2)") (class "Default")
      (node (ref "R98") (pin "2") (pinfunction "P$2_2") (pintype "bidirectional"))
      (node (ref "SV3") (pin "13") (pinfunction "13_13") (pintype "passive"))
    )
    (net (code "414") (name "Net-(R99-P$2)") (class "Default")
      (node (ref "R99") (pin "2") (pinfunction "P$2_2") (pintype "bidirectional"))
      (node (ref "SV3") (pin "11") (pinfunction "11_11") (pintype "passive"))
    )
    (net (code "415") (name "Net-(R100-P$2)") (class "Default")
      (node (ref "R100") (pin "2") (pinfunction "P$2_2") (pintype "bidirectional"))
      (node (ref "SV3") (pin "9") (pinfunction "9_9") (pintype "passive"))
    )
    (net (code "416") (name "Net-(R101-P$2)") (class "Default")
      (node (ref "R101") (pin "2") (pinfunction "P$2_2") (pintype "bidirectional"))
      (node (ref "SV3") (pin "7") (pinfunction "7_7") (pintype "passive"))
    )
    (net (code "417") (name "Net-(R102-P$2)") (class "Default")
      (node (ref "R102") (pin "2") (pinfunction "P$2_2") (pintype "bidirectional"))
      (node (ref "SV3") (pin "5") (pinfunction "5_5") (pintype "passive"))
    )
    (net (code "418") (name "Net-(R103-P$2)") (class "Default")
      (node (ref "R103") (pin "2") (pinfunction "P$2_2") (pintype "bidirectional"))
      (node (ref "SV3") (pin "3") (pinfunction "3_3") (pintype "passive"))
    )
    (net (code "419") (name "Net-(R105-P$1)") (class "Default")
      (node (ref "C102") (pin "1") (pinfunction "1_1") (pintype "passive"))
      (node (ref "R105") (pin "1") (pinfunction "P$1_1") (pintype "bidirectional"))
      (node (ref "R92") (pin "2") (pinfunction "P$2_2") (pintype "bidirectional"))
      (node (ref "R93") (pin "2") (pinfunction "P$2_2") (pintype "bidirectional"))
    )
    (net (code "420") (name "Net-(R107-P$2)") (class "Default")
      (node (ref "C1") (pin "2") (pinfunction "2_2") (pintype "passive"))
      (node (ref "C2") (pin "2") (pinfunction "2_2") (pintype "passive"))
      (node (ref "L13") (pin "2") (pinfunction "2_2") (pintype "passive"))
      (node (ref "R107") (pin "2") (pinfunction "P$2_2") (pintype "bidirectional"))
      (node (ref "R50") (pin "1") (pinfunction "P$1_1") (pintype "bidirectional"))
    )
    (net (code "421") (name "Net-(R108-P$1)") (class "Default")
      (node (ref "R108") (pin "1") (pinfunction "P$1_1") (pintype "bidirectional"))
      (node (ref "SV4") (pin "15") (pinfunction "15_15") (pintype "passive"))
    )
    (net (code "422") (name "Net-(R109-P$1)") (class "Default")
      (node (ref "R109") (pin "1") (pinfunction "P$1_1") (pintype "bidirectional"))
      (node (ref "SV4") (pin "16") (pinfunction "16_16") (pintype "passive"))
    )
    (net (code "423") (name "Net-(R110-P$1)") (class "Default")
      (node (ref "R110") (pin "1") (pinfunction "P$1_1") (pintype "bidirectional"))
      (node (ref "SV4") (pin "14") (pinfunction "14_14") (pintype "passive"))
    )
    (net (code "424") (name "Net-(R113-P$1)") (class "Default")
      (node (ref "C75") (pin "1") (pinfunction "1_1") (pintype "passive"))
      (node (ref "R113") (pin "1") (pinfunction "P$1_1") (pintype "bidirectional"))
      (node (ref "R121") (pin "2") (pinfunction "P$2_2") (pintype "bidirectional"))
    )
    (net (code "425") (name "Net-(R113-P$2)") (class "Default")
      (node (ref "C75") (pin "2") (pinfunction "2_2") (pintype "passive"))
      (node (ref "R113") (pin "2") (pinfunction "P$2_2") (pintype "bidirectional"))
      (node (ref "R126") (pin "2") (pinfunction "P$2_2") (pintype "bidirectional"))
      (node (ref "R71") (pin "1") (pinfunction "P$1_1") (pintype "bidirectional"))
    )
    (net (code "426") (name "Net-(R114-P$1)") (class "Default")
      (node (ref "C89") (pin "1") (pinfunction "1_1") (pintype "passive"))
      (node (ref "R114") (pin "1") (pinfunction "P$1_1") (pintype "bidirectional"))
      (node (ref "R122") (pin "2") (pinfunction "P$2_2") (pintype "bidirectional"))
    )
    (net (code "427") (name "Net-(R114-P$2)") (class "Default")
      (node (ref "C89") (pin "2") (pinfunction "2_2") (pintype "passive"))
      (node (ref "R114") (pin "2") (pinfunction "P$2_2") (pintype "bidirectional"))
      (node (ref "R125") (pin "2") (pinfunction "P$2_2") (pintype "bidirectional"))
      (node (ref "R72") (pin "1") (pinfunction "P$1_1") (pintype "bidirectional"))
    )
    (net (code "428") (name "Net-(R115-P$1)") (class "Default")
      (node (ref "C90") (pin "1") (pinfunction "1_1") (pintype "passive"))
      (node (ref "R115") (pin "1") (pinfunction "P$1_1") (pintype "bidirectional"))
      (node (ref "R123") (pin "2") (pinfunction "P$2_2") (pintype "bidirectional"))
    )
    (net (code "429") (name "Net-(R115-P$2)") (class "Default")
      (node (ref "C90") (pin "2") (pinfunction "2_2") (pintype "passive"))
      (node (ref "R115") (pin "2") (pinfunction "P$2_2") (pintype "bidirectional"))
      (node (ref "R124") (pin "2") (pinfunction "P$2_2") (pintype "bidirectional"))
      (node (ref "R73") (pin "1") (pinfunction "P$1_1") (pintype "bidirectional"))
    )
    (net (code "430") (name "Net-(R116-P$2)") (class "Default")
      (node (ref "C4") (pin "1") (pinfunction "1_1") (pintype "passive"))
      (node (ref "R116") (pin "2") (pinfunction "P$2_2") (pintype "bidirectional"))
      (node (ref "R80") (pin "1") (pinfunction "P$1_1") (pintype "bidirectional"))
    )
    (net (code "431") (name "Net-(R117-P$2)") (class "Default")
      (node (ref "C5") (pin "1") (pinfunction "1_1") (pintype "passive"))
      (node (ref "R117") (pin "2") (pinfunction "P$2_2") (pintype "bidirectional"))
      (node (ref "R81") (pin "1") (pinfunction "P$1_1") (pintype "bidirectional"))
    )
    (net (code "432") (name "Net-(R118-P$2)") (class "Default")
      (node (ref "C6") (pin "1") (pinfunction "1_1") (pintype "passive"))
      (node (ref "R118") (pin "2") (pinfunction "P$2_2") (pintype "bidirectional"))
      (node (ref "R82") (pin "1") (pinfunction "P$1_1") (pintype "bidirectional"))
    )
    (net (code "433") (name "Net-(R119-P$2)") (class "Default")
      (node (ref "C7") (pin "1") (pinfunction "1_1") (pintype "passive"))
      (node (ref "R119") (pin "2") (pinfunction "P$2_2") (pintype "bidirectional"))
      (node (ref "R95") (pin "1") (pinfunction "P$1_1") (pintype "bidirectional"))
    )
    (net (code "434") (name "Net-(R120-P$2)") (class "Default")
      (node (ref "C19") (pin "1") (pinfunction "1_1") (pintype "passive"))
      (node (ref "R120") (pin "2") (pinfunction "P$2_2") (pintype "bidirectional"))
      (node (ref "R96") (pin "1") (pinfunction "P$1_1") (pintype "bidirectional"))
    )
    (net (code "435") (name "Net-(R127-P$2)") (class "Default")
      (node (ref "C19") (pin "2") (pinfunction "2_2") (pintype "passive"))
      (node (ref "R127") (pin "2") (pinfunction "P$2_2") (pintype "bidirectional"))
      (node (ref "R70") (pin "1") (pinfunction "P$1_1") (pintype "bidirectional"))
      (node (ref "R96") (pin "2") (pinfunction "P$2_2") (pintype "bidirectional"))
    )
    (net (code "436") (name "Net-(R128-P$2)") (class "Default")
      (node (ref "C7") (pin "2") (pinfunction "2_2") (pintype "passive"))
      (node (ref "R128") (pin "2") (pinfunction "P$2_2") (pintype "bidirectional"))
      (node (ref "R69") (pin "1") (pinfunction "P$1_1") (pintype "bidirectional"))
      (node (ref "R95") (pin "2") (pinfunction "P$2_2") (pintype "bidirectional"))
    )
    (net (code "437") (name "Net-(R129-P$2)") (class "Default")
      (node (ref "C6") (pin "2") (pinfunction "2_2") (pintype "passive"))
      (node (ref "R129") (pin "2") (pinfunction "P$2_2") (pintype "bidirectional"))
      (node (ref "R68") (pin "1") (pinfunction "P$1_1") (pintype "bidirectional"))
      (node (ref "R82") (pin "2") (pinfunction "P$2_2") (pintype "bidirectional"))
    )
    (net (code "438") (name "Net-(R130-P$2)") (class "Default")
      (node (ref "C5") (pin "2") (pinfunction "2_2") (pintype "passive"))
      (node (ref "R130") (pin "2") (pinfunction "P$2_2") (pintype "bidirectional"))
      (node (ref "R67") (pin "1") (pinfunction "P$1_1") (pintype "bidirectional"))
      (node (ref "R81") (pin "2") (pinfunction "P$2_2") (pintype "bidirectional"))
    )
    (net (code "439") (name "Net-(R135-P$1)") (class "Default")
      (node (ref "C129") (pin "2") (pinfunction "2_2") (pintype "passive"))
      (node (ref "R135") (pin "1") (pinfunction "P$1_1") (pintype "bidirectional"))
    )
    (net (code "440") (name "Net-(R136-P$1)") (class "Default")
      (node (ref "C131") (pin "2") (pinfunction "2_2") (pintype "passive"))
      (node (ref "R136") (pin "1") (pinfunction "P$1_1") (pintype "bidirectional"))
    )
    (net (code "441") (name "Net-(R137-P$1)") (class "Default")
      (node (ref "C132") (pin "2") (pinfunction "2_2") (pintype "passive"))
      (node (ref "R137") (pin "1") (pinfunction "P$1_1") (pintype "bidirectional"))
    )
    (net (code "442") (name "Net-(R138-P$1)") (class "Default")
      (node (ref "C130") (pin "2") (pinfunction "2_2") (pintype "passive"))
      (node (ref "R138") (pin "1") (pinfunction "P$1_1") (pintype "bidirectional"))
    )
    (net (code "443") (name "Net-(R157-P$2)") (class "Default")
      (node (ref "C149") (pin "1") (pinfunction "1_1") (pintype "passive"))
      (node (ref "R157") (pin "2") (pinfunction "P$2_2") (pintype "bidirectional"))
      (node (ref "R158") (pin "1") (pinfunction "P$1_1") (pintype "bidirectional"))
    )
    (net (code "444") (name "Net-(R169-P$1)") (class "Default")
      (node (ref "R169") (pin "1") (pinfunction "P$1_1") (pintype "bidirectional"))
      (node (ref "U2") (pin "N6") (pinfunction "IO_L64N_D9_2_N6") (pintype "bidirectional"))
    )
    (net (code "445") (name "Net-(R181-P$1)") (class "Default")
      (node (ref "C179") (pin "1") (pinfunction "1_1") (pintype "passive"))
      (node (ref "R181") (pin "1") (pinfunction "P$1_1") (pintype "bidirectional"))
      (node (ref "R62") (pin "2") (pinfunction "P$2_2") (pintype "bidirectional"))
    )
    (net (code "446") (name "Net-(R182-P$1)") (class "Default")
      (node (ref "C180") (pin "1") (pinfunction "1_1") (pintype "passive"))
      (node (ref "R182") (pin "1") (pinfunction "P$1_1") (pintype "bidirectional"))
      (node (ref "R64") (pin "2") (pinfunction "P$2_2") (pintype "bidirectional"))
    )
    (net (code "447") (name "Net-(R195-P$2)") (class "Default")
      (node (ref "R195") (pin "2") (pinfunction "P$2_2") (pintype "bidirectional"))
      (node (ref "R197") (pin "1") (pinfunction "P$1_1") (pintype "bidirectional"))
    )
    (net (code "448") (name "Net-(R199-P$2)") (class "Default")
      (node (ref "C200") (pin "1") (pinfunction "1_1") (pintype "passive"))
      (node (ref "R199") (pin "2") (pinfunction "P$2_2") (pintype "bidirectional"))
      (node (ref "R200") (pin "1") (pinfunction "P$1_1") (pintype "bidirectional"))
    )
    (net (code "449") (name "Net-(R204-P$1)") (class "Default")
      (node (ref "R204") (pin "1") (pinfunction "P$1_1") (pintype "bidirectional"))
      (node (ref "SV5") (pin "3") (pinfunction "3_3") (pintype "passive"))
    )
    (net (code "450") (name "Net-(R205-P$1)") (class "Default")
      (node (ref "R205") (pin "1") (pinfunction "P$1_1") (pintype "bidirectional"))
      (node (ref "SV5") (pin "1") (pinfunction "1_1") (pintype "passive"))
    )
    (net (code "451") (name "Net-(R209-P$1)") (class "Default")
      (node (ref "R209") (pin "1") (pinfunction "P$1_1") (pintype "bidirectional"))
      (node (ref "R210") (pin "2") (pinfunction "P$2_2") (pintype "bidirectional"))
    )
    (net (code "452") (name "Net-(R221-P$1)") (class "Default")
      (node (ref "C212") (pin "2") (pinfunction "2_2") (pintype "passive"))
      (node (ref "C214") (pin "1") (pinfunction "1_1") (pintype "passive"))
      (node (ref "C228") (pin "1") (pinfunction "1_1") (pintype "passive"))
      (node (ref "R221") (pin "1") (pinfunction "P$1_1") (pintype "bidirectional"))
      (node (ref "R222") (pin "2") (pinfunction "P$2_2") (pintype "bidirectional"))
      (node (ref "R242") (pin "2") (pinfunction "P$2_2") (pintype "bidirectional"))
    )
    (net (code "453") (name "Net-(R221-P$2)") (class "Default")
      (node (ref "R221") (pin "2") (pinfunction "P$2_2") (pintype "bidirectional"))
      (node (ref "R223") (pin "1") (pinfunction "P$1_1") (pintype "bidirectional"))
    )
    (net (code "454") (name "Net-(R222-P$1)") (class "Default")
      (node (ref "R222") (pin "1") (pinfunction "P$1_1") (pintype "bidirectional"))
      (node (ref "R224") (pin "2") (pinfunction "P$2_2") (pintype "bidirectional"))
    )
    (net (code "455") (name "Net-(R225-P$1)") (class "Default")
      (node (ref "C215") (pin "2") (pinfunction "2_2") (pintype "passive"))
      (node (ref "C217") (pin "1") (pinfunction "1_1") (pintype "passive"))
      (node (ref "C229") (pin "1") (pinfunction "1_1") (pintype "passive"))
      (node (ref "R225") (pin "1") (pinfunction "P$1_1") (pintype "bidirectional"))
      (node (ref "R226") (pin "2") (pinfunction "P$2_2") (pintype "bidirectional"))
      (node (ref "R243") (pin "2") (pinfunction "P$2_2") (pintype "bidirectional"))
    )
    (net (code "456") (name "Net-(R225-P$2)") (class "Default")
      (node (ref "R225") (pin "2") (pinfunction "P$2_2") (pintype "bidirectional"))
      (node (ref "R227") (pin "1") (pinfunction "P$1_1") (pintype "bidirectional"))
    )
    (net (code "457") (name "Net-(R226-P$1)") (class "Default")
      (node (ref "R226") (pin "1") (pinfunction "P$1_1") (pintype "bidirectional"))
      (node (ref "R228") (pin "2") (pinfunction "P$2_2") (pintype "bidirectional"))
    )
    (net (code "458") (name "Net-(R230-P$1)") (class "Default")
      (node (ref "C220") (pin "2") (pinfunction "2_2") (pintype "passive"))
      (node (ref "L12") (pin "1") (pinfunction "1_1") (pintype "passive"))
      (node (ref "R230") (pin "1") (pinfunction "P$1_1") (pintype "bidirectional"))
    )
    (net (code "459") (name "Net-(R232-P$1)") (class "Default")
      (node (ref "C224") (pin "1") (pinfunction "1_1") (pintype "passive"))
      (node (ref "R232") (pin "1") (pinfunction "P$1_1") (pintype "bidirectional"))
      (node (ref "T2") (pin "3") (pinfunction "C_3") (pintype "passive"))
      (node (ref "T3") (pin "3") (pinfunction "C_3") (pintype "passive"))
      (node (ref "T4") (pin "3") (pinfunction "C_3") (pintype "passive"))
      (node (ref "T8") (pin "3") (pinfunction "C_3") (pintype "passive"))
    )
    (net (code "460") (name "Net-(R233-P$2)") (class "Default")
      (node (ref "R233") (pin "2") (pinfunction "P$2_2") (pintype "bidirectional"))
      (node (ref "T3") (pin "1") (pinfunction "B_1") (pintype "passive"))
      (node (ref "T6") (pin "B") (pinfunction "B_B") (pintype "passive"))
    )
    (net (code "461") (name "Net-(R234-P$1)") (class "Default")
      (node (ref "R234") (pin "1") (pinfunction "P$1_1") (pintype "bidirectional"))
      (node (ref "T4") (pin "1") (pinfunction "B_1") (pintype "passive"))
      (node (ref "T7") (pin "B") (pinfunction "B_B") (pintype "passive"))
    )
    (net (code "462") (name "Net-(R235-P$1)") (class "Default")
      (node (ref "R235") (pin "1") (pinfunction "P$1_1") (pintype "bidirectional"))
      (node (ref "T2") (pin "1") (pinfunction "B_1") (pintype "passive"))
      (node (ref "T5") (pin "B") (pinfunction "B_B") (pintype "passive"))
    )
    (net (code "463") (name "Net-(R236-P$2)") (class "Default")
      (node (ref "R236") (pin "2") (pinfunction "P$2_2") (pintype "bidirectional"))
      (node (ref "T8") (pin "1") (pinfunction "B_1") (pintype "passive"))
      (node (ref "T9") (pin "B") (pinfunction "B_B") (pintype "passive"))
    )
    (net (code "464") (name "Net-(R240-P$2)") (class "Default")
      (node (ref "R240") (pin "2") (pinfunction "P$2_2") (pintype "bidirectional"))
      (node (ref "X2") (pin "2") (pinfunction "2_2") (pintype "passive"))
    )
    (net (code "465") (name "Net-(R241-P$2)") (class "Default")
      (node (ref "R241") (pin "2") (pinfunction "P$2_2") (pintype "bidirectional"))
      (node (ref "X2") (pin "1") (pinfunction "1_1") (pintype "passive"))
    )
    (net (code "466") (name "Net-(R245-P$1)") (class "Default")
      (node (ref "R245") (pin "1") (pinfunction "P$1_1") (pintype "bidirectional"))
      (node (ref "R246") (pin "2") (pinfunction "P$2_2") (pintype "bidirectional"))
    )
    (net (code "467") (name "Net-(R257-P$1)") (class "Default")
      (node (ref "C237") (pin "2") (pinfunction "2_2") (pintype "passive"))
      (node (ref "C239") (pin "1") (pinfunction "1_1") (pintype "passive"))
      (node (ref "C253") (pin "1") (pinfunction "1_1") (pintype "passive"))
      (node (ref "R257") (pin "1") (pinfunction "P$1_1") (pintype "bidirectional"))
      (node (ref "R258") (pin "2") (pinfunction "P$2_2") (pintype "bidirectional"))
      (node (ref "R278") (pin "2") (pinfunction "P$2_2") (pintype "bidirectional"))
    )
    (net (code "468") (name "Net-(R257-P$2)") (class "Default")
      (node (ref "R257") (pin "2") (pinfunction "P$2_2") (pintype "bidirectional"))
      (node (ref "R259") (pin "1") (pinfunction "P$1_1") (pintype "bidirectional"))
    )
    (net (code "469") (name "Net-(R258-P$1)") (class "Default")
      (node (ref "R258") (pin "1") (pinfunction "P$1_1") (pintype "bidirectional"))
      (node (ref "R260") (pin "2") (pinfunction "P$2_2") (pintype "bidirectional"))
    )
    (net (code "470") (name "Net-(R261-P$1)") (class "Default")
      (node (ref "C240") (pin "2") (pinfunction "2_2") (pintype "passive"))
      (node (ref "C242") (pin "1") (pinfunction "1_1") (pintype "passive"))
      (node (ref "C254") (pin "1") (pinfunction "1_1") (pintype "passive"))
      (node (ref "R261") (pin "1") (pinfunction "P$1_1") (pintype "bidirectional"))
      (node (ref "R262") (pin "2") (pinfunction "P$2_2") (pintype "bidirectional"))
      (node (ref "R279") (pin "2") (pinfunction "P$2_2") (pintype "bidirectional"))
    )
    (net (code "471") (name "Net-(R261-P$2)") (class "Default")
      (node (ref "R261") (pin "2") (pinfunction "P$2_2") (pintype "bidirectional"))
      (node (ref "R263") (pin "1") (pinfunction "P$1_1") (pintype "bidirectional"))
    )
    (net (code "472") (name "Net-(R262-P$1)") (class "Default")
      (node (ref "R262") (pin "1") (pinfunction "P$1_1") (pintype "bidirectional"))
      (node (ref "R264") (pin "2") (pinfunction "P$2_2") (pintype "bidirectional"))
    )
    (net (code "473") (name "Net-(R266-P$1)") (class "Default")
      (node (ref "C245") (pin "2") (pinfunction "2_2") (pintype "passive"))
      (node (ref "L14") (pin "1") (pinfunction "1_1") (pintype "passive"))
      (node (ref "R266") (pin "1") (pinfunction "P$1_1") (pintype "bidirectional"))
    )
    (net (code "474") (name "Net-(R268-P$1)") (class "Default")
      (node (ref "C249") (pin "1") (pinfunction "1_1") (pintype "passive"))
      (node (ref "R268") (pin "1") (pinfunction "P$1_1") (pintype "bidirectional"))
      (node (ref "T10") (pin "3") (pinfunction "C_3") (pintype "passive"))
      (node (ref "T11") (pin "3") (pinfunction "C_3") (pintype "passive"))
      (node (ref "T14") (pin "3") (pinfunction "C_3") (pintype "passive"))
      (node (ref "T16") (pin "3") (pinfunction "C_3") (pintype "passive"))
    )
    (net (code "475") (name "Net-(R269-P$2)") (class "Default")
      (node (ref "R269") (pin "2") (pinfunction "P$2_2") (pintype "bidirectional"))
      (node (ref "T11") (pin "1") (pinfunction "B_1") (pintype "passive"))
      (node (ref "T13") (pin "B") (pinfunction "B_B") (pintype "passive"))
    )
    (net (code "476") (name "Net-(R270-P$1)") (class "Default")
      (node (ref "R270") (pin "1") (pinfunction "P$1_1") (pintype "bidirectional"))
      (node (ref "T14") (pin "1") (pinfunction "B_1") (pintype "passive"))
      (node (ref "T15") (pin "B") (pinfunction "B_B") (pintype "passive"))
    )
    (net (code "477") (name "Net-(R271-P$1)") (class "Default")
      (node (ref "R271") (pin "1") (pinfunction "P$1_1") (pintype "bidirectional"))
      (node (ref "T10") (pin "1") (pinfunction "B_1") (pintype "passive"))
      (node (ref "T12") (pin "B") (pinfunction "B_B") (pintype "passive"))
    )
    (net (code "478") (name "Net-(R272-P$2)") (class "Default")
      (node (ref "R272") (pin "2") (pinfunction "P$2_2") (pintype "bidirectional"))
      (node (ref "T16") (pin "1") (pinfunction "B_1") (pintype "passive"))
      (node (ref "T17") (pin "B") (pinfunction "B_B") (pintype "passive"))
    )
    (net (code "479") (name "Net-(R276-P$2)") (class "Default")
      (node (ref "R276") (pin "2") (pinfunction "P$2_2") (pintype "bidirectional"))
      (node (ref "X3") (pin "2") (pinfunction "2_2") (pintype "passive"))
    )
    (net (code "480") (name "Net-(R277-P$2)") (class "Default")
      (node (ref "R277") (pin "2") (pinfunction "P$2_2") (pintype "bidirectional"))
      (node (ref "X3") (pin "1") (pinfunction "1_1") (pintype "passive"))
    )
    (net (code "481") (name "Net-(R284-P$1)") (class "Default")
      (node (ref "R284") (pin "1") (pinfunction "P$1_1") (pintype "bidirectional"))
      (node (ref "R285") (pin "1") (pinfunction "P$1_1") (pintype "bidirectional"))
      (node (ref "R286") (pin "2") (pinfunction "P$2_2") (pintype "bidirectional"))
    )
    (net (code "482") (name "Net-(R286-P$1)") (class "Default")
      (node (ref "R286") (pin "1") (pinfunction "P$1_1") (pintype "bidirectional"))
      (node (ref "R287") (pin "2") (pinfunction "P$2_2") (pintype "bidirectional"))
      (node (ref "R293") (pin "1") (pinfunction "P$1_1") (pintype "bidirectional"))
    )
    (net (code "483") (name "Net-(R287-P$1)") (class "Default")
      (node (ref "R287") (pin "1") (pinfunction "P$1_1") (pintype "bidirectional"))
      (node (ref "R288") (pin "2") (pinfunction "P$2_2") (pintype "bidirectional"))
      (node (ref "R294") (pin "1") (pinfunction "P$1_1") (pintype "bidirectional"))
    )
    (net (code "484") (name "Net-(R288-P$1)") (class "Default")
      (node (ref "R288") (pin "1") (pinfunction "P$1_1") (pintype "bidirectional"))
      (node (ref "R289") (pin "2") (pinfunction "P$2_2") (pintype "bidirectional"))
      (node (ref "R295") (pin "1") (pinfunction "P$1_1") (pintype "bidirectional"))
    )
    (net (code "485") (name "Net-(R289-P$1)") (class "Default")
      (node (ref "R289") (pin "1") (pinfunction "P$1_1") (pintype "bidirectional"))
      (node (ref "R290") (pin "2") (pinfunction "P$2_2") (pintype "bidirectional"))
      (node (ref "R296") (pin "1") (pinfunction "P$1_1") (pintype "bidirectional"))
    )
    (net (code "486") (name "Net-(R290-P$1)") (class "Default")
      (node (ref "R290") (pin "1") (pinfunction "P$1_1") (pintype "bidirectional"))
      (node (ref "R291") (pin "2") (pinfunction "P$2_2") (pintype "bidirectional"))
      (node (ref "R297") (pin "1") (pinfunction "P$1_1") (pintype "bidirectional"))
    )
    (net (code "487") (name "Net-(R291-P$1)") (class "Default")
      (node (ref "R291") (pin "1") (pinfunction "P$1_1") (pintype "bidirectional"))
      (node (ref "R292") (pin "2") (pinfunction "P$2_2") (pintype "bidirectional"))
      (node (ref "R298") (pin "1") (pinfunction "P$1_1") (pintype "bidirectional"))
    )
    (net (code "488") (name "Net-(R292-P$1)") (class "Default")
      (node (ref "R292") (pin "1") (pinfunction "P$1_1") (pintype "bidirectional"))
      (node (ref "R299") (pin "2") (pinfunction "P$2_2") (pintype "bidirectional"))
    )
    (net (code "489") (name "Net-(T1-S1N)") (class "Default")
      (node (ref "D1") (pin "A") (pinfunction "A_A") (pintype "passive"))
      (node (ref "D4") (pin "C") (pinfunction "C_C") (pintype "passive"))
      (node (ref "T1") (pin "7") (pinfunction "S1N_7") (pintype "passive"))
    )
    (net (code "490") (name "Net-(T1-S1P)") (class "Default")
      (node (ref "D2") (pin "A") (pinfunction "A_A") (pintype "passive"))
      (node (ref "D3") (pin "C") (pinfunction "C_C") (pintype "passive"))
      (node (ref "T1") (pin "8") (pinfunction "S1P_8") (pintype "passive"))
    )
    (net (code "491") (name "Net-(T1-S2N)") (class "Default")
      (node (ref "D6") (pin "A") (pinfunction "A_A") (pintype "passive"))
      (node (ref "T1") (pin "6") (pinfunction "S2N_6") (pintype "passive"))
    )
    (net (code "492") (name "Net-(T1-S2P)") (class "Default")
      (node (ref "D5") (pin "A") (pinfunction "A_A") (pintype "passive"))
      (node (ref "T1") (pin "5") (pinfunction "S2P_5") (pintype "passive"))
    )
    (net (code "493") (name "Net-(U2F-TCK)") (class "Default")
      (node (ref "SV1") (pin "6") (pinfunction "6_6") (pintype "passive"))
      (node (ref "U2") (pin "C14") (pinfunction "TCK_C14") (pintype "input"))
    )
    (net (code "494") (name "Net-(U2F-TDI)") (class "Default")
      (node (ref "SV1") (pin "10") (pinfunction "10_10") (pintype "passive"))
      (node (ref "U2") (pin "C12") (pinfunction "TDI_C12") (pintype "input"))
    )
    (net (code "495") (name "Net-(U2F-TDO)") (class "Default")
      (node (ref "SV1") (pin "8") (pinfunction "8_8") (pintype "passive"))
      (node (ref "U2") (pin "E14") (pinfunction "TDO_E14") (pintype "output"))
    )
    (net (code "496") (name "Net-(U2F-TMS)") (class "Default")
      (node (ref "SV1") (pin "4") (pinfunction "4_4") (pintype "passive"))
      (node (ref "U2") (pin "A15") (pinfunction "TMS_A15") (pintype "input"))
    )
    (net (code "497") (name "ODT") (class "Default")
      (node (ref "IC26") (pin "G1") (pinfunction "ODT_G1") (pintype "input"))
      (node (ref "U2") (pin "L5") (pinfunction "IO_L45N_M3ODT_3_L5") (pintype "bidirectional"))
    )
    (net (code "498") (name "OFFSETCH0") (class "Default")
      (node (ref "C182") (pin "1") (pinfunction "1_1") (pintype "passive"))
      (node (ref "L14") (pin "2") (pinfunction "2_2") (pintype "passive"))
      (node (ref "R183") (pin "2") (pinfunction "P$2_2") (pintype "bidirectional"))
    )
    (net (code "499") (name "OFFSETCH1") (class "Default")
      (node (ref "C183") (pin "1") (pinfunction "1_1") (pintype "passive"))
      (node (ref "L12") (pin "2") (pinfunction "2_2") (pintype "passive"))
      (node (ref "R184") (pin "2") (pinfunction "P$2_2") (pintype "bidirectional"))
    )
    (net (code "500") (name "OUTPUTCH0") (class "Default")
      (node (ref "C61") (pin "1") (pinfunction "1_1") (pintype "passive"))
      (node (ref "IC5") (pin "6") (pinfunction "VIN_6") (pintype "bidirectional"))
      (node (ref "R273") (pin "1") (pinfunction "P$1_1") (pintype "bidirectional"))
    )
    (net (code "501") (name "OUTPUTCH1") (class "Default")
      (node (ref "C62") (pin "1") (pinfunction "1_1") (pintype "passive"))
      (node (ref "IC6") (pin "6") (pinfunction "VIN_6") (pintype "bidirectional"))
      (node (ref "R237") (pin "1") (pinfunction "P$1_1") (pintype "bidirectional"))
    )
    (net (code "502") (name "PWMEXVO") (class "Default")
      (node (ref "R188") (pin "2") (pinfunction "P$2_2") (pintype "bidirectional"))
      (node (ref "U2") (pin "D11") (pinfunction "IO_L66P_SCP1_0_D11") (pintype "bidirectional"))
    )
    (net (code "503") (name "PWMLA") (class "Default")
      (node (ref "R200") (pin "2") (pinfunction "P$2_2") (pintype "bidirectional"))
      (node (ref "U2") (pin "E12") (pinfunction "IO_L1N_A24_VREF_1_E12") (pintype "bidirectional"))
    )
    (net (code "504") (name "PWMLAVIO") (class "Default")
      (node (ref "R187") (pin "2") (pinfunction "P$2_2") (pintype "bidirectional"))
      (node (ref "U2") (pin "D12") (pinfunction "IO_L66N_SCP0_0_D12") (pintype "bidirectional"))
    )
    (net (code "505") (name "PWMOFFS0") (class "Default")
      (node (ref "R181") (pin "2") (pinfunction "P$2_2") (pintype "bidirectional"))
      (node (ref "U2") (pin "C10") (pinfunction "IO_L37N_GCLK12_0_C10") (pintype "bidirectional"))
    )
    (net (code "506") (name "PWMOFFS1") (class "Default")
      (node (ref "R182") (pin "2") (pinfunction "P$2_2") (pintype "bidirectional"))
      (node (ref "U2") (pin "C11") (pinfunction "IO_L39P_0_C11") (pintype "bidirectional"))
    )
    (net (code "507") (name "RASN") (class "Default")
      (node (ref "IC26") (pin "F3") (pinfunction "RAS#_F3") (pintype "input"))
      (node (ref "U2") (pin "J6") (pinfunction "IO_L43P_GCLK23_M3RASN_3_J6") (pintype "bidirectional"))
    )
    (net (code "508") (name "RSTN") (class "Default")
      (node (ref "IC26") (pin "N2") (pinfunction "RST#_N2") (pintype "input"))
      (node (ref "R4") (pin "2") (pinfunction "P$2_2") (pintype "bidirectional"))
      (node (ref "U2") (pin "E4") (pinfunction "IO_L54P_M3RESET_3_E4") (pintype "bidirectional"))
    )
    (net (code "509") (name "SK") (class "Default")
      (node (ref "IC3") (pin "5") (pinfunction "A4_5") (pintype "input"))
      (node (ref "R38") (pin "1") (pinfunction "P$1_1") (pintype "bidirectional"))
    )
    (net (code "510") (name "SPICHAIN") (class "Default")
      (node (ref "IC37") (pin "9") (pinfunction "QH*_9") (pintype "tri_state"))
      (node (ref "IC42") (pin "14") (pinfunction "SER_14") (pintype "input"))
    )
    (net (code "511") (name "SPICHAINB") (class "Default")
      (node (ref "IC42") (pin "9") (pinfunction "QH*_9") (pintype "tri_state"))
    )
    (net (code "512") (name "SPICLK") (class "Default")
      (node (ref "IC37") (pin "11") (pinfunction "SCK_11") (pintype "input"))
      (node (ref "IC42") (pin "11") (pinfunction "SCK_11") (pintype "input"))
      (node (ref "U2") (pin "A13") (pinfunction "IO_L63N_SCP6_0_A13") (pintype "bidirectional"))
    )
    (net (code "513") (name "SPICS") (class "Default")
      (node (ref "IC37") (pin "12") (pinfunction "RCK_12") (pintype "input"))
      (node (ref "IC42") (pin "12") (pinfunction "RCK_12") (pintype "input"))
      (node (ref "U2") (pin "B14") (pinfunction "IO_L65P_SCP3_0_B14") (pintype "bidirectional"))
    )
    (net (code "514") (name "SPIDI") (class "Default")
      (node (ref "IC37") (pin "14") (pinfunction "SER_14") (pintype "input"))
      (node (ref "U2") (pin "A14") (pinfunction "IO_L65N_SCP2_0_A14") (pintype "bidirectional"))
    )
    (net (code "515") (name "VCCDDR3") (class "Default")
      (node (ref "C10") (pin "1") (pinfunction "1_1") (pintype "passive"))
      (node (ref "C11") (pin "1") (pinfunction "1_1") (pintype "passive"))
      (node (ref "C12") (pin "1") (pinfunction "1_1") (pintype "passive"))
      (node (ref "C13") (pin "1") (pinfunction "1_1") (pintype "passive"))
      (node (ref "C14") (pin "1") (pinfunction "1_1") (pintype "passive"))
      (node (ref "C15") (pin "1") (pinfunction "1_1") (pintype "passive"))
      (node (ref "C16") (pin "1") (pinfunction "1_1") (pintype "passive"))
      (node (ref "C17") (pin "1") (pinfunction "1_1") (pintype "passive"))
      (node (ref "C18") (pin "1") (pinfunction "1_1") (pintype "passive"))
      (node (ref "C8") (pin "1") (pinfunction "1_1") (pintype "passive"))
      (node (ref "C9") (pin "1") (pinfunction "1_1") (pintype "passive"))
      (node (ref "IC26") (pin "A2") (pinfunction "VCC_A2") (pintype "power_in"))
      (node (ref "IC26") (pin "A9") (pinfunction "VCC_A9") (pintype "power_in"))
      (node (ref "IC26") (pin "B9") (pinfunction "VCCQ_B9") (pintype "power_in"))
      (node (ref "IC26") (pin "C1") (pinfunction "VCCQ_C1") (pintype "power_in"))
      (node (ref "IC26") (pin "D7") (pinfunction "VCC_D7") (pintype "power_in"))
      (node (ref "IC26") (pin "E2") (pinfunction "VCCQ_E2") (pintype "power_in"))
      (node (ref "IC26") (pin "E9") (pinfunction "VCCQ_E9") (pintype "power_in"))
      (node (ref "IC26") (pin "G2") (pinfunction "VCC_G2") (pintype "power_in"))
      (node (ref "IC26") (pin "G8") (pinfunction "VCC_G8") (pintype "power_in"))
      (node (ref "IC26") (pin "K1") (pinfunction "VCC_K1") (pintype "power_in"))
      (node (ref "IC26") (pin "K9") (pinfunction "VCC_K9") (pintype "power_in"))
      (node (ref "IC26") (pin "M1") (pinfunction "VCC_M1") (pintype "power_in"))
      (node (ref "IC26") (pin "M9") (pinfunction "VCC_M9") (pintype "power_in"))
      (node (ref "R1") (pin "2") (pinfunction "P$2_2") (pintype "bidirectional"))
      (node (ref "R50") (pin "2") (pinfunction "P$2_2") (pintype "bidirectional"))
      (node (ref "U2") (pin "D2") (pinfunction "VCCO_3_D2") (pintype "input"))
      (node (ref "U2") (pin "G4") (pinfunction "VCCO_3_G4") (pintype "input"))
      (node (ref "U2") (pin "J2") (pinfunction "VCCO_3_J2") (pintype "input"))
      (node (ref "U2") (pin "K4") (pinfunction "VCCO_3_K4") (pintype "input"))
      (node (ref "U2") (pin "N2") (pinfunction "VCCO_3_N2") (pintype "input"))
    )
    (net (code "516") (name "VCCINT") (class "Default")
      (node (ref "C21") (pin "2") (pinfunction "2_2") (pintype "passive"))
      (node (ref "C29") (pin "1") (pinfunction "1_1") (pintype "passive"))
      (node (ref "C30") (pin "1") (pinfunction "1_1") (pintype "passive"))
      (node (ref "C31") (pin "1") (pinfunction "1_1") (pintype "passive"))
      (node (ref "C32") (pin "1") (pinfunction "1_1") (pintype "passive"))
      (node (ref "R49") (pin "2") (pinfunction "P$2_2") (pintype "bidirectional"))
      (node (ref "U2") (pin "G7") (pinfunction "VCCINT_G7") (pintype "input"))
      (node (ref "U2") (pin "G9") (pinfunction "VCCINT_G9") (pintype "input"))
      (node (ref "U2") (pin "H10") (pinfunction "VCCINT_H10") (pintype "input"))
      (node (ref "U2") (pin "H8") (pinfunction "VCCINT_H8") (pintype "input"))
      (node (ref "U2") (pin "J7") (pinfunction "VCCINT_J7") (pintype "input"))
      (node (ref "U2") (pin "J9") (pinfunction "VCCINT_J9") (pintype "input"))
      (node (ref "U2") (pin "K10") (pinfunction "VCCINT_K10") (pintype "input"))
      (node (ref "U2") (pin "K8") (pinfunction "VCCINT_K8") (pintype "input"))
    )
    (net (code "517") (name "VCCIO") (class "Default")
      (node (ref "C36") (pin "1") (pinfunction "1_1") (pintype "passive"))
      (node (ref "C44") (pin "1") (pinfunction "1_1") (pintype "passive"))
      (node (ref "C45") (pin "1") (pinfunction "1_1") (pintype "passive"))
      (node (ref "C50") (pin "1") (pinfunction "1_1") (pintype "passive"))
      (node (ref "C51") (pin "1") (pinfunction "1_1") (pintype "passive"))
      (node (ref "C52") (pin "1") (pinfunction "1_1") (pintype "passive"))
      (node (ref "C54") (pin "1") (pinfunction "1_1") (pintype "passive"))
      (node (ref "IC3") (pin "1") (pinfunction "VDD1_1") (pintype "power_in"))
      (node (ref "IC4") (pin "12") (pinfunction "VCCIO_12") (pintype "power_in"))
      (node (ref "IC4") (pin "24") (pinfunction "VCCIO_24") (pintype "power_in"))
      (node (ref "IC4") (pin "39") (pinfunction "VCCD_39") (pintype "power_in"))
      (node (ref "IC4") (pin "46") (pinfunction "VCCIO_46") (pintype "power_in"))
      (node (ref "IC8") (pin "6") (pinfunction "ORG_6") (pintype "input"))
      (node (ref "IC8") (pin "8") (pinfunction "VCC_8") (pintype "power_in"))
      (node (ref "L1") (pin "2") (pinfunction "2_2") (pintype "passive"))
      (node (ref "L3") (pin "2") (pinfunction "2_2") (pintype "passive"))
      (node (ref "R16") (pin "2") (pinfunction "P$2_2") (pintype "bidirectional"))
      (node (ref "R19") (pin "2") (pinfunction "P$2_2") (pintype "bidirectional"))
      (node (ref "R20") (pin "2") (pinfunction "P$2_2") (pintype "bidirectional"))
      (node (ref "R21") (pin "2") (pinfunction "P$2_2") (pintype "bidirectional"))
    )
    (net (code "518") (name "VREFDDR") (class "Default")
      (node (ref "C142") (pin "2") (pinfunction "2_2") (pintype "passive"))
      (node (ref "C143") (pin "2") (pinfunction "2_2") (pintype "passive"))
      (node (ref "C144") (pin "2") (pinfunction "2_2") (pintype "passive"))
      (node (ref "C20") (pin "2") (pinfunction "2_2") (pintype "passive"))
      (node (ref "IC26") (pin "E1") (pinfunction "VREFDQ_E1") (pintype "bidirectional"))
      (node (ref "IC26") (pin "J8") (pinfunction "VREFCA_J8") (pintype "bidirectional"))
      (node (ref "R1") (pin "1") (pinfunction "P$1_1") (pintype "bidirectional"))
      (node (ref "R2") (pin "2") (pinfunction "P$2_2") (pintype "bidirectional"))
      (node (ref "U2") (pin "A3") (pinfunction "IO_L83N_VREF_3_A3") (pintype "bidirectional"))
      (node (ref "U2") (pin "M3") (pinfunction "IO_L1N_VREF_3_M3") (pintype "bidirectional"))
    )
    (net (code "519") (name "WEN") (class "Default")
      (node (ref "IC26") (pin "H3") (pinfunction "WE#_H3") (pintype "input"))
      (node (ref "U2") (pin "C1") (pinfunction "IO_L50P_M3WE_3_C1") (pintype "bidirectional"))
    )
    (net (code "520") (name "unconnected-(IC4-AC0{slash}TXDEN{slash}GPIOH0{slash}CS#{slash}SCLK-Pad21)") (class "Default")
      (node (ref "IC4") (pin "21") (pinfunction "AC0/TXDEN/GPIOH0/CS#/SCLK_21") (pintype "bidirectional"))
    )
    (net (code "521") (name "unconnected-(IC4-AC1{slash}GPIOH1{slash}A0{slash}SS_N-Pad25)") (class "Default")
      (node (ref "IC4") (pin "25") (pinfunction "AC1/GPIOH1/A0/SS_N_25") (pintype "bidirectional"))
    )
    (net (code "522") (name "unconnected-(IC4-AC2{slash}RD#{slash}MISO-Pad26)") (class "Default")
      (node (ref "IC4") (pin "26") (pinfunction "AC2/RD#/MISO_26") (pintype "bidirectional"))
    )
    (net (code "523") (name "unconnected-(IC4-AC3{slash}RXLED{slash}GPIOH3{slash}WR#-Pad27)") (class "Default")
      (node (ref "IC4") (pin "27") (pinfunction "AC3/RXLED/GPIOH3/WR#_27") (pintype "bidirectional"))
    )
    (net (code "524") (name "unconnected-(IC4-AC4{slash}TXLED{slash}GPIOH4{slash}SIWU#-Pad28)") (class "Default")
      (node (ref "IC4") (pin "28") (pinfunction "AC4/TXLED/GPIOH4/SIWU#_28") (pintype "bidirectional"))
    )
    (net (code "525") (name "unconnected-(IC4-AC5{slash}GPIOH5-Pad29)") (class "Default")
      (node (ref "IC4") (pin "29") (pinfunction "AC5/GPIOH5_29") (pintype "bidirectional"))
    )
    (net (code "526") (name "unconnected-(IC4-AC6-Pad30)") (class "Default")
      (node (ref "IC4") (pin "30") (pinfunction "AC6_30") (pintype "bidirectional"))
    )
    (net (code "527") (name "unconnected-(IC4-AC7{slash}PWRSAV#-Pad31)") (class "Default")
      (node (ref "IC4") (pin "31") (pinfunction "AC7/PWRSAV#_31") (pintype "bidirectional"))
    )
    (net (code "528") (name "unconnected-(IC4-AC8-Pad32)") (class "Default")
      (node (ref "IC4") (pin "32") (pinfunction "AC8_32") (pintype "bidirectional"))
    )
    (net (code "529") (name "unconnected-(IC4-AC9-Pad33)") (class "Default")
      (node (ref "IC4") (pin "33") (pinfunction "AC9_33") (pintype "bidirectional"))
    )
    (net (code "530") (name "unconnected-(IC4-AD6{slash}DCD#{slash}GPIOL2-Pad19)") (class "Default")
      (node (ref "IC4") (pin "19") (pinfunction "AD6/DCD#/GPIOL2_19") (pintype "bidirectional"))
    )
    (net (code "531") (name "unconnected-(IC4-AD7{slash}RI#{slash}GPIOL3-Pad20)") (class "Default")
      (node (ref "IC4") (pin "20") (pinfunction "AD7/RI#/GPIOL3_20") (pintype "bidirectional"))
    )
    (net (code "532") (name "unconnected-(IC4-TEST-Pad42)") (class "Default")
      (node (ref "IC4") (pin "42") (pinfunction "TEST_42") (pintype "bidirectional"))
    )
    (net (code "533") (name "unconnected-(IC8-NU-Pad7)") (class "Default")
      (node (ref "IC8") (pin "7") (pinfunction "NU_7") (pintype "passive"))
    )
    (net (code "534") (name "unconnected-(IC26-NC-PadA3)") (class "Default")
      (node (ref "IC26") (pin "A3") (pinfunction "NC_A3") (pintype "passive"))
    )
    (net (code "535") (name "unconnected-(IC26-NC-PadF1)") (class "Default")
      (node (ref "IC26") (pin "F1") (pinfunction "NC_F1") (pintype "passive"))
    )
    (net (code "536") (name "unconnected-(IC26-NC-PadF9)") (class "Default")
      (node (ref "IC26") (pin "F9") (pinfunction "NC_F9") (pintype "passive"))
    )
    (net (code "537") (name "unconnected-(IC26-NC-PadH1)") (class "Default")
      (node (ref "IC26") (pin "H1") (pinfunction "NC_H1") (pintype "passive"))
    )
    (net (code "538") (name "unconnected-(IC26-NC-PadH9)") (class "Default")
      (node (ref "IC26") (pin "H9") (pinfunction "NC_H9") (pintype "passive"))
    )
    (net (code "539") (name "unconnected-(IC26-NC-PadJ7)") (class "Default")
      (node (ref "IC26") (pin "J7") (pinfunction "NC_J7") (pintype "passive"))
    )
    (net (code "540") (name "unconnected-(IC26-NC-PadN7)") (class "Default")
      (node (ref "IC26") (pin "N7") (pinfunction "NC_N7") (pintype "passive"))
    )
    (net (code "541") (name "unconnected-(IC26-NF_TDQS#-PadA7)") (class "Default")
      (node (ref "IC26") (pin "A7") (pinfunction "NF_TDQS#_A7") (pintype "output"))
    )
    (net (code "542") (name "unconnected-(IC31A-OUT-Pad1)") (class "Default")
      (node (ref "IC31") (pin "1") (pinfunction "OUT_1") (pintype "output"))
    )
    (net (code "543") (name "unconnected-(IC34A-Y-Pad3)") (class "Default")
      (node (ref "IC34") (pin "3") (pinfunction "Y_3") (pintype "bidirectional"))
    )
    (net (code "544") (name "unconnected-(IC34A-Y0-Pad1)") (class "Default")
      (node (ref "IC34") (pin "1") (pinfunction "Y0_1") (pintype "bidirectional"))
    )
    (net (code "545") (name "unconnected-(IC34A-Y1-Pad5)") (class "Default")
      (node (ref "IC34") (pin "5") (pinfunction "Y1_5") (pintype "bidirectional"))
    )
    (net (code "546") (name "unconnected-(IC34A-Y2-Pad2)") (class "Default")
      (node (ref "IC34") (pin "2") (pinfunction "Y2_2") (pintype "bidirectional"))
    )
    (net (code "547") (name "unconnected-(IC34A-Y3-Pad4)") (class "Default")
      (node (ref "IC34") (pin "4") (pinfunction "Y3_4") (pintype "bidirectional"))
    )
    (net (code "548") (name "unconnected-(IC35A-X1-Pad14)") (class "Default")
      (node (ref "IC35") (pin "14") (pinfunction "X1_14") (pintype "bidirectional"))
    )
    (net (code "549") (name "unconnected-(IC35A-Y2-Pad2)") (class "Default")
      (node (ref "IC35") (pin "2") (pinfunction "Y2_2") (pintype "bidirectional"))
    )
    (net (code "550") (name "unconnected-(IC35A-Y3-Pad4)") (class "Default")
      (node (ref "IC35") (pin "4") (pinfunction "Y3_4") (pintype "bidirectional"))
    )
    (net (code "551") (name "unconnected-(IC39A-Y-Pad3)") (class "Default")
      (node (ref "IC39") (pin "3") (pinfunction "Y_3") (pintype "bidirectional"))
    )
    (net (code "552") (name "unconnected-(IC39A-Y0-Pad1)") (class "Default")
      (node (ref "IC39") (pin "1") (pinfunction "Y0_1") (pintype "bidirectional"))
    )
    (net (code "553") (name "unconnected-(IC39A-Y1-Pad5)") (class "Default")
      (node (ref "IC39") (pin "5") (pinfunction "Y1_5") (pintype "bidirectional"))
    )
    (net (code "554") (name "unconnected-(IC39A-Y2-Pad2)") (class "Default")
      (node (ref "IC39") (pin "2") (pinfunction "Y2_2") (pintype "bidirectional"))
    )
    (net (code "555") (name "unconnected-(IC39A-Y3-Pad4)") (class "Default")
      (node (ref "IC39") (pin "4") (pinfunction "Y3_4") (pintype "bidirectional"))
    )
    (net (code "556") (name "unconnected-(IC40A-X1-Pad14)") (class "Default")
      (node (ref "IC40") (pin "14") (pinfunction "X1_14") (pintype "bidirectional"))
    )
    (net (code "557") (name "unconnected-(IC40A-Y2-Pad2)") (class "Default")
      (node (ref "IC40") (pin "2") (pinfunction "Y2_2") (pintype "bidirectional"))
    )
    (net (code "558") (name "unconnected-(IC40A-Y3-Pad4)") (class "Default")
      (node (ref "IC40") (pin "4") (pinfunction "Y3_4") (pintype "bidirectional"))
    )
    (net (code "559") (name "unconnected-(IC44A-QH*-Pad9)") (class "Default")
      (node (ref "IC44") (pin "9") (pinfunction "QH*_9") (pintype "tri_state"))
    )
    (net (code "560") (name "unconnected-(K1B-S-Pad4)") (class "Default")
      (node (ref "K1") (pin "4") (pinfunction "S_4") (pintype "passive"))
    )
    (net (code "561") (name "unconnected-(K1C-O-Pad7)") (class "Default")
      (node (ref "K1") (pin "7") (pinfunction "O_7") (pintype "passive"))
    )
    (net (code "562") (name "unconnected-(K1C-P-Pad6)") (class "Default")
      (node (ref "K1") (pin "6") (pinfunction "P_6") (pintype "passive"))
    )
    (net (code "563") (name "unconnected-(K1C-S-Pad5)") (class "Default")
      (node (ref "K1") (pin "5") (pinfunction "S_5") (pintype "passive"))
    )
    (net (code "564") (name "unconnected-(K3B-S-Pad4)") (class "Default")
      (node (ref "K3") (pin "4") (pinfunction "S_4") (pintype "passive"))
    )
    (net (code "565") (name "unconnected-(K3C-O-Pad7)") (class "Default")
      (node (ref "K3") (pin "7") (pinfunction "O_7") (pintype "passive"))
    )
    (net (code "566") (name "unconnected-(K3C-P-Pad6)") (class "Default")
      (node (ref "K3") (pin "6") (pinfunction "P_6") (pintype "passive"))
    )
    (net (code "567") (name "unconnected-(K3C-S-Pad5)") (class "Default")
      (node (ref "K3") (pin "5") (pinfunction "S_5") (pintype "passive"))
    )
    (net (code "568") (name "unconnected-(QG1-E{slash}D-Pad1)") (class "Default")
      (node (ref "QG1") (pin "1") (pinfunction "E/D_1") (pintype "input"))
    )
    (net (code "569") (name "unconnected-(U2A-IO_L1P_HSWAPEN_0-PadC4)") (class "Default")
      (node (ref "U2") (pin "C4") (pinfunction "IO_L1P_HSWAPEN_0_C4") (pintype "bidirectional"))
    )
    (net (code "570") (name "unconnected-(U2A-IO_L2N_0-PadA5)") (class "Default")
      (node (ref "U2") (pin "A5") (pinfunction "IO_L2N_0_A5") (pintype "bidirectional"))
    )
    (net (code "571") (name "unconnected-(U2A-IO_L4N_0-PadA6)") (class "Default")
      (node (ref "U2") (pin "A6") (pinfunction "IO_L4N_0_A6") (pintype "bidirectional"))
    )
    (net (code "572") (name "unconnected-(U2A-IO_L4P_0-PadB6)") (class "Default")
      (node (ref "U2") (pin "B6") (pinfunction "IO_L4P_0_B6") (pintype "bidirectional"))
    )
    (net (code "573") (name "unconnected-(U2A-IO_L5N_0-PadE6)") (class "Default")
      (node (ref "U2") (pin "E6") (pinfunction "IO_L5N_0_E6") (pintype "bidirectional"))
    )
    (net (code "574") (name "unconnected-(U2A-IO_L5P_0-PadF7)") (class "Default")
      (node (ref "U2") (pin "F7") (pinfunction "IO_L5P_0_F7") (pintype "bidirectional"))
    )
    (net (code "575") (name "unconnected-(U2A-IO_L6P_0-PadC7)") (class "Default")
      (node (ref "U2") (pin "C7") (pinfunction "IO_L6P_0_C7") (pintype "bidirectional"))
    )
    (net (code "576") (name "unconnected-(U2A-IO_L36N_GCLK14_0-PadE8)") (class "Default")
      (node (ref "U2") (pin "E8") (pinfunction "IO_L36N_GCLK14_0_E8") (pintype "bidirectional"))
    )
    (net (code "577") (name "unconnected-(U2A-IO_L36P_GCLK15_0-PadE7)") (class "Default")
      (node (ref "U2") (pin "E7") (pinfunction "IO_L36P_GCLK15_0_E7") (pintype "bidirectional"))
    )
    (net (code "578") (name "unconnected-(U2A-IO_L37P_GCLK13_0-PadE10)") (class "Default")
      (node (ref "U2") (pin "E10") (pinfunction "IO_L37P_GCLK13_0_E10") (pintype "bidirectional"))
    )
    (net (code "579") (name "unconnected-(U2A-IO_L38N_VREF_0-PadC8)") (class "Default")
      (node (ref "U2") (pin "C8") (pinfunction "IO_L38N_VREF_0_C8") (pintype "bidirectional"))
    )
    (net (code "580") (name "unconnected-(U2A-IO_L38P_0-PadD8)") (class "Default")
      (node (ref "U2") (pin "D8") (pinfunction "IO_L38P_0_D8") (pintype "bidirectional"))
    )
    (net (code "581") (name "unconnected-(U2A-IO_L39N_0-PadA11)") (class "Default")
      (node (ref "U2") (pin "A11") (pinfunction "IO_L39N_0_A11") (pintype "bidirectional"))
    )
    (net (code "582") (name "unconnected-(U2A-IO_L40N_0-PadD9)") (class "Default")
      (node (ref "U2") (pin "D9") (pinfunction "IO_L40N_0_D9") (pintype "bidirectional"))
    )
    (net (code "583") (name "unconnected-(U2A-IO_L62N_VREF_0-PadA12)") (class "Default")
      (node (ref "U2") (pin "A12") (pinfunction "IO_L62N_VREF_0_A12") (pintype "bidirectional"))
    )
    (net (code "584") (name "unconnected-(U2A-IO_L62P_0-PadB12)") (class "Default")
      (node (ref "U2") (pin "B12") (pinfunction "IO_L62P_0_B12") (pintype "bidirectional"))
    )
    (net (code "585") (name "unconnected-(U2A-IO_L63P_SCP7_0-PadC13)") (class "Default")
      (node (ref "U2") (pin "C13") (pinfunction "IO_L63P_SCP7_0_C13") (pintype "bidirectional"))
    )
    (net (code "586") (name "unconnected-(U2A-IO_L64N_SCP4_0-PadE11)") (class "Default")
      (node (ref "U2") (pin "E11") (pinfunction "IO_L64N_SCP4_0_E11") (pintype "bidirectional"))
    )
    (net (code "587") (name "unconnected-(U2A-IO_L64P_SCP5_0-PadF10)") (class "Default")
      (node (ref "U2") (pin "F10") (pinfunction "IO_L64P_SCP5_0_F10") (pintype "bidirectional"))
    )
    (net (code "588") (name "unconnected-(U2B-IO_L1P_A25_1-PadE13)") (class "Default")
      (node (ref "U2") (pin "E13") (pinfunction "IO_L1P_A25_1_E13") (pintype "bidirectional"))
    )
    (net (code "589") (name "unconnected-(U2B-IO_L30N_A20_M1A11_1-PadG11)") (class "Default")
      (node (ref "U2") (pin "G11") (pinfunction "IO_L30N_A20_M1A11_1_G11") (pintype "bidirectional"))
    )
    (net (code "590") (name "unconnected-(U2B-IO_L30P_A21_M1RESET_1-PadF12)") (class "Default")
      (node (ref "U2") (pin "F12") (pinfunction "IO_L30P_A21_M1RESET_1_F12") (pintype "bidirectional"))
    )
    (net (code "591") (name "unconnected-(U2B-IO_L36P_A9_M1BA0_1-PadG14)") (class "Default")
      (node (ref "U2") (pin "G14") (pinfunction "IO_L36P_A9_M1BA0_1_G14") (pintype "bidirectional"))
    )
    (net (code "592") (name "unconnected-(U2B-IO_L38N_A4_M1CLKN_1-PadH11)") (class "Default")
      (node (ref "U2") (pin "H11") (pinfunction "IO_L38N_A4_M1CLKN_1_H11") (pintype "bidirectional"))
    )
    (net (code "593") (name "unconnected-(U2B-IO_L38P_A5_M1CLK_1-PadG12)") (class "Default")
      (node (ref "U2") (pin "G12") (pinfunction "IO_L38P_A5_M1CLK_1_G12") (pintype "bidirectional"))
    )
    (net (code "594") (name "unconnected-(U2B-IO_L39N_M1ODT_1-PadH14)") (class "Default")
      (node (ref "U2") (pin "H14") (pinfunction "IO_L39N_M1ODT_1_H14") (pintype "bidirectional"))
    )
    (net (code "595") (name "unconnected-(U2B-IO_L39P_M1A3_1-PadH13)") (class "Default")
      (node (ref "U2") (pin "H13") (pinfunction "IO_L39P_M1A3_1_H13") (pintype "bidirectional"))
    )
    (net (code "596") (name "unconnected-(U2B-IO_L40N_GCLK10_M1A6_1-PadJ12)") (class "Default")
      (node (ref "U2") (pin "J12") (pinfunction "IO_L40N_GCLK10_M1A6_1_J12") (pintype "bidirectional"))
    )
    (net (code "597") (name "unconnected-(U2B-IO_L40P_GCLK11_M1A5_1-PadJ11)") (class "Default")
      (node (ref "U2") (pin "J11") (pinfunction "IO_L40P_GCLK11_M1A5_1_J11") (pintype "bidirectional"))
    )
    (net (code "598") (name "unconnected-(U2B-IO_L42N_GCLK6_TRDY1_M1LDM_1-PadK11)") (class "Default")
      (node (ref "U2") (pin "K11") (pinfunction "IO_L42N_GCLK6_TRDY1_M1LDM_1_K11") (pintype "bidirectional"))
    )
    (net (code "599") (name "unconnected-(U2B-IO_L42P_GCLK7_M1UDM_1-PadK12)") (class "Default")
      (node (ref "U2") (pin "K12") (pinfunction "IO_L42P_GCLK7_M1UDM_1_K12") (pintype "bidirectional"))
    )
    (net (code "600") (name "unconnected-(U2B-IO_L43P_GCLK5_M1DQ4_1-PadJ14)") (class "Default")
      (node (ref "U2") (pin "J14") (pinfunction "IO_L43P_GCLK5_M1DQ4_1_J14") (pintype "bidirectional"))
    )
    (net (code "601") (name "unconnected-(U2B-IO_L47P_FWE_B_M1DQ0_1-PadL14)") (class "Default")
      (node (ref "U2") (pin "L14") (pinfunction "IO_L47P_FWE_B_M1DQ0_1_L14") (pintype "bidirectional"))
    )
    (net (code "602") (name "unconnected-(U2B-IO_L53P_1-PadL12)") (class "Default")
      (node (ref "U2") (pin "L12") (pinfunction "IO_L53P_1_L12") (pintype "bidirectional"))
    )
    (net (code "603") (name "unconnected-(U2C-CMPCS_B_2-PadL11)") (class "Default")
      (node (ref "U2") (pin "L11") (pinfunction "CMPCS_B_2_L11") (pintype "bidirectional"))
    )
    (net (code "604") (name "unconnected-(U2C-IO_L2N_CMPMOSI_2-PadM11)") (class "Default")
      (node (ref "U2") (pin "M11") (pinfunction "IO_L2N_CMPMOSI_2_M11") (pintype "bidirectional"))
    )
    (net (code "605") (name "unconnected-(U2C-IO_L2P_CMPCLK_2-PadM12)") (class "Default")
      (node (ref "U2") (pin "M12") (pinfunction "IO_L2P_CMPCLK_2_M12") (pintype "bidirectional"))
    )
    (net (code "606") (name "unconnected-(U2C-IO_L13N_D10_2-PadP11)") (class "Default")
      (node (ref "U2") (pin "P11") (pinfunction "IO_L13N_D10_2_P11") (pintype "bidirectional"))
    )
    (net (code "607") (name "unconnected-(U2C-IO_L16P_2-PadL10)") (class "Default")
      (node (ref "U2") (pin "L10") (pinfunction "IO_L16P_2_L10") (pintype "bidirectional"))
    )
    (net (code "608") (name "unconnected-(U2C-IO_L23P_2-PadR9)") (class "Default")
      (node (ref "U2") (pin "R9") (pinfunction "IO_L23P_2_R9") (pintype "bidirectional"))
    )
    (net (code "609") (name "unconnected-(U2C-IO_L29P_GCLK3_2-PadM9)") (class "Default")
      (node (ref "U2") (pin "M9") (pinfunction "IO_L29P_GCLK3_2_M9") (pintype "bidirectional"))
    )
    (net (code "610") (name "unconnected-(U2C-IO_L30P_GCLK1_D13_2-PadP8)") (class "Default")
      (node (ref "U2") (pin "P8") (pinfunction "IO_L30P_GCLK1_D13_2_P8") (pintype "bidirectional"))
    )
    (net (code "611") (name "unconnected-(U2C-IO_L31N_GCLK30_D15_2-PadM7)") (class "Default")
      (node (ref "U2") (pin "M7") (pinfunction "IO_L31N_GCLK30_D15_2_M7") (pintype "bidirectional"))
    )
    (net (code "612") (name "unconnected-(U2C-IO_L62N_D6_2-PadL7)") (class "Default")
      (node (ref "U2") (pin "L7") (pinfunction "IO_L62N_D6_2_L7") (pintype "bidirectional"))
    )
    (net (code "613") (name "unconnected-(U2C-IO_L62P_D5_2-PadL8)") (class "Default")
      (node (ref "U2") (pin "L8") (pinfunction "IO_L62P_D5_2_L8") (pintype "bidirectional"))
    )
    (net (code "614") (name "unconnected-(U2C-IO_L63P_2-PadP4)") (class "Default")
      (node (ref "U2") (pin "P4") (pinfunction "IO_L63P_2_P4") (pintype "bidirectional"))
    )
    (net (code "615") (name "unconnected-(U2C-IO_L64P_D8_2-PadM6)") (class "Default")
      (node (ref "U2") (pin "M6") (pinfunction "IO_L64P_D8_2_M6") (pintype "bidirectional"))
    )
    (net (code "616") (name "unconnected-(U2D-IO_L1P_3-PadM4)") (class "Default")
      (node (ref "U2") (pin "M4") (pinfunction "IO_L1P_3_M4") (pintype "bidirectional"))
    )
    (net (code "617") (name "unconnected-(U2D-IO_L2N_3-PadN4)") (class "Default")
      (node (ref "U2") (pin "N4") (pinfunction "IO_L2N_3_N4") (pintype "bidirectional"))
    )
    (net (code "618") (name "unconnected-(U2D-IO_L2P_3-PadM5)") (class "Default")
      (node (ref "U2") (pin "M5") (pinfunction "IO_L2P_3_M5") (pintype "bidirectional"))
    )
    (net (code "619") (name "unconnected-(U2D-IO_L32N_M3DQ15_3-PadR1)") (class "Default")
      (node (ref "U2") (pin "R1") (pinfunction "IO_L32N_M3DQ15_3_R1") (pintype "bidirectional"))
    )
    (net (code "620") (name "unconnected-(U2D-IO_L32P_M3DQ14_3-PadR2)") (class "Default")
      (node (ref "U2") (pin "R2") (pinfunction "IO_L32P_M3DQ14_3_R2") (pintype "bidirectional"))
    )
    (net (code "621") (name "unconnected-(U2D-IO_L33N_M3DQ13_3-PadP1)") (class "Default")
      (node (ref "U2") (pin "P1") (pinfunction "IO_L33N_M3DQ13_3_P1") (pintype "bidirectional"))
    )
    (net (code "622") (name "unconnected-(U2D-IO_L33P_M3DQ12_3-PadP2)") (class "Default")
      (node (ref "U2") (pin "P2") (pinfunction "IO_L33P_M3DQ12_3_P2") (pintype "bidirectional"))
    )
    (net (code "623") (name "unconnected-(U2D-IO_L34N_M3UDQSN_3-PadN1)") (class "Default")
      (node (ref "U2") (pin "N1") (pinfunction "IO_L34N_M3UDQSN_3_N1") (pintype "bidirectional"))
    )
    (net (code "624") (name "unconnected-(U2D-IO_L34P_M3UDQS_3-PadN3)") (class "Default")
      (node (ref "U2") (pin "N3") (pinfunction "IO_L34P_M3UDQS_3_N3") (pintype "bidirectional"))
    )
    (net (code "625") (name "unconnected-(U2D-IO_L35N_M3DQ11_3-PadM1)") (class "Default")
      (node (ref "U2") (pin "M1") (pinfunction "IO_L35N_M3DQ11_3_M1") (pintype "bidirectional"))
    )
    (net (code "626") (name "unconnected-(U2D-IO_L35P_M3DQ10_3-PadM2)") (class "Default")
      (node (ref "U2") (pin "M2") (pinfunction "IO_L35P_M3DQ10_3_M2") (pintype "bidirectional"))
    )
    (net (code "627") (name "unconnected-(U2D-IO_L36N_M3DQ9_3-PadL1)") (class "Default")
      (node (ref "U2") (pin "L1") (pinfunction "IO_L36N_M3DQ9_3_L1") (pintype "bidirectional"))
    )
    (net (code "628") (name "unconnected-(U2D-IO_L36P_M3DQ8_3-PadL3)") (class "Default")
      (node (ref "U2") (pin "L3") (pinfunction "IO_L36P_M3DQ8_3_L3") (pintype "bidirectional"))
    )
    (net (code "629") (name "unconnected-(U2D-IO_L42P_GCLK25_TRDY2_M3UDM_3-PadK3)") (class "Default")
      (node (ref "U2") (pin "K3") (pinfunction "IO_L42P_GCLK25_TRDY2_M3UDM_3_K3") (pintype "bidirectional"))
    )
    (net (code "630") (name "unconnected-(U2D-IO_L55N_M3A14_3-PadF5)") (class "Default")
      (node (ref "U2") (pin "F5") (pinfunction "IO_L55N_M3A14_3_F5") (pintype "bidirectional"))
    )
    (net (code "631") (name "unconnected-(U2D-IO_L83P_3-PadB3)") (class "Default")
      (node (ref "U2") (pin "B3") (pinfunction "IO_L83P_3_B3") (pintype "bidirectional"))
    )
    (net (code "632") (name "unconnected-(X1-Pad4)") (class "Default")
      (node (ref "X1") (pin "4") (pinfunction "4_4") (pintype "passive"))
    )
  )
)
